# DMFX-1_v1_0.net
KiCad netlist of a schematic drawn in EAGLE
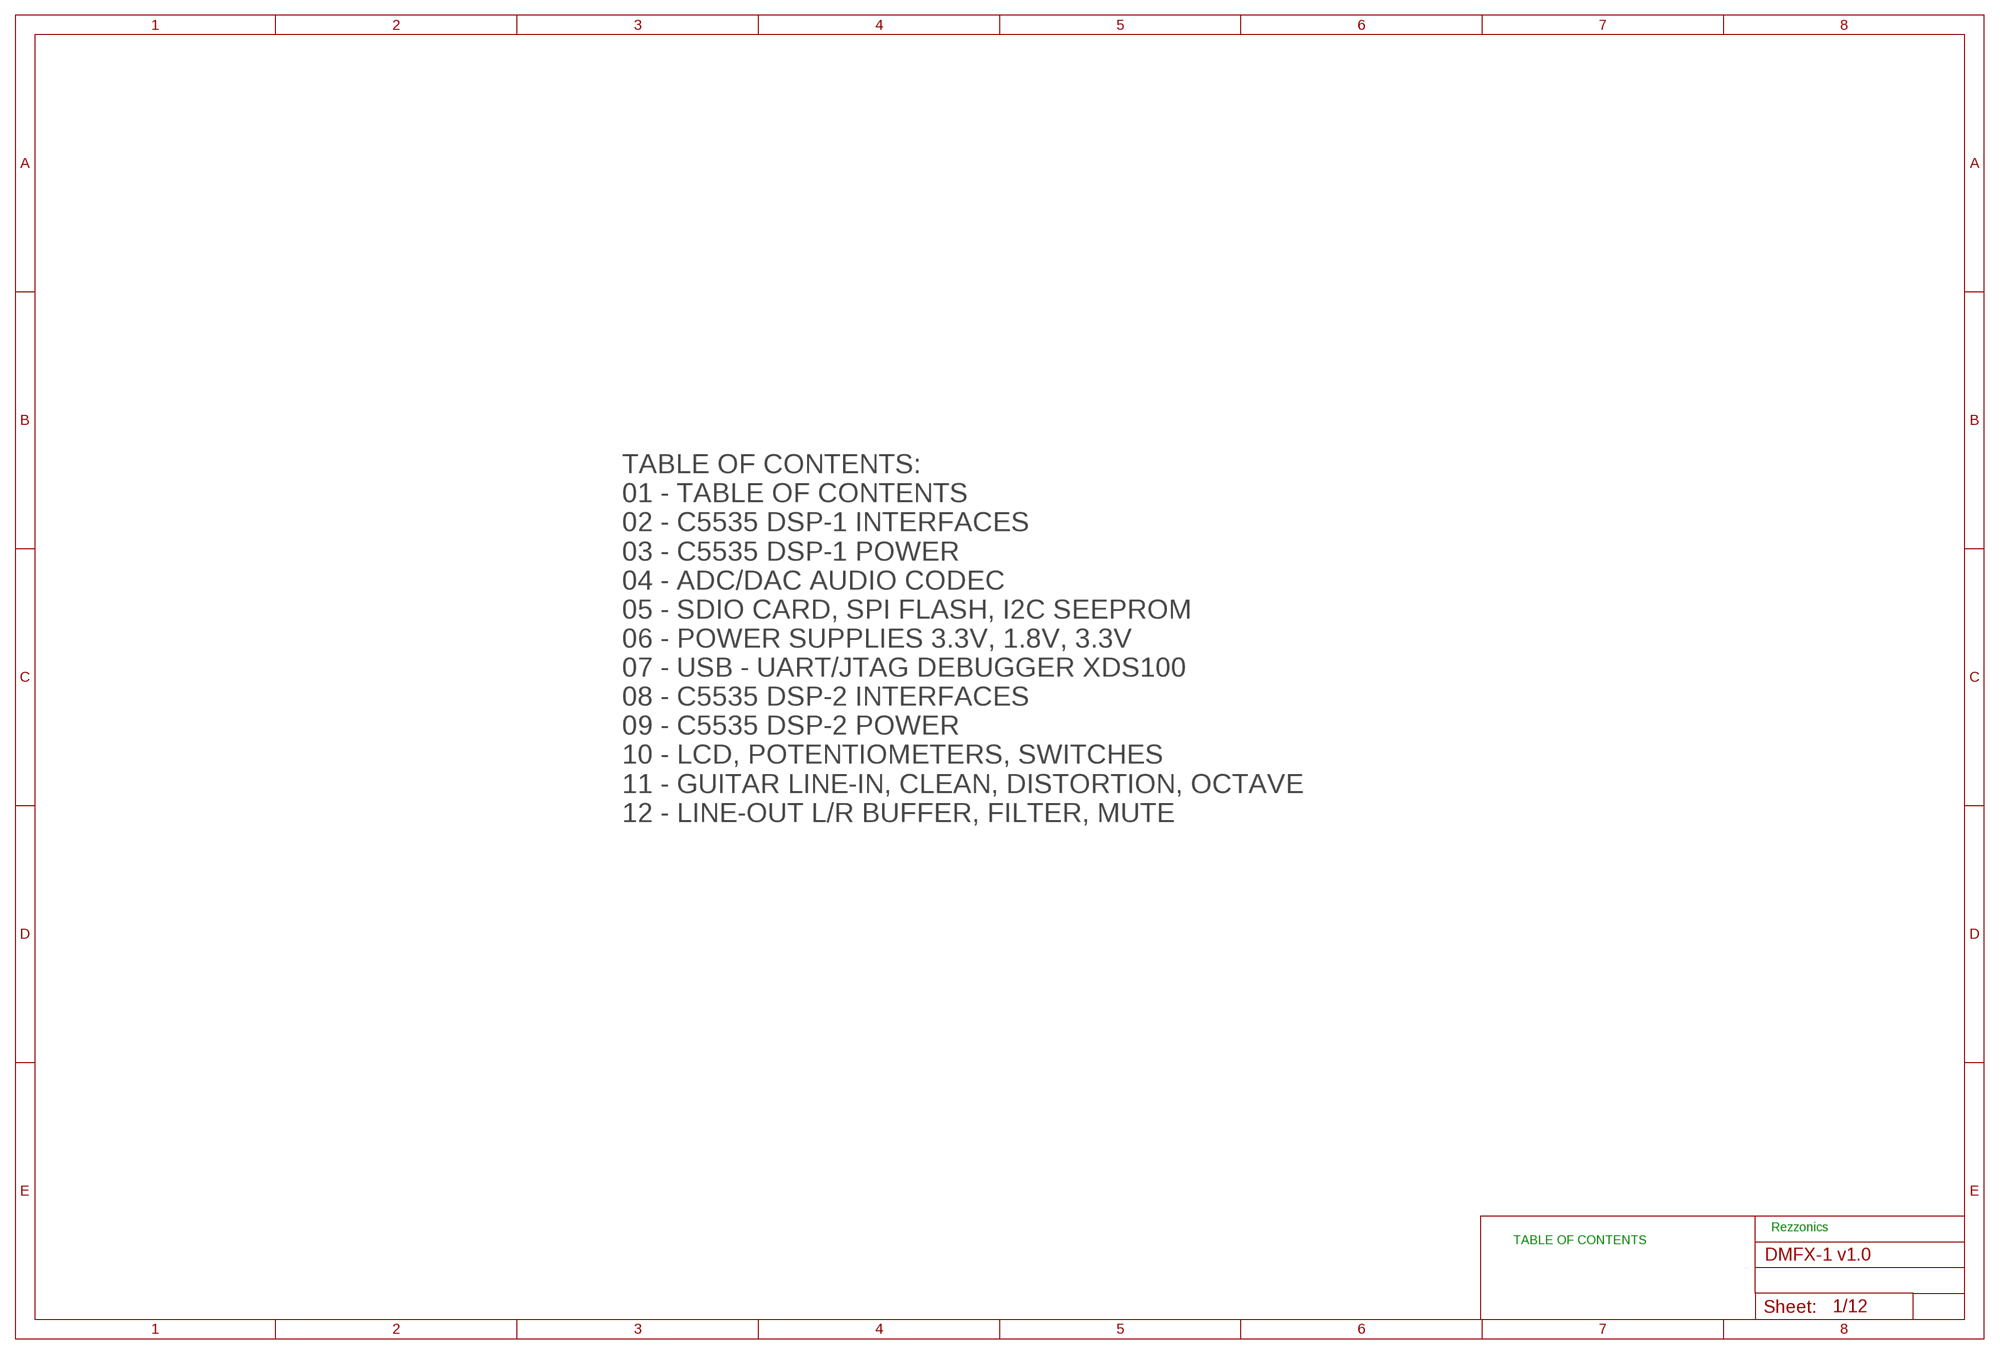
[diagram p0: schematic, sheet 1]
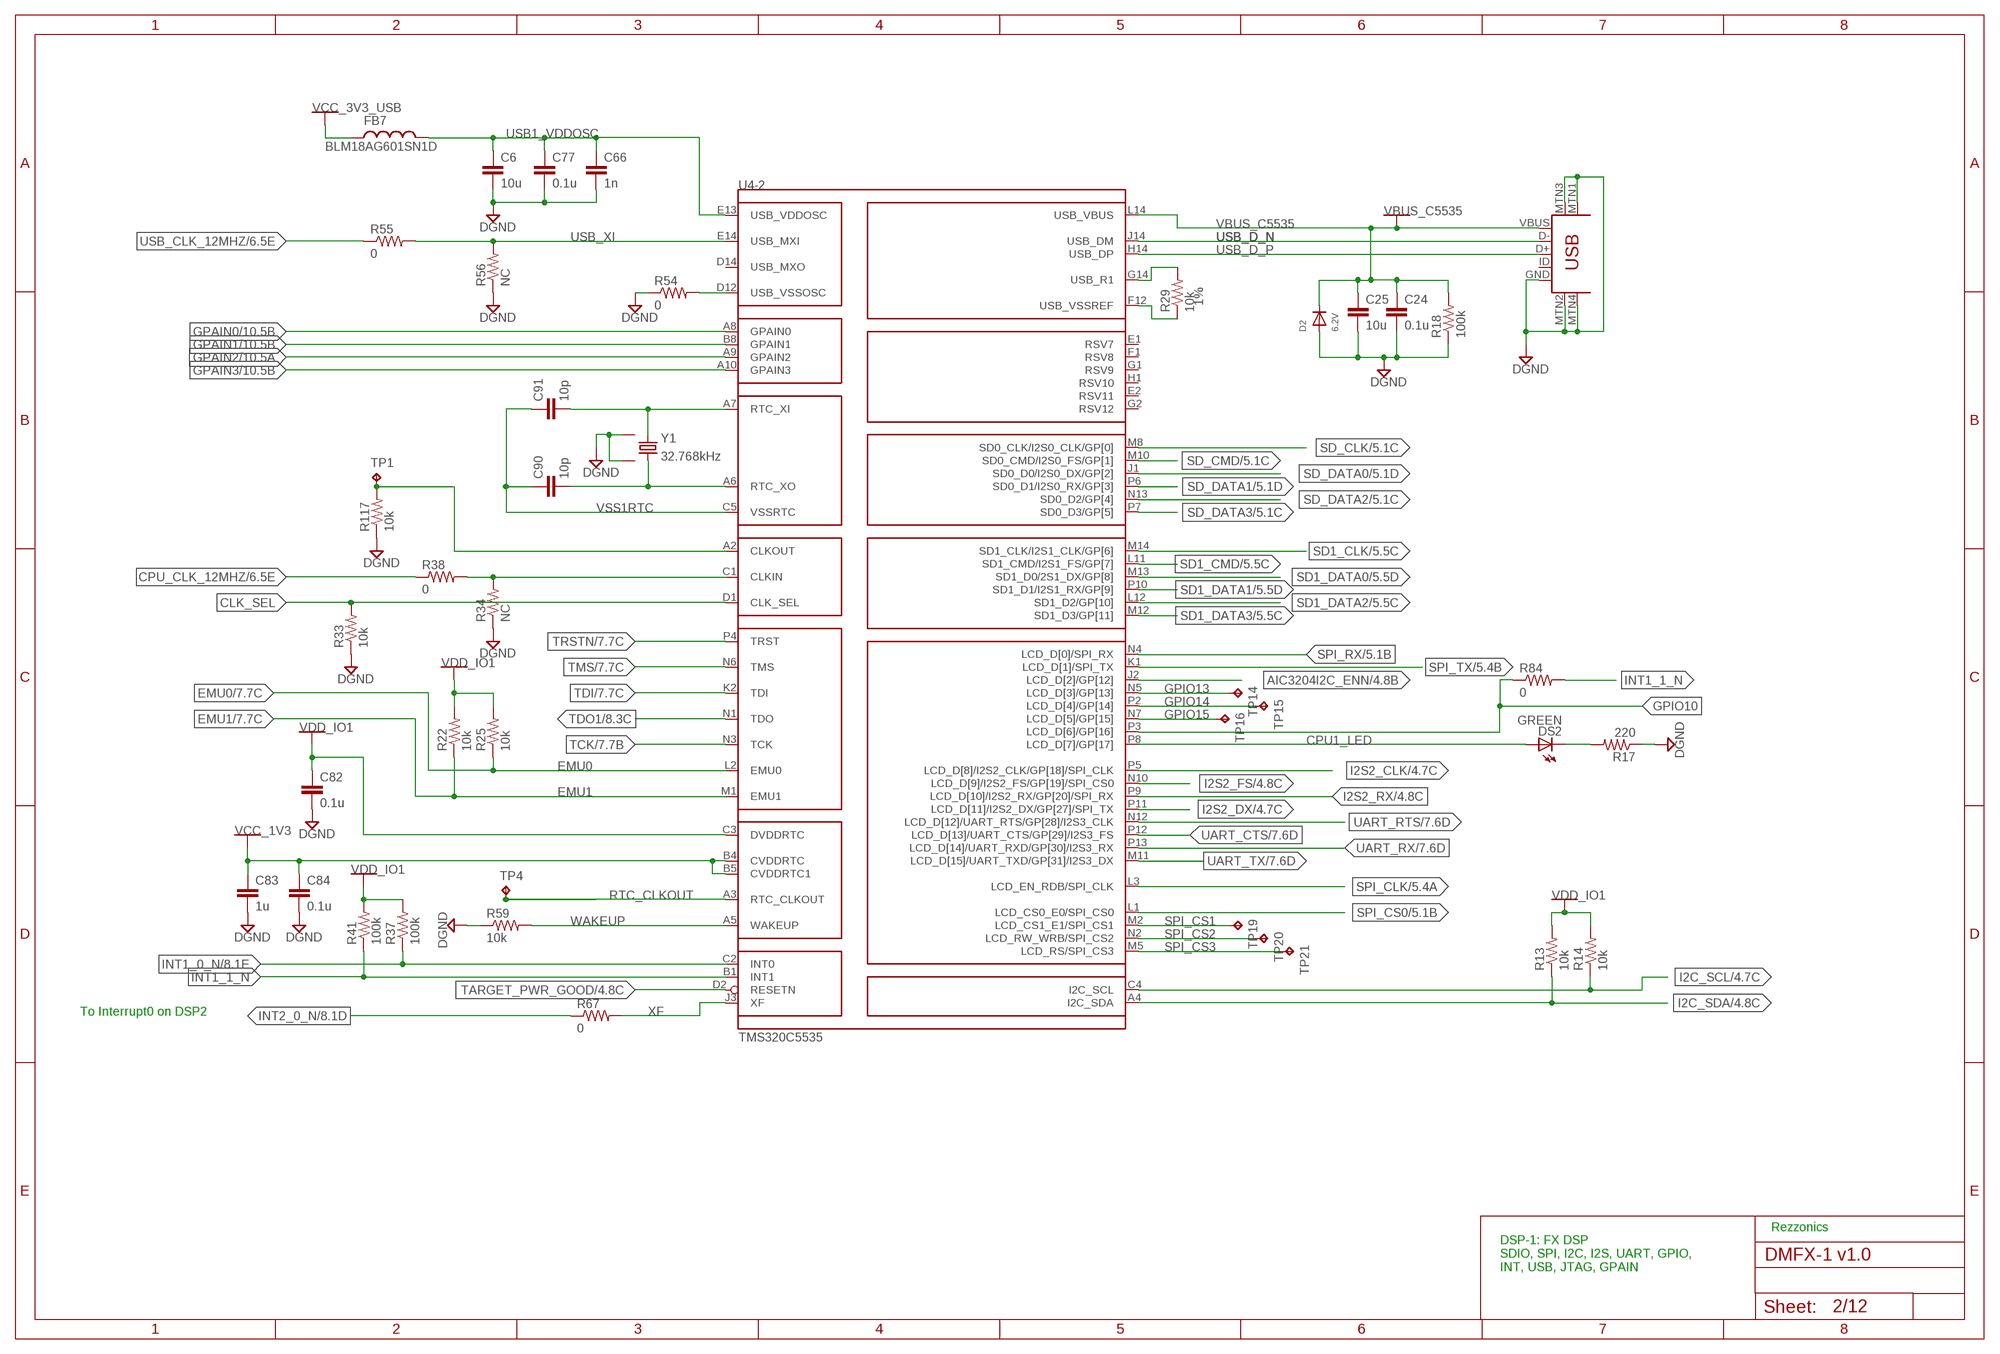
[diagram p1: schematic, sheet 2]
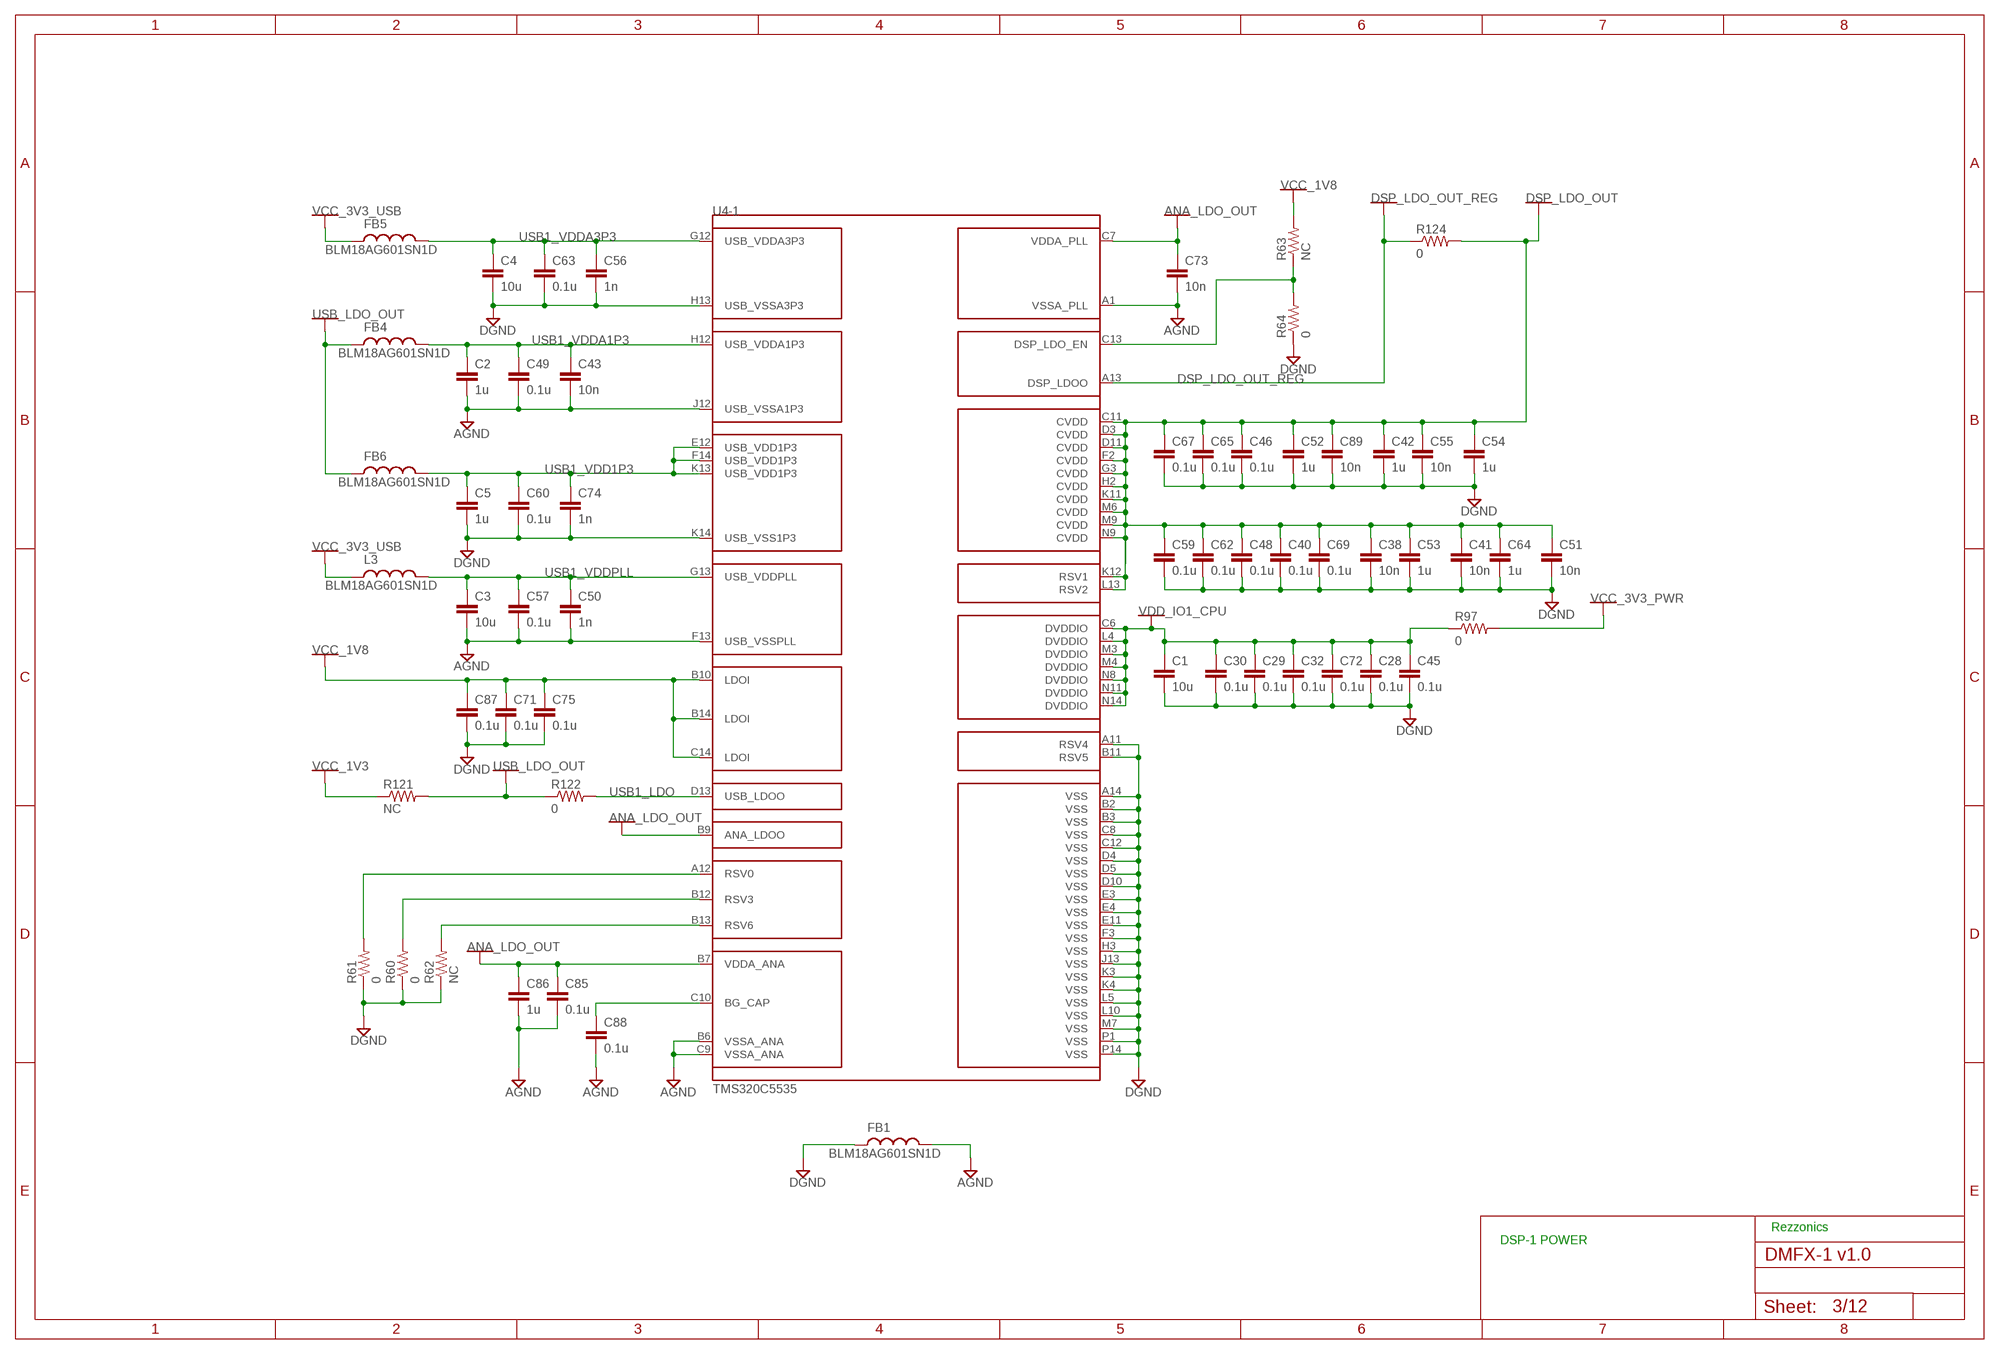
[diagram p2: schematic, sheet 3]
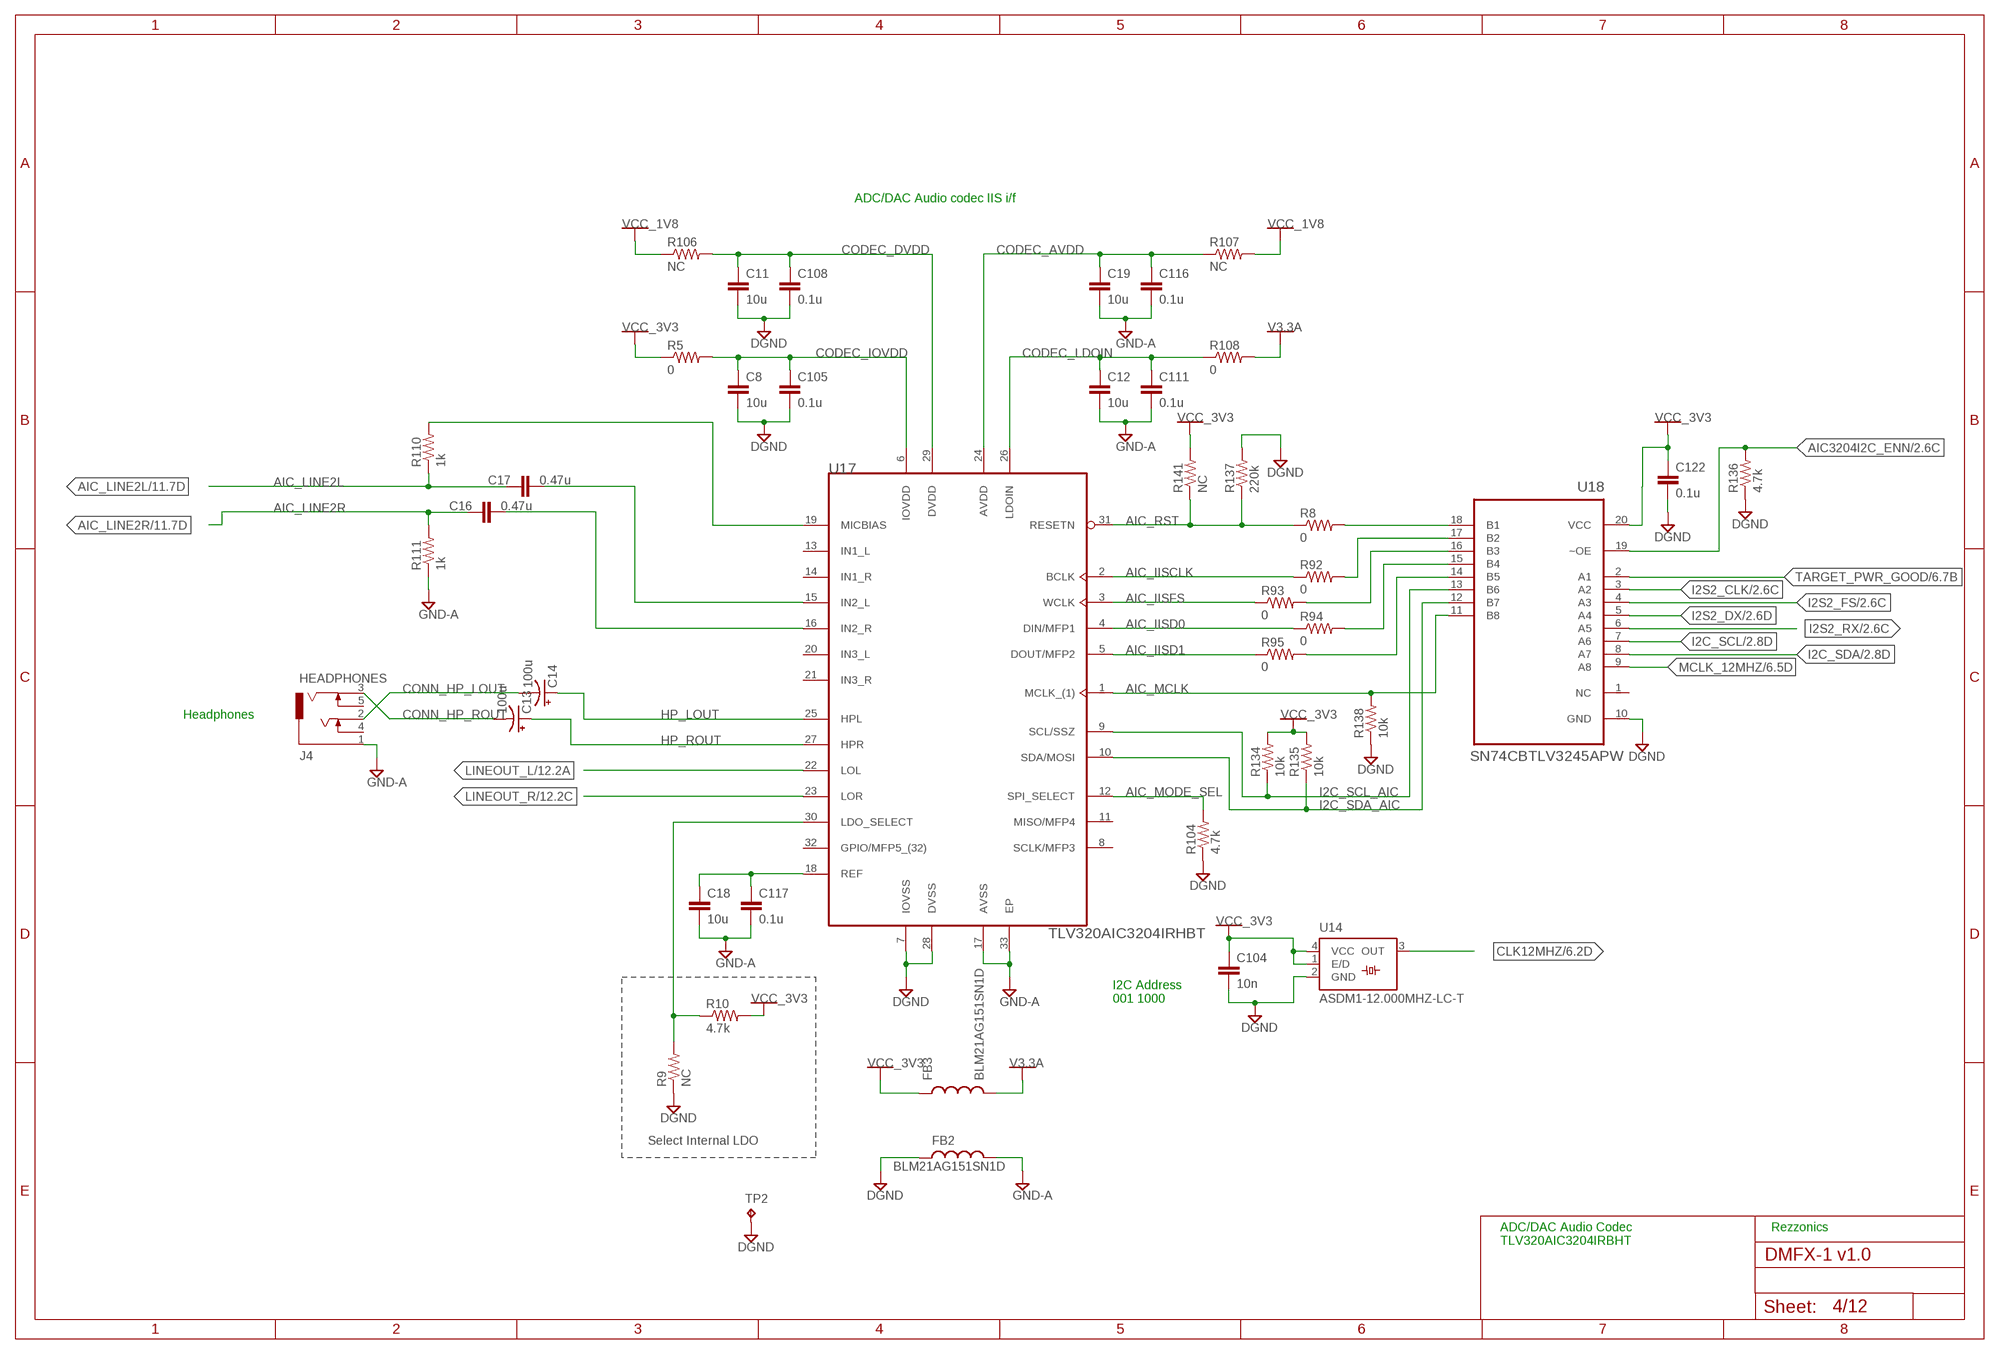
[diagram p3: schematic, sheet 4]
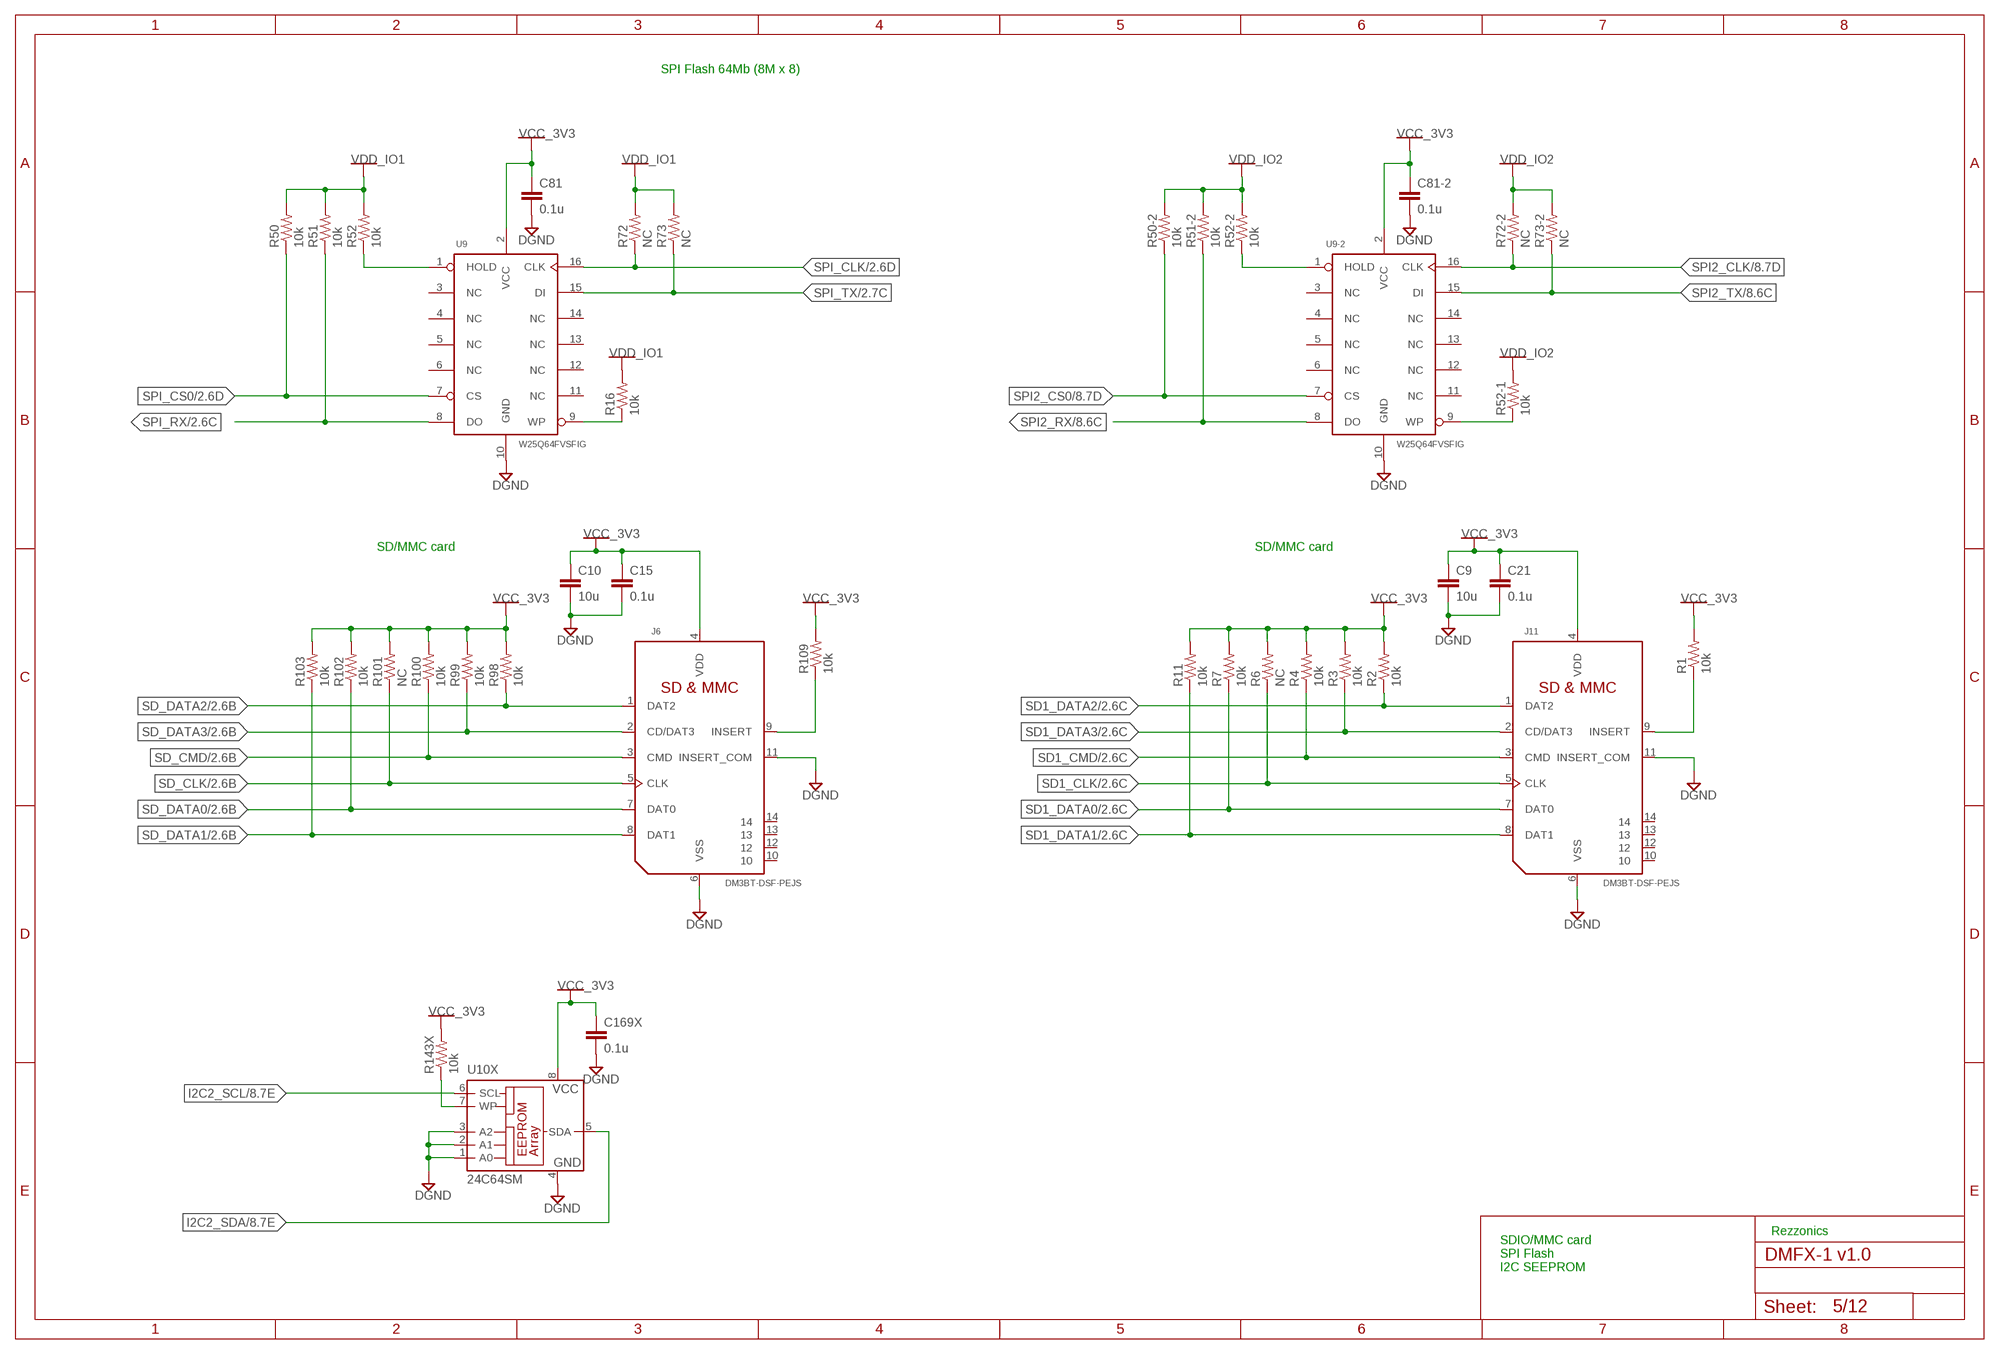
[diagram p4: schematic, sheet 5]
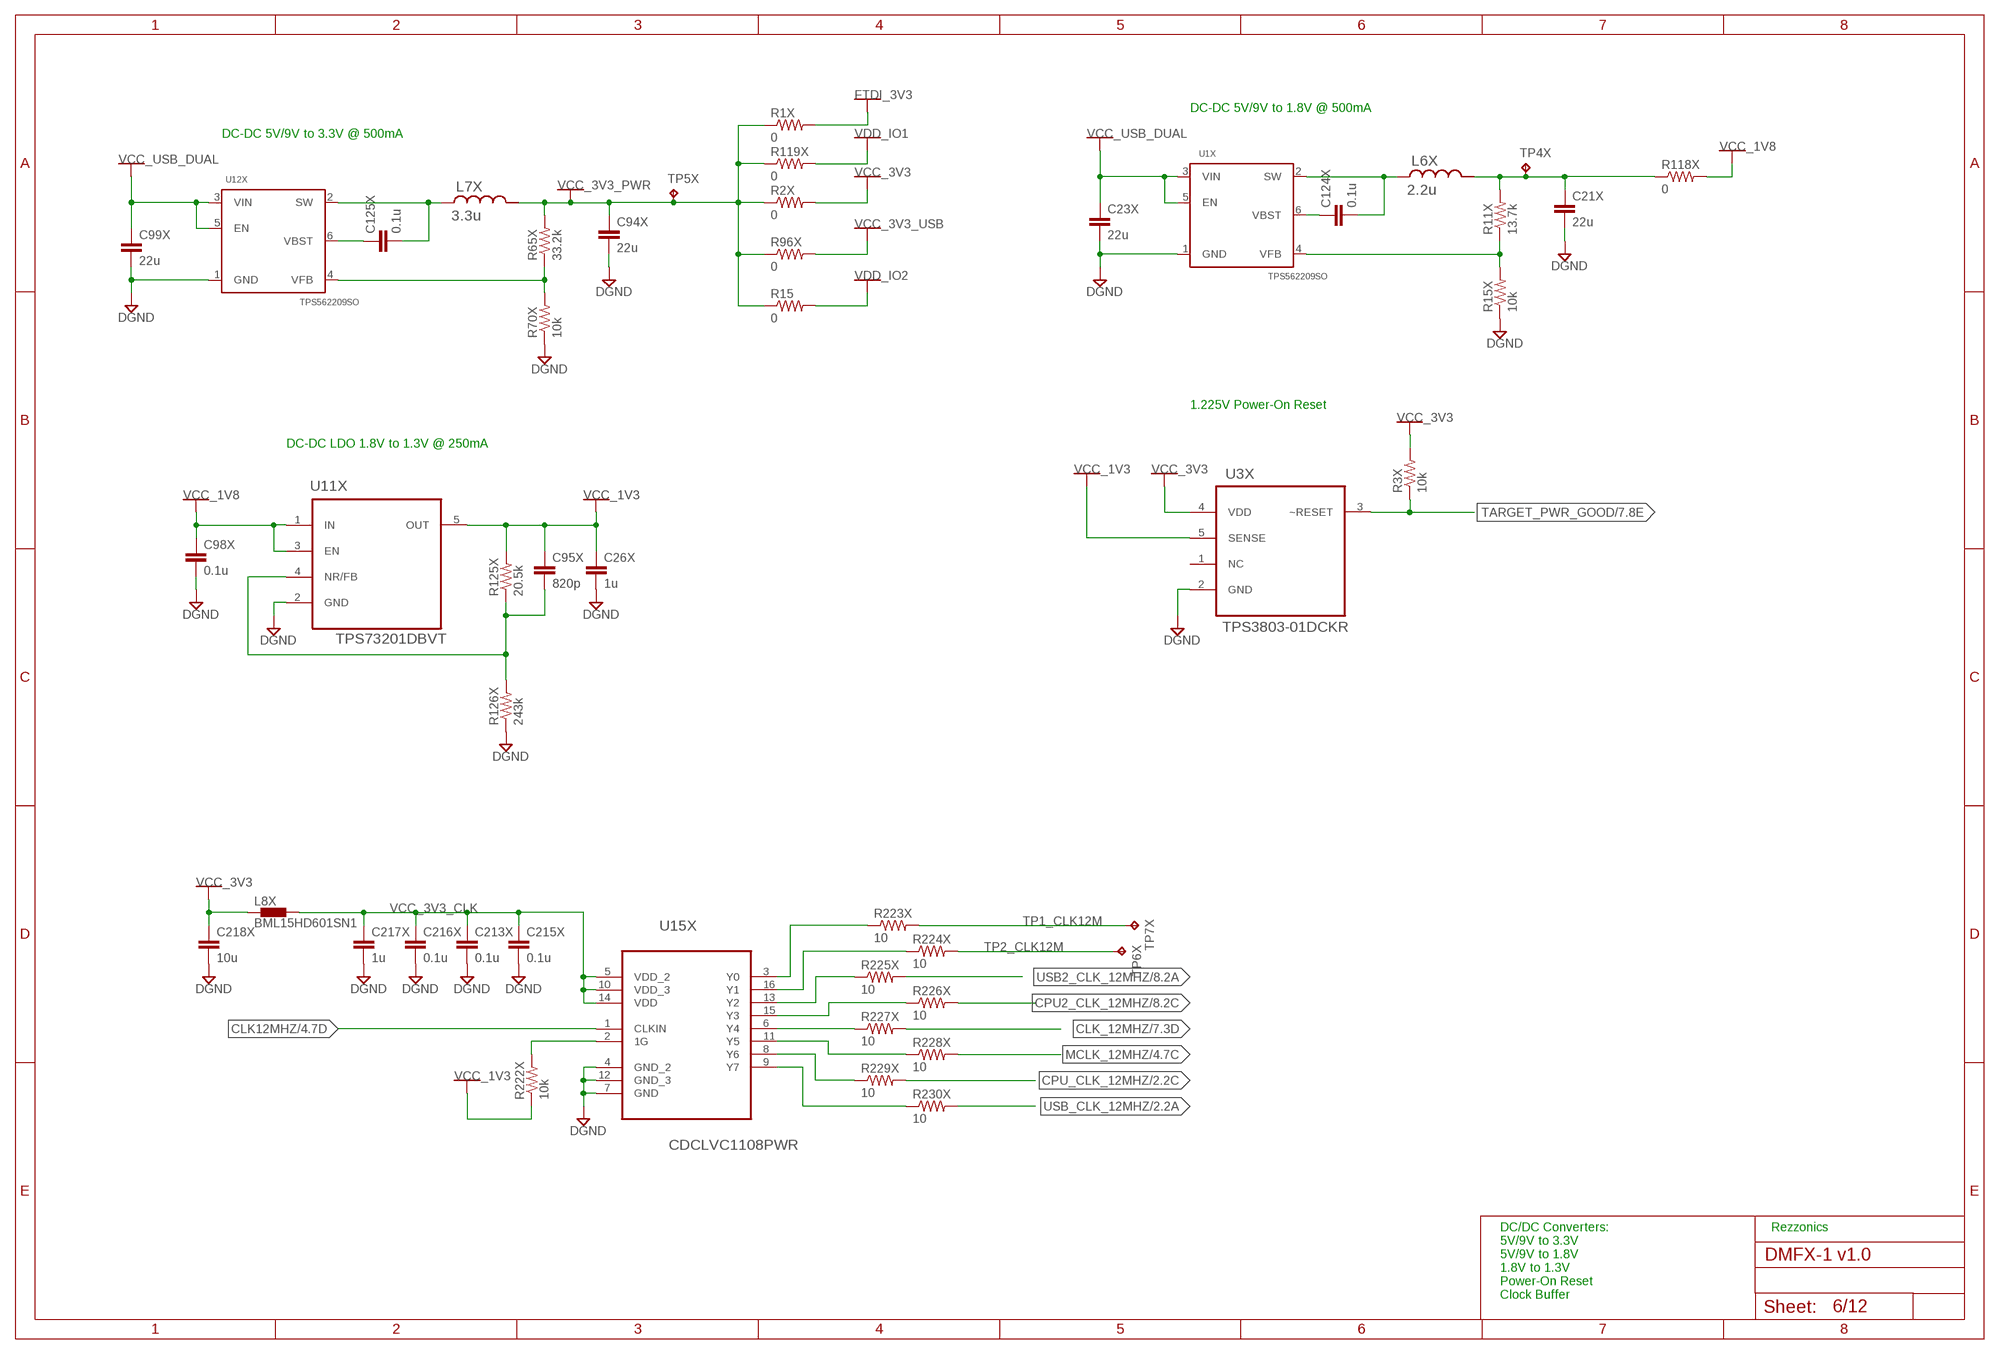
[diagram p5: schematic, sheet 6]
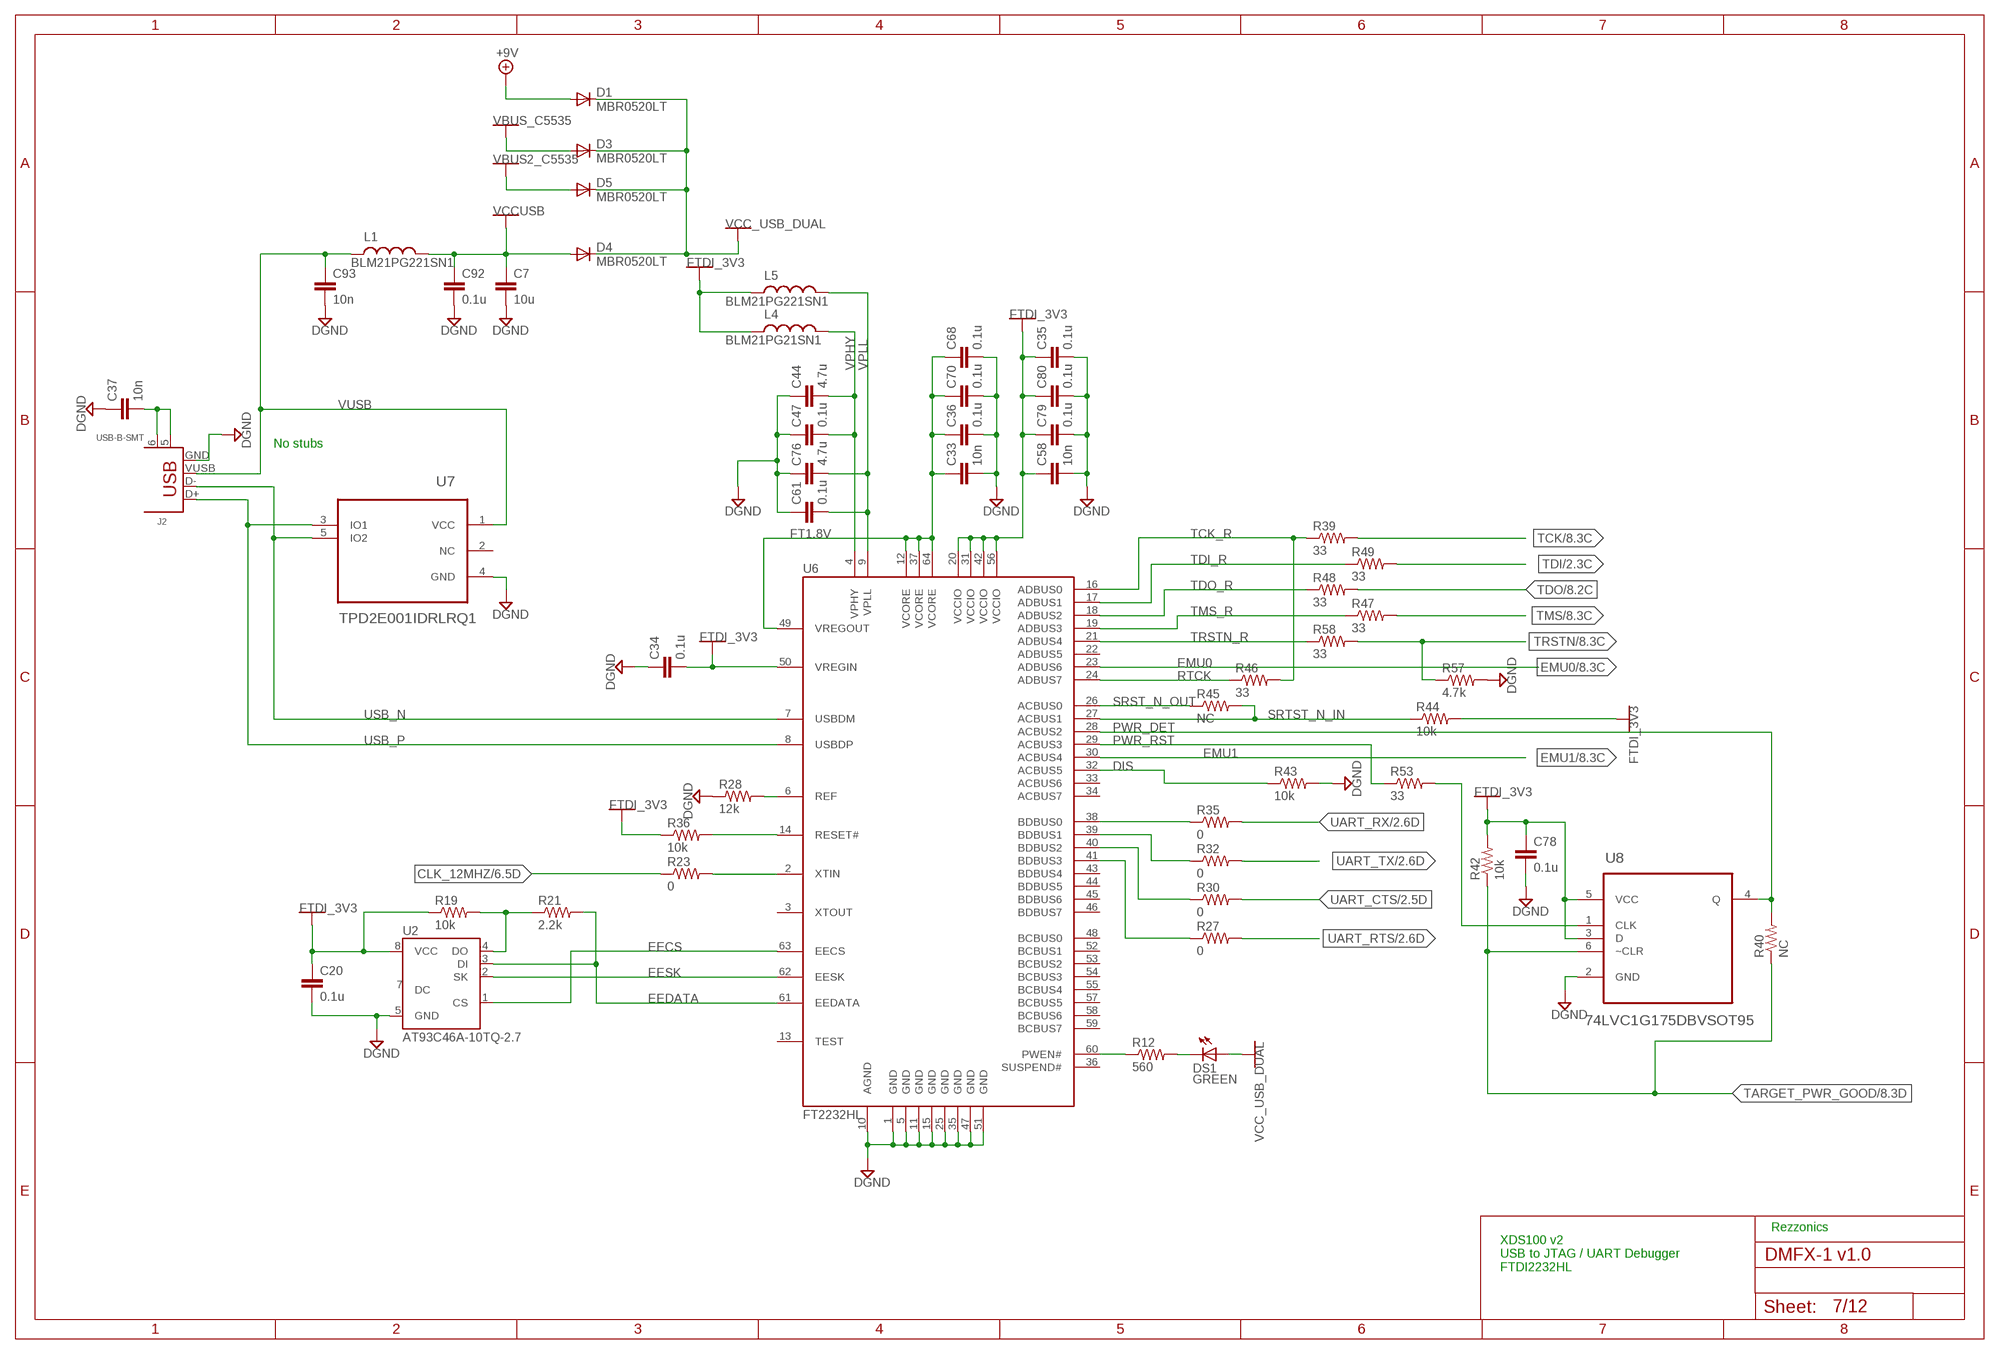
[diagram p6: schematic, sheet 7]
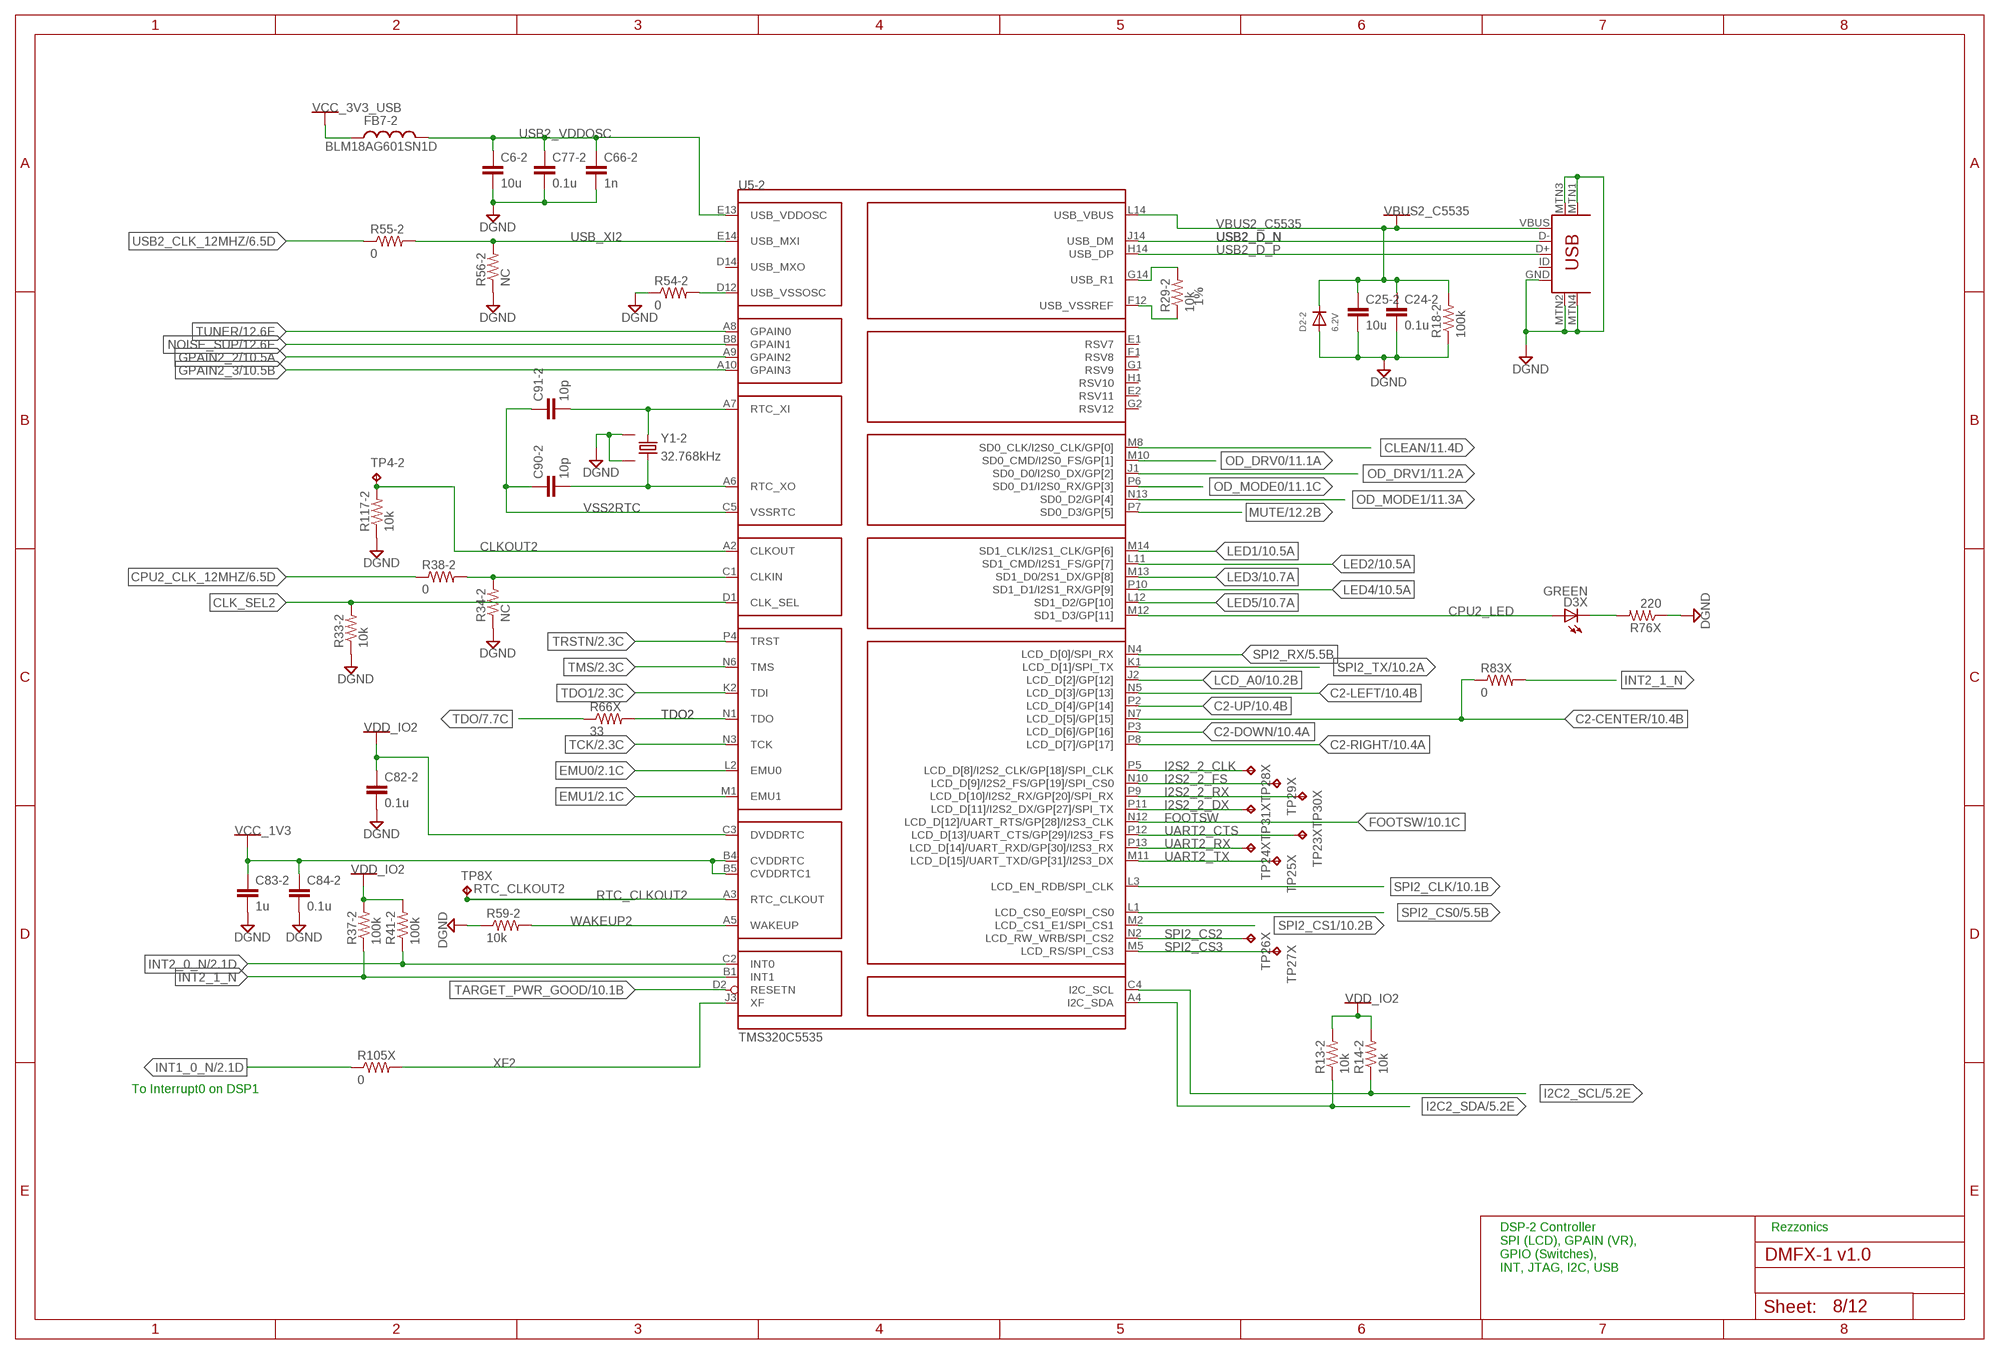
[diagram p7: schematic, sheet 8]
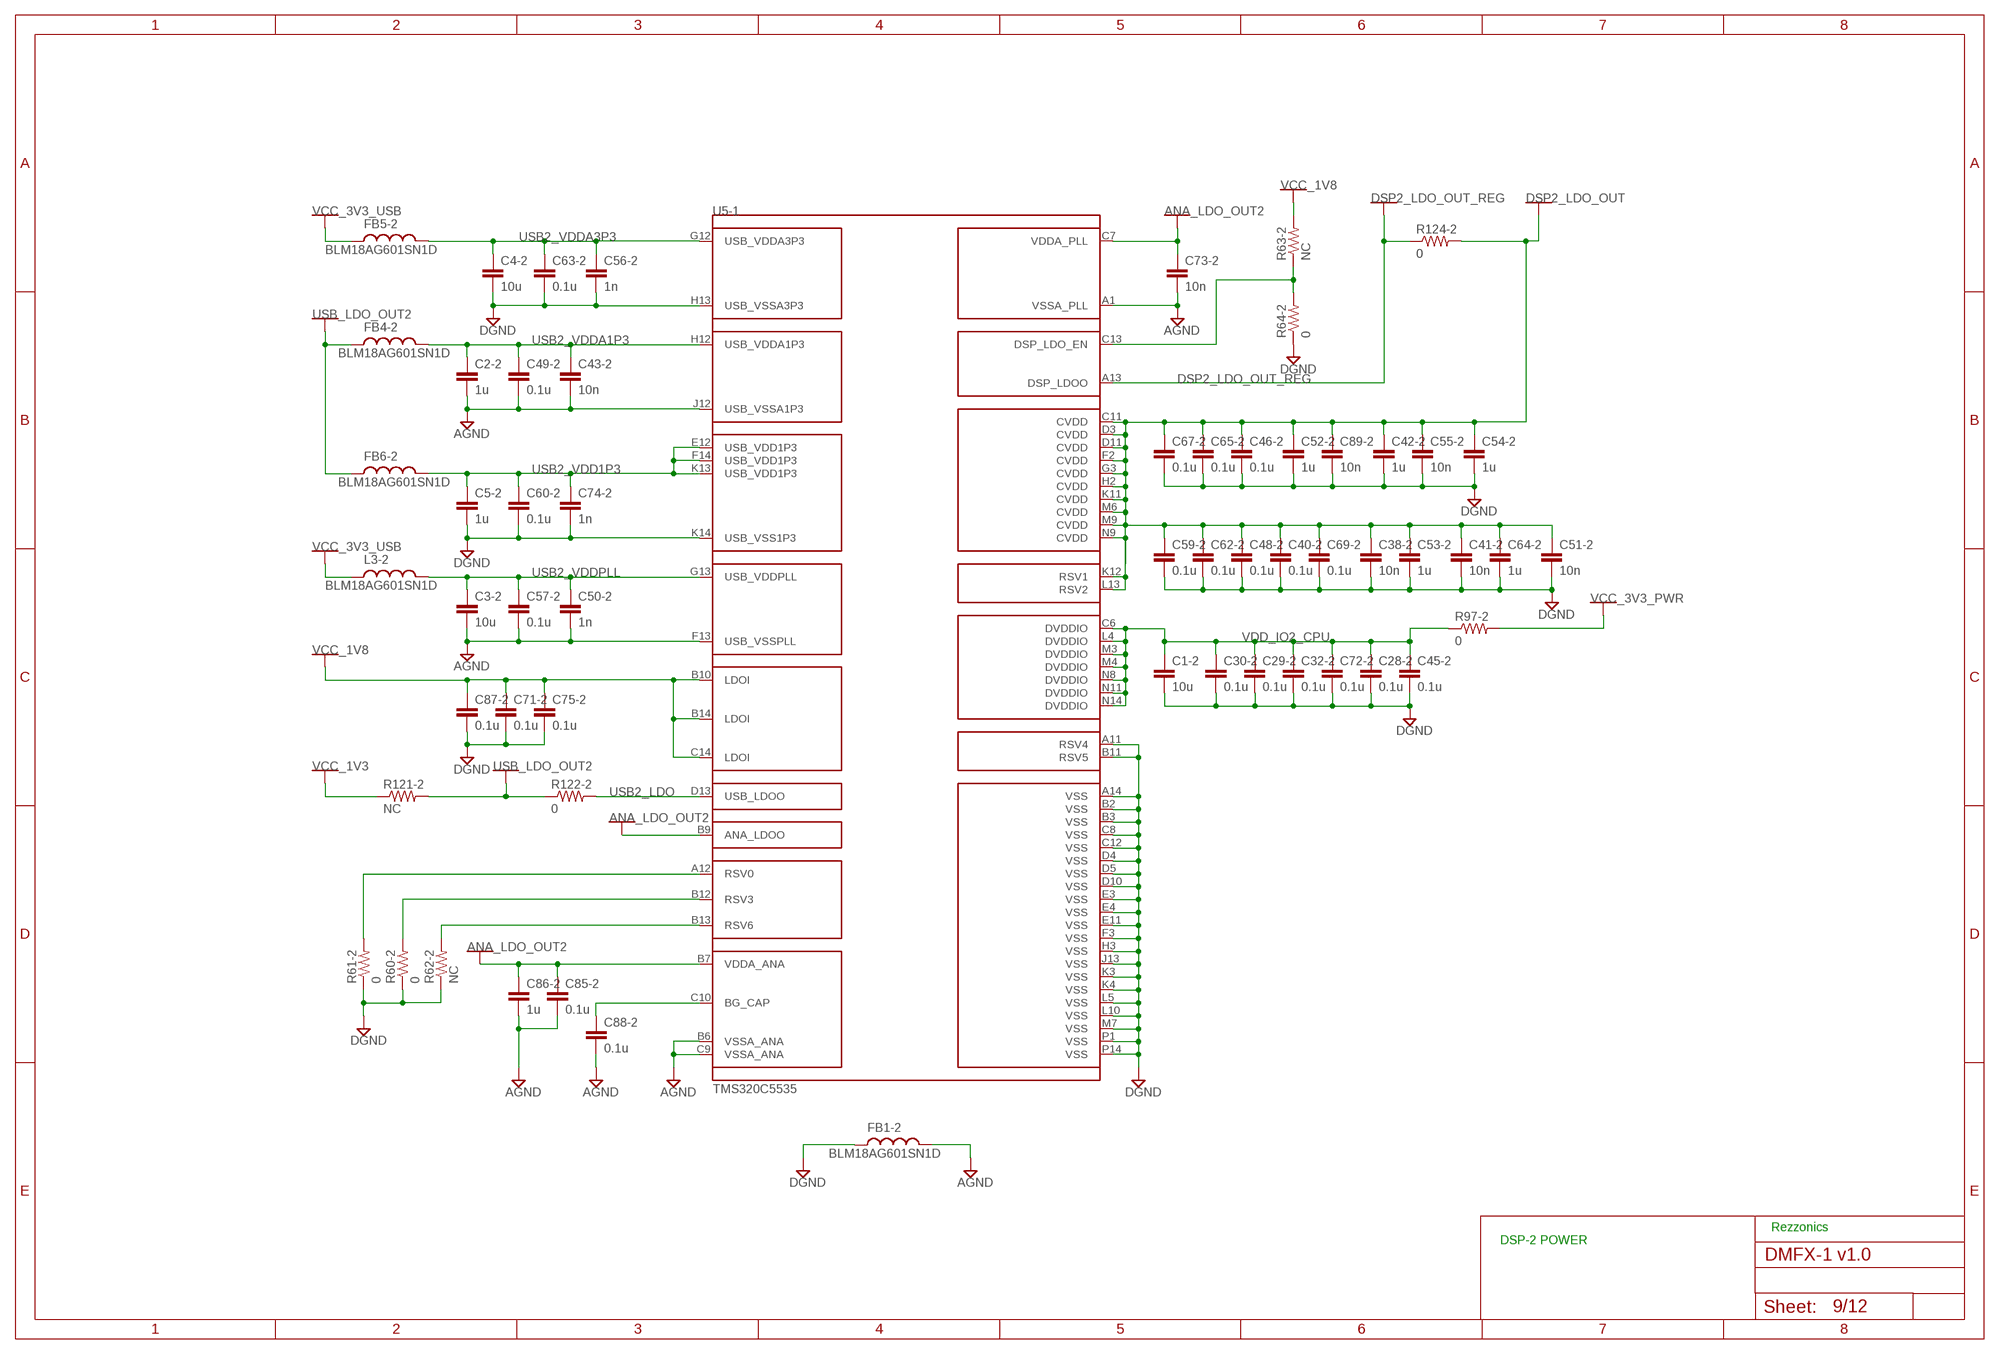
[diagram p8: schematic, sheet 9]
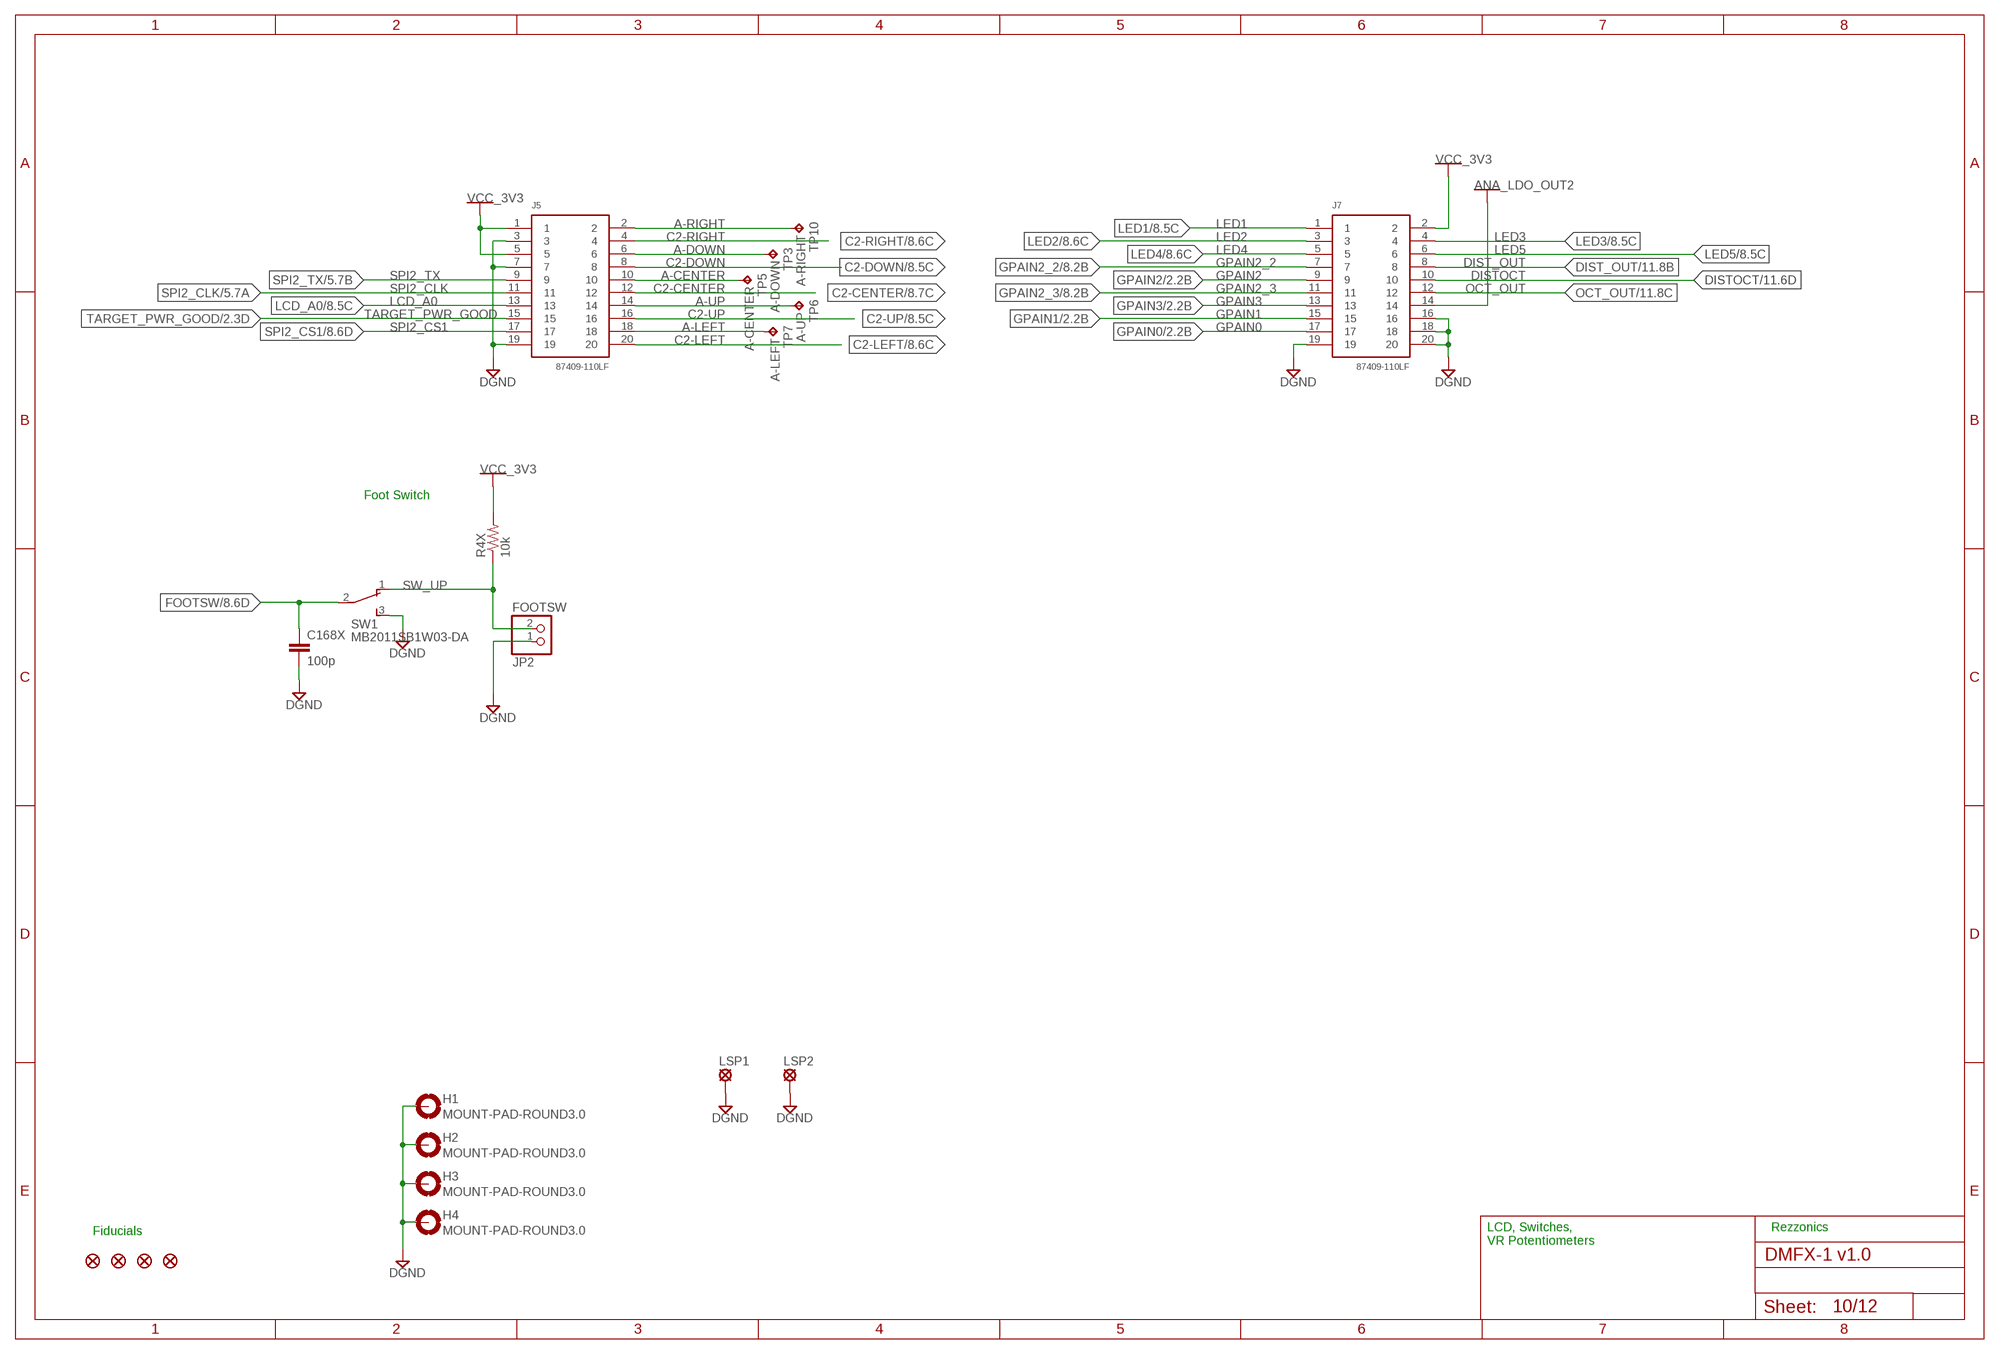
[diagram p9: schematic, sheet 10]
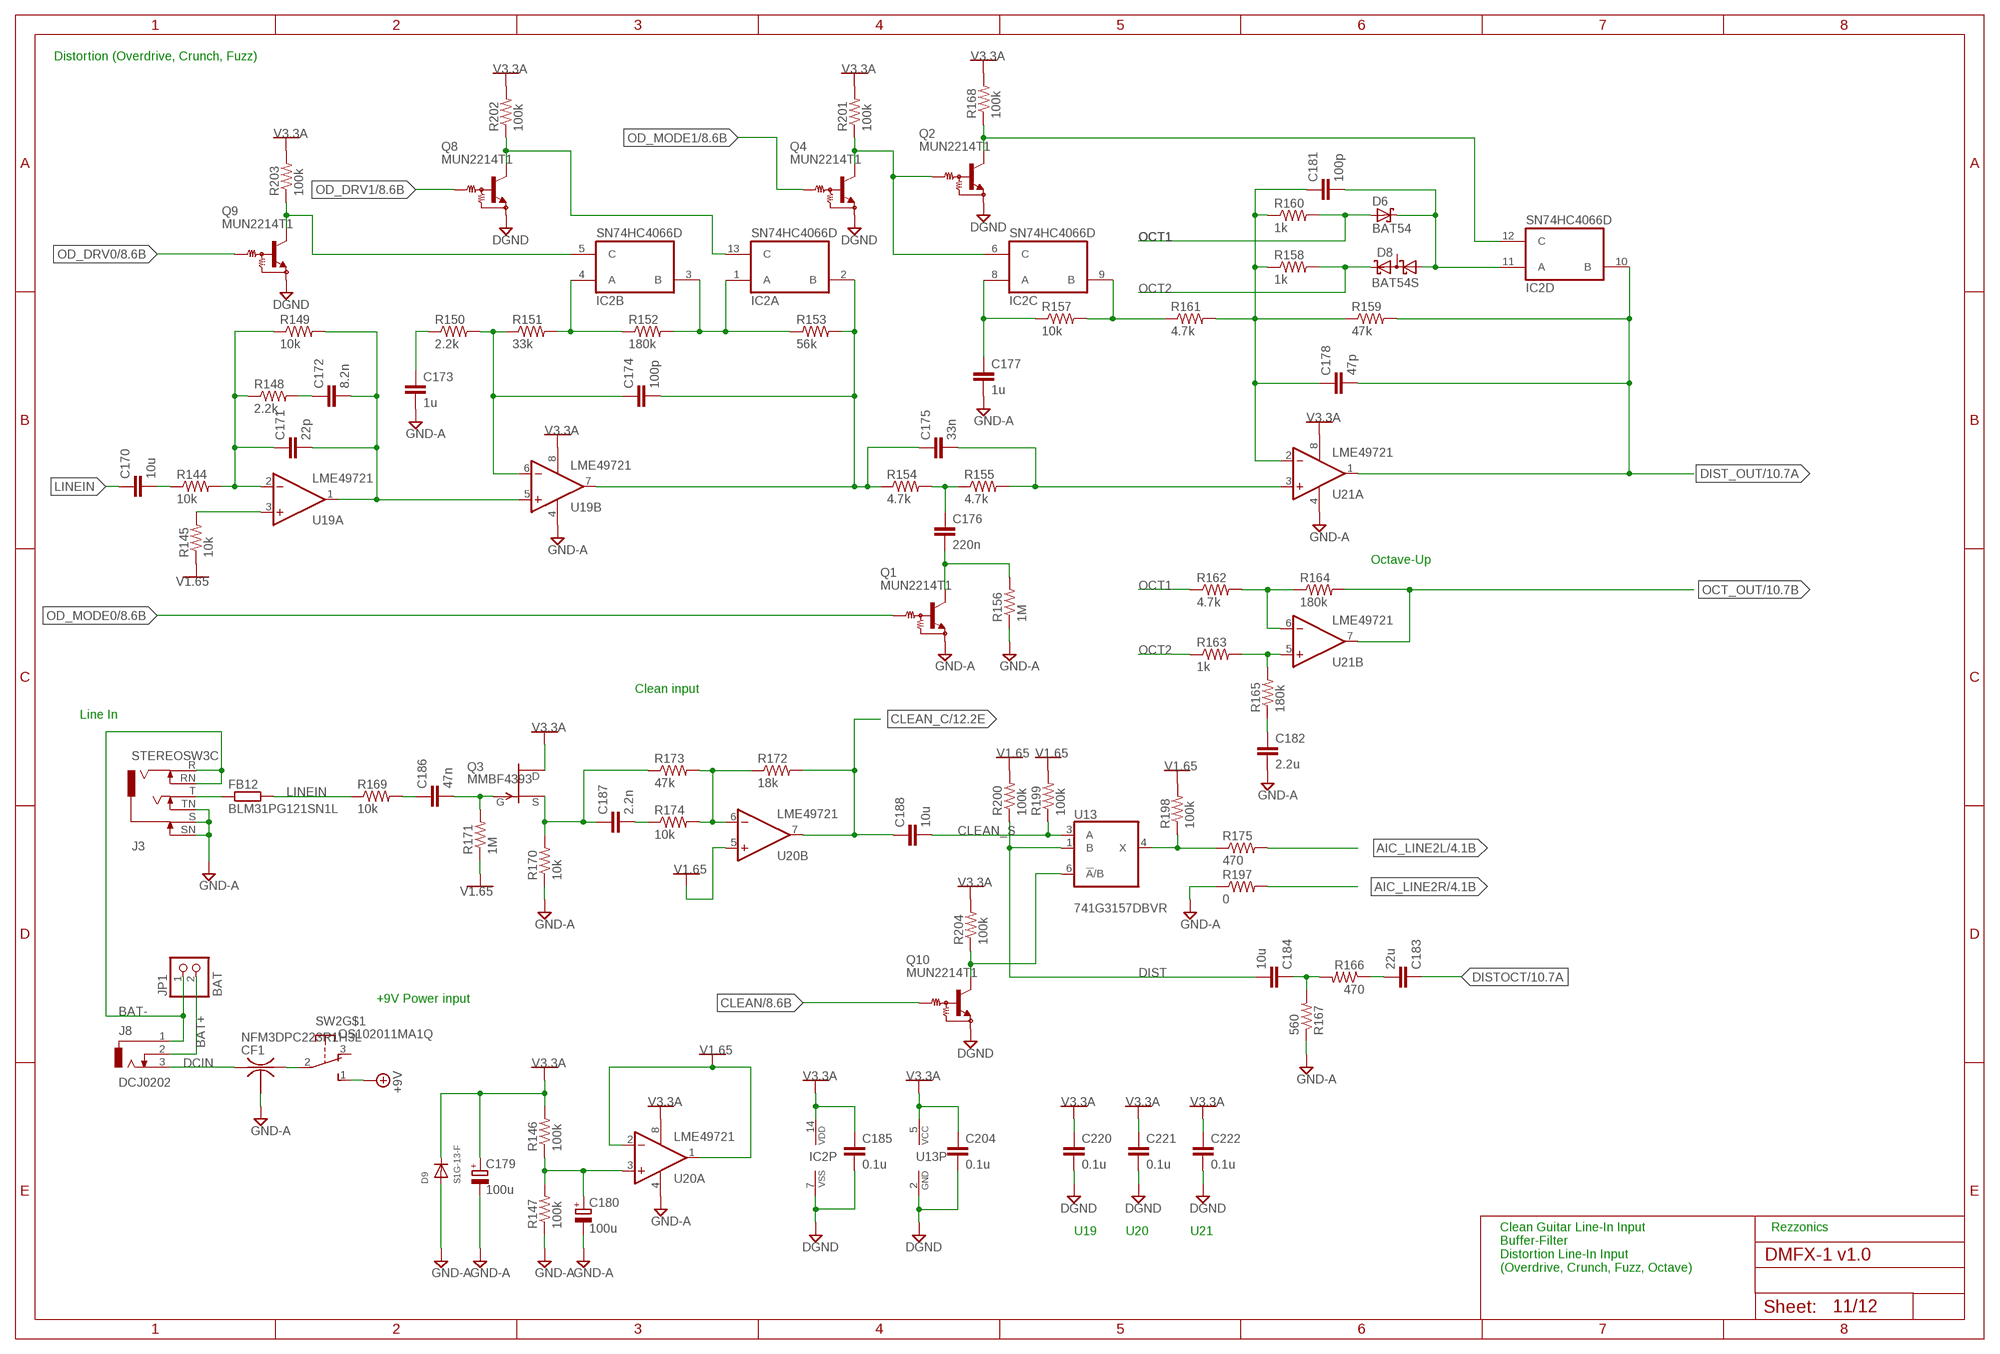
[diagram p10: schematic, sheet 11]
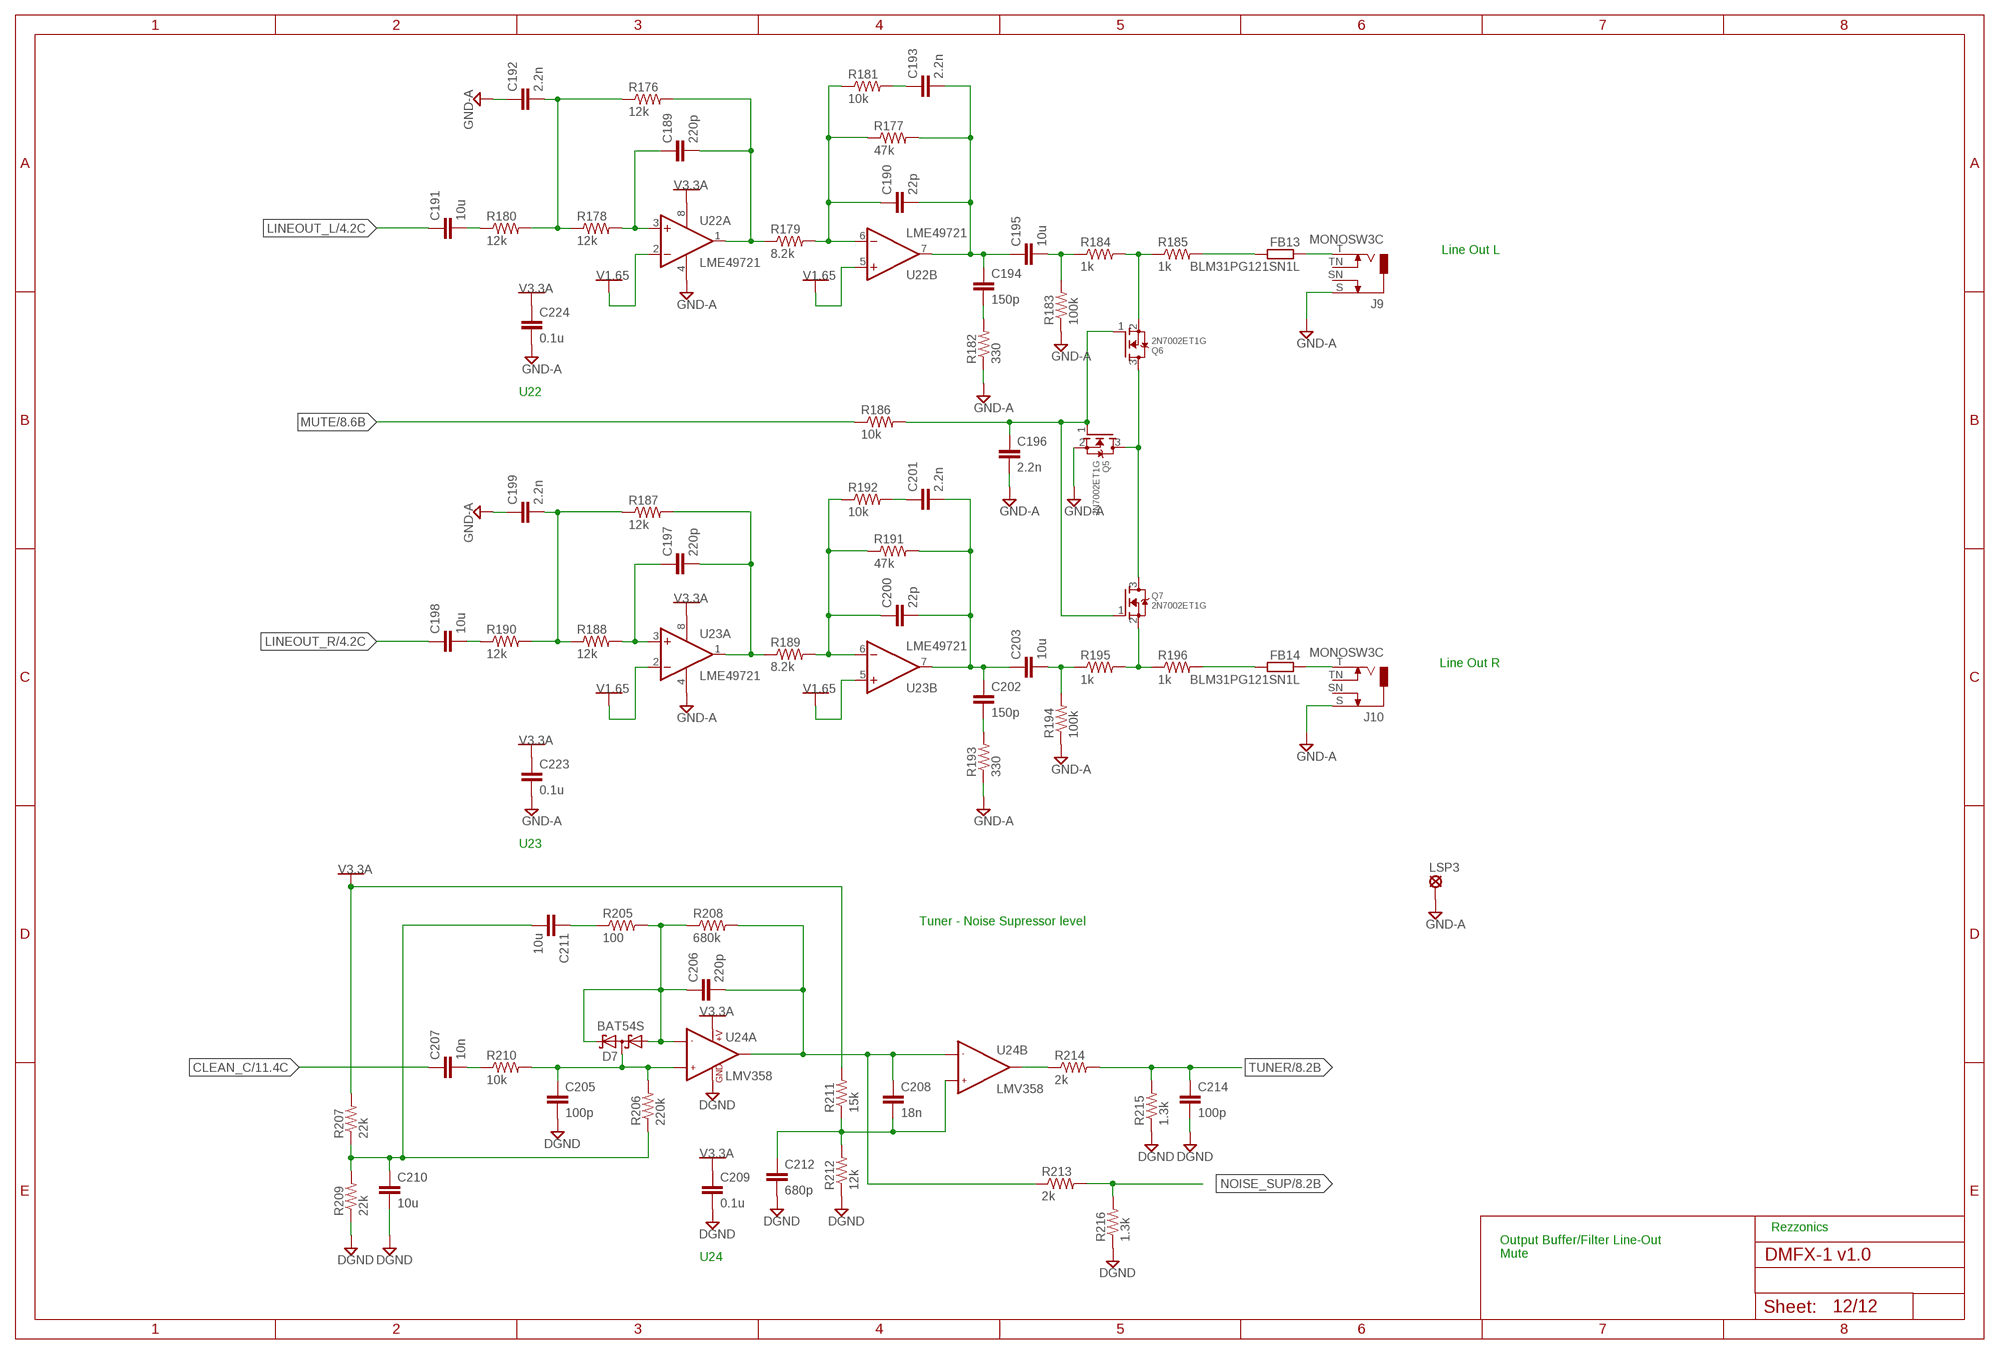
[diagram p11: schematic, sheet 12]

(export (version "E")
  (design (tool "Eeschema 10.0.6"))
  (components
    (comp (ref "C8")
      (value "10u")
      (footprint "eagle-import:C0603K")
      (fields (field (name "MPN") "GRM188R61C106MA73D"))
      (libsource (lib "eagle-import") (part "C-EUC0603K"))
    )
    (comp (ref "C11")
      (value "10u")
      (footprint "eagle-import:C0603K")
      (fields (field (name "MPN") "GRM188R61C106MA73D"))
      (libsource (lib "eagle-import") (part "C-EUC0603K"))
    )
    (comp (ref "C12")
      (value "10u")
      (footprint "eagle-import:C0603K")
      (fields (field (name "MPN") "GRM188R61C106MA73D"))
      (libsource (lib "eagle-import") (part "C-EUC0603K"))
    )
    (comp (ref "C13")
      (value "100u")
      (footprint "eagle-import:1411")
      (fields (field (name "MPN") "ATCC-211B-010-107M-T"))
      (libsource (lib "eagle-import") (part "CPOL-US1411"))
    )
    (comp (ref "C14")
      (value "100u")
      (footprint "eagle-import:1411")
      (fields (field (name "MPN") "ATCC-211B-010-107M-T"))
      (libsource (lib "eagle-import") (part "CPOL-US1411"))
    )
    (comp (ref "C16")
      (value "0.47u")
      (footprint "eagle-import:C0603K")
      (fields (field (name "MPN") "GRM188R71C474KA88D"))
      (libsource (lib "eagle-import") (part "C-EUC0603K"))
    )
    (comp (ref "C17")
      (value "0.47u")
      (footprint "eagle-import:C0603K")
      (fields (field (name "MPN") "GRM188R71C474KA88D"))
      (libsource (lib "eagle-import") (part "C-EUC0603K"))
    )
    (comp (ref "C18")
      (value "10u")
      (footprint "eagle-import:C0603K")
      (fields (field (name "MPN") "GRM188R61C106MA73D"))
      (libsource (lib "eagle-import") (part "C-EUC0603K"))
    )
    (comp (ref "C19")
      (value "10u")
      (footprint "eagle-import:C0603K")
      (fields (field (name "MPN") "GRM188R61C106MA73D"))
      (libsource (lib "eagle-import") (part "C-EUC0603K"))
    )
    (comp (ref "C104")
      (value "10n")
      (footprint "eagle-import:C0402K")
      (fields (field (name "MPN") "GRM155R71E103KA01D"))
      (libsource (lib "eagle-import") (part "resistor_C-EUC0402K"))
    )
    (comp (ref "C105")
      (value "0.1u")
      (footprint "eagle-import:C0402K")
      (fields (field (name "MPN") "GRM155R71C104JA88D"))
      (libsource (lib "eagle-import") (part "resistor_C-EUC0402K"))
    )
    (comp (ref "C108")
      (value "0.1u")
      (footprint "eagle-import:C0402K")
      (fields (field (name "MPN") "GRM155R71C104JA88D"))
      (libsource (lib "eagle-import") (part "resistor_C-EUC0402K"))
    )
    (comp (ref "C111")
      (value "0.1u")
      (footprint "eagle-import:C0402K")
      (fields (field (name "MPN") "GRM155R71C104JA88D"))
      (libsource (lib "eagle-import") (part "resistor_C-EUC0402K"))
    )
    (comp (ref "C116")
      (value "0.1u")
      (footprint "eagle-import:C0402K")
      (fields (field (name "MPN") "GRM155R71C104JA88D"))
      (libsource (lib "eagle-import") (part "resistor_C-EUC0402K"))
    )
    (comp (ref "C117")
      (value "0.1u")
      (footprint "eagle-import:C0402K")
      (fields (field (name "MPN") "GRM155R71C104JA88D"))
      (libsource (lib "eagle-import") (part "resistor_C-EUC0402K"))
    )
    (comp (ref "C122")
      (value "0.1u")
      (footprint "eagle-import:C0402K")
      (fields (field (name "MPN") "GRM155R71C104JA88D"))
      (libsource (lib "eagle-import") (part "resistor_C-EUC0402K"))
    )
    (comp (ref "FB2")
      (value "BLM21AG151SN1D")
      (footprint "eagle-import:0805")
      (libsource (lib "eagle-import") (part "INDUCTOR0805"))
    )
    (comp (ref "FB3")
      (value "BLM21AG151SN1D")
      (footprint "eagle-import:0805")
      (libsource (lib "eagle-import") (part "INDUCTOR0805"))
    )
    (comp (ref "J4")
      (value "HEADPHONES")
      (footprint "eagle-import:AUDIO-JACK-3.5MM-SMD")
      (fields (field (name "MPN") "SJ1-3515-SMT-TR"))
      (libsource (lib "eagle-import") (part "AUDIOJACK3_5SMD"))
    )
    (comp (ref "R5")
      (value "0")
      (footprint "eagle-import:0402-RES")
      (fields (field (name "MPN") "ERJ-2GE0R00X"))
      (libsource (lib "eagle-import") (part "RESISTOR0402-RES"))
    )
    (comp (ref "R8")
      (value "0")
      (footprint "eagle-import:0402-RES")
      (fields (field (name "MPN") "ERJ-2GE0R00X"))
      (libsource (lib "eagle-import") (part "RESISTOR0402-RES"))
    )
    (comp (ref "R9")
      (value "NC")
      (footprint "eagle-import:0603-RES")
      (libsource (lib "eagle-import") (part "RESISTOR0603-RES"))
    )
    (comp (ref "R10")
      (value "4.7k")
      (footprint "eagle-import:0603-RES")
      (fields (field (name "MPN") "ERJ-3EKF4701V"))
      (libsource (lib "eagle-import") (part "RESISTOR0603-RES"))
    )
    (comp (ref "R92")
      (value "0")
      (footprint "eagle-import:0402-RES")
      (fields (field (name "MPN") "ERJ-2GE0R00X"))
      (libsource (lib "eagle-import") (part "RESISTOR0402-RES"))
    )
    (comp (ref "R93")
      (value "0")
      (footprint "eagle-import:0402-RES")
      (fields (field (name "MPN") "ERJ-2GE0R00X"))
      (libsource (lib "eagle-import") (part "RESISTOR0402-RES"))
    )
    (comp (ref "R94")
      (value "0")
      (footprint "eagle-import:0402-RES")
      (fields (field (name "MPN") "ERJ-2GE0R00X"))
      (libsource (lib "eagle-import") (part "RESISTOR0402-RES"))
    )
    (comp (ref "R95")
      (value "0")
      (footprint "eagle-import:0402-RES")
      (fields (field (name "MPN") "ERJ-2GE0R00X"))
      (libsource (lib "eagle-import") (part "RESISTOR0402-RES"))
    )
    (comp (ref "R104")
      (value "4.7k")
      (footprint "eagle-import:0402-RES")
      (fields (field (name "MPN") "ERJ-2RKF4701X"))
      (libsource (lib "eagle-import") (part "RESISTOR0402-RES"))
    )
    (comp (ref "R106")
      (value "NC")
      (footprint "eagle-import:0402-RES")
      (libsource (lib "eagle-import") (part "RESISTOR0402-RES"))
    )
    (comp (ref "R107")
      (value "NC")
      (footprint "eagle-import:0402-RES")
      (libsource (lib "eagle-import") (part "RESISTOR0402-RES"))
    )
    (comp (ref "R108")
      (value "0")
      (footprint "eagle-import:0402-RES")
      (fields (field (name "MPN") "ERJ-2GE0R00X"))
      (libsource (lib "eagle-import") (part "RESISTOR0402-RES"))
    )
    (comp (ref "R110")
      (value "1k")
      (footprint "eagle-import:0402-RES")
      (fields (field (name "MPN") "ERJ-2RKF1001X"))
      (libsource (lib "eagle-import") (part "RESISTOR0402-RES"))
    )
    (comp (ref "R111")
      (value "1k")
      (footprint "eagle-import:0402-RES")
      (fields (field (name "MPN") "ERJ-2RKF1001X"))
      (libsource (lib "eagle-import") (part "RESISTOR0402-RES"))
    )
    (comp (ref "R134")
      (value "10k")
      (footprint "eagle-import:0402-RES")
      (fields (field (name "MPN") "ERJ-2RKF1002X"))
      (libsource (lib "eagle-import") (part "RESISTOR0402-RES"))
    )
    (comp (ref "R135")
      (value "10k")
      (footprint "eagle-import:0402-RES")
      (fields (field (name "MPN") "ERJ-2RKF1002X"))
      (libsource (lib "eagle-import") (part "RESISTOR0402-RES"))
    )
    (comp (ref "R136")
      (value "4.7k")
      (footprint "eagle-import:0402-RES")
      (fields (field (name "MPN") "ERJ-2RKF4701X"))
      (libsource (lib "eagle-import") (part "RESISTOR0402-RES"))
    )
    (comp (ref "R137")
      (value "220k")
      (footprint "eagle-import:0402-RES")
      (fields (field (name "MPN") "ERJ-2RKF2203X"))
      (libsource (lib "eagle-import") (part "RESISTOR0402-RES"))
    )
    (comp (ref "R138")
      (value "10k")
      (footprint "eagle-import:0402-RES")
      (fields (field (name "MPN") "ERJ-2RKF1002X"))
      (libsource (lib "eagle-import") (part "RESISTOR0402-RES"))
    )
    (comp (ref "R141")
      (value "NC")
      (footprint "eagle-import:0402-RES")
      (libsource (lib "eagle-import") (part "RESISTOR0402-RES"))
    )
    (comp (ref "TP2")
      (value "TPTP06R")
      (footprint "eagle-import:TP06R")
      (fields (field (name "TP_SIGNAL_NAME") "GND"))
      (libsource (lib "eagle-import") (part "TPTP06R"))
    )
    (comp (ref "U14")
      (value "ASDM1-12.000MHZ-LC-T")
      (footprint "eagle-import:ASDM1")
      (fields
        (field (name "MF") "Abracon")
        (field (name "MPN") "ASDM")
        (field (name "MPN_1") "ASDM1-12.000MHZ-LC-T")
      )
      (libsource (lib "eagle-import") (part "ASDM"))
    )
    (comp (ref "U17")
      (value "TLV320AIC3204IRHBT")
      (footprint "eagle-import:QFN50P500X500X100-33N")
      (fields (field (name "MPN") "TLV320AIC3204IRHBT"))
      (libsource (lib "eagle-import") (part "TLV320AIC3204IRHBT"))
    )
    (comp (ref "U18")
      (value "SN74CBTLV3245APW")
      (footprint "eagle-import:SOP65P640X120-20N")
      (fields (field (name "MPN") "SN74CBTLV3245APWR"))
      (libsource (lib "eagle-import") (part "SN74CBTLV3245APW"))
    )
    (comp (ref "C1")
      (value "10u")
      (footprint "eagle-import:C0603K")
      (fields (field (name "MPN") "GRM188R61C106MA73D"))
      (libsource (lib "eagle-import") (part "C-EUC0603K"))
    )
    (comp (ref "C2")
      (value "1u")
      (footprint "eagle-import:C0402K")
      (fields (field (name "MPN") "GRM155R70J105KA12D"))
      (libsource (lib "eagle-import") (part "resistor_C-EUC0402K"))
    )
    (comp (ref "C3")
      (value "10u")
      (footprint "eagle-import:C0603K")
      (fields (field (name "MPN") "GRM188R61C106MA73D"))
      (libsource (lib "eagle-import") (part "C-EUC0603K"))
    )
    (comp (ref "C4")
      (value "10u")
      (footprint "eagle-import:C0603K")
      (fields (field (name "MPN") "GRM188R61C106MA73D"))
      (libsource (lib "eagle-import") (part "C-EUC0603K"))
    )
    (comp (ref "C5")
      (value "1u")
      (footprint "eagle-import:C0402K")
      (fields (field (name "MPN") "GRM155R70J105KA12D"))
      (libsource (lib "eagle-import") (part "resistor_C-EUC0402K"))
    )
    (comp (ref "C28")
      (value "0.1u")
      (footprint "eagle-import:C0402K")
      (fields (field (name "MPN") "GRM155R71C104JA88D"))
      (libsource (lib "eagle-import") (part "resistor_C-EUC0402K"))
    )
    (comp (ref "C29")
      (value "0.1u")
      (footprint "eagle-import:C0402K")
      (fields (field (name "MPN") "GRM155R71C104JA88D"))
      (libsource (lib "eagle-import") (part "resistor_C-EUC0402K"))
    )
    (comp (ref "C30")
      (value "0.1u")
      (footprint "eagle-import:C0402K")
      (fields (field (name "MPN") "GRM155R71C104JA88D"))
      (libsource (lib "eagle-import") (part "resistor_C-EUC0402K"))
    )
    (comp (ref "C32")
      (value "0.1u")
      (footprint "eagle-import:0402")
      (fields (field (name "MPN") "GRM155R71C104JA88D"))
      (libsource (lib "eagle-import") (part "C0402_BGA"))
    )
    (comp (ref "C38")
      (value "10n")
      (footprint "eagle-import:0402")
      (fields (field (name "MPN") "GRM155R71E103KA01D"))
      (libsource (lib "eagle-import") (part "C0402_BGA"))
    )
    (comp (ref "C40")
      (value "0.1u")
      (footprint "eagle-import:0402")
      (fields (field (name "MPN") "GRM155R71C104JA88D"))
      (libsource (lib "eagle-import") (part "C0402_BGA"))
    )
    (comp (ref "C41")
      (value "10n")
      (footprint "eagle-import:0402")
      (fields (field (name "MPN") "GRM155R71E103KA01D"))
      (libsource (lib "eagle-import") (part "C0402_BGA"))
    )
    (comp (ref "C42")
      (value "1u")
      (footprint "eagle-import:0402")
      (fields (field (name "MPN") "GRM155R70J105KA12D"))
      (libsource (lib "eagle-import") (part "C0402_BGA"))
    )
    (comp (ref "C43")
      (value "10n")
      (footprint "eagle-import:0402")
      (fields (field (name "MPN") "GRM155R71E103KA01D"))
      (libsource (lib "eagle-import") (part "C0402_BGA"))
    )
    (comp (ref "C45")
      (value "0.1u")
      (footprint "eagle-import:0402")
      (fields (field (name "MPN") "GRM155R71C104JA88D"))
      (libsource (lib "eagle-import") (part "C0402_BGA"))
    )
    (comp (ref "C46")
      (value "0.1u")
      (footprint "eagle-import:0402")
      (fields (field (name "MPN") "GRM155R71C104JA88D"))
      (libsource (lib "eagle-import") (part "C0402_BGA"))
    )
    (comp (ref "C48")
      (value "0.1u")
      (footprint "eagle-import:0402")
      (fields (field (name "MPN") "GRM155R71C104JA88D"))
      (libsource (lib "eagle-import") (part "C0402_BGA"))
    )
    (comp (ref "C49")
      (value "0.1u")
      (footprint "eagle-import:0402")
      (fields (field (name "MPN") "GRM155R71C104JA88D"))
      (libsource (lib "eagle-import") (part "C0402_BGA"))
    )
    (comp (ref "C50")
      (value "1n")
      (footprint "eagle-import:0402")
      (fields (field (name "MPN") "GRM155R71H102JA01J"))
      (libsource (lib "eagle-import") (part "C0402_BGA"))
    )
    (comp (ref "C51")
      (value "10n")
      (footprint "eagle-import:0402")
      (fields (field (name "MPN") "GRM155R71E103KA01D"))
      (libsource (lib "eagle-import") (part "C0402_BGA"))
    )
    (comp (ref "C52")
      (value "1u")
      (footprint "eagle-import:0402")
      (fields (field (name "MPN") "GRM155R70J105KA12D"))
      (libsource (lib "eagle-import") (part "C0402_BGA"))
    )
    (comp (ref "C53")
      (value "1u")
      (footprint "eagle-import:0402")
      (fields (field (name "MPN") "GRM155R70J105KA12D"))
      (libsource (lib "eagle-import") (part "C0402_BGA"))
    )
    (comp (ref "C54")
      (value "1u")
      (footprint "eagle-import:0402")
      (fields (field (name "MPN") "GRM155R70J105KA12D"))
      (libsource (lib "eagle-import") (part "C0402_BGA"))
    )
    (comp (ref "C55")
      (value "10n")
      (footprint "eagle-import:0402")
      (fields (field (name "MPN") "GRM155R71E103KA01D"))
      (libsource (lib "eagle-import") (part "C0402_BGA"))
    )
    (comp (ref "C56")
      (value "1n")
      (footprint "eagle-import:0402")
      (fields (field (name "MPN") "GRM155R71H102JA01J"))
      (libsource (lib "eagle-import") (part "C0402_BGA"))
    )
    (comp (ref "C57")
      (value "0.1u")
      (footprint "eagle-import:0402")
      (fields (field (name "MPN") "GRM155R71C104JA88D"))
      (libsource (lib "eagle-import") (part "C0402_BGA"))
    )
    (comp (ref "C59")
      (value "0.1u")
      (footprint "eagle-import:0402")
      (fields (field (name "MPN") "GRM155R71C104JA88D"))
      (libsource (lib "eagle-import") (part "C0402_BGA"))
    )
    (comp (ref "C60")
      (value "0.1u")
      (footprint "eagle-import:0402")
      (fields (field (name "MPN") "GRM155R71C104JA88D"))
      (libsource (lib "eagle-import") (part "C0402_BGA"))
    )
    (comp (ref "C62")
      (value "0.1u")
      (footprint "eagle-import:0402")
      (fields (field (name "MPN") "GRM155R71C104JA88D"))
      (libsource (lib "eagle-import") (part "C0402_BGA"))
    )
    (comp (ref "C63")
      (value "0.1u")
      (footprint "eagle-import:0402")
      (fields (field (name "MPN") "GRM155R71C104JA88D"))
      (libsource (lib "eagle-import") (part "C0402_BGA"))
    )
    (comp (ref "C64")
      (value "1u")
      (footprint "eagle-import:0402")
      (fields (field (name "MPN") "GRM155R70J105KA12D"))
      (libsource (lib "eagle-import") (part "C0402_BGA"))
    )
    (comp (ref "C65")
      (value "0.1u")
      (footprint "eagle-import:0402")
      (fields (field (name "MPN") "GRM155R71C104JA88D"))
      (libsource (lib "eagle-import") (part "C0402_BGA"))
    )
    (comp (ref "C67")
      (value "0.1u")
      (footprint "eagle-import:0402")
      (fields (field (name "MPN") "GRM155R71C104JA88D"))
      (libsource (lib "eagle-import") (part "C0402_BGA"))
    )
    (comp (ref "C69")
      (value "0.1u")
      (footprint "eagle-import:0402")
      (fields (field (name "MPN") "GRM155R71C104JA88D"))
      (libsource (lib "eagle-import") (part "C0402_BGA"))
    )
    (comp (ref "C71")
      (value "0.1u")
      (footprint "eagle-import:0402")
      (fields (field (name "MPN") "GRM155R71C104JA88D"))
      (libsource (lib "eagle-import") (part "C0402_BGA"))
    )
    (comp (ref "C72")
      (value "0.1u")
      (footprint "eagle-import:0402")
      (fields (field (name "MPN") "GRM155R71C104JA88D"))
      (libsource (lib "eagle-import") (part "C0402_BGA"))
    )
    (comp (ref "C73")
      (value "10n")
      (footprint "eagle-import:0402")
      (fields (field (name "MPN") "GRM155R71E103KA01D"))
      (libsource (lib "eagle-import") (part "C0402_BGA"))
    )
    (comp (ref "C74")
      (value "1n")
      (footprint "eagle-import:C0402K")
      (fields (field (name "MPN") "GRM155R71H102JA01J"))
      (libsource (lib "eagle-import") (part "resistor_C-EUC0402K"))
    )
    (comp (ref "C75")
      (value "0.1u")
      (footprint "eagle-import:0402")
      (fields (field (name "MPN") "GRM155R71C104JA88D"))
      (libsource (lib "eagle-import") (part "C0402_BGA"))
    )
    (comp (ref "C85")
      (value "0.1u")
      (footprint "eagle-import:0402")
      (fields (field (name "MPN") "GRM155R71C104JA88D"))
      (libsource (lib "eagle-import") (part "C0402_BGA"))
    )
    (comp (ref "C86")
      (value "1u")
      (footprint "eagle-import:0402")
      (fields (field (name "MPN") "GRM155R70J105KA12D"))
      (libsource (lib "eagle-import") (part "C0402_BGA"))
    )
    (comp (ref "C87")
      (value "0.1u")
      (footprint "eagle-import:0402")
      (fields (field (name "MPN") "GRM155R71C104JA88D"))
      (libsource (lib "eagle-import") (part "C0402_BGA"))
    )
    (comp (ref "C88")
      (value "0.1u")
      (footprint "eagle-import:0402")
      (fields (field (name "MPN") "GRM155R71C104JA88D"))
      (libsource (lib "eagle-import") (part "C0402_BGA"))
    )
    (comp (ref "C89")
      (value "10n")
      (footprint "eagle-import:C0402K")
      (fields (field (name "MPN") "GRM155R71E103KA01D"))
      (libsource (lib "eagle-import") (part "resistor_C-EUC0402K"))
    )
    (comp (ref "FB1")
      (value "BLM18AG601SN1D")
      (footprint "eagle-import:0603")
      (libsource (lib "eagle-import") (part "INDUCTOR0603"))
    )
    (comp (ref "FB4")
      (value "BLM18AG601SN1D")
      (footprint "eagle-import:0603")
      (libsource (lib "eagle-import") (part "INDUCTOR0603"))
    )
    (comp (ref "FB5")
      (value "BLM18AG601SN1D")
      (footprint "eagle-import:0603")
      (libsource (lib "eagle-import") (part "INDUCTOR0603"))
    )
    (comp (ref "FB6")
      (value "BLM18AG601SN1D")
      (footprint "eagle-import:0603")
      (libsource (lib "eagle-import") (part "INDUCTOR0603"))
    )
    (comp (ref "L3")
      (value "BLM18AG601SN1D")
      (footprint "eagle-import:0603")
      (libsource (lib "eagle-import") (part "INDUCTOR0603"))
    )
    (comp (ref "R60")
      (value "0")
      (footprint "eagle-import:0402-RES")
      (fields (field (name "MPN") "ERJ-2GE0R00X"))
      (libsource (lib "eagle-import") (part "RESISTOR0402-RES"))
    )
    (comp (ref "R61")
      (value "0")
      (footprint "eagle-import:0402-RES")
      (fields (field (name "MPN") "ERJ-2GE0R00X"))
      (libsource (lib "eagle-import") (part "RESISTOR0402-RES"))
    )
    (comp (ref "R62")
      (value "NC")
      (footprint "eagle-import:0402-RES")
      (libsource (lib "eagle-import") (part "RESISTOR0402-RES"))
    )
    (comp (ref "R63")
      (value "NC")
      (footprint "eagle-import:0402-RES")
      (libsource (lib "eagle-import") (part "RESISTOR0402-RES"))
    )
    (comp (ref "R64")
      (value "0")
      (footprint "eagle-import:0402-RES")
      (fields (field (name "MPN") "ERJ-2GE0R00X"))
      (libsource (lib "eagle-import") (part "RESISTOR0402-RES"))
    )
    (comp (ref "R97")
      (value "0")
      (footprint "eagle-import:0805")
      (fields (field (name "MPN") "ERJ-2GE0R00X"))
      (libsource (lib "eagle-import") (part "RESISTOR0805-RES"))
    )
    (comp (ref "R121")
      (value "NC")
      (footprint "eagle-import:0805")
      (libsource (lib "eagle-import") (part "RESISTOR0805-RES"))
    )
    (comp (ref "R122")
      (value "0")
      (footprint "eagle-import:0805")
      (fields (field (name "MPN") "ERJ-6GEY0R00V"))
      (libsource (lib "eagle-import") (part "RESISTOR0805-RES"))
    )
    (comp (ref "R124")
      (value "0")
      (footprint "eagle-import:0805")
      (fields (field (name "MPN") "ERJ-6GEY0R00V"))
      (libsource (lib "eagle-import") (part "RESISTOR0805-RES"))
    )
    (comp (ref "U4")
      (value "TMS320C5535")
      (footprint "eagle-import:PBGA144")
      (fields (field (name "MPN") "TMS320C5535AZHH10"))
      (libsource (lib "eagle-import") (part "TMS320C5535S-PBGA-N144"))
    )
    (comp (ref "C6-2")
      (value "10u")
      (footprint "eagle-import:C0603K")
      (fields (field (name "MPN") "GRM188R61C106MA73D"))
      (libsource (lib "eagle-import") (part "C-EUC0603K"))
    )
    (comp (ref "C24-2")
      (value "0.1u")
      (footprint "eagle-import:C0402K")
      (fields (field (name "MPN") "GRM155R71C104JA88D"))
      (libsource (lib "eagle-import") (part "resistor_C-EUC0402K"))
    )
    (comp (ref "C25-2")
      (value "10u")
      (footprint "eagle-import:C0603K")
      (fields (field (name "MPN") "GRM188R61C106MA73D"))
      (libsource (lib "eagle-import") (part "C-EUC0603K"))
    )
    (comp (ref "C66-2")
      (value "1n")
      (footprint "eagle-import:0402")
      (fields (field (name "MPN") "GRM155R71H102JA01J"))
      (libsource (lib "eagle-import") (part "C0402_BGA"))
    )
    (comp (ref "C77-2")
      (value "0.1u")
      (footprint "eagle-import:C0402K")
      (fields (field (name "MPN") "GRM155R71C104JA88D"))
      (libsource (lib "eagle-import") (part "resistor_C-EUC0402K"))
    )
    (comp (ref "C82-2")
      (value "0.1u")
      (footprint "eagle-import:0402")
      (fields (field (name "MPN") "GRM155R71C104JA88D"))
      (libsource (lib "eagle-import") (part "C0402_BGA"))
    )
    (comp (ref "C83-2")
      (value "1u")
      (footprint "eagle-import:0402")
      (fields (field (name "MPN") "GRM155R70J105KA12D"))
      (libsource (lib "eagle-import") (part "C0402_BGA"))
    )
    (comp (ref "C84-2")
      (value "0.1u")
      (footprint "eagle-import:0402")
      (fields (field (name "MPN") "GRM155R71C104JA88D"))
      (libsource (lib "eagle-import") (part "C0402_BGA"))
    )
    (comp (ref "C90-2")
      (value "10p")
      (footprint "eagle-import:C0402K")
      (fields (field (name "MPN") "GRM1555C1H100FA01D"))
      (libsource (lib "eagle-import") (part "resistor_C-EUC0402K"))
    )
    (comp (ref "C91-2")
      (value "10p")
      (footprint "eagle-import:C0402K")
      (fields (field (name "MPN") "GRM1555C1H100FA01D"))
      (libsource (lib "eagle-import") (part "resistor_C-EUC0402K"))
    )
    (comp (ref "D2-2")
      (value "6.2V")
      (footprint "eagle-import:SMADIODE")
      (fields (field (name "MPN") "1SMA5920BT3G") (field (name "PART_NUMBER") "SMAZ6V2-13-F"))
      (libsource (lib "eagle-import") (part "DIODESMA"))
    )
    (comp (ref "D3X")
      (value "GREEN")
      (footprint "eagle-import:CHIPLED_0603")
      (fields (field (name "MPN") "LTST-C190KGKT"))
      (libsource (lib "eagle-import") (part "LEDCHIPLED_0603"))
    )
    (comp (ref "FB7-2")
      (value "BLM18AG601SN1D")
      (footprint "eagle-import:0805")
      (fields (field (name "MPN") "BLM21AG151SN1D"))
      (libsource (lib "eagle-import") (part "INDUCTOR0805"))
    )
    (comp (ref "J1-2")
      (value "USB-MINIB-5PIN")
      (footprint "eagle-import:USB-MINIB")
      (fields (field (name "MPN") "10033526-N3212LF"))
      (libsource (lib "eagle-import") (part "USB-MINIB-5PIN"))
    )
    (comp (ref "R13-2")
      (value "10k")
      (footprint "eagle-import:0402-RES")
      (fields (field (name "MPN") "ERJ-2RKF1002X"))
      (libsource (lib "eagle-import") (part "RESISTOR0402-RES"))
    )
    (comp (ref "R14-2")
      (value "10k")
      (footprint "eagle-import:0402-RES")
      (fields (field (name "MPN") "ERJ-2RKF1002X"))
      (libsource (lib "eagle-import") (part "RESISTOR0402-RES"))
    )
    (comp (ref "R18-2")
      (value "100k")
      (footprint "eagle-import:0402-RES")
      (fields (field (name "MPN") "ERJ-2RKF1003X"))
      (libsource (lib "eagle-import") (part "RESISTOR0402-RES"))
    )
    (comp (ref "R29-2")
      (value "10k")
      (footprint "eagle-import:0402")
      (fields
        (field (name "MANUFACTURER_PART_NUMBER") "CRCW04021K00FKED")
        (field (name "POWER") "0.063")
        (field (name "TOLERANCE") "1.0")
        (field (name "MPN") "ERJ-2RKF1002X")
        (field (name "TOLERANCE_1") "1%")
      )
      (libsource (lib "eagle-import") (part "CRCW04021K00FKED"))
    )
    (comp (ref "R33-2")
      (value "10k")
      (footprint "eagle-import:0402-RES")
      (fields (field (name "MPN") "ERJ-2RKF1002X"))
      (libsource (lib "eagle-import") (part "RESISTOR0402-RES"))
    )
    (comp (ref "R34-2")
      (value "NC")
      (footprint "eagle-import:0402")
      (fields
        (field (name "MANUFACTURER_PART_NUMBER") "CRCW04021K00FKED")
        (field (name "POWER") "0.063")
        (field (name "TOLERANCE") "1.0")
      )
      (libsource (lib "eagle-import") (part "CRCW04021K00FKED"))
    )
    (comp (ref "R37-2")
      (value "100k")
      (footprint "eagle-import:0402-RES")
      (fields (field (name "MPN") "ERJ-2RKF1003X"))
      (libsource (lib "eagle-import") (part "RESISTOR0402-RES"))
    )
    (comp (ref "R38-2")
      (value "0")
      (footprint "eagle-import:0402")
      (fields
        (field (name "MANUFACTURER_PART_NUMBER") "CRCW04021K00FKED")
        (field (name "POWER") "0.063")
        (field (name "TOLERANCE") "1.0")
      )
      (libsource (lib "eagle-import") (part "CRCW04021K00FKED"))
    )
    (comp (ref "R41-2")
      (value "100k")
      (footprint "eagle-import:0402-RES")
      (fields (field (name "MPN") "ERJ-2RKF1003X"))
      (libsource (lib "eagle-import") (part "RESISTOR0402-RES"))
    )
    (comp (ref "R54-2")
      (value "0")
      (footprint "eagle-import:0402")
      (fields
        (field (name "MANUFACTURER_PART_NUMBER") "CRCW04021K00FKED")
        (field (name "POWER") "0.063")
        (field (name "TOLERANCE") "1.0")
      )
      (libsource (lib "eagle-import") (part "CRCW04021K00FKED"))
    )
    (comp (ref "R55-2")
      (value "0")
      (footprint "eagle-import:0402-RES")
      (fields (field (name "MPN") "ERJ-2GE0R00X"))
      (libsource (lib "eagle-import") (part "RESISTOR0402-RES"))
    )
    (comp (ref "R56-2")
      (value "NC")
      (footprint "eagle-import:0402-RES")
      (libsource (lib "eagle-import") (part "RESISTOR0402-RES"))
    )
    (comp (ref "R59-2")
      (value "10k")
      (footprint "eagle-import:0402-RES")
      (fields (field (name "MPN") "ERJ-2RKF1002X"))
      (libsource (lib "eagle-import") (part "RESISTOR0402-RES"))
    )
    (comp (ref "R66X")
      (value "33")
      (footprint "eagle-import:0402-RES")
      (fields (field (name "MPN") "ERJ-2RKF33R0X"))
      (libsource (lib "eagle-import") (part "RESISTOR0402-RES"))
    )
    (comp (ref "R76X")
      (value "220")
      (footprint "eagle-import:0402-RES")
      (fields (field (name "MPN") "ERJ-2RKF2200X"))
      (libsource (lib "eagle-import") (part "RESISTOR0402-RES"))
    )
    (comp (ref "R83X")
      (value "0")
      (footprint "eagle-import:0402")
      (fields
        (field (name "MANUFACTURER_PART_NUMBER") "CRCW04021K00FKED")
        (field (name "POWER") "0.063")
        (field (name "TOLERANCE") "1.0")
      )
      (libsource (lib "eagle-import") (part "CRCW04021K00FKED"))
    )
    (comp (ref "R105X")
      (value "0")
      (footprint "eagle-import:0402-RES")
      (fields (field (name "MPN") "ERJ-2GE0R00X"))
      (libsource (lib "eagle-import") (part "RESISTOR0402-RES"))
    )
    (comp (ref "R117-2")
      (value "10k")
      (footprint "eagle-import:0402-RES")
      (fields (field (name "MPN") "ERJ-2RKF1002X"))
      (libsource (lib "eagle-import") (part "RESISTOR0402-RES"))
    )
    (comp (ref "TP4-2")
      (value "TPTP06R")
      (footprint "eagle-import:TP06R")
      (fields (field (name "TP_SIGNAL_NAME") "CLKOUT2"))
      (libsource (lib "eagle-import") (part "TPTP06R"))
    )
    (comp (ref "TP8X")
      (value "TPTP06R")
      (footprint "eagle-import:TP06R")
      (fields (field (name "TP_SIGNAL_NAME") "RTC_CLKOUT2"))
      (libsource (lib "eagle-import") (part "TPTP06R"))
    )
    (comp (ref "TP23X")
      (value "TPTP06R")
      (footprint "eagle-import:TP06R")
      (libsource (lib "eagle-import") (part "TPTP06R"))
    )
    (comp (ref "TP24X")
      (value "TPTP06R")
      (footprint "eagle-import:TP06R")
      (libsource (lib "eagle-import") (part "TPTP06R"))
    )
    (comp (ref "TP25X")
      (value "TPTP06R")
      (footprint "eagle-import:TP06R")
      (libsource (lib "eagle-import") (part "TPTP06R"))
    )
    (comp (ref "TP26X")
      (value "TPTP06R")
      (footprint "eagle-import:TP06R")
      (libsource (lib "eagle-import") (part "TPTP06R"))
    )
    (comp (ref "TP27X")
      (value "TPTP06R")
      (footprint "eagle-import:TP06R")
      (libsource (lib "eagle-import") (part "TPTP06R"))
    )
    (comp (ref "TP28X")
      (value "TPTP06R")
      (footprint "eagle-import:TP06R")
      (libsource (lib "eagle-import") (part "TPTP06R"))
    )
    (comp (ref "TP29X")
      (value "TPTP06R")
      (footprint "eagle-import:TP06R")
      (libsource (lib "eagle-import") (part "TPTP06R"))
    )
    (comp (ref "TP30X")
      (value "TPTP06R")
      (footprint "eagle-import:TP06R")
      (libsource (lib "eagle-import") (part "TPTP06R"))
    )
    (comp (ref "TP31X")
      (value "TPTP06R")
      (footprint "eagle-import:TP06R")
      (libsource (lib "eagle-import") (part "TPTP06R"))
    )
    (comp (ref "U5")
      (value "TMS320C5535")
      (footprint "eagle-import:PBGA144")
      (fields (field (name "MPN") "TMS320C5535AZHH10"))
      (libsource (lib "eagle-import") (part "TMS320C5535S-PBGA-N144"))
    )
    (comp (ref "Y1-2")
      (value "32.768kHz")
      (footprint "eagle-import:CRYSTAL-32KHZ-SMD_EPSON_MC146")
      (fields (field (name "MPN") "SSPT7F-12.5PF20-R"))
      (libsource (lib "eagle-import") (part "CRYSTAL"))
    )
    (comp (ref "C7")
      (value "10u")
      (footprint "eagle-import:C0603K")
      (fields (field (name "MPN") "GRM188R61C106MA73D"))
      (libsource (lib "eagle-import") (part "C-EUC0603K"))
    )
    (comp (ref "C20")
      (value "0.1u")
      (footprint "eagle-import:C0402K")
      (fields (field (name "MPN") "GRM155R71C104JA88D"))
      (libsource (lib "eagle-import") (part "resistor_C-EUC0402K"))
    )
    (comp (ref "C33")
      (value "10n")
      (footprint "eagle-import:C0402K")
      (fields (field (name "MPN") "GRM155R71E103KA01D"))
      (libsource (lib "eagle-import") (part "resistor_C-EUC0402K"))
    )
    (comp (ref "C34")
      (value "0.1u")
      (footprint "eagle-import:C0402K")
      (fields (field (name "MPN") "GRM155R71C104JA88D"))
      (libsource (lib "eagle-import") (part "resistor_C-EUC0402K"))
    )
    (comp (ref "C35")
      (value "0.1u")
      (footprint "eagle-import:C0402K")
      (fields (field (name "MPN") "GRM155R71C104JA88D"))
      (libsource (lib "eagle-import") (part "resistor_C-EUC0402K"))
    )
    (comp (ref "C36")
      (value "0.1u")
      (footprint "eagle-import:C0402K")
      (fields (field (name "MPN") "GRM155R71C104JA88D"))
      (libsource (lib "eagle-import") (part "resistor_C-EUC0402K"))
    )
    (comp (ref "C37")
      (value "10n")
      (footprint "eagle-import:C0402K")
      (fields (field (name "MPN") "GRM155R71E103KA01D"))
      (libsource (lib "eagle-import") (part "resistor_C-EUC0402K"))
    )
    (comp (ref "C44")
      (value "4.7u")
      (footprint "eagle-import:C0603K")
      (fields (field (name "MPN") "GRM188R60J475KE19D"))
      (libsource (lib "eagle-import") (part "C-EUC0603K"))
    )
    (comp (ref "C47")
      (value "0.1u")
      (footprint "eagle-import:C0402K")
      (fields (field (name "MPN") "GRM155R71C104JA88D"))
      (libsource (lib "eagle-import") (part "resistor_C-EUC0402K"))
    )
    (comp (ref "C58")
      (value "10n")
      (footprint "eagle-import:C0402K")
      (fields (field (name "MPN") "GRM155R71E103KA01D"))
      (libsource (lib "eagle-import") (part "resistor_C-EUC0402K"))
    )
    (comp (ref "C61")
      (value "0.1u")
      (footprint "eagle-import:C0402K")
      (fields (field (name "MPN") "GRM155R71C104JA88D"))
      (libsource (lib "eagle-import") (part "resistor_C-EUC0402K"))
    )
    (comp (ref "C68")
      (value "0.1u")
      (footprint "eagle-import:C0402K")
      (fields (field (name "MPN") "GRM155R71C104JA88D"))
      (libsource (lib "eagle-import") (part "resistor_C-EUC0402K"))
    )
    (comp (ref "C70")
      (value "0.1u")
      (footprint "eagle-import:C0402K")
      (fields (field (name "MPN") "GRM155R71C104JA88D"))
      (libsource (lib "eagle-import") (part "resistor_C-EUC0402K"))
    )
    (comp (ref "C76")
      (value "4.7u")
      (footprint "eagle-import:C0603K")
      (fields (field (name "MPN") "GRM188R60J475KE19D"))
      (libsource (lib "eagle-import") (part "C-EUC0603K"))
    )
    (comp (ref "C78")
      (value "0.1u")
      (footprint "eagle-import:C0402K")
      (fields (field (name "MPN") "GRM155R71C104JA88D"))
      (libsource (lib "eagle-import") (part "resistor_C-EUC0402K"))
    )
    (comp (ref "C79")
      (value "0.1u")
      (footprint "eagle-import:C0402K")
      (fields (field (name "MPN") "GRM155R71C104JA88D"))
      (libsource (lib "eagle-import") (part "resistor_C-EUC0402K"))
    )
    (comp (ref "C80")
      (value "0.1u")
      (footprint "eagle-import:C0402K")
      (fields (field (name "MPN") "GRM155R71C104JA88D"))
      (libsource (lib "eagle-import") (part "resistor_C-EUC0402K"))
    )
    (comp (ref "C92")
      (value "0.1u")
      (footprint "eagle-import:C0402K")
      (fields (field (name "MPN") "GRM155R71C104JA88D"))
      (libsource (lib "eagle-import") (part "resistor_C-EUC0402K"))
    )
    (comp (ref "C93")
      (value "10n")
      (footprint "eagle-import:C0402K")
      (fields (field (name "MPN") "GRM155R71E103KA01D"))
      (libsource (lib "eagle-import") (part "resistor_C-EUC0402K"))
    )
    (comp (ref "D1")
      (value "MBR0520LT")
      (footprint "eagle-import:SOD123")
      (fields (field (name "MPN") "MBR0520LT1G"))
      (libsource (lib "eagle-import") (part "MBR0520LT"))
    )
    (comp (ref "D3")
      (value "MBR0520LT")
      (footprint "eagle-import:SOD123")
      (fields (field (name "MPN") "MBR0520LT1G"))
      (libsource (lib "eagle-import") (part "MBR0520LT"))
    )
    (comp (ref "D4")
      (value "MBR0520LT")
      (footprint "eagle-import:SOD123")
      (fields (field (name "MPN") "MBR0520LT1G"))
      (libsource (lib "eagle-import") (part "MBR0520LT"))
    )
    (comp (ref "D5")
      (value "MBR0520LT")
      (footprint "eagle-import:SOD123")
      (fields (field (name "MPN") "MBR0520LT1G"))
      (libsource (lib "eagle-import") (part "MBR0520LT"))
    )
    (comp (ref "DS1")
      (value "GREEN")
      (footprint "eagle-import:CHIPLED_1206")
      (fields (field (name "MPN") "LTST-C230KGKT"))
      (libsource (lib "eagle-import") (part "LEDCHIPLED_1206"))
    )
    (comp (ref "J2")
      (value "USB-B-SMT")
      (footprint "eagle-import:USB-B-SMT")
      (fields (field (name "MPN") "M701-370442"))
      (libsource (lib "eagle-import") (part "USB-B-SMT"))
    )
    (comp (ref "L1")
      (value "BLM21PG221SN1")
      (footprint "eagle-import:0805")
      (fields (field (name "MPN") "BLM21PG221SN1D"))
      (libsource (lib "eagle-import") (part "INDUCTOR0805"))
    )
    (comp (ref "L4")
      (value "BLM21PG21SN1")
      (footprint "eagle-import:0805")
      (fields (field (name "MPN") "BLM21PG221SN1D"))
      (libsource (lib "eagle-import") (part "INDUCTOR0805"))
    )
    (comp (ref "L5")
      (value "BLM21PG221SN1")
      (footprint "eagle-import:0805")
      (fields (field (name "MPN") "BLM21PG221SN1D"))
      (libsource (lib "eagle-import") (part "INDUCTOR0805"))
    )
    (comp (ref "R12")
      (value "560")
      (footprint "eagle-import:0402-RES")
      (fields (field (name "MPN") "ERJ-2RKF2200X"))
      (libsource (lib "eagle-import") (part "RESISTOR0402-RES"))
    )
    (comp (ref "R19")
      (value "10k")
      (footprint "eagle-import:0402-RES")
      (fields (field (name "MPN") "ERJ-2RKF1002X"))
      (libsource (lib "eagle-import") (part "RESISTOR0402-RES"))
    )
    (comp (ref "R21")
      (value "2.2k")
      (footprint "eagle-import:0402-RES")
      (fields (field (name "MPN") "ERJ-2RKF2201X"))
      (libsource (lib "eagle-import") (part "RESISTOR0402-RES"))
    )
    (comp (ref "R23")
      (value "0")
      (footprint "eagle-import:0402-RES")
      (fields (field (name "MPN") "ERJ-2GE0R00X"))
      (libsource (lib "eagle-import") (part "RESISTOR0402-RES"))
    )
    (comp (ref "R27")
      (value "0")
      (footprint "eagle-import:0402-RES")
      (fields (field (name "MPN") "ERJ-2GE0R00X"))
      (libsource (lib "eagle-import") (part "RESISTOR0402-RES"))
    )
    (comp (ref "R28")
      (value "12k")
      (footprint "eagle-import:0402-RES")
      (fields (field (name "MPN") "ERJ-2RKF1202X"))
      (libsource (lib "eagle-import") (part "RESISTOR0402-RES"))
    )
    (comp (ref "R30")
      (value "0")
      (footprint "eagle-import:0402-RES")
      (fields (field (name "MPN") "ERJ-2GE0R00X"))
      (libsource (lib "eagle-import") (part "RESISTOR0402-RES"))
    )
    (comp (ref "R32")
      (value "0")
      (footprint "eagle-import:0402-RES")
      (fields (field (name "MPN") "ERJ-2GE0R00X"))
      (libsource (lib "eagle-import") (part "RESISTOR0402-RES"))
    )
    (comp (ref "R35")
      (value "0")
      (footprint "eagle-import:0402-RES")
      (fields (field (name "MPN") "ERJ-2GE0R00X"))
      (libsource (lib "eagle-import") (part "RESISTOR0402-RES"))
    )
    (comp (ref "R36")
      (value "10k")
      (footprint "eagle-import:0402-RES")
      (fields (field (name "MPN") "ERJ-2RKF1002X"))
      (libsource (lib "eagle-import") (part "RESISTOR0402-RES"))
    )
    (comp (ref "R39")
      (value "33")
      (footprint "eagle-import:0402-RES")
      (fields (field (name "MPN") "ERJ-2RKF33R0X"))
      (libsource (lib "eagle-import") (part "RESISTOR0402-RES"))
    )
    (comp (ref "R40")
      (value "NC")
      (footprint "eagle-import:0402-RES")
      (libsource (lib "eagle-import") (part "RESISTOR0402-RES"))
    )
    (comp (ref "R42")
      (value "10k")
      (footprint "eagle-import:0402-RES")
      (fields (field (name "MPN") "ERJ-2RKF1002X"))
      (libsource (lib "eagle-import") (part "RESISTOR0402-RES"))
    )
    (comp (ref "R43")
      (value "10k")
      (footprint "eagle-import:0402-RES")
      (fields (field (name "MPN") "ERJ-2RKF1002X"))
      (libsource (lib "eagle-import") (part "RESISTOR0402-RES"))
    )
    (comp (ref "R44")
      (value "10k")
      (footprint "eagle-import:0402-RES")
      (fields (field (name "MPN") "ERJ-2RKF1002X"))
      (libsource (lib "eagle-import") (part "RESISTOR0402-RES"))
    )
    (comp (ref "R45")
      (value "NC")
      (footprint "eagle-import:0402-RES")
      (libsource (lib "eagle-import") (part "RESISTOR0402-RES"))
    )
    (comp (ref "R46")
      (value "33")
      (footprint "eagle-import:0402-RES")
      (fields (field (name "MPN") "ERJ-2RKF33R0X"))
      (libsource (lib "eagle-import") (part "RESISTOR0402-RES"))
    )
    (comp (ref "R47")
      (value "33")
      (footprint "eagle-import:0402-RES")
      (fields (field (name "MPN") "ERJ-2RKF33R0X"))
      (libsource (lib "eagle-import") (part "RESISTOR0402-RES"))
    )
    (comp (ref "R48")
      (value "33")
      (footprint "eagle-import:0402-RES")
      (fields (field (name "MPN") "ERJ-2RKF33R0X"))
      (libsource (lib "eagle-import") (part "RESISTOR0402-RES"))
    )
    (comp (ref "R49")
      (value "33")
      (footprint "eagle-import:0402-RES")
      (fields (field (name "MPN") "ERJ-2RKF33R0X"))
      (libsource (lib "eagle-import") (part "RESISTOR0402-RES"))
    )
    (comp (ref "R53")
      (value "33")
      (footprint "eagle-import:0402-RES")
      (fields (field (name "MPN") "ERJ-2RKF33R0X"))
      (libsource (lib "eagle-import") (part "RESISTOR0402-RES"))
    )
    (comp (ref "R57")
      (value "4.7k")
      (footprint "eagle-import:0402-RES")
      (fields (field (name "MPN") "ERJ-2RKF4701X"))
      (libsource (lib "eagle-import") (part "RESISTOR0402-RES"))
    )
    (comp (ref "R58")
      (value "33")
      (footprint "eagle-import:0402-RES")
      (fields (field (name "MPN") "ERJ-2RKF33R0X"))
      (libsource (lib "eagle-import") (part "RESISTOR0402-RES"))
    )
    (comp (ref "U2")
      (value "AT93C46A-10TQ-2.7")
      (footprint "eagle-import:TSSOP8")
      (fields (field (name "MPN") "AT93C46D-TH-T"))
      (libsource (lib "eagle-import") (part "AT93C46A-10?Q-2.7T"))
    )
    (comp (ref "U6")
      (value "FT2232HL")
      (footprint "eagle-import:LQFP-10X10-64")
      (fields (field (name "MPN") "FT2232HL-REEL"))
      (libsource (lib "eagle-import") (part "FT2232H"))
    )
    (comp (ref "U7")
      (value "TPD2E001IDRLRQ1")
      (footprint "eagle-import:SOT50P160X60-5N")
      (fields (field (name "MPN") "TPD2E001DRLR"))
      (libsource (lib "eagle-import") (part "TPD2E001IDRLRQ1"))
    )
    (comp (ref "U8")
      (value "74LVC1G175DBVSOT95")
      (footprint "eagle-import:SOT95P280X145-6N")
      (fields (field (name "MPN") "SN74LVC1G175DBVT"))
      (libsource (lib "eagle-import") (part "74LVC1G175SOT95DBV"))
    )
    (comp (ref "C9")
      (value "10u")
      (footprint "eagle-import:C0603K")
      (fields (field (name "MPN") "GRM188R61C106MA73D"))
      (libsource (lib "eagle-import") (part "C-EUC0603K"))
    )
    (comp (ref "C10")
      (value "10u")
      (footprint "eagle-import:C0603K")
      (fields (field (name "MPN") "GRM188R61C106MA73D"))
      (libsource (lib "eagle-import") (part "C-EUC0603K"))
    )
    (comp (ref "C15")
      (value "0.1u")
      (footprint "eagle-import:C0402K")
      (fields (field (name "MPN") "GRM155R71C104JA88D"))
      (libsource (lib "eagle-import") (part "resistor_C-EUC0402K"))
    )
    (comp (ref "C21")
      (value "0.1u")
      (footprint "eagle-import:C0402K")
      (fields (field (name "MPN") "GRM155R71C104JA88D"))
      (libsource (lib "eagle-import") (part "resistor_C-EUC0402K"))
    )
    (comp (ref "C81")
      (value "0.1u")
      (footprint "eagle-import:C0402K")
      (fields (field (name "MPN") "GRM155R71C104JA88D"))
      (libsource (lib "eagle-import") (part "resistor_C-EUC0402K"))
    )
    (comp (ref "C81-2")
      (value "0.1u")
      (footprint "eagle-import:C0402K")
      (fields (field (name "MPN") "GRM155R71C104JA88D"))
      (libsource (lib "eagle-import") (part "resistor_C-EUC0402K"))
    )
    (comp (ref "C169X")
      (value "0.1u")
      (footprint "eagle-import:C0402K")
      (fields (field (name "MPN") "GRM155R71C104JA88D"))
      (libsource (lib "eagle-import") (part "resistor_C-EUC0402K"))
    )
    (comp (ref "J6")
      (value "DM3BT-DSF-PEJS")
      (footprint "eagle-import:MICROSD_RBT")
      (libsource (lib "eagle-import") (part "SDMMCRBT"))
    )
    (comp (ref "J11")
      (value "DM3BT-DSF-PEJS")
      (footprint "eagle-import:MICROSD_RBT")
      (libsource (lib "eagle-import") (part "SDMMCRBT"))
    )
    (comp (ref "R1")
      (value "10k")
      (footprint "eagle-import:0402-RES")
      (fields (field (name "MPN") "ERJ-2RKF1002X"))
      (libsource (lib "eagle-import") (part "RESISTOR0402-RES"))
    )
    (comp (ref "R2")
      (value "10k")
      (footprint "eagle-import:0402-RES")
      (fields (field (name "MPN") "ERJ-2RKF1002X"))
      (libsource (lib "eagle-import") (part "RESISTOR0402-RES"))
    )
    (comp (ref "R3")
      (value "10k")
      (footprint "eagle-import:0402-RES")
      (fields (field (name "MPN") "ERJ-2RKF1002X"))
      (libsource (lib "eagle-import") (part "RESISTOR0402-RES"))
    )
    (comp (ref "R4")
      (value "10k")
      (footprint "eagle-import:0402-RES")
      (fields (field (name "MPN") "ERJ-2RKF1002X"))
      (libsource (lib "eagle-import") (part "RESISTOR0402-RES"))
    )
    (comp (ref "R6")
      (value "NC")
      (footprint "eagle-import:0402-RES")
      (libsource (lib "eagle-import") (part "RESISTOR0402-RES"))
    )
    (comp (ref "R7")
      (value "10k")
      (footprint "eagle-import:0402-RES")
      (fields (field (name "MPN") "ERJ-2RKF1002X"))
      (libsource (lib "eagle-import") (part "RESISTOR0402-RES"))
    )
    (comp (ref "R11")
      (value "10k")
      (footprint "eagle-import:0402-RES")
      (fields (field (name "MPN") "ERJ-2RKF1002X"))
      (libsource (lib "eagle-import") (part "RESISTOR0402-RES"))
    )
    (comp (ref "R16")
      (value "10k")
      (footprint "eagle-import:0402-RES")
      (fields (field (name "MPN") "ERJ-2RKF1002X"))
      (libsource (lib "eagle-import") (part "RESISTOR0402-RES"))
    )
    (comp (ref "R50")
      (value "10k")
      (footprint "eagle-import:0402-RES")
      (fields (field (name "MPN") "ERJ-2RKF1002X"))
      (libsource (lib "eagle-import") (part "RESISTOR0402-RES"))
    )
    (comp (ref "R50-2")
      (value "10k")
      (footprint "eagle-import:0402-RES")
      (fields (field (name "MPN") "ERJ-2RKF1002X"))
      (libsource (lib "eagle-import") (part "RESISTOR0402-RES"))
    )
    (comp (ref "R51")
      (value "10k")
      (footprint "eagle-import:0402-RES")
      (fields (field (name "MPN") "ERJ-2RKF1002X"))
      (libsource (lib "eagle-import") (part "RESISTOR0402-RES"))
    )
    (comp (ref "R51-2")
      (value "10k")
      (footprint "eagle-import:0402-RES")
      (fields (field (name "MPN") "ERJ-2RKF1002X"))
      (libsource (lib "eagle-import") (part "RESISTOR0402-RES"))
    )
    (comp (ref "R52")
      (value "10k")
      (footprint "eagle-import:0402-RES")
      (fields (field (name "MPN") "ERJ-2RKF1002X"))
      (libsource (lib "eagle-import") (part "RESISTOR0402-RES"))
    )
    (comp (ref "R52-1")
      (value "10k")
      (footprint "eagle-import:0402-RES")
      (fields (field (name "MPN") "ERJ-2RKF1002X"))
      (libsource (lib "eagle-import") (part "RESISTOR0402-RES"))
    )
    (comp (ref "R52-2")
      (value "10k")
      (footprint "eagle-import:0402-RES")
      (fields (field (name "MPN") "ERJ-2RKF1002X"))
      (libsource (lib "eagle-import") (part "RESISTOR0402-RES"))
    )
    (comp (ref "R72")
      (value "NC")
      (footprint "eagle-import:0402-RES")
      (libsource (lib "eagle-import") (part "RESISTOR0402-RES"))
    )
    (comp (ref "R72-2")
      (value "NC")
      (footprint "eagle-import:0402-RES")
      (libsource (lib "eagle-import") (part "RESISTOR0402-RES"))
    )
    (comp (ref "R73")
      (value "NC")
      (footprint "eagle-import:0402-RES")
      (libsource (lib "eagle-import") (part "RESISTOR0402-RES"))
    )
    (comp (ref "R73-2")
      (value "NC")
      (footprint "eagle-import:0402-RES")
      (libsource (lib "eagle-import") (part "RESISTOR0402-RES"))
    )
    (comp (ref "R98")
      (value "10k")
      (footprint "eagle-import:0402-RES")
      (fields (field (name "MPN") "ERJ-2RKF1002X"))
      (libsource (lib "eagle-import") (part "RESISTOR0402-RES"))
    )
    (comp (ref "R99")
      (value "10k")
      (footprint "eagle-import:0402-RES")
      (fields (field (name "MPN") "ERJ-2RKF1002X"))
      (libsource (lib "eagle-import") (part "RESISTOR0402-RES"))
    )
    (comp (ref "R100")
      (value "10k")
      (footprint "eagle-import:0402-RES")
      (fields (field (name "MPN") "ERJ-2RKF1002X"))
      (libsource (lib "eagle-import") (part "RESISTOR0402-RES"))
    )
    (comp (ref "R101")
      (value "NC")
      (footprint "eagle-import:0402-RES")
      (libsource (lib "eagle-import") (part "RESISTOR0402-RES"))
    )
    (comp (ref "R102")
      (value "10k")
      (footprint "eagle-import:0402-RES")
      (fields (field (name "MPN") "ERJ-2RKF1002X"))
      (libsource (lib "eagle-import") (part "RESISTOR0402-RES"))
    )
    (comp (ref "R103")
      (value "10k")
      (footprint "eagle-import:0402-RES")
      (fields (field (name "MPN") "ERJ-2RKF1002X"))
      (libsource (lib "eagle-import") (part "RESISTOR0402-RES"))
    )
    (comp (ref "R109")
      (value "10k")
      (footprint "eagle-import:0402-RES")
      (fields (field (name "MPN") "ERJ-2RKF1002X"))
      (libsource (lib "eagle-import") (part "RESISTOR0402-RES"))
    )
    (comp (ref "R143X")
      (value "10k")
      (footprint "eagle-import:0402-RES")
      (fields (field (name "MPN") "ERJ-2RKF1002X"))
      (libsource (lib "eagle-import") (part "RESISTOR0402-RES"))
    )
    (comp (ref "U9")
      (value "W25Q64FVSFIG")
      (footprint "eagle-import:SO16L")
      (libsource (lib "eagle-import") (part "SPI_FLASH-X25XX"))
    )
    (comp (ref "U9-2")
      (value "W25Q64FVSFIG")
      (footprint "eagle-import:SO16L")
      (libsource (lib "eagle-import") (part "SPI_FLASH-X25XX"))
    )
    (comp (ref "U10X")
      (value "24C64SM")
      (footprint "eagle-import:SO-08M")
      (fields
        (field (name "MF") "RAMTRON INTERNATIONAL CORP")
        (field (name "MPN") "FM24C64-S")
        (field (name "MPN_1") "AT24C64D-SSHM-T")
      )
      (libsource (lib "eagle-import") (part "24SMC64"))
    )
    (comp (ref "C168X")
      (value "100p")
      (footprint "eagle-import:C0402K")
      (fields (field (name "MPN") "GRM1555C1H101FA01J"))
      (libsource (lib "eagle-import") (part "C-EUC0402K"))
    )
    (comp (ref "H1")
      (value "MOUNT-PAD-ROUND3.0")
      (footprint "eagle-import:3,0-PAD")
      (libsource (lib "eagle-import") (part "MOUNT-PAD-ROUND3.0"))
    )
    (comp (ref "H2")
      (value "MOUNT-PAD-ROUND3.0")
      (footprint "eagle-import:3,0-PAD")
      (libsource (lib "eagle-import") (part "MOUNT-PAD-ROUND3.0"))
    )
    (comp (ref "H3")
      (value "MOUNT-PAD-ROUND3.0")
      (footprint "eagle-import:3,0-PAD")
      (libsource (lib "eagle-import") (part "MOUNT-PAD-ROUND3.0"))
    )
    (comp (ref "H4")
      (value "MOUNT-PAD-ROUND3.0")
      (footprint "eagle-import:3,0-PAD")
      (libsource (lib "eagle-import") (part "MOUNT-PAD-ROUND3.0"))
    )
    (comp (ref "J5")
      (value "87409-110LF")
      (footprint "eagle-import:87409-110LF")
      (libsource (lib "eagle-import") (part "87409-110LF"))
    )
    (comp (ref "J7")
      (value "87409-110LF")
      (footprint "eagle-import:87409-110LF")
      (libsource (lib "eagle-import") (part "87409-110LF"))
    )
    (comp (ref "JP2")
      (value "FOOTSW")
      (footprint "eagle-import:1X02")
      (libsource (lib "eagle-import") (part "PINHD-1X2"))
    )
    (comp (ref "JP3")
      (value "FIDUCIAL1X2.5")
      (footprint "eagle-import:FIDUCIAL-1X2.5")
      (libsource (lib "eagle-import") (part "FIDUCIAL1X2.5"))
    )
    (comp (ref "JP6")
      (value "FIDUCIAL1X2.5")
      (footprint "eagle-import:FIDUCIAL-1X2.5")
      (libsource (lib "eagle-import") (part "FIDUCIAL1X2.5"))
    )
    (comp (ref "JP7")
      (value "FIDUCIAL1X2.5")
      (footprint "eagle-import:FIDUCIAL-1X2.5")
      (libsource (lib "eagle-import") (part "FIDUCIAL1X2.5"))
    )
    (comp (ref "JP8")
      (value "FIDUCIAL1X2.5")
      (footprint "eagle-import:FIDUCIAL-1X2.5")
      (libsource (lib "eagle-import") (part "FIDUCIAL1X2.5"))
    )
    (comp (ref "LSP1")
      (value "LSP13")
      (footprint "eagle-import:LSP13")
      (libsource (lib "eagle-import") (part "LSP13"))
    )
    (comp (ref "LSP2")
      (value "LSP13")
      (footprint "eagle-import:LSP13")
      (libsource (lib "eagle-import") (part "LSP13"))
    )
    (comp (ref "R4X")
      (value "10k")
      (footprint "eagle-import:0402-RES")
      (fields (field (name "MPN") "ERJ-2RKF1002X"))
      (libsource (lib "eagle-import") (part "RESISTOR0402-RES"))
    )
    (comp (ref "SW1")
      (value "MB2011SB1W03-DA")
      (footprint "eagle-import:MB2011")
      (libsource (lib "eagle-import") (part "MB2011"))
    )
    (comp (ref "TP3")
      (value "TPTP12R")
      (footprint "eagle-import:TP12R")
      (fields (field (name "TP_SIGNAL_NAME") "A-DOWN"))
      (libsource (lib "eagle-import") (part "TPTP12R"))
    )
    (comp (ref "TP5")
      (value "TPTP12R")
      (footprint "eagle-import:TP12R")
      (fields (field (name "TP_SIGNAL_NAME") "A-CENTER"))
      (libsource (lib "eagle-import") (part "TPTP12R"))
    )
    (comp (ref "TP6")
      (value "TPTP12R")
      (footprint "eagle-import:TP12R")
      (fields (field (name "TP_SIGNAL_NAME") "A-UP"))
      (libsource (lib "eagle-import") (part "TPTP12R"))
    )
    (comp (ref "TP7")
      (value "TPTP12R")
      (footprint "eagle-import:TP12R")
      (fields (field (name "TP_SIGNAL_NAME") "A-LEFT"))
      (libsource (lib "eagle-import") (part "TPTP12R"))
    )
    (comp (ref "TP10")
      (value "TPTP12R")
      (footprint "eagle-import:TP12R")
      (fields (field (name "TP_SIGNAL_NAME") "A-RIGHT"))
      (libsource (lib "eagle-import") (part "TPTP12R"))
    )
    (comp (ref "C170")
      (value "10u")
      (footprint "eagle-import:C0805K")
      (fields (field (name "MPN") "GRM21BR71A106KA73L"))
      (libsource (lib "eagle-import") (part "C-EUC0805K"))
    )
    (comp (ref "C171")
      (value "22p")
      (footprint "eagle-import:0402-CAP")
      (fields (field (name "MPN") "GRM1555C2A220JA01D"))
      (libsource (lib "eagle-import") (part "CAP0402-CAP"))
    )
    (comp (ref "C172")
      (value "8.2n")
      (footprint "eagle-import:0402-CAP")
      (fields (field (name "MPN") "GRM155R71H822KA88D"))
      (libsource (lib "eagle-import") (part "CAP0402-CAP"))
    )
    (comp (ref "C173")
      (value "1u")
      (footprint "eagle-import:0402-CAP")
      (fields (field (name "MPN") "GRM155R70J105KA12D"))
      (libsource (lib "eagle-import") (part "CAP0402-CAP"))
    )
    (comp (ref "C174")
      (value "100p")
      (footprint "eagle-import:0402-CAP")
      (fields (field (name "MPN") "GRM1555C1H101FA01J"))
      (libsource (lib "eagle-import") (part "CAP0402-CAP"))
    )
    (comp (ref "C175")
      (value "33n")
      (footprint "eagle-import:0402-CAP")
      (fields (field (name "MPN") "GRM155R71E333KA88J"))
      (libsource (lib "eagle-import") (part "CAP0402-CAP"))
    )
    (comp (ref "C176")
      (value "220n")
      (footprint "eagle-import:0402-CAP")
      (fields (field (name "MPN") "GRM155R71C224KA12D"))
      (libsource (lib "eagle-import") (part "CAP0402-CAP"))
    )
    (comp (ref "C177")
      (value "1u")
      (footprint "eagle-import:0402-CAP")
      (fields (field (name "MPN") "GRM155R70J105KA12D"))
      (libsource (lib "eagle-import") (part "CAP0402-CAP"))
    )
    (comp (ref "C178")
      (value "47p")
      (footprint "eagle-import:0402-CAP")
      (fields (field (name "MPN") "GRM1555C1H470FA01D"))
      (libsource (lib "eagle-import") (part "CAP0402-CAP"))
    )
    (comp (ref "C179")
      (value "100u")
      (footprint "eagle-import:PANASONIC_D")
      (fields (field (name "MF") "Cornell-Dubilier") (field (name "MPN") "AVE107M25X16T-F"))
      (libsource (lib "eagle-import") (part "CPOL-EUD"))
    )
    (comp (ref "C180")
      (value "100u")
      (footprint "eagle-import:PANASONIC_D")
      (fields (field (name "MF") "Cornell Dubilier") (field (name "MPN") "AVE107M25X16T-F"))
      (libsource (lib "eagle-import") (part "CPOL-EUD"))
    )
    (comp (ref "C181")
      (value "100p")
      (footprint "eagle-import:0402-CAP")
      (fields (field (name "MPN") "GRM1555C1H101FA01J"))
      (libsource (lib "eagle-import") (part "CAP0402-CAP"))
    )
    (comp (ref "C182")
      (value "2.2u")
      (footprint "eagle-import:0402-CAP")
      (fields (field (name "MPN") "GRM155R60J225ME15D"))
      (libsource (lib "eagle-import") (part "CAP0402-CAP"))
    )
    (comp (ref "C183")
      (value "22u")
      (footprint "eagle-import:C1206K")
      (fields (field (name "MPN") "GRM31CR71A226KE15L"))
      (libsource (lib "eagle-import") (part "C-EUC1206K"))
    )
    (comp (ref "C184")
      (value "10u")
      (footprint "eagle-import:C0805K")
      (fields (field (name "MPN") "GRM21BR71A106KA73L"))
      (libsource (lib "eagle-import") (part "C-EUC0805K"))
    )
    (comp (ref "C185")
      (value "0.1u")
      (footprint "eagle-import:C0402K")
      (fields (field (name "MPN") "GRM155R71C104JA88D"))
      (libsource (lib "eagle-import") (part "resistor_C-EUC0402K"))
    )
    (comp (ref "C186")
      (value "47n")
      (footprint "eagle-import:0402-CAP")
      (fields (field (name "MPN") "GRM155R71H473KE14D"))
      (libsource (lib "eagle-import") (part "CAP0402-CAP"))
    )
    (comp (ref "C187")
      (value "2.2n")
      (footprint "eagle-import:0402-CAP")
      (fields (field (name "MPN") "GRM155R71H222JA01J"))
      (libsource (lib "eagle-import") (part "CAP0402-CAP"))
    )
    (comp (ref "C188")
      (value "10u")
      (footprint "eagle-import:C0805K")
      (fields (field (name "MPN") "GRM21BR71A106KA73L"))
      (libsource (lib "eagle-import") (part "C-EUC0805K"))
    )
    (comp (ref "C204")
      (value "0.1u")
      (footprint "eagle-import:C0402K")
      (fields (field (name "MPN") "GRM155R71C104JA88D"))
      (libsource (lib "eagle-import") (part "resistor_C-EUC0402K"))
    )
    (comp (ref "C220")
      (value "0.1u")
      (footprint "eagle-import:C0402K")
      (fields (field (name "MPN") "GRM155R71C104JA88D"))
      (libsource (lib "eagle-import") (part "resistor_C-EUC0402K"))
    )
    (comp (ref "C221")
      (value "0.1u")
      (footprint "eagle-import:C0402K")
      (fields (field (name "MPN") "GRM155R71C104JA88D"))
      (libsource (lib "eagle-import") (part "resistor_C-EUC0402K"))
    )
    (comp (ref "C222")
      (value "0.1u")
      (footprint "eagle-import:C0402K")
      (fields (field (name "MPN") "GRM155R71C104JA88D"))
      (libsource (lib "eagle-import") (part "resistor_C-EUC0402K"))
    )
    (comp (ref "CF1")
      (value "NFM3DPC223R1H3L")
      (footprint "eagle-import:NFM3DC")
      (fields
        (field (name "MF") "FARNELL")
        (field (name "MPN") "NFM3DCC470U1H3L")
        (field (name "MPN_1") "NFM3DPC223R1H3L")
      )
      (libsource (lib "eagle-import") (part "NFM3DC"))
    )
    (comp (ref "D6")
      (value "BAT54")
      (footprint "eagle-import:SOT23")
      (fields (field (name "MPN") "BAT54LT1G"))
      (libsource (lib "eagle-import") (part "BAT54"))
    )
    (comp (ref "D8")
      (value "BAT54S")
      (footprint "eagle-import:SOT23")
      (fields (field (name "MPN") "BAT54SLT1G"))
      (libsource (lib "eagle-import") (part "BAT54S"))
    )
    (comp (ref "D9")
      (value "S1G-13-F")
      (footprint "eagle-import:SMADIODE")
      (libsource (lib "eagle-import") (part "DIODESMA"))
    )
    (comp (ref "FB12")
      (value "BLM31PG121SN1L")
      (footprint "eagle-import:R1206")
      (libsource (lib "eagle-import") (part "R-EU_R1206"))
    )
    (comp (ref "IC2")
      (value "SN74HC4066D")
      (footprint "eagle-import:SO14")
      (fields (field (name "MPN") "SN74HC4066DR"))
      (libsource (lib "eagle-import") (part "4066D"))
    )
    (comp (ref "J3")
      (value "STEREOSW3C")
      (footprint "eagle-import:NEUTRIK-NMJ6HCD2")
      (fields (field (name "MPN") "NMJ6HCD2"))
      (libsource (lib "eagle-import") (part "STEREOSW3C"))
    )
    (comp (ref "J8")
      (value "DCJ0202")
      (footprint "eagle-import:DCJ0202")
      (fields (field (name "MF") "Kobiconn") (field (name "MPN") "PJ-202A"))
      (libsource (lib "eagle-import") (part "DCJ0202"))
    )
    (comp (ref "JP1")
      (value "BAT")
      (footprint "eagle-import:1X02")
      (fields (field (name "MF") "3M") (field (name "MPN") "929834-01-02-RK"))
      (libsource (lib "eagle-import") (part "PINHD-1X2"))
    )
    (comp (ref "Q1")
      (value "MUN2214T1")
      (footprint "eagle-import:SC59-BEC")
      (fields (field (name "MPN") "MUN2214T1G"))
      (libsource (lib "eagle-import") (part "MUN2214T1"))
    )
    (comp (ref "Q2")
      (value "MUN2214T1")
      (footprint "eagle-import:SC59-BEC")
      (fields (field (name "MPN") "MUN2214T1G"))
      (libsource (lib "eagle-import") (part "MUN2214T1"))
    )
    (comp (ref "Q3")
      (value "MMBF4393")
      (footprint "eagle-import:SOT23")
      (libsource (lib "eagle-import") (part "?548SST6"))
    )
    (comp (ref "Q4")
      (value "MUN2214T1")
      (footprint "eagle-import:SC59-BEC")
      (fields (field (name "MPN") "MUN2214T1G"))
      (libsource (lib "eagle-import") (part "MUN2214T1"))
    )
    (comp (ref "Q8")
      (value "MUN2214T1")
      (footprint "eagle-import:SC59-BEC")
      (fields (field (name "MPN") "MUN2214T1G"))
      (libsource (lib "eagle-import") (part "MUN2214T1"))
    )
    (comp (ref "Q9")
      (value "MUN2214T1")
      (footprint "eagle-import:SC59-BEC")
      (fields (field (name "MPN") "MUN2214T1G"))
      (libsource (lib "eagle-import") (part "MUN2214T1"))
    )
    (comp (ref "Q10")
      (value "MUN2214T1")
      (footprint "eagle-import:SC59-BEC")
      (fields (field (name "MPN") "MUN2214T1G"))
      (libsource (lib "eagle-import") (part "MUN2214T1"))
    )
    (comp (ref "R144")
      (value "10k")
      (footprint "eagle-import:0402-RES")
      (fields (field (name "MPN") "ERJ-2RKF1002X"))
      (libsource (lib "eagle-import") (part "RESISTOR0402-RES"))
    )
    (comp (ref "R145")
      (value "10k")
      (footprint "eagle-import:0402-RES")
      (fields (field (name "MPN") "ERJ-2RKF1002X"))
      (libsource (lib "eagle-import") (part "RESISTOR0402-RES"))
    )
    (comp (ref "R146")
      (value "100k")
      (footprint "eagle-import:0402-RES")
      (fields (field (name "MPN") "ERJ-2RKF1003X"))
      (libsource (lib "eagle-import") (part "RESISTOR0402-RES"))
    )
    (comp (ref "R147")
      (value "100k")
      (footprint "eagle-import:0402-RES")
      (fields (field (name "MPN") "ERJ-2RKF1003X"))
      (libsource (lib "eagle-import") (part "RESISTOR0402-RES"))
    )
    (comp (ref "R148")
      (value "2.2k")
      (footprint "eagle-import:0402-RES")
      (fields (field (name "MPN") "ERJ-2RKF2201X"))
      (libsource (lib "eagle-import") (part "RESISTOR0402-RES"))
    )
    (comp (ref "R149")
      (value "10k")
      (footprint "eagle-import:0402-RES")
      (fields (field (name "MPN") "ERJ-2RKF1002X"))
      (libsource (lib "eagle-import") (part "RESISTOR0402-RES"))
    )
    (comp (ref "R150")
      (value "2.2k")
      (footprint "eagle-import:0402-RES")
      (fields (field (name "MPN") "ERJ-2RKF2201X"))
      (libsource (lib "eagle-import") (part "RESISTOR0402-RES"))
    )
    (comp (ref "R151")
      (value "33k")
      (footprint "eagle-import:0402-RES")
      (fields (field (name "MPN") "ERJ-2RKF3302X"))
      (libsource (lib "eagle-import") (part "RESISTOR0402-RES"))
    )
    (comp (ref "R152")
      (value "180k")
      (footprint "eagle-import:0402-RES")
      (fields (field (name "MPN") "ERJ-2RKF1803X"))
      (libsource (lib "eagle-import") (part "RESISTOR0402-RES"))
    )
    (comp (ref "R153")
      (value "56k")
      (footprint "eagle-import:0402-RES")
      (fields (field (name "MPN") "ERJ-2RKF5602X"))
      (libsource (lib "eagle-import") (part "RESISTOR0402-RES"))
    )
    (comp (ref "R154")
      (value "4.7k")
      (footprint "eagle-import:0402-RES")
      (fields (field (name "MPN") "ERJ-2RKF4701X"))
      (libsource (lib "eagle-import") (part "RESISTOR0402-RES"))
    )
    (comp (ref "R155")
      (value "4.7k")
      (footprint "eagle-import:0402-RES")
      (fields (field (name "MPN") "ERJ-2RKF4701X"))
      (libsource (lib "eagle-import") (part "RESISTOR0402-RES"))
    )
    (comp (ref "R156")
      (value "1M")
      (footprint "eagle-import:0402-RES")
      (fields (field (name "MPN") "ERJ-2RKF1004X"))
      (libsource (lib "eagle-import") (part "RESISTOR0402-RES"))
    )
    (comp (ref "R157")
      (value "10k")
      (footprint "eagle-import:0402-RES")
      (fields (field (name "MPN") "ERJ-2RKF1002X"))
      (libsource (lib "eagle-import") (part "RESISTOR0402-RES"))
    )
    (comp (ref "R158")
      (value "1k")
      (footprint "eagle-import:0402-RES")
      (fields (field (name "MPN") "ERJ-2RKF1001X"))
      (libsource (lib "eagle-import") (part "RESISTOR0402-RES"))
    )
    (comp (ref "R159")
      (value "47k")
      (footprint "eagle-import:0402-RES")
      (fields (field (name "MPN") "ERJ-2RKF4702X"))
      (libsource (lib "eagle-import") (part "RESISTOR0402-RES"))
    )
    (comp (ref "R160")
      (value "1k")
      (footprint "eagle-import:0402-RES")
      (fields (field (name "MPN") "ERJ-2RKF1001X"))
      (libsource (lib "eagle-import") (part "RESISTOR0402-RES"))
    )
    (comp (ref "R161")
      (value "4.7k")
      (footprint "eagle-import:0402-RES")
      (fields (field (name "MPN") "ERJ-2RKF4701X"))
      (libsource (lib "eagle-import") (part "RESISTOR0402-RES"))
    )
    (comp (ref "R162")
      (value "4.7k")
      (footprint "eagle-import:0402-RES")
      (fields (field (name "MPN") "ERJ-2RKF4701X"))
      (libsource (lib "eagle-import") (part "RESISTOR0402-RES"))
    )
    (comp (ref "R163")
      (value "1k")
      (footprint "eagle-import:0402-RES")
      (fields (field (name "MPN") "ERJ-2RKF1001X"))
      (libsource (lib "eagle-import") (part "RESISTOR0402-RES"))
    )
    (comp (ref "R164")
      (value "180k")
      (footprint "eagle-import:0402-RES")
      (fields (field (name "MPN") "ERJ-2RKF1803X"))
      (libsource (lib "eagle-import") (part "RESISTOR0402-RES"))
    )
    (comp (ref "R165")
      (value "180k")
      (footprint "eagle-import:0402-RES")
      (fields (field (name "MPN") "ERJ-2RKF1803X"))
      (libsource (lib "eagle-import") (part "RESISTOR0402-RES"))
    )
    (comp (ref "R166")
      (value "470")
      (footprint "eagle-import:0402-RES")
      (fields (field (name "MPN") "ERJ-2RKF4700X"))
      (libsource (lib "eagle-import") (part "RESISTOR0402-RES"))
    )
    (comp (ref "R167")
      (value "560")
      (footprint "eagle-import:0402-RES")
      (fields (field (name "MPN") "ERJ-2RKF5600X"))
      (libsource (lib "eagle-import") (part "RESISTOR0402-RES"))
    )
    (comp (ref "R168")
      (value "100k")
      (footprint "eagle-import:0402-RES")
      (fields (field (name "MPN") "ERJ-2RKF1003X"))
      (libsource (lib "eagle-import") (part "RESISTOR0402-RES"))
    )
    (comp (ref "R169")
      (value "10k")
      (footprint "eagle-import:0402-RES")
      (fields (field (name "MPN") "ERJ-2RKF1002X"))
      (libsource (lib "eagle-import") (part "RESISTOR0402-RES"))
    )
    (comp (ref "R170")
      (value "10k")
      (footprint "eagle-import:0402-RES")
      (fields (field (name "MPN") "ERJ-2RKF1002X"))
      (libsource (lib "eagle-import") (part "RESISTOR0402-RES"))
    )
    (comp (ref "R171")
      (value "1M")
      (footprint "eagle-import:0402-RES")
      (fields (field (name "MPN") "ERJ-2RKF1004X"))
      (libsource (lib "eagle-import") (part "RESISTOR0402-RES"))
    )
    (comp (ref "R172")
      (value "18k")
      (footprint "eagle-import:0402-RES")
      (fields (field (name "MPN") "ERJ-2RKF1802X"))
      (libsource (lib "eagle-import") (part "RESISTOR0402-RES"))
    )
    (comp (ref "R173")
      (value "47k")
      (footprint "eagle-import:0402-RES")
      (fields (field (name "MPN") "ERJ-2RKF4702X"))
      (libsource (lib "eagle-import") (part "RESISTOR0402-RES"))
    )
    (comp (ref "R174")
      (value "10k")
      (footprint "eagle-import:0402-RES")
      (fields (field (name "MPN") "ERJ-2RKF1002X"))
      (libsource (lib "eagle-import") (part "RESISTOR0402-RES"))
    )
    (comp (ref "R175")
      (value "470")
      (footprint "eagle-import:0402-RES")
      (fields (field (name "MPN") "ERJ-2RKF4700X"))
      (libsource (lib "eagle-import") (part "RESISTOR0402-RES"))
    )
    (comp (ref "R197")
      (value "0")
      (footprint "eagle-import:0402-RES")
      (fields (field (name "MPN") "ERJ-2GE0R00X"))
      (libsource (lib "eagle-import") (part "RESISTOR0402-RES"))
    )
    (comp (ref "R198")
      (value "100k")
      (footprint "eagle-import:0402-RES")
      (fields (field (name "MPN") "ERJ-2RKF1003X"))
      (libsource (lib "eagle-import") (part "RESISTOR0402-RES"))
    )
    (comp (ref "R199")
      (value "100k")
      (footprint "eagle-import:0402-RES")
      (fields (field (name "MPN") "ERJ-2RKF1003X"))
      (libsource (lib "eagle-import") (part "RESISTOR0402-RES"))
    )
    (comp (ref "R200")
      (value "100k")
      (footprint "eagle-import:0402-RES")
      (fields (field (name "MPN") "ERJ-2RKF1003X"))
      (libsource (lib "eagle-import") (part "RESISTOR0402-RES"))
    )
    (comp (ref "R201")
      (value "100k")
      (footprint "eagle-import:0402-RES")
      (fields (field (name "MPN") "ERJ-2RKF1003X"))
      (libsource (lib "eagle-import") (part "RESISTOR0402-RES"))
    )
    (comp (ref "R202")
      (value "100k")
      (footprint "eagle-import:0402-RES")
      (fields (field (name "MPN") "ERJ-2RKF1003X"))
      (libsource (lib "eagle-import") (part "RESISTOR0402-RES"))
    )
    (comp (ref "R203")
      (value "100k")
      (footprint "eagle-import:0402-RES")
      (fields (field (name "MPN") "ERJ-2RKF1003X"))
      (libsource (lib "eagle-import") (part "RESISTOR0402-RES"))
    )
    (comp (ref "R204")
      (value "100k")
      (footprint "eagle-import:0402-RES")
      (fields (field (name "MPN") "ERJ-2RKF1003X"))
      (libsource (lib "eagle-import") (part "RESISTOR0402-RES"))
    )
    (comp (ref "SW2")
      (value "OS102011MA1Q")
      (footprint "eagle-import:OS102011MA1Q")
      (fields (field (name "MPN") "OS102011MA1QN1"))
      (libsource (lib "eagle-import") (part "OS102011MA1Q"))
    )
    (comp (ref "U13")
      (value "741G3157DBVR")
      (footprint "eagle-import:DBV_R-PDSO-G6")
      (fields (field (name "MPN") "SN74LVC1G3157DBVR"))
      (libsource (lib "eagle-import") (part "741G3157DBVR"))
    )
    (comp (ref "U19")
      (value "LME49721")
      (footprint "eagle-import:SO08")
      (fields (field (name "MPN") "LME49721MAX/NOPB"))
      (libsource (lib "eagle-import") (part "RC4559D"))
    )
    (comp (ref "U20")
      (value "LME49721")
      (footprint "eagle-import:SO08")
      (fields (field (name "MPN") "LME49721MAX/NOPB"))
      (libsource (lib "eagle-import") (part "RC4559D"))
    )
    (comp (ref "U21")
      (value "LME49721")
      (footprint "eagle-import:SO08")
      (fields (field (name "MPN") "LME49721MAX/NOPB"))
      (libsource (lib "eagle-import") (part "RC4559D"))
    )
    (comp (ref "C21X")
      (value "22u")
      (footprint "eagle-import:C1206K")
      (fields (field (name "MPN") "GRM31CR71A226KE15L"))
      (libsource (lib "eagle-import") (part "C-EUC1206K"))
    )
    (comp (ref "C23X")
      (value "22u")
      (footprint "eagle-import:C1210K")
      (fields (field (name "MPN") "GRM32ER71E226ME15L"))
      (libsource (lib "eagle-import") (part "C-EUC1210K"))
    )
    (comp (ref "C26X")
      (value "1u")
      (footprint "eagle-import:C0402K")
      (fields (field (name "MPN") "GRM155R70J105KA12D"))
      (libsource (lib "eagle-import") (part "resistor_C-EUC0402K"))
    )
    (comp (ref "C94X")
      (value "22u")
      (footprint "eagle-import:C1206K")
      (fields (field (name "MPN") "GRM31CR71A226KE15L"))
      (libsource (lib "eagle-import") (part "C-EUC1206K"))
    )
    (comp (ref "C95X")
      (value "820p")
      (footprint "eagle-import:C0402K")
      (fields (field (name "MPN") "GRM1555C1H821JA01D"))
      (libsource (lib "eagle-import") (part "resistor_C-EUC0402K"))
    )
    (comp (ref "C98X")
      (value "0.1u")
      (footprint "eagle-import:C0402K")
      (fields (field (name "MPN") "GRM155R71C104JA88D"))
      (libsource (lib "eagle-import") (part "resistor_C-EUC0402K"))
    )
    (comp (ref "C99X")
      (value "22u")
      (footprint "eagle-import:C1210K")
      (fields (field (name "MPN") "GRM32ER71E226ME15L"))
      (libsource (lib "eagle-import") (part "C-EUC1210K"))
    )
    (comp (ref "C124X")
      (value "0.1u")
      (footprint "eagle-import:C0402K")
      (fields (field (name "MPN") "GRM155R71C104JA88D"))
      (libsource (lib "eagle-import") (part "resistor_C-EUC0402K"))
    )
    (comp (ref "C125X")
      (value "0.1u")
      (footprint "eagle-import:C0402K")
      (fields (field (name "MPN") "GRM155R71C104JA88D"))
      (libsource (lib "eagle-import") (part "resistor_C-EUC0402K"))
    )
    (comp (ref "C213X")
      (value "0.1u")
      (footprint "eagle-import:C0402K")
      (fields (field (name "MPN") "GRM155R71C104JA88D"))
      (libsource (lib "eagle-import") (part "resistor_C-EUC0402K"))
    )
    (comp (ref "C215X")
      (value "0.1u")
      (footprint "eagle-import:C0402K")
      (fields (field (name "MPN") "GRM155R71C104JA88D"))
      (libsource (lib "eagle-import") (part "resistor_C-EUC0402K"))
    )
    (comp (ref "C216X")
      (value "0.1u")
      (footprint "eagle-import:C0402K")
      (fields (field (name "MPN") "GRM155R71C104JA88D"))
      (libsource (lib "eagle-import") (part "resistor_C-EUC0402K"))
    )
    (comp (ref "C217X")
      (value "1u")
      (footprint "eagle-import:C0402K")
      (fields (field (name "MPN") "GRM155R70J105KA12D"))
      (libsource (lib "eagle-import") (part "resistor_C-EUC0402K"))
    )
    (comp (ref "C218X")
      (value "10u")
      (footprint "eagle-import:C0603K")
      (fields (field (name "MPN") "GRM188R61C106MA73D"))
      (libsource (lib "eagle-import") (part "resistor_C-EUC0603K"))
    )
    (comp (ref "L6X")
      (value "2.2u")
      (footprint "eagle-import:SRN3015")
      (fields (field (name "MPN") "SRN3015-2R2M"))
      (libsource (lib "eagle-import") (part "SRN3015"))
    )
    (comp (ref "L7X")
      (value "3.3u")
      (footprint "eagle-import:SRN3015")
      (fields (field (name "MPN") "SRN3015-3R3M"))
      (libsource (lib "eagle-import") (part "SRN3015"))
    )
    (comp (ref "L8X")
      (value "BML15HD601SN1")
      (footprint "eagle-import:0402")
      (fields (field (name "MPN") "BLM15HD601SN1D"))
      (libsource (lib "eagle-import") (part "BML15HD601SN1"))
    )
    (comp (ref "R1X")
      (value "0")
      (footprint "eagle-import:0402-RES")
      (fields (field (name "MPN") "ERJ-2GE0R00X"))
      (libsource (lib "eagle-import") (part "RESISTOR0402-RES"))
    )
    (comp (ref "R2X")
      (value "0")
      (footprint "eagle-import:0402-RES")
      (fields (field (name "MPN") "ERJ-2GE0R00X"))
      (libsource (lib "eagle-import") (part "RESISTOR0402-RES"))
    )
    (comp (ref "R3X")
      (value "10k")
      (footprint "eagle-import:0402-RES")
      (fields (field (name "MPN") "ERJ-2RKF1002X"))
      (libsource (lib "eagle-import") (part "RESISTOR0402-RES"))
    )
    (comp (ref "R11X")
      (value "13.7k")
      (footprint "eagle-import:0402-RES")
      (fields (field (name "MPN") "ERJ-2RKF1372X"))
      (libsource (lib "eagle-import") (part "RESISTOR0402-RES"))
    )
    (comp (ref "R15")
      (value "0")
      (footprint "eagle-import:0402-RES")
      (fields (field (name "MPN") "ERJ-2GE0R00X"))
      (libsource (lib "eagle-import") (part "RESISTOR0402-RES"))
    )
    (comp (ref "R15X")
      (value "10k")
      (footprint "eagle-import:0402-RES")
      (fields (field (name "MPN") "ERJ-2RKF1002X"))
      (libsource (lib "eagle-import") (part "RESISTOR0402-RES"))
    )
    (comp (ref "R65X")
      (value "33.2k")
      (footprint "eagle-import:0402-RES")
      (fields (field (name "MPN") "ERJ-2RKF3322X"))
      (libsource (lib "eagle-import") (part "RESISTOR0402-RES"))
    )
    (comp (ref "R70X")
      (value "10k")
      (footprint "eagle-import:0402-RES")
      (fields (field (name "MPN") "ERJ-2RKF1002X"))
      (libsource (lib "eagle-import") (part "RESISTOR0402-RES"))
    )
    (comp (ref "R96X")
      (value "0")
      (footprint "eagle-import:0402-RES")
      (fields (field (name "MPN") "ERJ-2GE0R00X"))
      (libsource (lib "eagle-import") (part "RESISTOR0402-RES"))
    )
    (comp (ref "R118X")
      (value "0")
      (footprint "eagle-import:0402-RES")
      (fields (field (name "MPN") "ERJ-2GE0R00X"))
      (libsource (lib "eagle-import") (part "RESISTOR0402-RES"))
    )
    (comp (ref "R119X")
      (value "0")
      (footprint "eagle-import:0402-RES")
      (fields (field (name "MPN") "ERJ-2GE0R00X"))
      (libsource (lib "eagle-import") (part "RESISTOR0402-RES"))
    )
    (comp (ref "R125X")
      (value "20.5k")
      (footprint "eagle-import:0402-RES")
      (fields (field (name "MPN") "ERJ-2RKF2052X"))
      (libsource (lib "eagle-import") (part "RESISTOR0402-RES"))
    )
    (comp (ref "R126X")
      (value "243k")
      (footprint "eagle-import:0402-RES")
      (fields (field (name "MPN") "ERJ-2RKF2433X"))
      (libsource (lib "eagle-import") (part "RESISTOR0402-RES"))
    )
    (comp (ref "R222X")
      (value "10k")
      (footprint "eagle-import:0402-RES")
      (fields (field (name "MPN") "ERJ-2RKF1002X"))
      (libsource (lib "eagle-import") (part "RESISTOR0402-RES"))
    )
    (comp (ref "R223X")
      (value "10")
      (footprint "eagle-import:0402-RES")
      (fields (field (name "MPN") "ERJ-2RKF10R0X"))
      (libsource (lib "eagle-import") (part "RESISTOR0402-RES"))
    )
    (comp (ref "R224X")
      (value "10")
      (footprint "eagle-import:0402-RES")
      (fields (field (name "MPN") "ERJ-2RKF10R0X"))
      (libsource (lib "eagle-import") (part "RESISTOR0402-RES"))
    )
    (comp (ref "R225X")
      (value "10")
      (footprint "eagle-import:0402-RES")
      (fields (field (name "MPN") "ERJ-2RKF10R0X"))
      (libsource (lib "eagle-import") (part "RESISTOR0402-RES"))
    )
    (comp (ref "R226X")
      (value "10")
      (footprint "eagle-import:0402-RES")
      (fields (field (name "MPN") "ERJ-2RKF10R0X"))
      (libsource (lib "eagle-import") (part "RESISTOR0402-RES"))
    )
    (comp (ref "R227X")
      (value "10")
      (footprint "eagle-import:0402-RES")
      (fields (field (name "MPN") "ERJ-2RKF10R0X"))
      (libsource (lib "eagle-import") (part "RESISTOR0402-RES"))
    )
    (comp (ref "R228X")
      (value "10")
      (footprint "eagle-import:0402-RES")
      (fields (field (name "MPN") "ERJ-2RKF10R0X"))
      (libsource (lib "eagle-import") (part "RESISTOR0402-RES"))
    )
    (comp (ref "R229X")
      (value "10")
      (footprint "eagle-import:0402-RES")
      (fields (field (name "MPN") "ERJ-2RKF10R0X"))
      (libsource (lib "eagle-import") (part "RESISTOR0402-RES"))
    )
    (comp (ref "R230X")
      (value "10")
      (footprint "eagle-import:0402-RES")
      (fields (field (name "MPN") "ERJ-2RKF10R0X"))
      (libsource (lib "eagle-import") (part "RESISTOR0402-RES"))
    )
    (comp (ref "TP4X")
      (value "TPTP06R")
      (footprint "eagle-import:TP06R")
      (fields (field (name "TP_SIGNAL_NAME") "VCC_1V8_TP"))
      (libsource (lib "eagle-import") (part "TPTP06R"))
    )
    (comp (ref "TP5X")
      (value "TPTP06R")
      (footprint "eagle-import:TP06R")
      (fields (field (name "TP_SIGNAL_NAME") "VCC_3V3_TP"))
      (libsource (lib "eagle-import") (part "TPTP06R"))
    )
    (comp (ref "TP6X")
      (value "TPTP06R")
      (footprint "eagle-import:TP06R")
      (libsource (lib "eagle-import") (part "TPTP06R"))
    )
    (comp (ref "TP7X")
      (value "TPTP06R")
      (footprint "eagle-import:TP06R")
      (libsource (lib "eagle-import") (part "TPTP06R"))
    )
    (comp (ref "U1X")
      (value "TPS562209SO")
      (footprint "eagle-import:SOT95P280X145-6N")
      (fields (field (name "MPN") "TPS562209DDCT"))
      (libsource (lib "eagle-import") (part "TPS562209SO"))
    )
    (comp (ref "U3X")
      (value "TPS3803-01DCKR")
      (footprint "eagle-import:SOT65P210X110-5N")
      (fields (field (name "MPN") "TPS3803-01DCKR"))
      (libsource (lib "eagle-import") (part "TPS3803-01DCKR"))
    )
    (comp (ref "U11X")
      (value "TPS73201DBVT")
      (footprint "eagle-import:SOT95P280X145-5N")
      (fields (field (name "MPN") "TPS73201DBVT"))
      (libsource (lib "eagle-import") (part "TPS73201DBVT"))
    )
    (comp (ref "U12X")
      (value "TPS562209SO")
      (footprint "eagle-import:SOT95P280X145-6N")
      (fields (field (name "MPN") "TPS562209DDCT"))
      (libsource (lib "eagle-import") (part "TPS562209SO"))
    )
    (comp (ref "U15X")
      (value "CDCLVC1108PWR")
      (footprint "eagle-import:SOP65P640X120-16N")
      (fields (field (name "MPN") "CDCLVC1108PWR"))
      (libsource (lib "eagle-import") (part "CDCLVC1108PWR"))
    )
    (comp (ref "C6")
      (value "10u")
      (footprint "eagle-import:C0603K")
      (fields (field (name "MPN") "GRM188R61C106MA73D"))
      (libsource (lib "eagle-import") (part "C-EUC0603K"))
    )
    (comp (ref "C24")
      (value "0.1u")
      (footprint "eagle-import:C0402K")
      (fields (field (name "MPN") "GRM155R71C104JA88D"))
      (libsource (lib "eagle-import") (part "resistor_C-EUC0402K"))
    )
    (comp (ref "C25")
      (value "10u")
      (footprint "eagle-import:C0603K")
      (fields (field (name "MPN") "GRM188R61C106MA73D"))
      (libsource (lib "eagle-import") (part "C-EUC0603K"))
    )
    (comp (ref "C66")
      (value "1n")
      (footprint "eagle-import:0402")
      (fields (field (name "MPN") "GRM155R71H102JA01J"))
      (libsource (lib "eagle-import") (part "C0402_BGA"))
    )
    (comp (ref "C77")
      (value "0.1u")
      (footprint "eagle-import:C0402K")
      (fields (field (name "MPN") "GRM155R71C104JA88D"))
      (libsource (lib "eagle-import") (part "resistor_C-EUC0402K"))
    )
    (comp (ref "C82")
      (value "0.1u")
      (footprint "eagle-import:0402")
      (fields (field (name "MPN") "GRM155R71C104JA88D"))
      (libsource (lib "eagle-import") (part "C0402_BGA"))
    )
    (comp (ref "C83")
      (value "1u")
      (footprint "eagle-import:0402")
      (fields (field (name "MPN") "GRM155R70J105KA12D"))
      (libsource (lib "eagle-import") (part "C0402_BGA"))
    )
    (comp (ref "C84")
      (value "0.1u")
      (footprint "eagle-import:0402")
      (fields (field (name "MPN") "GRM155R71C104JA88D"))
      (libsource (lib "eagle-import") (part "C0402_BGA"))
    )
    (comp (ref "C90")
      (value "10p")
      (footprint "eagle-import:C0402K")
      (fields (field (name "MPN") "GRM1555C1H100FA01D"))
      (libsource (lib "eagle-import") (part "resistor_C-EUC0402K"))
    )
    (comp (ref "C91")
      (value "10p")
      (footprint "eagle-import:C0402K")
      (fields (field (name "MPN") "GRM1555C1H100FA01D"))
      (libsource (lib "eagle-import") (part "resistor_C-EUC0402K"))
    )
    (comp (ref "D2")
      (value "6.2V")
      (footprint "eagle-import:SMADIODE")
      (fields (field (name "MPN") "1SMA5920BT3G") (field (name "PART_NUMBER") "SMAZ6V2-13-F"))
      (libsource (lib "eagle-import") (part "DIODESMA"))
    )
    (comp (ref "DS2")
      (value "GREEN")
      (footprint "eagle-import:CHIPLED_0603")
      (fields (field (name "MPN") "LTST-C190KGKT"))
      (libsource (lib "eagle-import") (part "LEDCHIPLED_0603"))
    )
    (comp (ref "FB7")
      (value "BLM18AG601SN1D")
      (footprint "eagle-import:0805")
      (fields (field (name "MPN") "BLM21AG151SN1D"))
      (libsource (lib "eagle-import") (part "INDUCTOR0805"))
    )
    (comp (ref "J1")
      (value "USB-MINIB-5PIN")
      (footprint "eagle-import:USB-MINIB")
      (fields (field (name "MPN") "10033526-N3212LF"))
      (libsource (lib "eagle-import") (part "USB-MINIB-5PIN"))
    )
    (comp (ref "R13")
      (value "10k")
      (footprint "eagle-import:0402-RES")
      (fields (field (name "MPN") "ERJ-2RKF1002X"))
      (libsource (lib "eagle-import") (part "RESISTOR0402-RES"))
    )
    (comp (ref "R14")
      (value "10k")
      (footprint "eagle-import:0402-RES")
      (fields (field (name "MPN") "ERJ-2RKF1002X"))
      (libsource (lib "eagle-import") (part "RESISTOR0402-RES"))
    )
    (comp (ref "R17")
      (value "220")
      (footprint "eagle-import:0402-RES")
      (fields (field (name "MPN") "ERJ-2RKF2200X"))
      (libsource (lib "eagle-import") (part "RESISTOR0402-RES"))
    )
    (comp (ref "R18")
      (value "100k")
      (footprint "eagle-import:0402-RES")
      (fields (field (name "MPN") "ERJ-2RKF1003X"))
      (libsource (lib "eagle-import") (part "RESISTOR0402-RES"))
    )
    (comp (ref "R22")
      (value "10k")
      (footprint "eagle-import:0402-RES")
      (fields (field (name "MPN") "ERJ-2RKF1002X"))
      (libsource (lib "eagle-import") (part "RESISTOR0402-RES"))
    )
    (comp (ref "R25")
      (value "10k")
      (footprint "eagle-import:0402-RES")
      (fields (field (name "MPN") "ERJ-2RKF1002X"))
      (libsource (lib "eagle-import") (part "RESISTOR0402-RES"))
    )
    (comp (ref "R29")
      (value "10k")
      (footprint "eagle-import:0402")
      (fields
        (field (name "MANUFACTURER_PART_NUMBER") "CRCW04021K00FKED")
        (field (name "POWER") "0.063")
        (field (name "TOLERANCE") "1.0")
        (field (name "MPN") "ERJ-2RKF1002X")
        (field (name "TOLERANCE_1") "1%")
      )
      (libsource (lib "eagle-import") (part "CRCW04021K00FKED"))
    )
    (comp (ref "R33")
      (value "10k")
      (footprint "eagle-import:0402-RES")
      (fields (field (name "MPN") "ERJ-2RKF1002X"))
      (libsource (lib "eagle-import") (part "RESISTOR0402-RES"))
    )
    (comp (ref "R34")
      (value "NC")
      (footprint "eagle-import:0402")
      (fields
        (field (name "MANUFACTURER_PART_NUMBER") "CRCW04021K00FKED")
        (field (name "POWER") "0.063")
        (field (name "TOLERANCE") "1.0")
      )
      (libsource (lib "eagle-import") (part "CRCW04021K00FKED"))
    )
    (comp (ref "R37")
      (value "100k")
      (footprint "eagle-import:0402-RES")
      (fields (field (name "MPN") "ERJ-2RKF1003X"))
      (libsource (lib "eagle-import") (part "RESISTOR0402-RES"))
    )
    (comp (ref "R38")
      (value "0")
      (footprint "eagle-import:0402")
      (fields
        (field (name "MANUFACTURER_PART_NUMBER") "CRCW04021K00FKED")
        (field (name "POWER") "0.063")
        (field (name "TOLERANCE") "1.0")
      )
      (libsource (lib "eagle-import") (part "CRCW04021K00FKED"))
    )
    (comp (ref "R41")
      (value "100k")
      (footprint "eagle-import:0402-RES")
      (fields (field (name "MPN") "ERJ-2RKF1003X"))
      (libsource (lib "eagle-import") (part "RESISTOR0402-RES"))
    )
    (comp (ref "R54")
      (value "0")
      (footprint "eagle-import:0402")
      (fields
        (field (name "MANUFACTURER_PART_NUMBER") "CRCW04021K00FKED")
        (field (name "POWER") "0.063")
        (field (name "TOLERANCE") "1.0")
      )
      (libsource (lib "eagle-import") (part "CRCW04021K00FKED"))
    )
    (comp (ref "R55")
      (value "0")
      (footprint "eagle-import:0402-RES")
      (fields (field (name "MPN") "ERJ-2GE0R00X"))
      (libsource (lib "eagle-import") (part "RESISTOR0402-RES"))
    )
    (comp (ref "R56")
      (value "NC")
      (footprint "eagle-import:0402-RES")
      (libsource (lib "eagle-import") (part "RESISTOR0402-RES"))
    )
    (comp (ref "R59")
      (value "10k")
      (footprint "eagle-import:0402-RES")
      (fields (field (name "MPN") "ERJ-2RKF1002X"))
      (libsource (lib "eagle-import") (part "RESISTOR0402-RES"))
    )
    (comp (ref "R67")
      (value "0")
      (footprint "eagle-import:0402")
      (fields
        (field (name "MANUFACTURER_PART_NUMBER") "CRCW04021K00FKED")
        (field (name "POWER") "0.063")
        (field (name "TOLERANCE") "1.0")
      )
      (libsource (lib "eagle-import") (part "CRCW04021K00FKED"))
    )
    (comp (ref "R84")
      (value "0")
      (footprint "eagle-import:0402-RES")
      (fields (field (name "MPN") "ERJ-2GE0R00X"))
      (libsource (lib "eagle-import") (part "RESISTOR0402-RES"))
    )
    (comp (ref "R117")
      (value "10k")
      (footprint "eagle-import:0402-RES")
      (fields (field (name "MPN") "ERJ-2RKF1002X"))
      (libsource (lib "eagle-import") (part "RESISTOR0402-RES"))
    )
    (comp (ref "TP1")
      (value "TPTP06R")
      (footprint "eagle-import:TP06R")
      (fields (field (name "TP_SIGNAL_NAME") "CLKOUT"))
      (libsource (lib "eagle-import") (part "TPTP06R"))
    )
    (comp (ref "TP4")
      (value "TPTP06R")
      (footprint "eagle-import:TP06R")
      (fields (field (name "TP_SIGNAL_NAME") "RTC_CLKOUT"))
      (libsource (lib "eagle-import") (part "TPTP06R"))
    )
    (comp (ref "TP14")
      (value "TPTP06R")
      (footprint "eagle-import:TP06R")
      (libsource (lib "eagle-import") (part "TPTP06R"))
    )
    (comp (ref "TP15")
      (value "TPTP06R")
      (footprint "eagle-import:TP06R")
      (libsource (lib "eagle-import") (part "TPTP06R"))
    )
    (comp (ref "TP16")
      (value "TPTP06R")
      (footprint "eagle-import:TP06R")
      (libsource (lib "eagle-import") (part "TPTP06R"))
    )
    (comp (ref "TP19")
      (value "TPTP06R")
      (footprint "eagle-import:TP06R")
      (libsource (lib "eagle-import") (part "TPTP06R"))
    )
    (comp (ref "TP20")
      (value "TPTP06R")
      (footprint "eagle-import:TP06R")
      (libsource (lib "eagle-import") (part "TPTP06R"))
    )
    (comp (ref "TP21")
      (value "TPTP06R")
      (footprint "eagle-import:TP06R")
      (libsource (lib "eagle-import") (part "TPTP06R"))
    )
    (comp (ref "Y1")
      (value "32.768kHz")
      (footprint "eagle-import:CRYSTAL-32KHZ-SMD_EPSON_MC146")
      (fields (field (name "MPN") "SSPT7F-12.5PF20-R"))
      (libsource (lib "eagle-import") (part "CRYSTAL"))
    )
    (comp (ref "C189")
      (value "220p")
      (footprint "eagle-import:0402-CAP")
      (fields (field (name "MPN") "GRM1555C1H221FA01D"))
      (libsource (lib "eagle-import") (part "CAP0402-CAP"))
    )
    (comp (ref "C190")
      (value "22p")
      (footprint "eagle-import:0402-CAP")
      (fields (field (name "MPN") "GRM1555C2A220JA01D"))
      (libsource (lib "eagle-import") (part "CAP0402-CAP"))
    )
    (comp (ref "C191")
      (value "10u")
      (footprint "eagle-import:C0805K")
      (fields (field (name "MPN") "GRM21BR71A106KA73L"))
      (libsource (lib "eagle-import") (part "C-EUC0805K"))
    )
    (comp (ref "C192")
      (value "2.2n")
      (footprint "eagle-import:0402-CAP")
      (fields (field (name "MPN") "GRM155R71H222JA01J"))
      (libsource (lib "eagle-import") (part "CAP0402-CAP"))
    )
    (comp (ref "C193")
      (value "2.2n")
      (footprint "eagle-import:0402-CAP")
      (fields (field (name "MPN") "GRM155R71H222JA01J"))
      (libsource (lib "eagle-import") (part "CAP0402-CAP"))
    )
    (comp (ref "C194")
      (value "150p")
      (footprint "eagle-import:0402-CAP")
      (fields (field (name "MPN") "GRM1555C1H151GA01D"))
      (libsource (lib "eagle-import") (part "CAP0402-CAP"))
    )
    (comp (ref "C195")
      (value "10u")
      (footprint "eagle-import:C0805K")
      (fields (field (name "MPN") "GRM21BR71A106KA73L"))
      (libsource (lib "eagle-import") (part "C-EUC0805K"))
    )
    (comp (ref "C196")
      (value "2.2n")
      (footprint "eagle-import:0402-CAP")
      (fields (field (name "MPN") "GRM155R71H222JA01J"))
      (libsource (lib "eagle-import") (part "CAP0402-CAP"))
    )
    (comp (ref "C197")
      (value "220p")
      (footprint "eagle-import:0402-CAP")
      (fields (field (name "MPN") "GRM1555C1H221FA01D"))
      (libsource (lib "eagle-import") (part "CAP0402-CAP"))
    )
    (comp (ref "C198")
      (value "10u")
      (footprint "eagle-import:C0805K")
      (fields (field (name "MPN") "GRM21BR71A106KA73L"))
      (libsource (lib "eagle-import") (part "C-EUC0805K"))
    )
    (comp (ref "C199")
      (value "2.2n")
      (footprint "eagle-import:0402-CAP")
      (fields (field (name "MPN") "GRM155R71H222JA01J"))
      (libsource (lib "eagle-import") (part "CAP0402-CAP"))
    )
    (comp (ref "C200")
      (value "22p")
      (footprint "eagle-import:0402-CAP")
      (fields (field (name "MPN") "GRM1555C2A220JA01D"))
      (libsource (lib "eagle-import") (part "CAP0402-CAP"))
    )
    (comp (ref "C201")
      (value "2.2n")
      (footprint "eagle-import:0402-CAP")
      (fields (field (name "MPN") "GRM155R71H222JA01J"))
      (libsource (lib "eagle-import") (part "CAP0402-CAP"))
    )
    (comp (ref "C202")
      (value "150p")
      (footprint "eagle-import:0402-CAP")
      (fields (field (name "MPN") "GRM1555C1H151GA01D"))
      (libsource (lib "eagle-import") (part "CAP0402-CAP"))
    )
    (comp (ref "C203")
      (value "10u")
      (footprint "eagle-import:C0805K")
      (fields (field (name "MPN") "GRM21BR71A106KA73L"))
      (libsource (lib "eagle-import") (part "C-EUC0805K"))
    )
    (comp (ref "C205")
      (value "100p")
      (footprint "eagle-import:0402-CAP")
      (fields (field (name "MPN") "GRM1555C1H101FA01J"))
      (libsource (lib "eagle-import") (part "CAP0402-CAP"))
    )
    (comp (ref "C206")
      (value "220p")
      (footprint "eagle-import:0402-CAP")
      (fields (field (name "MPN") "GRM1555C1H221FA01D"))
      (libsource (lib "eagle-import") (part "CAP0402-CAP"))
    )
    (comp (ref "C207")
      (value "10n")
      (footprint "eagle-import:0402-CAP")
      (fields (field (name "MPN") "GRM155R71E103KA01D"))
      (libsource (lib "eagle-import") (part "CAP0402-CAP"))
    )
    (comp (ref "C208")
      (value "18n")
      (footprint "eagle-import:0402-CAP")
      (fields (field (name "MPN") "GRM155R71H183KA12D"))
      (libsource (lib "eagle-import") (part "CAP0402-CAP"))
    )
    (comp (ref "C209")
      (value "0.1u")
      (footprint "eagle-import:0402-CAP")
      (fields (field (name "MPN") "GRM155R71C104JA88D"))
      (libsource (lib "eagle-import") (part "CAP0402-CAP"))
    )
    (comp (ref "C210")
      (value "10u")
      (footprint "eagle-import:C0805K")
      (fields (field (name "MPN") "GRM21BR71A106KA73L"))
      (libsource (lib "eagle-import") (part "resistor_C-EUC0805K"))
    )
    (comp (ref "C211")
      (value "10u")
      (footprint "eagle-import:C0805K")
      (fields (field (name "MPN") "GRM21BR71A106KA73L"))
      (libsource (lib "eagle-import") (part "resistor_C-EUC0805K"))
    )
    (comp (ref "C212")
      (value "680p")
      (footprint "eagle-import:0402-CAP")
      (fields (field (name "MPN") "GRM155R72A681KA01D"))
      (libsource (lib "eagle-import") (part "CAP0402-CAP"))
    )
    (comp (ref "C214")
      (value "100p")
      (footprint "eagle-import:0402-CAP")
      (fields (field (name "MPN") "GRM1555C1H101FA01J"))
      (libsource (lib "eagle-import") (part "CAP0402-CAP"))
    )
    (comp (ref "C223")
      (value "0.1u")
      (footprint "eagle-import:0402-CAP")
      (fields (field (name "MPN") "GRM155R71C104JA88D"))
      (libsource (lib "eagle-import") (part "CAP0402-CAP"))
    )
    (comp (ref "C224")
      (value "0.1u")
      (footprint "eagle-import:0402-CAP")
      (fields (field (name "MPN") "GRM155R71C104JA88D"))
      (libsource (lib "eagle-import") (part "CAP0402-CAP"))
    )
    (comp (ref "D7")
      (value "BAT54S")
      (footprint "eagle-import:SOT23")
      (fields (field (name "MPN") "BAT54SLT1G"))
      (libsource (lib "eagle-import") (part "BAT54S"))
    )
    (comp (ref "FB13")
      (value "BLM31PG121SN1L")
      (footprint "eagle-import:R1206")
      (libsource (lib "eagle-import") (part "R-EU_R1206"))
    )
    (comp (ref "FB14")
      (value "BLM31PG121SN1L")
      (footprint "eagle-import:R1206")
      (libsource (lib "eagle-import") (part "R-EU_R1206"))
    )
    (comp (ref "J9")
      (value "MONOSW3C")
      (footprint "eagle-import:NEUTRIK-NMJ4HCD2")
      (fields (field (name "MPN") "NMJ4HCD2"))
      (libsource (lib "eagle-import") (part "MONOSW3C"))
    )
    (comp (ref "J10")
      (value "MONOSW3C")
      (footprint "eagle-import:NEUTRIK-NMJ4HCD2")
      (fields (field (name "MPN") "NMJ4HCD2"))
      (libsource (lib "eagle-import") (part "MONOSW3C"))
    )
    (comp (ref "LSP3")
      (value "LSP13")
      (footprint "eagle-import:LSP13")
      (libsource (lib "eagle-import") (part "LSP13"))
    )
    (comp (ref "Q5")
      (value "2N7002ET1G")
      (footprint "eagle-import:SOT23")
      (libsource (lib "eagle-import") (part "MOSFET-NREFLOW"))
    )
    (comp (ref "Q6")
      (value "2N7002ET1G")
      (footprint "eagle-import:SOT23")
      (libsource (lib "eagle-import") (part "MOSFET-NREFLOW"))
    )
    (comp (ref "Q7")
      (value "2N7002ET1G")
      (footprint "eagle-import:SOT23")
      (libsource (lib "eagle-import") (part "MOSFET-NREFLOW"))
    )
    (comp (ref "R176")
      (value "12k")
      (footprint "eagle-import:0402-RES")
      (fields (field (name "MPN") "ERJ-2RKF1202X"))
      (libsource (lib "eagle-import") (part "RESISTOR0402-RES"))
    )
    (comp (ref "R177")
      (value "47k")
      (footprint "eagle-import:0402-RES")
      (fields (field (name "MPN") "ERJ-2RKF4702X"))
      (libsource (lib "eagle-import") (part "RESISTOR0402-RES"))
    )
    (comp (ref "R178")
      (value "12k")
      (footprint "eagle-import:0402-RES")
      (fields (field (name "MPN") "ERJ-2RKF1202X"))
      (libsource (lib "eagle-import") (part "RESISTOR0402-RES"))
    )
    (comp (ref "R179")
      (value "8.2k")
      (footprint "eagle-import:0402-RES")
      (fields (field (name "MPN") "ERJ-2RKF8201X"))
      (libsource (lib "eagle-import") (part "RESISTOR0402-RES"))
    )
    (comp (ref "R180")
      (value "12k")
      (footprint "eagle-import:0402-RES")
      (fields (field (name "MPN") "ERJ-2RKF1202X"))
      (libsource (lib "eagle-import") (part "RESISTOR0402-RES"))
    )
    (comp (ref "R181")
      (value "10k")
      (footprint "eagle-import:0402-RES")
      (fields (field (name "MPN") "ERJ-2RKF1002X"))
      (libsource (lib "eagle-import") (part "RESISTOR0402-RES"))
    )
    (comp (ref "R182")
      (value "330")
      (footprint "eagle-import:0402-RES")
      (fields (field (name "MPN") "ERJ-2RKF3300X"))
      (libsource (lib "eagle-import") (part "RESISTOR0402-RES"))
    )
    (comp (ref "R183")
      (value "100k")
      (footprint "eagle-import:0402-RES")
      (fields (field (name "MPN") "ERJ-2RKF1003X"))
      (libsource (lib "eagle-import") (part "RESISTOR0402-RES"))
    )
    (comp (ref "R184")
      (value "1k")
      (footprint "eagle-import:0402-RES")
      (fields (field (name "MPN") "ERJ-2RKF1001X"))
      (libsource (lib "eagle-import") (part "RESISTOR0402-RES"))
    )
    (comp (ref "R185")
      (value "1k")
      (footprint "eagle-import:0402-RES")
      (fields (field (name "MPN") "ERJ-2RKF1001X"))
      (libsource (lib "eagle-import") (part "RESISTOR0402-RES"))
    )
    (comp (ref "R186")
      (value "10k")
      (footprint "eagle-import:0402-RES")
      (fields (field (name "MPN") "ERJ-2RKF1002X"))
      (libsource (lib "eagle-import") (part "RESISTOR0402-RES"))
    )
    (comp (ref "R187")
      (value "12k")
      (footprint "eagle-import:0402-RES")
      (fields (field (name "MPN") "ERJ-2RKF1202X"))
      (libsource (lib "eagle-import") (part "RESISTOR0402-RES"))
    )
    (comp (ref "R188")
      (value "12k")
      (footprint "eagle-import:0402-RES")
      (fields (field (name "MPN") "ERJ-2RKF1202X"))
      (libsource (lib "eagle-import") (part "RESISTOR0402-RES"))
    )
    (comp (ref "R189")
      (value "8.2k")
      (footprint "eagle-import:0402-RES")
      (fields (field (name "MPN") "ERJ-2RKF8201X"))
      (libsource (lib "eagle-import") (part "RESISTOR0402-RES"))
    )
    (comp (ref "R190")
      (value "12k")
      (footprint "eagle-import:0402-RES")
      (fields (field (name "MPN") "ERJ-2RKF1202X"))
      (libsource (lib "eagle-import") (part "RESISTOR0402-RES"))
    )
    (comp (ref "R191")
      (value "47k")
      (footprint "eagle-import:0402-RES")
      (fields (field (name "MPN") "ERJ-2RKF4702X"))
      (libsource (lib "eagle-import") (part "RESISTOR0402-RES"))
    )
    (comp (ref "R192")
      (value "10k")
      (footprint "eagle-import:0402-RES")
      (fields (field (name "MPN") "ERJ-2RKF1002X"))
      (libsource (lib "eagle-import") (part "RESISTOR0402-RES"))
    )
    (comp (ref "R193")
      (value "330")
      (footprint "eagle-import:0402-RES")
      (fields (field (name "MPN") "ERJ-2RKF3300X"))
      (libsource (lib "eagle-import") (part "RESISTOR0402-RES"))
    )
    (comp (ref "R194")
      (value "100k")
      (footprint "eagle-import:0402-RES")
      (fields (field (name "MPN") "ERJ-2RKF1003X"))
      (libsource (lib "eagle-import") (part "RESISTOR0402-RES"))
    )
    (comp (ref "R195")
      (value "1k")
      (footprint "eagle-import:0402-RES")
      (fields (field (name "MPN") "ERJ-2RKF1001X"))
      (libsource (lib "eagle-import") (part "RESISTOR0402-RES"))
    )
    (comp (ref "R196")
      (value "1k")
      (footprint "eagle-import:0402-RES")
      (fields (field (name "MPN") "ERJ-2RKF1001X"))
      (libsource (lib "eagle-import") (part "RESISTOR0402-RES"))
    )
    (comp (ref "R205")
      (value "100")
      (footprint "eagle-import:0402-RES")
      (fields (field (name "MPN") "ERJ-2RKF1000X"))
      (libsource (lib "eagle-import") (part "RESISTOR0402-RES"))
    )
    (comp (ref "R206")
      (value "220k")
      (footprint "eagle-import:0402-RES")
      (fields (field (name "MPN") "ERJ-2RKF2203X"))
      (libsource (lib "eagle-import") (part "RESISTOR0402-RES"))
    )
    (comp (ref "R207")
      (value "22k")
      (footprint "eagle-import:0402-RES")
      (fields (field (name "MPN") "ERJ-2RKF2202X"))
      (libsource (lib "eagle-import") (part "RESISTOR0402-RES"))
    )
    (comp (ref "R208")
      (value "680k")
      (footprint "eagle-import:0402-RES")
      (fields (field (name "MPN") "ERJ-2RKF6803X"))
      (libsource (lib "eagle-import") (part "RESISTOR0402-RES"))
    )
    (comp (ref "R209")
      (value "22k")
      (footprint "eagle-import:0402-RES")
      (fields (field (name "MPN") "ERJ-2RKF2202X"))
      (libsource (lib "eagle-import") (part "RESISTOR0402-RES"))
    )
    (comp (ref "R210")
      (value "10k")
      (footprint "eagle-import:0402-RES")
      (fields (field (name "MPN") "ERJ-2RKF1002X"))
      (libsource (lib "eagle-import") (part "RESISTOR0402-RES"))
    )
    (comp (ref "R211")
      (value "15k")
      (footprint "eagle-import:0402-RES")
      (fields (field (name "MPN") "ERJ-2RKF1502X"))
      (libsource (lib "eagle-import") (part "RESISTOR0402-RES"))
    )
    (comp (ref "R212")
      (value "12k")
      (footprint "eagle-import:0402-RES")
      (fields (field (name "MPN") "ERJ-2RKF1202X"))
      (libsource (lib "eagle-import") (part "RESISTOR0402-RES"))
    )
    (comp (ref "R213")
      (value "2k")
      (footprint "eagle-import:0402-RES")
      (fields (field (name "MPN") "ERJ-2RKF2001X"))
      (libsource (lib "eagle-import") (part "RESISTOR0402-RES"))
    )
    (comp (ref "R214")
      (value "2k")
      (footprint "eagle-import:0402-RES")
      (fields (field (name "MPN") "ERJ-2RKF2001X"))
      (libsource (lib "eagle-import") (part "RESISTOR0402-RES"))
    )
    (comp (ref "R215")
      (value "1.3k")
      (footprint "eagle-import:0402-RES")
      (fields (field (name "MPN") "ERJ-2RKF1301X"))
      (libsource (lib "eagle-import") (part "RESISTOR0402-RES"))
    )
    (comp (ref "R216")
      (value "1.3k")
      (footprint "eagle-import:0402-RES")
      (fields (field (name "MPN") "ERJ-2RKF1301X"))
      (libsource (lib "eagle-import") (part "RESISTOR0402-RES"))
    )
    (comp (ref "U22")
      (value "LME49721")
      (footprint "eagle-import:SO08")
      (fields (field (name "MPN") "LME49721MAX/NOPB"))
      (libsource (lib "eagle-import") (part "RC4559D"))
    )
    (comp (ref "U23")
      (value "LME49721")
      (footprint "eagle-import:SO08")
      (fields (field (name "MPN") "LME49721MAX/NOPB"))
      (libsource (lib "eagle-import") (part "RC4559D"))
    )
    (comp (ref "U24")
      (value "LMV358")
      (footprint "eagle-import:SO08")
      (fields (field (name "MPN") "LMV358IDR"))
      (libsource (lib "eagle-import") (part "LMV358"))
    )
    (comp (ref "C1-2")
      (value "10u")
      (footprint "eagle-import:C0603K")
      (fields (field (name "MPN") "GRM188R61C106MA73D"))
      (libsource (lib "eagle-import") (part "C-EUC0603K"))
    )
    (comp (ref "C2-2")
      (value "1u")
      (footprint "eagle-import:C0402K")
      (fields (field (name "MPN") "GRM155R70J105KA12D"))
      (libsource (lib "eagle-import") (part "resistor_C-EUC0402K"))
    )
    (comp (ref "C3-2")
      (value "10u")
      (footprint "eagle-import:C0603K")
      (fields (field (name "MPN") "GRM188R61C106MA73D"))
      (libsource (lib "eagle-import") (part "C-EUC0603K"))
    )
    (comp (ref "C4-2")
      (value "10u")
      (footprint "eagle-import:C0603K")
      (fields (field (name "MPN") "GRM188R61C106MA73D"))
      (libsource (lib "eagle-import") (part "C-EUC0603K"))
    )
    (comp (ref "C5-2")
      (value "1u")
      (footprint "eagle-import:C0402K")
      (fields (field (name "MPN") "GRM155R70J105KA12D"))
      (libsource (lib "eagle-import") (part "resistor_C-EUC0402K"))
    )
    (comp (ref "C28-2")
      (value "0.1u")
      (footprint "eagle-import:0402")
      (fields (field (name "MPN") "GRM155R71C104JA88D"))
      (libsource (lib "eagle-import") (part "C0402_BGA"))
    )
    (comp (ref "C29-2")
      (value "0.1u")
      (footprint "eagle-import:0402")
      (fields (field (name "MPN") "GRM155R71C104JA88D"))
      (libsource (lib "eagle-import") (part "C0402_BGA"))
    )
    (comp (ref "C30-2")
      (value "0.1u")
      (footprint "eagle-import:0402")
      (fields (field (name "MPN") "GRM155R71C104JA88D"))
      (libsource (lib "eagle-import") (part "C0402_BGA"))
    )
    (comp (ref "C32-2")
      (value "0.1u")
      (footprint "eagle-import:0402")
      (fields (field (name "MPN") "GRM155R71C104JA88D"))
      (libsource (lib "eagle-import") (part "C0402_BGA"))
    )
    (comp (ref "C38-2")
      (value "10n")
      (footprint "eagle-import:0402")
      (fields (field (name "MPN") "GRM155R71E103KA01D"))
      (libsource (lib "eagle-import") (part "C0402_BGA"))
    )
    (comp (ref "C40-2")
      (value "0.1u")
      (footprint "eagle-import:0402")
      (fields (field (name "MPN") "GRM155R71C104JA88D"))
      (libsource (lib "eagle-import") (part "C0402_BGA"))
    )
    (comp (ref "C41-2")
      (value "10n")
      (footprint "eagle-import:0402")
      (fields (field (name "MPN") "GRM155R71E103KA01D"))
      (libsource (lib "eagle-import") (part "C0402_BGA"))
    )
    (comp (ref "C42-2")
      (value "1u")
      (footprint "eagle-import:0402")
      (fields (field (name "MPN") "GRM155R70J105KA12D"))
      (libsource (lib "eagle-import") (part "C0402_BGA"))
    )
    (comp (ref "C43-2")
      (value "10n")
      (footprint "eagle-import:0402")
      (fields (field (name "MPN") "GRM155R71E103KA01D"))
      (libsource (lib "eagle-import") (part "C0402_BGA"))
    )
    (comp (ref "C45-2")
      (value "0.1u")
      (footprint "eagle-import:0402")
      (fields (field (name "MPN") "GRM155R71C104JA88D"))
      (libsource (lib "eagle-import") (part "C0402_BGA"))
    )
    (comp (ref "C46-2")
      (value "0.1u")
      (footprint "eagle-import:0402")
      (fields (field (name "MPN") "GRM155R71C104JA88D"))
      (libsource (lib "eagle-import") (part "C0402_BGA"))
    )
    (comp (ref "C48-2")
      (value "0.1u")
      (footprint "eagle-import:0402")
      (fields (field (name "MPN") "GRM155R71C104JA88D"))
      (libsource (lib "eagle-import") (part "C0402_BGA"))
    )
    (comp (ref "C49-2")
      (value "0.1u")
      (footprint "eagle-import:0402")
      (fields (field (name "MPN") "GRM155R71C104JA88D"))
      (libsource (lib "eagle-import") (part "C0402_BGA"))
    )
    (comp (ref "C50-2")
      (value "1n")
      (footprint "eagle-import:0402")
      (fields (field (name "MPN") "GRM155R71H102JA01J"))
      (libsource (lib "eagle-import") (part "C0402_BGA"))
    )
    (comp (ref "C51-2")
      (value "10n")
      (footprint "eagle-import:0402")
      (fields (field (name "MPN") "GRM155R71E103KA01D"))
      (libsource (lib "eagle-import") (part "C0402_BGA"))
    )
    (comp (ref "C52-2")
      (value "1u")
      (footprint "eagle-import:0402")
      (fields (field (name "MPN") "GRM155R70J105KA12D"))
      (libsource (lib "eagle-import") (part "C0402_BGA"))
    )
    (comp (ref "C53-2")
      (value "1u")
      (footprint "eagle-import:0402")
      (fields (field (name "MPN") "GRM155R70J105KA12D"))
      (libsource (lib "eagle-import") (part "C0402_BGA"))
    )
    (comp (ref "C54-2")
      (value "1u")
      (footprint "eagle-import:0402")
      (fields (field (name "MPN") "GRM155R70J105KA12D"))
      (libsource (lib "eagle-import") (part "C0402_BGA"))
    )
    (comp (ref "C55-2")
      (value "10n")
      (footprint "eagle-import:0402")
      (fields (field (name "MPN") "GRM155R71E103KA01D"))
      (libsource (lib "eagle-import") (part "C0402_BGA"))
    )
    (comp (ref "C56-2")
      (value "1n")
      (footprint "eagle-import:0402")
      (fields (field (name "MPN") "GRM155R71H102JA01J"))
      (libsource (lib "eagle-import") (part "C0402_BGA"))
    )
    (comp (ref "C57-2")
      (value "0.1u")
      (footprint "eagle-import:0402")
      (fields (field (name "MPN") "GRM155R71C104JA88D"))
      (libsource (lib "eagle-import") (part "C0402_BGA"))
    )
    (comp (ref "C59-2")
      (value "0.1u")
      (footprint "eagle-import:0402")
      (fields (field (name "MPN") "GRM155R71C104JA88D"))
      (libsource (lib "eagle-import") (part "C0402_BGA"))
    )
    (comp (ref "C60-2")
      (value "0.1u")
      (footprint "eagle-import:0402")
      (fields (field (name "MPN") "GRM155R71C104JA88D"))
      (libsource (lib "eagle-import") (part "C0402_BGA"))
    )
    (comp (ref "C62-2")
      (value "0.1u")
      (footprint "eagle-import:0402")
      (fields (field (name "MPN") "GRM155R71C104JA88D"))
      (libsource (lib "eagle-import") (part "C0402_BGA"))
    )
    (comp (ref "C63-2")
      (value "0.1u")
      (footprint "eagle-import:0402")
      (fields (field (name "MPN") "GRM155R71C104JA88D"))
      (libsource (lib "eagle-import") (part "C0402_BGA"))
    )
    (comp (ref "C64-2")
      (value "1u")
      (footprint "eagle-import:0402")
      (fields (field (name "MPN") "GRM155R70J105KA12D"))
      (libsource (lib "eagle-import") (part "C0402_BGA"))
    )
    (comp (ref "C65-2")
      (value "0.1u")
      (footprint "eagle-import:0402")
      (fields (field (name "MPN") "GRM155R71C104JA88D"))
      (libsource (lib "eagle-import") (part "C0402_BGA"))
    )
    (comp (ref "C67-2")
      (value "0.1u")
      (footprint "eagle-import:0402")
      (fields (field (name "MPN") "GRM155R71C104JA88D"))
      (libsource (lib "eagle-import") (part "C0402_BGA"))
    )
    (comp (ref "C69-2")
      (value "0.1u")
      (footprint "eagle-import:0402")
      (fields (field (name "MPN") "GRM155R71C104JA88D"))
      (libsource (lib "eagle-import") (part "C0402_BGA"))
    )
    (comp (ref "C71-2")
      (value "0.1u")
      (footprint "eagle-import:0402")
      (fields (field (name "MPN") "GRM155R71C104JA88D"))
      (libsource (lib "eagle-import") (part "C0402_BGA"))
    )
    (comp (ref "C72-2")
      (value "0.1u")
      (footprint "eagle-import:0402")
      (fields (field (name "MPN") "GRM155R71C104JA88D"))
      (libsource (lib "eagle-import") (part "C0402_BGA"))
    )
    (comp (ref "C73-2")
      (value "10n")
      (footprint "eagle-import:0402")
      (fields (field (name "MPN") "GRM155R71E103KA01D"))
      (libsource (lib "eagle-import") (part "C0402_BGA"))
    )
    (comp (ref "C74-2")
      (value "1n")
      (footprint "eagle-import:C0402K")
      (fields (field (name "MPN") "GRM155R71H102JA01J"))
      (libsource (lib "eagle-import") (part "resistor_C-EUC0402K"))
    )
    (comp (ref "C75-2")
      (value "0.1u")
      (footprint "eagle-import:0402")
      (fields (field (name "MPN") "GRM155R71C104JA88D"))
      (libsource (lib "eagle-import") (part "C0402_BGA"))
    )
    (comp (ref "C85-2")
      (value "0.1u")
      (footprint "eagle-import:0402")
      (fields (field (name "MPN") "GRM155R71C104JA88D"))
      (libsource (lib "eagle-import") (part "C0402_BGA"))
    )
    (comp (ref "C86-2")
      (value "1u")
      (footprint "eagle-import:0402")
      (fields (field (name "MPN") "GRM155R70J105KA12D"))
      (libsource (lib "eagle-import") (part "C0402_BGA"))
    )
    (comp (ref "C87-2")
      (value "0.1u")
      (footprint "eagle-import:0402")
      (fields (field (name "MPN") "GRM155R71C104JA88D"))
      (libsource (lib "eagle-import") (part "C0402_BGA"))
    )
    (comp (ref "C88-2")
      (value "0.1u")
      (footprint "eagle-import:0402")
      (fields (field (name "MPN") "GRM155R71C104JA88D"))
      (libsource (lib "eagle-import") (part "C0402_BGA"))
    )
    (comp (ref "C89-2")
      (value "10n")
      (footprint "eagle-import:C0402K")
      (fields (field (name "MPN") "GRM155R71E103KA01D"))
      (libsource (lib "eagle-import") (part "resistor_C-EUC0402K"))
    )
    (comp (ref "FB1-2")
      (value "BLM18AG601SN1D")
      (footprint "eagle-import:0603")
      (libsource (lib "eagle-import") (part "INDUCTOR0603"))
    )
    (comp (ref "FB4-2")
      (value "BLM18AG601SN1D")
      (footprint "eagle-import:0603")
      (libsource (lib "eagle-import") (part "INDUCTOR0603"))
    )
    (comp (ref "FB5-2")
      (value "BLM18AG601SN1D")
      (footprint "eagle-import:0603")
      (libsource (lib "eagle-import") (part "INDUCTOR0603"))
    )
    (comp (ref "FB6-2")
      (value "BLM18AG601SN1D")
      (footprint "eagle-import:0603")
      (libsource (lib "eagle-import") (part "INDUCTOR0603"))
    )
    (comp (ref "L3-2")
      (value "BLM18AG601SN1D")
      (footprint "eagle-import:0603")
      (libsource (lib "eagle-import") (part "INDUCTOR0603"))
    )
    (comp (ref "R60-2")
      (value "0")
      (footprint "eagle-import:0402-RES")
      (fields (field (name "MPN") "ERJ-2GE0R00X"))
      (libsource (lib "eagle-import") (part "RESISTOR0402-RES"))
    )
    (comp (ref "R61-2")
      (value "0")
      (footprint "eagle-import:0402-RES")
      (fields (field (name "MPN") "ERJ-2GE0R00X"))
      (libsource (lib "eagle-import") (part "RESISTOR0402-RES"))
    )
    (comp (ref "R62-2")
      (value "NC")
      (footprint "eagle-import:0402-RES")
      (libsource (lib "eagle-import") (part "RESISTOR0402-RES"))
    )
    (comp (ref "R63-2")
      (value "NC")
      (footprint "eagle-import:0402-RES")
      (libsource (lib "eagle-import") (part "RESISTOR0402-RES"))
    )
    (comp (ref "R64-2")
      (value "0")
      (footprint "eagle-import:0402-RES")
      (fields (field (name "MPN") "ERJ-2GE0R00X"))
      (libsource (lib "eagle-import") (part "RESISTOR0402-RES"))
    )
    (comp (ref "R97-2")
      (value "0")
      (footprint "eagle-import:0805")
      (fields (field (name "MPN") "ERJ-6GEY0R00V"))
      (libsource (lib "eagle-import") (part "RESISTOR0805-RES"))
    )
    (comp (ref "R121-2")
      (value "NC")
      (footprint "eagle-import:0805")
      (libsource (lib "eagle-import") (part "RESISTOR0805-RES"))
    )
    (comp (ref "R122-2")
      (value "0")
      (footprint "eagle-import:0805")
      (fields (field (name "MPN") "ERJ-6GEY0R00V"))
      (libsource (lib "eagle-import") (part "RESISTOR0805-RES"))
    )
    (comp (ref "R124-2")
      (value "0")
      (footprint "eagle-import:0805")
      (fields (field (name "MPN") "ERJ-6GEY0R00V"))
      (libsource (lib "eagle-import") (part "RESISTOR0805-RES"))
    )
  )
  (nets
    (net (code "1") (name "+9V") (class "Default")
      (node (ref "D1") (pin "A") (pinfunction "A_A") (pintype "passive"))
      (node (ref "SW2") (pin "1") (pinfunction "S_1") (pintype "passive"))
    )
    (net (code "2") (name "A-CENTER") (class "Default")
      (node (ref "J5") (pin "10") (pinfunction "10_10") (pintype "passive"))
      (node (ref "TP5") (pin "TP") (pinfunction "TP_TP") (pintype "input"))
    )
    (net (code "3") (name "A-DOWN") (class "Default")
      (node (ref "J5") (pin "6") (pinfunction "6_6") (pintype "passive"))
      (node (ref "TP3") (pin "TP") (pinfunction "TP_TP") (pintype "input"))
    )
    (net (code "4") (name "A-LEFT") (class "Default")
      (node (ref "J5") (pin "18") (pinfunction "18_18") (pintype "passive"))
      (node (ref "TP7") (pin "TP") (pinfunction "TP_TP") (pintype "input"))
    )
    (net (code "5") (name "A-RIGHT") (class "Default")
      (node (ref "J5") (pin "2") (pinfunction "2_2") (pintype "passive"))
      (node (ref "TP10") (pin "TP") (pinfunction "TP_TP") (pintype "input"))
    )
    (net (code "6") (name "A-UP") (class "Default")
      (node (ref "J5") (pin "14") (pinfunction "14_14") (pintype "passive"))
      (node (ref "TP6") (pin "TP") (pinfunction "TP_TP") (pintype "input"))
    )
    (net (code "7") (name "AGND") (class "Default")
      (node (ref "C2") (pin "2") (pinfunction "2_2") (pintype "passive"))
      (node (ref "C2-2") (pin "2") (pinfunction "2_2") (pintype "passive"))
      (node (ref "C3") (pin "2") (pinfunction "2_2") (pintype "passive"))
      (node (ref "C3-2") (pin "2") (pinfunction "2_2") (pintype "passive"))
      (node (ref "C43") (pin "2") (pinfunction "2_2") (pintype "passive"))
      (node (ref "C43-2") (pin "2") (pinfunction "2_2") (pintype "passive"))
      (node (ref "C49") (pin "2") (pinfunction "2_2") (pintype "passive"))
      (node (ref "C49-2") (pin "2") (pinfunction "2_2") (pintype "passive"))
      (node (ref "C50") (pin "2") (pinfunction "2_2") (pintype "passive"))
      (node (ref "C50-2") (pin "2") (pinfunction "2_2") (pintype "passive"))
      (node (ref "C57") (pin "2") (pinfunction "2_2") (pintype "passive"))
      (node (ref "C57-2") (pin "2") (pinfunction "2_2") (pintype "passive"))
      (node (ref "C73") (pin "2") (pinfunction "2_2") (pintype "passive"))
      (node (ref "C73-2") (pin "2") (pinfunction "2_2") (pintype "passive"))
      (node (ref "C85") (pin "2") (pinfunction "2_2") (pintype "passive"))
      (node (ref "C85-2") (pin "2") (pinfunction "2_2") (pintype "passive"))
      (node (ref "C86") (pin "2") (pinfunction "2_2") (pintype "passive"))
      (node (ref "C86-2") (pin "2") (pinfunction "2_2") (pintype "passive"))
      (node (ref "C88") (pin "2") (pinfunction "2_2") (pintype "passive"))
      (node (ref "C88-2") (pin "2") (pinfunction "2_2") (pintype "passive"))
      (node (ref "FB1") (pin "2") (pinfunction "2_2") (pintype "passive"))
      (node (ref "FB1-2") (pin "2") (pinfunction "2_2") (pintype "passive"))
      (node (ref "U4") (pin "A1") (pinfunction "VSSA_PLL_A1") (pintype "power_in"))
      (node (ref "U4") (pin "B6") (pinfunction "VSSA_ANA_B6") (pintype "power_in"))
      (node (ref "U4") (pin "C9") (pinfunction "VSSA_ANA_C9") (pintype "power_in"))
      (node (ref "U4") (pin "F13") (pinfunction "USB_VSSPLL_F13") (pintype "power_in"))
      (node (ref "U4") (pin "J12") (pinfunction "USB_VSSA1P3_J12") (pintype "power_in"))
      (node (ref "U5") (pin "A1") (pinfunction "VSSA_PLL_A1") (pintype "power_in"))
      (node (ref "U5") (pin "B6") (pinfunction "VSSA_ANA_B6") (pintype "power_in"))
      (node (ref "U5") (pin "C9") (pinfunction "VSSA_ANA_C9") (pintype "power_in"))
      (node (ref "U5") (pin "F13") (pinfunction "USB_VSSPLL_F13") (pintype "power_in"))
      (node (ref "U5") (pin "J12") (pinfunction "USB_VSSA1P3_J12") (pintype "power_in"))
    )
    (net (code "8") (name "AIC3204I2C_ENN") (class "Default")
      (node (ref "R136") (pin "2") (pinfunction "2_2") (pintype "passive"))
      (node (ref "U18") (pin "19") (pinfunction "~{OE}_19") (pintype "input"))
      (node (ref "U4") (pin "J2") (pinfunction "LCD_D[2]/GP[12]_J2") (pintype "tri_state"))
    )
    (net (code "9") (name "AIC_IISCLK") (class "Default")
      (node (ref "R92") (pin "1") (pinfunction "1_1") (pintype "passive"))
      (node (ref "U17") (pin "2") (pinfunction "BCLK_2") (pintype "bidirectional"))
    )
    (net (code "10") (name "AIC_IISD0") (class "Default")
      (node (ref "R94") (pin "1") (pinfunction "1_1") (pintype "passive"))
      (node (ref "U17") (pin "4") (pinfunction "DIN/MFP1_4") (pintype "input"))
    )
    (net (code "11") (name "AIC_IISD1") (class "Default")
      (node (ref "R95") (pin "1") (pinfunction "1_1") (pintype "passive"))
      (node (ref "U17") (pin "5") (pinfunction "DOUT/MFP2_5") (pintype "output"))
    )
    (net (code "12") (name "AIC_IISFS") (class "Default")
      (node (ref "R93") (pin "1") (pinfunction "1_1") (pintype "passive"))
      (node (ref "U17") (pin "3") (pinfunction "WCLK_3") (pintype "bidirectional"))
    )
    (net (code "13") (name "AIC_LINE2L") (class "Default")
      (node (ref "C17") (pin "1") (pinfunction "1_1") (pintype "passive"))
      (node (ref "R110") (pin "1") (pinfunction "1_1") (pintype "passive"))
      (node (ref "R175") (pin "2") (pinfunction "2_2") (pintype "passive"))
    )
    (net (code "14") (name "AIC_LINE2R") (class "Default")
      (node (ref "C16") (pin "1") (pinfunction "1_1") (pintype "passive"))
      (node (ref "R111") (pin "2") (pinfunction "2_2") (pintype "passive"))
      (node (ref "R197") (pin "2") (pinfunction "2_2") (pintype "passive"))
    )
    (net (code "15") (name "AIC_MCLK") (class "Default")
      (node (ref "R138") (pin "2") (pinfunction "2_2") (pintype "passive"))
      (node (ref "U17") (pin "1") (pinfunction "MCLK_(1)_1") (pintype "input"))
      (node (ref "U18") (pin "11") (pinfunction "B8_11") (pintype "bidirectional"))
    )
    (net (code "16") (name "AIC_MODE_SEL") (class "Default")
      (node (ref "R104") (pin "2") (pinfunction "2_2") (pintype "passive"))
      (node (ref "U17") (pin "12") (pinfunction "SPI_SELECT_12") (pintype "input"))
    )
    (net (code "17") (name "AIC_RST") (class "Default")
      (node (ref "R137") (pin "1") (pinfunction "1_1") (pintype "passive"))
      (node (ref "R141") (pin "1") (pinfunction "1_1") (pintype "passive"))
      (node (ref "R8") (pin "1") (pinfunction "1_1") (pintype "passive"))
      (node (ref "U17") (pin "31") (pinfunction "RESETN_31") (pintype "input"))
    )
    (net (code "18") (name "ANA_LDO_OUT") (class "Default")
      (node (ref "C73") (pin "1") (pinfunction "1_1") (pintype "passive"))
      (node (ref "C85") (pin "1") (pinfunction "1_1") (pintype "passive"))
      (node (ref "C86") (pin "1") (pinfunction "1_1") (pintype "passive"))
      (node (ref "U4") (pin "B7") (pinfunction "VDDA_ANA_B7") (pintype "power_in"))
      (node (ref "U4") (pin "B9") (pinfunction "ANA_LDOO_B9") (pintype "power_in"))
      (node (ref "U4") (pin "C7") (pinfunction "VDDA_PLL_C7") (pintype "power_in"))
    )
    (net (code "19") (name "ANA_LDO_OUT2") (class "Default")
      (node (ref "C73-2") (pin "1") (pinfunction "1_1") (pintype "passive"))
      (node (ref "C85-2") (pin "1") (pinfunction "1_1") (pintype "passive"))
      (node (ref "C86-2") (pin "1") (pinfunction "1_1") (pintype "passive"))
      (node (ref "J7") (pin "14") (pinfunction "14_14") (pintype "passive"))
      (node (ref "U5") (pin "B7") (pinfunction "VDDA_ANA_B7") (pintype "power_in"))
      (node (ref "U5") (pin "B9") (pinfunction "ANA_LDOO_B9") (pintype "power_in"))
      (node (ref "U5") (pin "C7") (pinfunction "VDDA_PLL_C7") (pintype "power_in"))
    )
    (net (code "20") (name "BAT+") (class "Default")
      (node (ref "J8") (pin "2") (pinfunction "2_2") (pintype "passive"))
      (node (ref "JP1") (pin "2") (pinfunction "2_2") (pintype "passive"))
    )
    (net (code "21") (name "BAT-") (class "Default")
      (node (ref "J3") (pin "R") (pinfunction "R_R") (pintype "passive"))
      (node (ref "J3") (pin "RN") (pinfunction "RN_RN") (pintype "passive"))
      (node (ref "J8") (pin "1") (pinfunction "1_1") (pintype "passive"))
      (node (ref "JP1") (pin "1") (pinfunction "1_1") (pintype "passive"))
    )
    (net (code "22") (name "C2-CENTER") (class "Default")
      (node (ref "J5") (pin "12") (pinfunction "12_12") (pintype "passive"))
      (node (ref "R83X") (pin "1") (pinfunction "1_1") (pintype "passive"))
      (node (ref "U5") (pin "N7") (pinfunction "LCD_D[5]/GP[15]_N7") (pintype "tri_state"))
    )
    (net (code "23") (name "C2-DOWN") (class "Default")
      (node (ref "J5") (pin "8") (pinfunction "8_8") (pintype "passive"))
      (node (ref "U5") (pin "P3") (pinfunction "LCD_D[6]/GP[16]_P3") (pintype "tri_state"))
    )
    (net (code "24") (name "C2-LEFT") (class "Default")
      (node (ref "J5") (pin "20") (pinfunction "20_20") (pintype "passive"))
      (node (ref "U5") (pin "N5") (pinfunction "LCD_D[3]/GP[13]_N5") (pintype "tri_state"))
    )
    (net (code "25") (name "C2-RIGHT") (class "Default")
      (node (ref "J5") (pin "4") (pinfunction "4_4") (pintype "passive"))
      (node (ref "U5") (pin "P8") (pinfunction "LCD_D[7]/GP[17]_P8") (pintype "tri_state"))
    )
    (net (code "26") (name "C2-UP") (class "Default")
      (node (ref "J5") (pin "16") (pinfunction "16_16") (pintype "passive"))
      (node (ref "U5") (pin "P2") (pinfunction "LCD_D[4]/GP[14]_P2") (pintype "tri_state"))
    )
    (net (code "27") (name "CLEAN") (class "Default")
      (node (ref "Q10") (pin "B") (pinfunction "B_B") (pintype "passive"))
      (node (ref "U5") (pin "M8") (pinfunction "SD0_CLK/I2S0_CLK/GP[0]_M8") (pintype "bidirectional"))
    )
    (net (code "28") (name "CLEAN_C") (class "Default")
      (node (ref "C188") (pin "1") (pinfunction "1_1") (pintype "passive"))
      (node (ref "C207") (pin "1") (pinfunction "1_1") (pintype "passive"))
      (node (ref "R172") (pin "2") (pinfunction "2_2") (pintype "passive"))
      (node (ref "U20") (pin "7") (pinfunction "OUT_7") (pintype "output"))
    )
    (net (code "29") (name "CLEAN_S") (class "Default")
      (node (ref "C188") (pin "2") (pinfunction "2_2") (pintype "passive"))
      (node (ref "R199") (pin "1") (pinfunction "1_1") (pintype "passive"))
      (node (ref "U13") (pin "3") (pinfunction "A_3") (pintype "bidirectional"))
    )
    (net (code "30") (name "CLK12MHZ") (class "Default")
      (node (ref "U14") (pin "3") (pinfunction "OUT_3") (pintype "output"))
      (node (ref "U15X") (pin "1") (pinfunction "CLKIN_1") (pintype "input"))
    )
    (net (code "31") (name "CLKOUT2") (class "Default")
      (node (ref "R117-2") (pin "2") (pinfunction "2_2") (pintype "passive"))
      (node (ref "TP4-2") (pin "TP") (pinfunction "TP_TP") (pintype "input"))
      (node (ref "U5") (pin "A2") (pinfunction "CLKOUT_A2") (pintype "output"))
    )
    (net (code "32") (name "CLK_12MHZ") (class "Default")
      (node (ref "R227X") (pin "2") (pinfunction "2_2") (pintype "passive"))
      (node (ref "R23") (pin "1") (pinfunction "1_1") (pintype "passive"))
    )
    (net (code "33") (name "CLK_SEL") (class "Default")
      (node (ref "R33") (pin "2") (pinfunction "2_2") (pintype "passive"))
      (node (ref "U4") (pin "D1") (pinfunction "CLK_SEL_D1") (pintype "input"))
    )
    (net (code "34") (name "CLK_SEL2") (class "Default")
      (node (ref "R33-2") (pin "2") (pinfunction "2_2") (pintype "passive"))
      (node (ref "U5") (pin "D1") (pinfunction "CLK_SEL_D1") (pintype "input"))
    )
    (net (code "35") (name "CODEC_AVDD") (class "Default")
      (node (ref "C116") (pin "1") (pinfunction "1_1") (pintype "passive"))
      (node (ref "C19") (pin "1") (pinfunction "1_1") (pintype "passive"))
      (node (ref "R107") (pin "1") (pinfunction "1_1") (pintype "passive"))
      (node (ref "U17") (pin "24") (pinfunction "AVDD_24") (pintype "power_in"))
    )
    (net (code "36") (name "CODEC_DVDD") (class "Default")
      (node (ref "C108") (pin "1") (pinfunction "1_1") (pintype "passive"))
      (node (ref "C11") (pin "1") (pinfunction "1_1") (pintype "passive"))
      (node (ref "R106") (pin "2") (pinfunction "2_2") (pintype "passive"))
      (node (ref "U17") (pin "29") (pinfunction "DVDD_29") (pintype "power_in"))
    )
    (net (code "37") (name "CODEC_IOVDD") (class "Default")
      (node (ref "C105") (pin "1") (pinfunction "1_1") (pintype "passive"))
      (node (ref "C8") (pin "1") (pinfunction "1_1") (pintype "passive"))
      (node (ref "R5") (pin "2") (pinfunction "2_2") (pintype "passive"))
      (node (ref "U17") (pin "6") (pinfunction "IOVDD_6") (pintype "power_in"))
    )
    (net (code "38") (name "CODEC_LDOIN") (class "Default")
      (node (ref "C111") (pin "1") (pinfunction "1_1") (pintype "passive"))
      (node (ref "C12") (pin "1") (pinfunction "1_1") (pintype "passive"))
      (node (ref "R108") (pin "1") (pinfunction "1_1") (pintype "passive"))
      (node (ref "U17") (pin "26") (pinfunction "LDOIN_26") (pintype "power_in"))
    )
    (net (code "39") (name "CONN_HP_LOUT") (class "Default")
      (node (ref "C14") (pin "-") (pinfunction "-_-") (pintype "passive"))
      (node (ref "J4") (pin "2") (pinfunction "T_2") (pintype "passive"))
    )
    (net (code "40") (name "CONN_HP_ROUT") (class "Default")
      (node (ref "C13") (pin "-") (pinfunction "-_-") (pintype "passive"))
      (node (ref "J4") (pin "3") (pinfunction "R_3") (pintype "passive"))
    )
    (net (code "41") (name "CPU1_LED") (class "Default")
      (node (ref "DS2") (pin "A") (pinfunction "A_A") (pintype "passive"))
      (node (ref "U4") (pin "P8") (pinfunction "LCD_D[7]/GP[17]_P8") (pintype "tri_state"))
    )
    (net (code "42") (name "CPU2_CLK_12MHZ") (class "Default")
      (node (ref "R226X") (pin "2") (pinfunction "2_2") (pintype "passive"))
      (node (ref "R38-2") (pin "1") (pinfunction "1_1") (pintype "passive"))
    )
    (net (code "43") (name "CPU2_LED") (class "Default")
      (node (ref "D3X") (pin "A") (pinfunction "A_A") (pintype "passive"))
      (node (ref "U5") (pin "M12") (pinfunction "SD1_D3/GP[11]_M12") (pintype "bidirectional"))
    )
    (net (code "44") (name "CPU_CLK_12MHZ") (class "Default")
      (node (ref "R229X") (pin "2") (pinfunction "2_2") (pintype "passive"))
      (node (ref "R38") (pin "1") (pinfunction "1_1") (pintype "passive"))
    )
    (net (code "45") (name "DCIN") (class "Default")
      (node (ref "CF1") (pin "1") (pinfunction "1_1") (pintype "passive"))
      (node (ref "J8") (pin "3") (pinfunction "3_3") (pintype "passive"))
    )
    (net (code "46") (name "DGND") (class "Default")
      (node (ref "C1") (pin "2") (pinfunction "2_2") (pintype "passive"))
      (node (ref "C1-2") (pin "2") (pinfunction "2_2") (pintype "passive"))
      (node (ref "C10") (pin "2") (pinfunction "2_2") (pintype "passive"))
      (node (ref "C104") (pin "2") (pinfunction "2_2") (pintype "passive"))
      (node (ref "C105") (pin "2") (pinfunction "2_2") (pintype "passive"))
      (node (ref "C108") (pin "2") (pinfunction "2_2") (pintype "passive"))
      (node (ref "C11") (pin "2") (pinfunction "2_2") (pintype "passive"))
      (node (ref "C122") (pin "2") (pinfunction "2_2") (pintype "passive"))
      (node (ref "C15") (pin "2") (pinfunction "2_2") (pintype "passive"))
      (node (ref "C168X") (pin "2") (pinfunction "2_2") (pintype "passive"))
      (node (ref "C169X") (pin "2") (pinfunction "2_2") (pintype "passive"))
      (node (ref "C185") (pin "2") (pinfunction "2_2") (pintype "passive"))
      (node (ref "C20") (pin "2") (pinfunction "2_2") (pintype "passive"))
      (node (ref "C204") (pin "2") (pinfunction "2_2") (pintype "passive"))
      (node (ref "C205") (pin "2") (pinfunction "2_2") (pintype "passive"))
      (node (ref "C209") (pin "2") (pinfunction "2_2") (pintype "passive"))
      (node (ref "C21") (pin "2") (pinfunction "2_2") (pintype "passive"))
      (node (ref "C210") (pin "2") (pinfunction "2_2") (pintype "passive"))
      (node (ref "C212") (pin "2") (pinfunction "2_2") (pintype "passive"))
      (node (ref "C213X") (pin "2") (pinfunction "2_2") (pintype "passive"))
      (node (ref "C214") (pin "2") (pinfunction "2_2") (pintype "passive"))
      (node (ref "C215X") (pin "2") (pinfunction "2_2") (pintype "passive"))
      (node (ref "C216X") (pin "2") (pinfunction "2_2") (pintype "passive"))
      (node (ref "C217X") (pin "2") (pinfunction "2_2") (pintype "passive"))
      (node (ref "C218X") (pin "2") (pinfunction "2_2") (pintype "passive"))
      (node (ref "C21X") (pin "2") (pinfunction "2_2") (pintype "passive"))
      (node (ref "C220") (pin "2") (pinfunction "2_2") (pintype "passive"))
      (node (ref "C221") (pin "2") (pinfunction "2_2") (pintype "passive"))
      (node (ref "C222") (pin "2") (pinfunction "2_2") (pintype "passive"))
      (node (ref "C23X") (pin "2") (pinfunction "2_2") (pintype "passive"))
      (node (ref "C24") (pin "2") (pinfunction "2_2") (pintype "passive"))
      (node (ref "C24-2") (pin "2") (pinfunction "2_2") (pintype "passive"))
      (node (ref "C25") (pin "2") (pinfunction "2_2") (pintype "passive"))
      (node (ref "C25-2") (pin "2") (pinfunction "2_2") (pintype "passive"))
      (node (ref "C26X") (pin "2") (pinfunction "2_2") (pintype "passive"))
      (node (ref "C28") (pin "2") (pinfunction "2_2") (pintype "passive"))
      (node (ref "C28-2") (pin "2") (pinfunction "2_2") (pintype "passive"))
      (node (ref "C29") (pin "2") (pinfunction "2_2") (pintype "passive"))
      (node (ref "C29-2") (pin "2") (pinfunction "2_2") (pintype "passive"))
      (node (ref "C30") (pin "2") (pinfunction "2_2") (pintype "passive"))
      (node (ref "C30-2") (pin "2") (pinfunction "2_2") (pintype "passive"))
      (node (ref "C32") (pin "2") (pinfunction "2_2") (pintype "passive"))
      (node (ref "C32-2") (pin "2") (pinfunction "2_2") (pintype "passive"))
      (node (ref "C33") (pin "2") (pinfunction "2_2") (pintype "passive"))
      (node (ref "C34") (pin "1") (pinfunction "1_1") (pintype "passive"))
      (node (ref "C35") (pin "2") (pinfunction "2_2") (pintype "passive"))
      (node (ref "C36") (pin "2") (pinfunction "2_2") (pintype "passive"))
      (node (ref "C37") (pin "1") (pinfunction "1_1") (pintype "passive"))
      (node (ref "C38") (pin "2") (pinfunction "2_2") (pintype "passive"))
      (node (ref "C38-2") (pin "2") (pinfunction "2_2") (pintype "passive"))
      (node (ref "C4") (pin "2") (pinfunction "2_2") (pintype "passive"))
      (node (ref "C4-2") (pin "2") (pinfunction "2_2") (pintype "passive"))
      (node (ref "C40") (pin "2") (pinfunction "2_2") (pintype "passive"))
      (node (ref "C40-2") (pin "2") (pinfunction "2_2") (pintype "passive"))
      (node (ref "C41") (pin "2") (pinfunction "2_2") (pintype "passive"))
      (node (ref "C41-2") (pin "2") (pinfunction "2_2") (pintype "passive"))
      (node (ref "C42") (pin "2") (pinfunction "2_2") (pintype "passive"))
      (node (ref "C42-2") (pin "2") (pinfunction "2_2") (pintype "passive"))
      (node (ref "C44") (pin "1") (pinfunction "1_1") (pintype "passive"))
      (node (ref "C45") (pin "2") (pinfunction "2_2") (pintype "passive"))
      (node (ref "C45-2") (pin "2") (pinfunction "2_2") (pintype "passive"))
      (node (ref "C46") (pin "2") (pinfunction "2_2") (pintype "passive"))
      (node (ref "C46-2") (pin "2") (pinfunction "2_2") (pintype "passive"))
      (node (ref "C47") (pin "1") (pinfunction "1_1") (pintype "passive"))
      (node (ref "C48") (pin "2") (pinfunction "2_2") (pintype "passive"))
      (node (ref "C48-2") (pin "2") (pinfunction "2_2") (pintype "passive"))
      (node (ref "C5") (pin "2") (pinfunction "2_2") (pintype "passive"))
      (node (ref "C5-2") (pin "2") (pinfunction "2_2") (pintype "passive"))
      (node (ref "C51") (pin "2") (pinfunction "2_2") (pintype "passive"))
      (node (ref "C51-2") (pin "2") (pinfunction "2_2") (pintype "passive"))
      (node (ref "C52") (pin "2") (pinfunction "2_2") (pintype "passive"))
      (node (ref "C52-2") (pin "2") (pinfunction "2_2") (pintype "passive"))
      (node (ref "C53") (pin "2") (pinfunction "2_2") (pintype "passive"))
      (node (ref "C53-2") (pin "2") (pinfunction "2_2") (pintype "passive"))
      (node (ref "C54") (pin "2") (pinfunction "2_2") (pintype "passive"))
      (node (ref "C54-2") (pin "2") (pinfunction "2_2") (pintype "passive"))
      (node (ref "C55") (pin "2") (pinfunction "2_2") (pintype "passive"))
      (node (ref "C55-2") (pin "2") (pinfunction "2_2") (pintype "passive"))
      (node (ref "C56") (pin "2") (pinfunction "2_2") (pintype "passive"))
      (node (ref "C56-2") (pin "2") (pinfunction "2_2") (pintype "passive"))
      (node (ref "C58") (pin "2") (pinfunction "2_2") (pintype "passive"))
      (node (ref "C59") (pin "2") (pinfunction "2_2") (pintype "passive"))
      (node (ref "C59-2") (pin "2") (pinfunction "2_2") (pintype "passive"))
      (node (ref "C6") (pin "2") (pinfunction "2_2") (pintype "passive"))
      (node (ref "C6-2") (pin "2") (pinfunction "2_2") (pintype "passive"))
      (node (ref "C60") (pin "2") (pinfunction "2_2") (pintype "passive"))
      (node (ref "C60-2") (pin "2") (pinfunction "2_2") (pintype "passive"))
      (node (ref "C61") (pin "1") (pinfunction "1_1") (pintype "passive"))
      (node (ref "C62") (pin "2") (pinfunction "2_2") (pintype "passive"))
      (node (ref "C62-2") (pin "2") (pinfunction "2_2") (pintype "passive"))
      (node (ref "C63") (pin "2") (pinfunction "2_2") (pintype "passive"))
      (node (ref "C63-2") (pin "2") (pinfunction "2_2") (pintype "passive"))
      (node (ref "C64") (pin "2") (pinfunction "2_2") (pintype "passive"))
      (node (ref "C64-2") (pin "2") (pinfunction "2_2") (pintype "passive"))
      (node (ref "C65") (pin "2") (pinfunction "2_2") (pintype "passive"))
      (node (ref "C65-2") (pin "2") (pinfunction "2_2") (pintype "passive"))
      (node (ref "C66") (pin "2") (pinfunction "2_2") (pintype "passive"))
      (node (ref "C66-2") (pin "2") (pinfunction "2_2") (pintype "passive"))
      (node (ref "C67") (pin "2") (pinfunction "2_2") (pintype "passive"))
      (node (ref "C67-2") (pin "2") (pinfunction "2_2") (pintype "passive"))
      (node (ref "C68") (pin "2") (pinfunction "2_2") (pintype "passive"))
      (node (ref "C69") (pin "2") (pinfunction "2_2") (pintype "passive"))
      (node (ref "C69-2") (pin "2") (pinfunction "2_2") (pintype "passive"))
      (node (ref "C7") (pin "2") (pinfunction "2_2") (pintype "passive"))
      (node (ref "C70") (pin "2") (pinfunction "2_2") (pintype "passive"))
      (node (ref "C71") (pin "2") (pinfunction "2_2") (pintype "passive"))
      (node (ref "C71-2") (pin "2") (pinfunction "2_2") (pintype "passive"))
      (node (ref "C72") (pin "2") (pinfunction "2_2") (pintype "passive"))
      (node (ref "C72-2") (pin "2") (pinfunction "2_2") (pintype "passive"))
      (node (ref "C74") (pin "2") (pinfunction "2_2") (pintype "passive"))
      (node (ref "C74-2") (pin "2") (pinfunction "2_2") (pintype "passive"))
      (node (ref "C75") (pin "2") (pinfunction "2_2") (pintype "passive"))
      (node (ref "C75-2") (pin "2") (pinfunction "2_2") (pintype "passive"))
      (node (ref "C76") (pin "1") (pinfunction "1_1") (pintype "passive"))
      (node (ref "C77") (pin "2") (pinfunction "2_2") (pintype "passive"))
      (node (ref "C77-2") (pin "2") (pinfunction "2_2") (pintype "passive"))
      (node (ref "C78") (pin "2") (pinfunction "2_2") (pintype "passive"))
      (node (ref "C79") (pin "2") (pinfunction "2_2") (pintype "passive"))
      (node (ref "C8") (pin "2") (pinfunction "2_2") (pintype "passive"))
      (node (ref "C80") (pin "2") (pinfunction "2_2") (pintype "passive"))
      (node (ref "C81") (pin "2") (pinfunction "2_2") (pintype "passive"))
      (node (ref "C81-2") (pin "2") (pinfunction "2_2") (pintype "passive"))
      (node (ref "C82") (pin "2") (pinfunction "2_2") (pintype "passive"))
      (node (ref "C82-2") (pin "2") (pinfunction "2_2") (pintype "passive"))
      (node (ref "C83") (pin "2") (pinfunction "2_2") (pintype "passive"))
      (node (ref "C83-2") (pin "2") (pinfunction "2_2") (pintype "passive"))
      (node (ref "C84") (pin "2") (pinfunction "2_2") (pintype "passive"))
      (node (ref "C84-2") (pin "2") (pinfunction "2_2") (pintype "passive"))
      (node (ref "C87") (pin "2") (pinfunction "2_2") (pintype "passive"))
      (node (ref "C87-2") (pin "2") (pinfunction "2_2") (pintype "passive"))
      (node (ref "C89") (pin "2") (pinfunction "2_2") (pintype "passive"))
      (node (ref "C89-2") (pin "2") (pinfunction "2_2") (pintype "passive"))
      (node (ref "C9") (pin "2") (pinfunction "2_2") (pintype "passive"))
      (node (ref "C92") (pin "2") (pinfunction "2_2") (pintype "passive"))
      (node (ref "C93") (pin "2") (pinfunction "2_2") (pintype "passive"))
      (node (ref "C94X") (pin "2") (pinfunction "2_2") (pintype "passive"))
      (node (ref "C98X") (pin "2") (pinfunction "2_2") (pintype "passive"))
      (node (ref "C99X") (pin "2") (pinfunction "2_2") (pintype "passive"))
      (node (ref "D2") (pin "A") (pinfunction "A_A") (pintype "passive"))
      (node (ref "D2-2") (pin "A") (pinfunction "A_A") (pintype "passive"))
      (node (ref "FB1") (pin "1") (pinfunction "1_1") (pintype "passive"))
      (node (ref "FB1-2") (pin "1") (pinfunction "1_1") (pintype "passive"))
      (node (ref "FB2") (pin "1") (pinfunction "1_1") (pintype "passive"))
      (node (ref "H1") (pin "B3,0") (pinfunction "MOUNT_B3,0") (pintype "passive"))
      (node (ref "H2") (pin "B3,0") (pinfunction "MOUNT_B3,0") (pintype "passive"))
      (node (ref "H3") (pin "B3,0") (pinfunction "MOUNT_B3,0") (pintype "passive"))
      (node (ref "H4") (pin "B3,0") (pinfunction "MOUNT_B3,0") (pintype "passive"))
      (node (ref "IC2") (pin "7") (pinfunction "VSS_7") (pintype "power_in"))
      (node (ref "J1") (pin "GND") (pinfunction "GND_GND") (pintype "bidirectional"))
      (node (ref "J1") (pin "MTN1") (pinfunction "MTN2_MTN1") (pintype "bidirectional"))
      (node (ref "J1") (pin "MTN2") (pinfunction "MTN3_MTN2") (pintype "bidirectional"))
      (node (ref "J1") (pin "MTN3") (pinfunction "MTN1_MTN3") (pintype "bidirectional"))
      (node (ref "J1") (pin "MTN4") (pinfunction "MTN4_MTN4") (pintype "bidirectional"))
      (node (ref "J1-2") (pin "GND") (pinfunction "GND_GND") (pintype "bidirectional"))
      (node (ref "J1-2") (pin "MTN1") (pinfunction "MTN2_MTN1") (pintype "bidirectional"))
      (node (ref "J1-2") (pin "MTN2") (pinfunction "MTN3_MTN2") (pintype "bidirectional"))
      (node (ref "J1-2") (pin "MTN3") (pinfunction "MTN1_MTN3") (pintype "bidirectional"))
      (node (ref "J1-2") (pin "MTN4") (pinfunction "MTN4_MTN4") (pintype "bidirectional"))
      (node (ref "J11") (pin "11") (pinfunction "INSERT_COM_11") (pintype "passive"))
      (node (ref "J11") (pin "6") (pinfunction "VSS_6") (pintype "power_in"))
      (node (ref "J2") (pin "GND") (pinfunction "GND_GND") (pintype "bidirectional"))
      (node (ref "J5") (pin "19") (pinfunction "19_19") (pintype "passive"))
      (node (ref "J5") (pin "3") (pinfunction "3_3") (pintype "passive"))
      (node (ref "J5") (pin "7") (pinfunction "7_7") (pintype "passive"))
      (node (ref "J6") (pin "11") (pinfunction "INSERT_COM_11") (pintype "passive"))
      (node (ref "J6") (pin "6") (pinfunction "VSS_6") (pintype "power_in"))
      (node (ref "J7") (pin "16") (pinfunction "16_16") (pintype "passive"))
      (node (ref "J7") (pin "18") (pinfunction "18_18") (pintype "passive"))
      (node (ref "J7") (pin "19") (pinfunction "19_19") (pintype "passive"))
      (node (ref "J7") (pin "20") (pinfunction "20_20") (pintype "passive"))
      (node (ref "JP2") (pin "1") (pinfunction "1_1") (pintype "passive"))
      (node (ref "LSP1") (pin "MP") (pinfunction "MP_MP") (pintype "passive"))
      (node (ref "LSP2") (pin "MP") (pinfunction "MP_MP") (pintype "passive"))
      (node (ref "Q10") (pin "E") (pinfunction "E_E") (pintype "passive"))
      (node (ref "Q2") (pin "E") (pinfunction "E_E") (pintype "passive"))
      (node (ref "Q4") (pin "E") (pinfunction "E_E") (pintype "passive"))
      (node (ref "Q8") (pin "E") (pinfunction "E_E") (pintype "passive"))
      (node (ref "Q9") (pin "E") (pinfunction "E_E") (pintype "passive"))
      (node (ref "R104") (pin "1") (pinfunction "1_1") (pintype "passive"))
      (node (ref "R117") (pin "1") (pinfunction "1_1") (pintype "passive"))
      (node (ref "R117-2") (pin "1") (pinfunction "1_1") (pintype "passive"))
      (node (ref "R126X") (pin "1") (pinfunction "1_1") (pintype "passive"))
      (node (ref "R136") (pin "1") (pinfunction "1_1") (pintype "passive"))
      (node (ref "R137") (pin "2") (pinfunction "2_2") (pintype "passive"))
      (node (ref "R138") (pin "1") (pinfunction "1_1") (pintype "passive"))
      (node (ref "R15X") (pin "1") (pinfunction "1_1") (pintype "passive"))
      (node (ref "R17") (pin "1") (pinfunction "1_1") (pintype "passive"))
      (node (ref "R18") (pin "1") (pinfunction "1_1") (pintype "passive"))
      (node (ref "R18-2") (pin "1") (pinfunction "1_1") (pintype "passive"))
      (node (ref "R209") (pin "1") (pinfunction "1_1") (pintype "passive"))
      (node (ref "R212") (pin "1") (pinfunction "1_1") (pintype "passive"))
      (node (ref "R215") (pin "1") (pinfunction "1_1") (pintype "passive"))
      (node (ref "R216") (pin "1") (pinfunction "1_1") (pintype "passive"))
      (node (ref "R28") (pin "1") (pinfunction "1_1") (pintype "passive"))
      (node (ref "R33") (pin "1") (pinfunction "1_1") (pintype "passive"))
      (node (ref "R33-2") (pin "1") (pinfunction "1_1") (pintype "passive"))
      (node (ref "R34") (pin "1") (pinfunction "1_1") (pintype "passive"))
      (node (ref "R34-2") (pin "1") (pinfunction "1_1") (pintype "passive"))
      (node (ref "R43") (pin "2") (pinfunction "2_2") (pintype "passive"))
      (node (ref "R54") (pin "1") (pinfunction "1_1") (pintype "passive"))
      (node (ref "R54-2") (pin "1") (pinfunction "1_1") (pintype "passive"))
      (node (ref "R56") (pin "1") (pinfunction "1_1") (pintype "passive"))
      (node (ref "R56-2") (pin "1") (pinfunction "1_1") (pintype "passive"))
      (node (ref "R57") (pin "2") (pinfunction "2_2") (pintype "passive"))
      (node (ref "R59") (pin "1") (pinfunction "1_1") (pintype "passive"))
      (node (ref "R59-2") (pin "1") (pinfunction "1_1") (pintype "passive"))
      (node (ref "R60") (pin "1") (pinfunction "1_1") (pintype "passive"))
      (node (ref "R60-2") (pin "1") (pinfunction "1_1") (pintype "passive"))
      (node (ref "R61") (pin "1") (pinfunction "1_1") (pintype "passive"))
      (node (ref "R61-2") (pin "1") (pinfunction "1_1") (pintype "passive"))
      (node (ref "R62") (pin "1") (pinfunction "1_1") (pintype "passive"))
      (node (ref "R62-2") (pin "1") (pinfunction "1_1") (pintype "passive"))
      (node (ref "R64") (pin "1") (pinfunction "1_1") (pintype "passive"))
      (node (ref "R64-2") (pin "1") (pinfunction "1_1") (pintype "passive"))
      (node (ref "R70X") (pin "1") (pinfunction "1_1") (pintype "passive"))
      (node (ref "R76X") (pin "1") (pinfunction "1_1") (pintype "passive"))
      (node (ref "R9") (pin "1") (pinfunction "1_1") (pintype "passive"))
      (node (ref "SW1") (pin "3") (pinfunction "S_3") (pintype "passive"))
      (node (ref "TP2") (pin "TP") (pinfunction "TP_TP") (pintype "input"))
      (node (ref "U10X") (pin "1") (pinfunction "A0_1") (pintype "input"))
      (node (ref "U10X") (pin "2") (pinfunction "A1_2") (pintype "input"))
      (node (ref "U10X") (pin "3") (pinfunction "A2_3") (pintype "input"))
      (node (ref "U10X") (pin "4") (pinfunction "GND_4") (pintype "power_in"))
      (node (ref "U11X") (pin "2") (pinfunction "GND_2") (pintype "passive"))
      (node (ref "U12X") (pin "1") (pinfunction "GND_1") (pintype "power_in"))
      (node (ref "U13") (pin "2") (pinfunction "GND_2") (pintype "power_in"))
      (node (ref "U14") (pin "2") (pinfunction "GND_2") (pintype "power_in"))
      (node (ref "U15X") (pin "12") (pinfunction "GND_3_12") (pintype "passive"))
      (node (ref "U15X") (pin "4") (pinfunction "GND_2_4") (pintype "passive"))
      (node (ref "U15X") (pin "7") (pinfunction "GND_7") (pintype "passive"))
      (node (ref "U17") (pin "28") (pinfunction "DVSS_28") (pintype "power_in"))
      (node (ref "U17") (pin "7") (pinfunction "IOVSS_7") (pintype "power_in"))
      (node (ref "U18") (pin "10") (pinfunction "GND_10") (pintype "passive"))
      (node (ref "U1X") (pin "1") (pinfunction "GND_1") (pintype "power_in"))
      (node (ref "U2") (pin "5") (pinfunction "GND_5") (pintype "power_in"))
      (node (ref "U24") (pin "4") (pinfunction "GND_4") (pintype "power_in"))
      (node (ref "U3X") (pin "2") (pinfunction "GND_2") (pintype "passive"))
      (node (ref "U4") (pin "A11") (pinfunction "RSV4_A11") (pintype "input"))
      (node (ref "U4") (pin "A14") (pinfunction "VSS_A14") (pintype "power_in"))
      (node (ref "U4") (pin "B11") (pinfunction "RSV5_B11") (pintype "input"))
      (node (ref "U4") (pin "B2") (pinfunction "VSS_B2") (pintype "power_in"))
      (node (ref "U4") (pin "B3") (pinfunction "VSS_B3") (pintype "power_in"))
      (node (ref "U4") (pin "C12") (pinfunction "VSS_C12") (pintype "power_in"))
      (node (ref "U4") (pin "C8") (pinfunction "VSS_C8") (pintype "power_in"))
      (node (ref "U4") (pin "D10") (pinfunction "VSS_D10") (pintype "power_in"))
      (node (ref "U4") (pin "D4") (pinfunction "VSS_D4") (pintype "power_in"))
      (node (ref "U4") (pin "D5") (pinfunction "VSS_D5") (pintype "power_in"))
      (node (ref "U4") (pin "E11") (pinfunction "VSS_E11") (pintype "power_in"))
      (node (ref "U4") (pin "E3") (pinfunction "VSS_E3") (pintype "power_in"))
      (node (ref "U4") (pin "E4") (pinfunction "VSS_E4") (pintype "power_in"))
      (node (ref "U4") (pin "F3") (pinfunction "VSS_F3") (pintype "power_in"))
      (node (ref "U4") (pin "H13") (pinfunction "USB_VSSA3P3_H13") (pintype "power_in"))
      (node (ref "U4") (pin "H3") (pinfunction "VSS_H3") (pintype "power_in"))
      (node (ref "U4") (pin "J13") (pinfunction "VSS_J13") (pintype "power_in"))
      (node (ref "U4") (pin "K14") (pinfunction "USB_VSS1P3_K14") (pintype "power_in"))
      (node (ref "U4") (pin "K3") (pinfunction "VSS_K3") (pintype "power_in"))
      (node (ref "U4") (pin "K4") (pinfunction "VSS_K4") (pintype "power_in"))
      (node (ref "U4") (pin "L10") (pinfunction "VSS_L10") (pintype "power_in"))
      (node (ref "U4") (pin "L5") (pinfunction "VSS_L5") (pintype "power_in"))
      (node (ref "U4") (pin "M7") (pinfunction "VSS_M7") (pintype "power_in"))
      (node (ref "U4") (pin "P1") (pinfunction "VSS_P1") (pintype "power_in"))
      (node (ref "U4") (pin "P14") (pinfunction "VSS_P14") (pintype "power_in"))
      (node (ref "U5") (pin "A11") (pinfunction "RSV4_A11") (pintype "input"))
      (node (ref "U5") (pin "A14") (pinfunction "VSS_A14") (pintype "power_in"))
      (node (ref "U5") (pin "B11") (pinfunction "RSV5_B11") (pintype "input"))
      (node (ref "U5") (pin "B2") (pinfunction "VSS_B2") (pintype "power_in"))
      (node (ref "U5") (pin "B3") (pinfunction "VSS_B3") (pintype "power_in"))
      (node (ref "U5") (pin "C12") (pinfunction "VSS_C12") (pintype "power_in"))
      (node (ref "U5") (pin "C8") (pinfunction "VSS_C8") (pintype "power_in"))
      (node (ref "U5") (pin "D10") (pinfunction "VSS_D10") (pintype "power_in"))
      (node (ref "U5") (pin "D4") (pinfunction "VSS_D4") (pintype "power_in"))
      (node (ref "U5") (pin "D5") (pinfunction "VSS_D5") (pintype "power_in"))
      (node (ref "U5") (pin "E11") (pinfunction "VSS_E11") (pintype "power_in"))
      (node (ref "U5") (pin "E3") (pinfunction "VSS_E3") (pintype "power_in"))
      (node (ref "U5") (pin "E4") (pinfunction "VSS_E4") (pintype "power_in"))
      (node (ref "U5") (pin "F3") (pinfunction "VSS_F3") (pintype "power_in"))
      (node (ref "U5") (pin "H13") (pinfunction "USB_VSSA3P3_H13") (pintype "power_in"))
      (node (ref "U5") (pin "H3") (pinfunction "VSS_H3") (pintype "power_in"))
      (node (ref "U5") (pin "J13") (pinfunction "VSS_J13") (pintype "power_in"))
      (node (ref "U5") (pin "K14") (pinfunction "USB_VSS1P3_K14") (pintype "power_in"))
      (node (ref "U5") (pin "K3") (pinfunction "VSS_K3") (pintype "power_in"))
      (node (ref "U5") (pin "K4") (pinfunction "VSS_K4") (pintype "power_in"))
      (node (ref "U5") (pin "L10") (pinfunction "VSS_L10") (pintype "power_in"))
      (node (ref "U5") (pin "L5") (pinfunction "VSS_L5") (pintype "power_in"))
      (node (ref "U5") (pin "M7") (pinfunction "VSS_M7") (pintype "power_in"))
      (node (ref "U5") (pin "P1") (pinfunction "VSS_P1") (pintype "power_in"))
      (node (ref "U5") (pin "P14") (pinfunction "VSS_P14") (pintype "power_in"))
      (node (ref "U6") (pin "1") (pinfunction "GND_1") (pintype "power_in"))
      (node (ref "U6") (pin "10") (pinfunction "AGND_10") (pintype "power_in"))
      (node (ref "U6") (pin "11") (pinfunction "GND_11") (pintype "power_in"))
      (node (ref "U6") (pin "15") (pinfunction "GND_15") (pintype "power_in"))
      (node (ref "U6") (pin "25") (pinfunction "GND_25") (pintype "power_in"))
      (node (ref "U6") (pin "35") (pinfunction "GND_35") (pintype "power_in"))
      (node (ref "U6") (pin "47") (pinfunction "GND_47") (pintype "power_in"))
      (node (ref "U6") (pin "5") (pinfunction "GND_5") (pintype "power_in"))
      (node (ref "U6") (pin "51") (pinfunction "GND_51") (pintype "power_in"))
      (node (ref "U7") (pin "4") (pinfunction "GND_4") (pintype "passive"))
      (node (ref "U8") (pin "2") (pinfunction "GND_2") (pintype "passive"))
      (node (ref "U9") (pin "10") (pinfunction "GND_10") (pintype "power_in"))
      (node (ref "U9-2") (pin "10") (pinfunction "GND_10") (pintype "power_in"))
      (node (ref "Y1") (pin "NC1") (pinfunction "3_NC1") (pintype "passive"))
      (node (ref "Y1") (pin "NC2") (pinfunction "4_NC2") (pintype "passive"))
      (node (ref "Y1-2") (pin "NC1") (pinfunction "3_NC1") (pintype "passive"))
      (node (ref "Y1-2") (pin "NC2") (pinfunction "4_NC2") (pintype "passive"))
    )
    (net (code "47") (name "DIS") (class "Default")
      (node (ref "R43") (pin "1") (pinfunction "1_1") (pintype "passive"))
      (node (ref "U6") (pin "32") (pinfunction "ACBUS5_32") (pintype "bidirectional"))
    )
    (net (code "48") (name "DIST") (class "Default")
      (node (ref "C184") (pin "2") (pinfunction "2_2") (pintype "passive"))
      (node (ref "R200") (pin "1") (pinfunction "1_1") (pintype "passive"))
      (node (ref "U13") (pin "1") (pinfunction "B_1") (pintype "bidirectional"))
    )
    (net (code "49") (name "DISTOCT") (class "Default")
      (node (ref "C183") (pin "1") (pinfunction "1_1") (pintype "passive"))
      (node (ref "J7") (pin "10") (pinfunction "10_10") (pintype "passive"))
    )
    (net (code "50") (name "DIST_OUT") (class "Default")
      (node (ref "C178") (pin "2") (pinfunction "2_2") (pintype "passive"))
      (node (ref "IC2") (pin "10") (pinfunction "B_10") (pintype "tri_state"))
      (node (ref "J7") (pin "8") (pinfunction "8_8") (pintype "passive"))
      (node (ref "R159") (pin "2") (pinfunction "2_2") (pintype "passive"))
      (node (ref "U21") (pin "1") (pinfunction "OUT_1") (pintype "output"))
    )
    (net (code "51") (name "DSP2_LDO_OUT") (class "Default")
      (node (ref "C38-2") (pin "1") (pinfunction "1_1") (pintype "passive"))
      (node (ref "C40-2") (pin "1") (pinfunction "1_1") (pintype "passive"))
      (node (ref "C41-2") (pin "1") (pinfunction "1_1") (pintype "passive"))
      (node (ref "C42-2") (pin "1") (pinfunction "1_1") (pintype "passive"))
      (node (ref "C46-2") (pin "1") (pinfunction "1_1") (pintype "passive"))
      (node (ref "C48-2") (pin "1") (pinfunction "1_1") (pintype "passive"))
      (node (ref "C51-2") (pin "1") (pinfunction "1_1") (pintype "passive"))
      (node (ref "C52-2") (pin "1") (pinfunction "1_1") (pintype "passive"))
      (node (ref "C53-2") (pin "1") (pinfunction "1_1") (pintype "passive"))
      (node (ref "C54-2") (pin "1") (pinfunction "1_1") (pintype "passive"))
      (node (ref "C55-2") (pin "1") (pinfunction "1_1") (pintype "passive"))
      (node (ref "C59-2") (pin "1") (pinfunction "1_1") (pintype "passive"))
      (node (ref "C62-2") (pin "1") (pinfunction "1_1") (pintype "passive"))
      (node (ref "C64-2") (pin "1") (pinfunction "1_1") (pintype "passive"))
      (node (ref "C65-2") (pin "1") (pinfunction "1_1") (pintype "passive"))
      (node (ref "C67-2") (pin "1") (pinfunction "1_1") (pintype "passive"))
      (node (ref "C69-2") (pin "1") (pinfunction "1_1") (pintype "passive"))
      (node (ref "C89-2") (pin "1") (pinfunction "1_1") (pintype "passive"))
      (node (ref "R124-2") (pin "2") (pinfunction "2_2") (pintype "passive"))
      (node (ref "U5") (pin "C11") (pinfunction "CVDD_C11") (pintype "power_in"))
      (node (ref "U5") (pin "D11") (pinfunction "CVDD_D11") (pintype "power_in"))
      (node (ref "U5") (pin "D3") (pinfunction "CVDD_D3") (pintype "power_in"))
      (node (ref "U5") (pin "F2") (pinfunction "CVDD_F2") (pintype "power_in"))
      (node (ref "U5") (pin "G3") (pinfunction "CVDD_G3") (pintype "power_in"))
      (node (ref "U5") (pin "H2") (pinfunction "CVDD_H2") (pintype "power_in"))
      (node (ref "U5") (pin "K11") (pinfunction "CVDD_K11") (pintype "power_in"))
      (node (ref "U5") (pin "K12") (pinfunction "RSV1_K12") (pintype "power_in"))
      (node (ref "U5") (pin "L13") (pinfunction "RSV2_L13") (pintype "power_in"))
      (node (ref "U5") (pin "M6") (pinfunction "CVDD_M6") (pintype "power_in"))
      (node (ref "U5") (pin "M9") (pinfunction "CVDD_M9") (pintype "power_in"))
      (node (ref "U5") (pin "N9") (pinfunction "CVDD_N9") (pintype "power_in"))
    )
    (net (code "52") (name "DSP2_LDO_OUT_REG") (class "Default")
      (node (ref "R124-2") (pin "1") (pinfunction "1_1") (pintype "passive"))
      (node (ref "U5") (pin "A13") (pinfunction "DSP_LDOO_A13") (pintype "power_in"))
    )
    (net (code "53") (name "DSP_LDO_OUT") (class "Default")
      (node (ref "C38") (pin "1") (pinfunction "1_1") (pintype "passive"))
      (node (ref "C40") (pin "1") (pinfunction "1_1") (pintype "passive"))
      (node (ref "C41") (pin "1") (pinfunction "1_1") (pintype "passive"))
      (node (ref "C42") (pin "1") (pinfunction "1_1") (pintype "passive"))
      (node (ref "C46") (pin "1") (pinfunction "1_1") (pintype "passive"))
      (node (ref "C48") (pin "1") (pinfunction "1_1") (pintype "passive"))
      (node (ref "C51") (pin "1") (pinfunction "1_1") (pintype "passive"))
      (node (ref "C52") (pin "1") (pinfunction "1_1") (pintype "passive"))
      (node (ref "C53") (pin "1") (pinfunction "1_1") (pintype "passive"))
      (node (ref "C54") (pin "1") (pinfunction "1_1") (pintype "passive"))
      (node (ref "C55") (pin "1") (pinfunction "1_1") (pintype "passive"))
      (node (ref "C59") (pin "1") (pinfunction "1_1") (pintype "passive"))
      (node (ref "C62") (pin "1") (pinfunction "1_1") (pintype "passive"))
      (node (ref "C64") (pin "1") (pinfunction "1_1") (pintype "passive"))
      (node (ref "C65") (pin "1") (pinfunction "1_1") (pintype "passive"))
      (node (ref "C67") (pin "1") (pinfunction "1_1") (pintype "passive"))
      (node (ref "C69") (pin "1") (pinfunction "1_1") (pintype "passive"))
      (node (ref "C89") (pin "1") (pinfunction "1_1") (pintype "passive"))
      (node (ref "R124") (pin "2") (pinfunction "2_2") (pintype "passive"))
      (node (ref "U4") (pin "C11") (pinfunction "CVDD_C11") (pintype "power_in"))
      (node (ref "U4") (pin "D11") (pinfunction "CVDD_D11") (pintype "power_in"))
      (node (ref "U4") (pin "D3") (pinfunction "CVDD_D3") (pintype "power_in"))
      (node (ref "U4") (pin "F2") (pinfunction "CVDD_F2") (pintype "power_in"))
      (node (ref "U4") (pin "G3") (pinfunction "CVDD_G3") (pintype "power_in"))
      (node (ref "U4") (pin "H2") (pinfunction "CVDD_H2") (pintype "power_in"))
      (node (ref "U4") (pin "K11") (pinfunction "CVDD_K11") (pintype "power_in"))
      (node (ref "U4") (pin "K12") (pinfunction "RSV1_K12") (pintype "power_in"))
      (node (ref "U4") (pin "L13") (pinfunction "RSV2_L13") (pintype "power_in"))
      (node (ref "U4") (pin "M6") (pinfunction "CVDD_M6") (pintype "power_in"))
      (node (ref "U4") (pin "M9") (pinfunction "CVDD_M9") (pintype "power_in"))
      (node (ref "U4") (pin "N9") (pinfunction "CVDD_N9") (pintype "power_in"))
    )
    (net (code "54") (name "DSP_LDO_OUT_REG") (class "Default")
      (node (ref "R124") (pin "1") (pinfunction "1_1") (pintype "passive"))
      (node (ref "U4") (pin "A13") (pinfunction "DSP_LDOO_A13") (pintype "power_in"))
    )
    (net (code "55") (name "EECS") (class "Default")
      (node (ref "U2") (pin "1") (pinfunction "CS_1") (pintype "input"))
      (node (ref "U6") (pin "63") (pinfunction "EECS_63") (pintype "bidirectional"))
    )
    (net (code "56") (name "EEDATA") (class "Default")
      (node (ref "R21") (pin "2") (pinfunction "2_2") (pintype "passive"))
      (node (ref "U2") (pin "3") (pinfunction "DI_3") (pintype "input"))
      (node (ref "U6") (pin "61") (pinfunction "EEDATA_61") (pintype "bidirectional"))
    )
    (net (code "57") (name "EESK") (class "Default")
      (node (ref "U2") (pin "2") (pinfunction "SK_2") (pintype "input"))
      (node (ref "U6") (pin "62") (pinfunction "EESK_62") (pintype "output"))
    )
    (net (code "58") (name "EMU0") (class "Default")
      (node (ref "R25") (pin "1") (pinfunction "1_1") (pintype "passive"))
      (node (ref "U4") (pin "L2") (pinfunction "EMU0_L2") (pintype "bidirectional"))
      (node (ref "U5") (pin "L2") (pinfunction "EMU0_L2") (pintype "bidirectional"))
      (node (ref "U6") (pin "23") (pinfunction "ADBUS6_23") (pintype "bidirectional"))
    )
    (net (code "59") (name "EMU1") (class "Default")
      (node (ref "R22") (pin "1") (pinfunction "1_1") (pintype "passive"))
      (node (ref "U4") (pin "M1") (pinfunction "EMU1_M1") (pintype "bidirectional"))
      (node (ref "U5") (pin "M1") (pinfunction "EMU1_M1") (pintype "bidirectional"))
      (node (ref "U6") (pin "30") (pinfunction "ACBUS4_30") (pintype "bidirectional"))
    )
    (net (code "60") (name "FOOTSW") (class "Default")
      (node (ref "C168X") (pin "1") (pinfunction "1_1") (pintype "passive"))
      (node (ref "SW1") (pin "2") (pinfunction "P_2") (pintype "passive"))
      (node (ref "U5") (pin "N12") (pinfunction "LCD_D[12]/UART_RTS/GP[28]/I2S3_CLK_N12") (pintype "bidirectional"))
    )
    (net (code "61") (name "FT1.8V") (class "Default")
      (node (ref "C33") (pin "1") (pinfunction "1_1") (pintype "passive"))
      (node (ref "C36") (pin "1") (pinfunction "1_1") (pintype "passive"))
      (node (ref "C68") (pin "1") (pinfunction "1_1") (pintype "passive"))
      (node (ref "C70") (pin "1") (pinfunction "1_1") (pintype "passive"))
      (node (ref "U6") (pin "12") (pinfunction "VCORE_12") (pintype "power_in"))
      (node (ref "U6") (pin "37") (pinfunction "VCORE_37") (pintype "power_in"))
      (node (ref "U6") (pin "49") (pinfunction "VREGOUT_49") (pintype "power_in"))
      (node (ref "U6") (pin "64") (pinfunction "VCORE_64") (pintype "power_in"))
    )
    (net (code "62") (name "FTDI_3V3") (class "Default")
      (node (ref "C20") (pin "1") (pinfunction "1_1") (pintype "passive"))
      (node (ref "C34") (pin "2") (pinfunction "2_2") (pintype "passive"))
      (node (ref "C35") (pin "1") (pinfunction "1_1") (pintype "passive"))
      (node (ref "C58") (pin "1") (pinfunction "1_1") (pintype "passive"))
      (node (ref "C78") (pin "1") (pinfunction "1_1") (pintype "passive"))
      (node (ref "C79") (pin "1") (pinfunction "1_1") (pintype "passive"))
      (node (ref "C80") (pin "1") (pinfunction "1_1") (pintype "passive"))
      (node (ref "L4") (pin "1") (pinfunction "1_1") (pintype "passive"))
      (node (ref "L5") (pin "1") (pinfunction "1_1") (pintype "passive"))
      (node (ref "R19") (pin "1") (pinfunction "1_1") (pintype "passive"))
      (node (ref "R1X") (pin "2") (pinfunction "2_2") (pintype "passive"))
      (node (ref "R36") (pin "1") (pinfunction "1_1") (pintype "passive"))
      (node (ref "R42") (pin "2") (pinfunction "2_2") (pintype "passive"))
      (node (ref "R44") (pin "2") (pinfunction "2_2") (pintype "passive"))
      (node (ref "U2") (pin "8") (pinfunction "VCC_8") (pintype "power_in"))
      (node (ref "U6") (pin "20") (pinfunction "VCCIO_20") (pintype "power_in"))
      (node (ref "U6") (pin "31") (pinfunction "VCCIO_31") (pintype "power_in"))
      (node (ref "U6") (pin "42") (pinfunction "VCCIO_42") (pintype "power_in"))
      (node (ref "U6") (pin "50") (pinfunction "VREGIN_50") (pintype "power_in"))
      (node (ref "U6") (pin "56") (pinfunction "VCCIO_56") (pintype "power_in"))
      (node (ref "U8") (pin "3") (pinfunction "D_3") (pintype "input"))
      (node (ref "U8") (pin "5") (pinfunction "VCC_5") (pintype "power_in"))
    )
    (net (code "63") (name "GND-A") (class "Default")
      (node (ref "C111") (pin "2") (pinfunction "2_2") (pintype "passive"))
      (node (ref "C116") (pin "2") (pinfunction "2_2") (pintype "passive"))
      (node (ref "C117") (pin "2") (pinfunction "2_2") (pintype "passive"))
      (node (ref "C12") (pin "2") (pinfunction "2_2") (pintype "passive"))
      (node (ref "C173") (pin "2") (pinfunction "2_2") (pintype "passive"))
      (node (ref "C177") (pin "2") (pinfunction "2_2") (pintype "passive"))
      (node (ref "C179") (pin "-") (pinfunction "-_-") (pintype "passive"))
      (node (ref "C18") (pin "2") (pinfunction "2_2") (pintype "passive"))
      (node (ref "C180") (pin "-") (pinfunction "-_-") (pintype "passive"))
      (node (ref "C182") (pin "2") (pinfunction "2_2") (pintype "passive"))
      (node (ref "C19") (pin "2") (pinfunction "2_2") (pintype "passive"))
      (node (ref "C192") (pin "1") (pinfunction "1_1") (pintype "passive"))
      (node (ref "C196") (pin "2") (pinfunction "2_2") (pintype "passive"))
      (node (ref "C199") (pin "1") (pinfunction "1_1") (pintype "passive"))
      (node (ref "C223") (pin "2") (pinfunction "2_2") (pintype "passive"))
      (node (ref "C224") (pin "2") (pinfunction "2_2") (pintype "passive"))
      (node (ref "CF1") (pin "2@1") (pinfunction "2_2@1") (pintype "passive"))
      (node (ref "D9") (pin "A") (pinfunction "A_A") (pintype "passive"))
      (node (ref "FB2") (pin "2") (pinfunction "2_2") (pintype "passive"))
      (node (ref "J10") (pin "S") (pinfunction "S_S") (pintype "passive"))
      (node (ref "J3") (pin "S") (pinfunction "S_S") (pintype "passive"))
      (node (ref "J3") (pin "SN") (pinfunction "SN_SN") (pintype "passive"))
      (node (ref "J3") (pin "TN") (pinfunction "TN_TN") (pintype "passive"))
      (node (ref "J4") (pin "1") (pinfunction "S_1") (pintype "passive"))
      (node (ref "J9") (pin "S") (pinfunction "S_S") (pintype "passive"))
      (node (ref "LSP3") (pin "MP") (pinfunction "MP_MP") (pintype "passive"))
      (node (ref "Q1") (pin "E") (pinfunction "E_E") (pintype "passive"))
      (node (ref "Q5") (pin "2") (pinfunction "S_2") (pintype "bidirectional"))
      (node (ref "R111") (pin "1") (pinfunction "1_1") (pintype "passive"))
      (node (ref "R147") (pin "1") (pinfunction "1_1") (pintype "passive"))
      (node (ref "R156") (pin "1") (pinfunction "1_1") (pintype "passive"))
      (node (ref "R167") (pin "1") (pinfunction "1_1") (pintype "passive"))
      (node (ref "R170") (pin "1") (pinfunction "1_1") (pintype "passive"))
      (node (ref "R182") (pin "1") (pinfunction "1_1") (pintype "passive"))
      (node (ref "R183") (pin "1") (pinfunction "1_1") (pintype "passive"))
      (node (ref "R193") (pin "1") (pinfunction "1_1") (pintype "passive"))
      (node (ref "R194") (pin "1") (pinfunction "1_1") (pintype "passive"))
      (node (ref "R197") (pin "1") (pinfunction "1_1") (pintype "passive"))
      (node (ref "U17") (pin "17") (pinfunction "AVSS_17") (pintype "power_in"))
      (node (ref "U17") (pin "33") (pinfunction "EP_33") (pintype "power_in"))
      (node (ref "U19") (pin "4") (pinfunction "V-_4") (pintype "power_in"))
      (node (ref "U20") (pin "4") (pinfunction "V-_4") (pintype "power_in"))
      (node (ref "U21") (pin "4") (pinfunction "V-_4") (pintype "power_in"))
      (node (ref "U22") (pin "4") (pinfunction "V-_4") (pintype "power_in"))
      (node (ref "U23") (pin "4") (pinfunction "V-_4") (pintype "power_in"))
    )
    (net (code "64") (name "GPAIN0") (class "Default")
      (node (ref "J7") (pin "17") (pinfunction "17_17") (pintype "passive"))
      (node (ref "U4") (pin "A8") (pinfunction "GPAIN0_A8") (pintype "bidirectional"))
    )
    (net (code "65") (name "GPAIN1") (class "Default")
      (node (ref "J7") (pin "15") (pinfunction "15_15") (pintype "passive"))
      (node (ref "U4") (pin "B8") (pinfunction "GPAIN1_B8") (pintype "bidirectional"))
    )
    (net (code "66") (name "GPAIN2") (class "Default")
      (node (ref "J7") (pin "9") (pinfunction "9_9") (pintype "passive"))
      (node (ref "U4") (pin "A9") (pinfunction "GPAIN2_A9") (pintype "bidirectional"))
    )
    (net (code "67") (name "GPAIN2_2") (class "Default")
      (node (ref "J7") (pin "7") (pinfunction "7_7") (pintype "passive"))
      (node (ref "U5") (pin "A9") (pinfunction "GPAIN2_A9") (pintype "bidirectional"))
    )
    (net (code "68") (name "GPAIN2_3") (class "Default")
      (node (ref "J7") (pin "11") (pinfunction "11_11") (pintype "passive"))
      (node (ref "U5") (pin "A10") (pinfunction "GPAIN3_A10") (pintype "bidirectional"))
    )
    (net (code "69") (name "GPAIN3") (class "Default")
      (node (ref "J7") (pin "13") (pinfunction "13_13") (pintype "passive"))
      (node (ref "U4") (pin "A10") (pinfunction "GPAIN3_A10") (pintype "bidirectional"))
    )
    (net (code "70") (name "GPIO10") (class "Default")
      (node (ref "R84") (pin "1") (pinfunction "1_1") (pintype "passive"))
      (node (ref "U4") (pin "P3") (pinfunction "LCD_D[6]/GP[16]_P3") (pintype "tri_state"))
    )
    (net (code "71") (name "GPIO13") (class "Default")
      (node (ref "TP14") (pin "TP") (pinfunction "TP_TP") (pintype "input"))
      (node (ref "U4") (pin "N5") (pinfunction "LCD_D[3]/GP[13]_N5") (pintype "tri_state"))
    )
    (net (code "72") (name "GPIO14") (class "Default")
      (node (ref "TP15") (pin "TP") (pinfunction "TP_TP") (pintype "input"))
      (node (ref "U4") (pin "P2") (pinfunction "LCD_D[4]/GP[14]_P2") (pintype "tri_state"))
    )
    (net (code "73") (name "GPIO15") (class "Default")
      (node (ref "TP16") (pin "TP") (pinfunction "TP_TP") (pintype "input"))
      (node (ref "U4") (pin "N7") (pinfunction "LCD_D[5]/GP[15]_N7") (pintype "tri_state"))
    )
    (net (code "74") (name "HP_LOUT") (class "Default")
      (node (ref "C14") (pin "+") (pinfunction "+_+") (pintype "passive"))
      (node (ref "U17") (pin "25") (pinfunction "HPL_25") (pintype "output"))
    )
    (net (code "75") (name "HP_ROUT") (class "Default")
      (node (ref "C13") (pin "+") (pinfunction "+_+") (pintype "passive"))
      (node (ref "U17") (pin "27") (pinfunction "HPR_27") (pintype "output"))
    )
    (net (code "76") (name "I2C2_SCL") (class "Default")
      (node (ref "R14-2") (pin "1") (pinfunction "1_1") (pintype "passive"))
      (node (ref "U10X") (pin "6") (pinfunction "SCL_6") (pintype "input"))
      (node (ref "U5") (pin "C4") (pinfunction "I2C_SCL_C4") (pintype "bidirectional"))
    )
    (net (code "77") (name "I2C2_SDA") (class "Default")
      (node (ref "R13-2") (pin "1") (pinfunction "1_1") (pintype "passive"))
      (node (ref "U10X") (pin "5") (pinfunction "SDA_5") (pintype "bidirectional"))
      (node (ref "U5") (pin "A4") (pinfunction "I2C_SDA_A4") (pintype "bidirectional"))
    )
    (net (code "78") (name "I2C_SCL") (class "Default")
      (node (ref "R14") (pin "1") (pinfunction "1_1") (pintype "passive"))
      (node (ref "U18") (pin "7") (pinfunction "A6_7") (pintype "bidirectional"))
      (node (ref "U4") (pin "C4") (pinfunction "I2C_SCL_C4") (pintype "bidirectional"))
    )
    (net (code "79") (name "I2C_SCL_AIC") (class "Default")
      (node (ref "R134") (pin "1") (pinfunction "1_1") (pintype "passive"))
      (node (ref "U17") (pin "9") (pinfunction "SCL/SSZ_9") (pintype "input"))
      (node (ref "U18") (pin "13") (pinfunction "B6_13") (pintype "bidirectional"))
    )
    (net (code "80") (name "I2C_SDA") (class "Default")
      (node (ref "R13") (pin "1") (pinfunction "1_1") (pintype "passive"))
      (node (ref "U18") (pin "8") (pinfunction "A7_8") (pintype "bidirectional"))
      (node (ref "U4") (pin "A4") (pinfunction "I2C_SDA_A4") (pintype "bidirectional"))
    )
    (net (code "81") (name "I2C_SDA_AIC") (class "Default")
      (node (ref "R135") (pin "1") (pinfunction "1_1") (pintype "passive"))
      (node (ref "U17") (pin "10") (pinfunction "SDA/MOSI_10") (pintype "input"))
      (node (ref "U18") (pin "12") (pinfunction "B7_12") (pintype "bidirectional"))
    )
    (net (code "82") (name "I2S2_2_CLK") (class "Default")
      (node (ref "TP28X") (pin "TP") (pinfunction "TP_TP") (pintype "input"))
      (node (ref "U5") (pin "P5") (pinfunction "LCD_D[8]/I2S2_CLK/GP[18]/SPI_CLK_P5") (pintype "bidirectional"))
    )
    (net (code "83") (name "I2S2_2_DX") (class "Default")
      (node (ref "TP31X") (pin "TP") (pinfunction "TP_TP") (pintype "input"))
      (node (ref "U5") (pin "P11") (pinfunction "LCD_D[11]/I2S2_DX/GP[27]/SPI_TX_P11") (pintype "bidirectional"))
    )
    (net (code "84") (name "I2S2_2_FS") (class "Default")
      (node (ref "TP29X") (pin "TP") (pinfunction "TP_TP") (pintype "input"))
      (node (ref "U5") (pin "N10") (pinfunction "LCD_D[9]/I2S2_FS/GP[19]/SPI_CS0_N10") (pintype "bidirectional"))
    )
    (net (code "85") (name "I2S2_2_RX") (class "Default")
      (node (ref "TP30X") (pin "TP") (pinfunction "TP_TP") (pintype "input"))
      (node (ref "U5") (pin "P9") (pinfunction "LCD_D[10]/I2S2_RX/GP[20]/SPI_RX_P9") (pintype "bidirectional"))
    )
    (net (code "86") (name "I2S2_CLK") (class "Default")
      (node (ref "U18") (pin "3") (pinfunction "A2_3") (pintype "bidirectional"))
      (node (ref "U4") (pin "P5") (pinfunction "LCD_D[8]/I2S2_CLK/GP[18]/SPI_CLK_P5") (pintype "bidirectional"))
    )
    (net (code "87") (name "I2S2_DX") (class "Default")
      (node (ref "U18") (pin "5") (pinfunction "A4_5") (pintype "bidirectional"))
      (node (ref "U4") (pin "P11") (pinfunction "LCD_D[11]/I2S2_DX/GP[27]/SPI_TX_P11") (pintype "bidirectional"))
    )
    (net (code "88") (name "I2S2_FS") (class "Default")
      (node (ref "U18") (pin "4") (pinfunction "A3_4") (pintype "bidirectional"))
      (node (ref "U4") (pin "N10") (pinfunction "LCD_D[9]/I2S2_FS/GP[19]/SPI_CS0_N10") (pintype "bidirectional"))
    )
    (net (code "89") (name "I2S2_RX") (class "Default")
      (node (ref "U18") (pin "6") (pinfunction "A5_6") (pintype "bidirectional"))
      (node (ref "U4") (pin "P9") (pinfunction "LCD_D[10]/I2S2_RX/GP[20]/SPI_RX_P9") (pintype "bidirectional"))
    )
    (net (code "90") (name "INT1_0_N") (class "Default")
      (node (ref "R105X") (pin "1") (pinfunction "1_1") (pintype "passive"))
      (node (ref "R37") (pin "1") (pinfunction "1_1") (pintype "passive"))
      (node (ref "U4") (pin "C2") (pinfunction "INT0_C2") (pintype "input"))
    )
    (net (code "91") (name "INT1_1_N") (class "Default")
      (node (ref "R41") (pin "1") (pinfunction "1_1") (pintype "passive"))
      (node (ref "R84") (pin "2") (pinfunction "2_2") (pintype "passive"))
      (node (ref "U4") (pin "B1") (pinfunction "INT1_B1") (pintype "input"))
    )
    (net (code "92") (name "INT2_0_N") (class "Default")
      (node (ref "R41-2") (pin "1") (pinfunction "1_1") (pintype "passive"))
      (node (ref "R67") (pin "1") (pinfunction "1_1") (pintype "passive"))
      (node (ref "U5") (pin "C2") (pinfunction "INT0_C2") (pintype "input"))
    )
    (net (code "93") (name "INT2_1_N") (class "Default")
      (node (ref "R37-2") (pin "1") (pinfunction "1_1") (pintype "passive"))
      (node (ref "R83X") (pin "2") (pinfunction "2_2") (pintype "passive"))
      (node (ref "U5") (pin "B1") (pinfunction "INT1_B1") (pintype "input"))
    )
    (net (code "94") (name "LCD_A0") (class "Default")
      (node (ref "J5") (pin "13") (pinfunction "13_13") (pintype "passive"))
      (node (ref "U5") (pin "J2") (pinfunction "LCD_D[2]/GP[12]_J2") (pintype "tri_state"))
    )
    (net (code "95") (name "LED1") (class "Default")
      (node (ref "J7") (pin "1") (pinfunction "1_1") (pintype "passive"))
      (node (ref "U5") (pin "M14") (pinfunction "SD1_CLK/I2S1_CLK/GP[6]_M14") (pintype "bidirectional"))
    )
    (net (code "96") (name "LED2") (class "Default")
      (node (ref "J7") (pin "3") (pinfunction "3_3") (pintype "passive"))
      (node (ref "U5") (pin "L11") (pinfunction "SD1_CMD/I2S1_FS/GP[7]_L11") (pintype "bidirectional"))
    )
    (net (code "97") (name "LED3") (class "Default")
      (node (ref "J7") (pin "4") (pinfunction "4_4") (pintype "passive"))
      (node (ref "U5") (pin "M13") (pinfunction "SD1_D0/2S1_DX/GP[8]_M13") (pintype "bidirectional"))
    )
    (net (code "98") (name "LED4") (class "Default")
      (node (ref "J7") (pin "5") (pinfunction "5_5") (pintype "passive"))
      (node (ref "U5") (pin "P10") (pinfunction "SD1_D1/I2S1_RX/GP[9]_P10") (pintype "bidirectional"))
    )
    (net (code "99") (name "LED5") (class "Default")
      (node (ref "J7") (pin "6") (pinfunction "6_6") (pintype "passive"))
      (node (ref "U5") (pin "L12") (pinfunction "SD1_D2/GP[10]_L12") (pintype "bidirectional"))
    )
    (net (code "100") (name "LINEIN") (class "Default")
      (node (ref "C170") (pin "1") (pinfunction "1_1") (pintype "passive"))
      (node (ref "FB12") (pin "2") (pinfunction "2_2") (pintype "passive"))
      (node (ref "R169") (pin "1") (pinfunction "1_1") (pintype "passive"))
    )
    (net (code "101") (name "LINEOUT_L") (class "Default")
      (node (ref "C191") (pin "1") (pinfunction "1_1") (pintype "passive"))
      (node (ref "U17") (pin "22") (pinfunction "LOL_22") (pintype "output"))
    )
    (net (code "102") (name "LINEOUT_R") (class "Default")
      (node (ref "C198") (pin "1") (pinfunction "1_1") (pintype "passive"))
      (node (ref "U17") (pin "23") (pinfunction "LOR_23") (pintype "output"))
    )
    (net (code "103") (name "MCLK_12MHZ") (class "Default")
      (node (ref "R228X") (pin "2") (pinfunction "2_2") (pintype "passive"))
      (node (ref "U18") (pin "9") (pinfunction "A8_9") (pintype "bidirectional"))
    )
    (net (code "104") (name "MUTE") (class "Default")
      (node (ref "R186") (pin "1") (pinfunction "1_1") (pintype "passive"))
      (node (ref "U5") (pin "P7") (pinfunction "SD0_D3/GP[5]_P7") (pintype "bidirectional"))
    )
    (net (code "105") (name "NOISE_SUP") (class "Default")
      (node (ref "R213") (pin "2") (pinfunction "2_2") (pintype "passive"))
      (node (ref "R216") (pin "2") (pinfunction "2_2") (pintype "passive"))
      (node (ref "U5") (pin "B8") (pinfunction "GPAIN1_B8") (pintype "bidirectional"))
    )
    (net (code "106") (name "Net-(C21X-Pad1)") (class "Default")
      (node (ref "C21X") (pin "1") (pinfunction "1_1") (pintype "passive"))
      (node (ref "L6X") (pin "1") (pinfunction "1_1") (pintype "passive"))
      (node (ref "R118X") (pin "1") (pinfunction "1_1") (pintype "passive"))
      (node (ref "R11X") (pin "2") (pinfunction "2_2") (pintype "passive"))
      (node (ref "TP4X") (pin "TP") (pinfunction "TP_TP") (pintype "input"))
    )
    (net (code "107") (name "Net-(C170-Pad2)") (class "Default")
      (node (ref "C170") (pin "2") (pinfunction "2_2") (pintype "passive"))
      (node (ref "R144") (pin "1") (pinfunction "1_1") (pintype "passive"))
    )
    (net (code "108") (name "Net-(C172-Pad1)") (class "Default")
      (node (ref "C172") (pin "1") (pinfunction "1_1") (pintype "passive"))
      (node (ref "R148") (pin "2") (pinfunction "2_2") (pintype "passive"))
    )
    (net (code "109") (name "Net-(C173-Pad1)") (class "Default")
      (node (ref "C173") (pin "1") (pinfunction "1_1") (pintype "passive"))
      (node (ref "R150") (pin "1") (pinfunction "1_1") (pintype "passive"))
    )
    (net (code "110") (name "Net-(C176-Pad1)") (class "Default")
      (node (ref "C176") (pin "1") (pinfunction "1_1") (pintype "passive"))
      (node (ref "R154") (pin "2") (pinfunction "2_2") (pintype "passive"))
      (node (ref "R155") (pin "1") (pinfunction "1_1") (pintype "passive"))
    )
    (net (code "111") (name "Net-(C176-Pad2)") (class "Default")
      (node (ref "C176") (pin "2") (pinfunction "2_2") (pintype "passive"))
      (node (ref "Q1") (pin "C") (pinfunction "C_C") (pintype "passive"))
      (node (ref "R156") (pin "2") (pinfunction "2_2") (pintype "passive"))
    )
    (net (code "112") (name "Net-(C182-Pad1)") (class "Default")
      (node (ref "C182") (pin "1") (pinfunction "1_1") (pintype "passive"))
      (node (ref "R165") (pin "1") (pinfunction "1_1") (pintype "passive"))
    )
    (net (code "113") (name "Net-(C183-Pad2)") (class "Default")
      (node (ref "C183") (pin "2") (pinfunction "2_2") (pintype "passive"))
      (node (ref "R166") (pin "1") (pinfunction "1_1") (pintype "passive"))
    )
    (net (code "114") (name "Net-(C184-Pad1)") (class "Default")
      (node (ref "C184") (pin "1") (pinfunction "1_1") (pintype "passive"))
      (node (ref "R166") (pin "2") (pinfunction "2_2") (pintype "passive"))
      (node (ref "R167") (pin "2") (pinfunction "2_2") (pintype "passive"))
    )
    (net (code "115") (name "Net-(C186-Pad1)") (class "Default")
      (node (ref "C186") (pin "1") (pinfunction "1_1") (pintype "passive"))
      (node (ref "R169") (pin "2") (pinfunction "2_2") (pintype "passive"))
    )
    (net (code "116") (name "Net-(C187-Pad2)") (class "Default")
      (node (ref "C187") (pin "2") (pinfunction "2_2") (pintype "passive"))
      (node (ref "R174") (pin "1") (pinfunction "1_1") (pintype "passive"))
    )
    (net (code "117") (name "Net-(C191-Pad2)") (class "Default")
      (node (ref "C191") (pin "2") (pinfunction "2_2") (pintype "passive"))
      (node (ref "R180") (pin "1") (pinfunction "1_1") (pintype "passive"))
    )
    (net (code "118") (name "Net-(C192-Pad2)") (class "Default")
      (node (ref "C192") (pin "2") (pinfunction "2_2") (pintype "passive"))
      (node (ref "R176") (pin "1") (pinfunction "1_1") (pintype "passive"))
      (node (ref "R178") (pin "1") (pinfunction "1_1") (pintype "passive"))
      (node (ref "R180") (pin "2") (pinfunction "2_2") (pintype "passive"))
    )
    (net (code "119") (name "Net-(C193-Pad1)") (class "Default")
      (node (ref "C193") (pin "1") (pinfunction "1_1") (pintype "passive"))
      (node (ref "R181") (pin "2") (pinfunction "2_2") (pintype "passive"))
    )
    (net (code "120") (name "Net-(C194-Pad2)") (class "Default")
      (node (ref "C194") (pin "2") (pinfunction "2_2") (pintype "passive"))
      (node (ref "R182") (pin "2") (pinfunction "2_2") (pintype "passive"))
    )
    (net (code "121") (name "Net-(C195-Pad2)") (class "Default")
      (node (ref "C195") (pin "2") (pinfunction "2_2") (pintype "passive"))
      (node (ref "R183") (pin "2") (pinfunction "2_2") (pintype "passive"))
      (node (ref "R184") (pin "1") (pinfunction "1_1") (pintype "passive"))
    )
    (net (code "122") (name "Net-(C198-Pad2)") (class "Default")
      (node (ref "C198") (pin "2") (pinfunction "2_2") (pintype "passive"))
      (node (ref "R190") (pin "1") (pinfunction "1_1") (pintype "passive"))
    )
    (net (code "123") (name "Net-(C199-Pad2)") (class "Default")
      (node (ref "C199") (pin "2") (pinfunction "2_2") (pintype "passive"))
      (node (ref "R187") (pin "1") (pinfunction "1_1") (pintype "passive"))
      (node (ref "R188") (pin "1") (pinfunction "1_1") (pintype "passive"))
      (node (ref "R190") (pin "2") (pinfunction "2_2") (pintype "passive"))
    )
    (net (code "124") (name "Net-(C201-Pad1)") (class "Default")
      (node (ref "C201") (pin "1") (pinfunction "1_1") (pintype "passive"))
      (node (ref "R192") (pin "2") (pinfunction "2_2") (pintype "passive"))
    )
    (net (code "125") (name "Net-(C202-Pad2)") (class "Default")
      (node (ref "C202") (pin "2") (pinfunction "2_2") (pintype "passive"))
      (node (ref "R193") (pin "2") (pinfunction "2_2") (pintype "passive"))
    )
    (net (code "126") (name "Net-(C203-Pad2)") (class "Default")
      (node (ref "C203") (pin "2") (pinfunction "2_2") (pintype "passive"))
      (node (ref "R194") (pin "2") (pinfunction "2_2") (pintype "passive"))
      (node (ref "R195") (pin "1") (pinfunction "1_1") (pintype "passive"))
    )
    (net (code "127") (name "Net-(C207-Pad2)") (class "Default")
      (node (ref "C207") (pin "2") (pinfunction "2_2") (pintype "passive"))
      (node (ref "R210") (pin "1") (pinfunction "1_1") (pintype "passive"))
    )
    (net (code "128") (name "Net-(C210-Pad1)") (class "Default")
      (node (ref "C210") (pin "1") (pinfunction "1_1") (pintype "passive"))
      (node (ref "C211") (pin "2") (pinfunction "2_2") (pintype "passive"))
      (node (ref "R206") (pin "1") (pinfunction "1_1") (pintype "passive"))
      (node (ref "R207") (pin "1") (pinfunction "1_1") (pintype "passive"))
      (node (ref "R209") (pin "2") (pinfunction "2_2") (pintype "passive"))
    )
    (net (code "129") (name "Net-(C211-Pad1)") (class "Default")
      (node (ref "C211") (pin "1") (pinfunction "1_1") (pintype "passive"))
      (node (ref "R205") (pin "1") (pinfunction "1_1") (pintype "passive"))
    )
    (net (code "130") (name "Net-(D3X-PadC)") (class "Default")
      (node (ref "D3X") (pin "C") (pinfunction "C_C") (pintype "passive"))
      (node (ref "R76X") (pin "2") (pinfunction "2_2") (pintype "passive"))
    )
    (net (code "131") (name "Net-(D6-C)") (class "Default")
      (node (ref "C181") (pin "2") (pinfunction "2_2") (pintype "passive"))
      (node (ref "D6") (pin "3") (pinfunction "C_3") (pintype "passive"))
      (node (ref "D8") (pin "1") (pinfunction "A1_1") (pintype "passive"))
      (node (ref "IC2") (pin "11") (pinfunction "A_11") (pintype "tri_state"))
    )
    (net (code "132") (name "Net-(D7-A1)") (class "Default")
      (node (ref "C206") (pin "1") (pinfunction "1_1") (pintype "passive"))
      (node (ref "D7") (pin "1") (pinfunction "A1_1") (pintype "passive"))
      (node (ref "D7") (pin "2") (pinfunction "C2_2") (pintype "passive"))
      (node (ref "R205") (pin "2") (pinfunction "2_2") (pintype "passive"))
      (node (ref "R208") (pin "1") (pinfunction "1_1") (pintype "passive"))
      (node (ref "U24") (pin "2") (pinfunction "-IN1_2") (pintype "input"))
    )
    (net (code "133") (name "Net-(D7-C1A2)") (class "Default")
      (node (ref "C205") (pin "1") (pinfunction "1_1") (pintype "passive"))
      (node (ref "D7") (pin "3") (pinfunction "C1A2_3") (pintype "passive"))
      (node (ref "R206") (pin "2") (pinfunction "2_2") (pintype "passive"))
      (node (ref "R210") (pin "2") (pinfunction "2_2") (pintype "passive"))
      (node (ref "U24") (pin "3") (pinfunction "+IN1_3") (pintype "input"))
    )
    (net (code "134") (name "Net-(DS1-PadC)") (class "Default")
      (node (ref "DS1") (pin "C") (pinfunction "C_C") (pintype "passive"))
      (node (ref "R12") (pin "2") (pinfunction "2_2") (pintype "passive"))
    )
    (net (code "135") (name "Net-(DS2-PadC)") (class "Default")
      (node (ref "DS2") (pin "C") (pinfunction "C_C") (pintype "passive"))
      (node (ref "R17") (pin "2") (pinfunction "2_2") (pintype "passive"))
    )
    (net (code "136") (name "Net-(FB12-Pad1)") (class "Default")
      (node (ref "FB12") (pin "1") (pinfunction "1_1") (pintype "passive"))
      (node (ref "J3") (pin "T") (pinfunction "T_T") (pintype "passive"))
    )
    (net (code "137") (name "Net-(FB13-Pad1)") (class "Default")
      (node (ref "FB13") (pin "1") (pinfunction "1_1") (pintype "passive"))
      (node (ref "J9") (pin "T") (pinfunction "T_T") (pintype "passive"))
    )
    (net (code "138") (name "Net-(FB13-Pad2)") (class "Default")
      (node (ref "FB13") (pin "2") (pinfunction "2_2") (pintype "passive"))
      (node (ref "R185") (pin "2") (pinfunction "2_2") (pintype "passive"))
    )
    (net (code "139") (name "Net-(FB14-Pad1)") (class "Default")
      (node (ref "FB14") (pin "1") (pinfunction "1_1") (pintype "passive"))
      (node (ref "J10") (pin "T") (pinfunction "T_T") (pintype "passive"))
    )
    (net (code "140") (name "Net-(FB14-Pad2)") (class "Default")
      (node (ref "FB14") (pin "2") (pinfunction "2_2") (pintype "passive"))
      (node (ref "R196") (pin "2") (pinfunction "2_2") (pintype "passive"))
    )
    (net (code "141") (name "Net-(IC2A-A)") (class "Default")
      (node (ref "IC2") (pin "1") (pinfunction "A_1") (pintype "tri_state"))
      (node (ref "IC2") (pin "3") (pinfunction "B_3") (pintype "tri_state"))
      (node (ref "R152") (pin "2") (pinfunction "2_2") (pintype "passive"))
      (node (ref "R153") (pin "1") (pinfunction "1_1") (pintype "passive"))
    )
    (net (code "142") (name "Net-(IC2A-B)") (class "Default")
      (node (ref "C174") (pin "2") (pinfunction "2_2") (pintype "passive"))
      (node (ref "C175") (pin "1") (pinfunction "1_1") (pintype "passive"))
      (node (ref "IC2") (pin "2") (pinfunction "B_2") (pintype "tri_state"))
      (node (ref "R153") (pin "2") (pinfunction "2_2") (pintype "passive"))
      (node (ref "R154") (pin "1") (pinfunction "1_1") (pintype "passive"))
      (node (ref "U19") (pin "7") (pinfunction "OUT_7") (pintype "output"))
    )
    (net (code "143") (name "Net-(IC2A-C)") (class "Default")
      (node (ref "IC2") (pin "13") (pinfunction "C_13") (pintype "input"))
      (node (ref "Q8") (pin "C") (pinfunction "C_C") (pintype "passive"))
      (node (ref "R202") (pin "1") (pinfunction "1_1") (pintype "passive"))
    )
    (net (code "144") (name "Net-(IC2B-A)") (class "Default")
      (node (ref "IC2") (pin "4") (pinfunction "A_4") (pintype "tri_state"))
      (node (ref "R151") (pin "2") (pinfunction "2_2") (pintype "passive"))
      (node (ref "R152") (pin "1") (pinfunction "1_1") (pintype "passive"))
    )
    (net (code "145") (name "Net-(IC2B-C)") (class "Default")
      (node (ref "IC2") (pin "5") (pinfunction "C_5") (pintype "input"))
      (node (ref "Q9") (pin "C") (pinfunction "C_C") (pintype "passive"))
      (node (ref "R203") (pin "1") (pinfunction "1_1") (pintype "passive"))
    )
    (net (code "146") (name "Net-(IC2C-A)") (class "Default")
      (node (ref "C177") (pin "1") (pinfunction "1_1") (pintype "passive"))
      (node (ref "IC2") (pin "8") (pinfunction "A_8") (pintype "tri_state"))
      (node (ref "R157") (pin "1") (pinfunction "1_1") (pintype "passive"))
    )
    (net (code "147") (name "Net-(IC2C-B)") (class "Default")
      (node (ref "IC2") (pin "9") (pinfunction "B_9") (pintype "tri_state"))
      (node (ref "R157") (pin "2") (pinfunction "2_2") (pintype "passive"))
      (node (ref "R161") (pin "1") (pinfunction "1_1") (pintype "passive"))
    )
    (net (code "148") (name "Net-(IC2C-C)") (class "Default")
      (node (ref "IC2") (pin "6") (pinfunction "C_6") (pintype "input"))
      (node (ref "Q2") (pin "B") (pinfunction "B_B") (pintype "passive"))
      (node (ref "Q4") (pin "C") (pinfunction "C_C") (pintype "passive"))
      (node (ref "R201") (pin "1") (pinfunction "1_1") (pintype "passive"))
    )
    (net (code "149") (name "Net-(IC2D-C)") (class "Default")
      (node (ref "IC2") (pin "12") (pinfunction "C_12") (pintype "input"))
      (node (ref "Q2") (pin "C") (pinfunction "C_C") (pintype "passive"))
      (node (ref "R168") (pin "1") (pinfunction "1_1") (pintype "passive"))
    )
    (net (code "150") (name "Net-(J2-P$1)") (class "Default")
      (node (ref "C37") (pin "2") (pinfunction "2_2") (pintype "passive"))
      (node (ref "J2") (pin "5") (pinfunction "P$1_5") (pintype "bidirectional"))
      (node (ref "J2") (pin "6") (pinfunction "P$2_6") (pintype "bidirectional"))
    )
    (net (code "151") (name "Net-(J6-INSERT)") (class "Default")
      (node (ref "J6") (pin "9") (pinfunction "INSERT_9") (pintype "passive"))
      (node (ref "R109") (pin "1") (pinfunction "1_1") (pintype "passive"))
    )
    (net (code "152") (name "Net-(J11-INSERT)") (class "Default")
      (node (ref "J11") (pin "9") (pinfunction "INSERT_9") (pintype "passive"))
      (node (ref "R1") (pin "1") (pinfunction "1_1") (pintype "passive"))
    )
    (net (code "153") (name "Net-(Q3-G)") (class "Default")
      (node (ref "C186") (pin "2") (pinfunction "2_2") (pintype "passive"))
      (node (ref "Q3") (pin "3") (pinfunction "G_3") (pintype "passive"))
      (node (ref "R171") (pin "2") (pinfunction "2_2") (pintype "passive"))
    )
    (net (code "154") (name "Net-(Q3-S)") (class "Default")
      (node (ref "C187") (pin "1") (pinfunction "1_1") (pintype "passive"))
      (node (ref "Q3") (pin "2") (pinfunction "S_2") (pintype "passive"))
      (node (ref "R170") (pin "2") (pinfunction "2_2") (pintype "passive"))
      (node (ref "R173") (pin "1") (pinfunction "1_1") (pintype "passive"))
    )
    (net (code "155") (name "Net-(Q5-D)") (class "Default")
      (node (ref "Q5") (pin "3") (pinfunction "D_3") (pintype "bidirectional"))
      (node (ref "Q6") (pin "3") (pinfunction "D_3") (pintype "bidirectional"))
      (node (ref "Q7") (pin "3") (pinfunction "D_3") (pintype "bidirectional"))
    )
    (net (code "156") (name "Net-(Q5-G)") (class "Default")
      (node (ref "C196") (pin "1") (pinfunction "1_1") (pintype "passive"))
      (node (ref "Q5") (pin "1") (pinfunction "G_1") (pintype "bidirectional"))
      (node (ref "Q6") (pin "1") (pinfunction "G_1") (pintype "bidirectional"))
      (node (ref "Q7") (pin "1") (pinfunction "G_1") (pintype "bidirectional"))
      (node (ref "R186") (pin "2") (pinfunction "2_2") (pintype "passive"))
    )
    (net (code "157") (name "Net-(Q6-S)") (class "Default")
      (node (ref "Q6") (pin "2") (pinfunction "S_2") (pintype "bidirectional"))
      (node (ref "R184") (pin "2") (pinfunction "2_2") (pintype "passive"))
      (node (ref "R185") (pin "1") (pinfunction "1_1") (pintype "passive"))
    )
    (net (code "158") (name "Net-(Q7-S)") (class "Default")
      (node (ref "Q7") (pin "2") (pinfunction "S_2") (pintype "bidirectional"))
      (node (ref "R195") (pin "2") (pinfunction "2_2") (pintype "passive"))
      (node (ref "R196") (pin "1") (pinfunction "1_1") (pintype "passive"))
    )
    (net (code "159") (name "Net-(SW2A-P)") (class "Default")
      (node (ref "CF1") (pin "3") (pinfunction "3_3") (pintype "passive"))
      (node (ref "SW2") (pin "2") (pinfunction "P_2") (pintype "passive"))
    )
    (net (code "160") (name "Net-(U1X-SW)") (class "Default")
      (node (ref "C124X") (pin "2") (pinfunction "2_2") (pintype "passive"))
      (node (ref "L6X") (pin "2") (pinfunction "2_2") (pintype "passive"))
      (node (ref "U1X") (pin "2") (pinfunction "SW_2") (pintype "output"))
    )
    (net (code "161") (name "Net-(U1X-VBST)") (class "Default")
      (node (ref "C124X") (pin "1") (pinfunction "1_1") (pintype "passive"))
      (node (ref "U1X") (pin "6") (pinfunction "VBST_6") (pintype "passive"))
    )
    (net (code "162") (name "Net-(U1X-VFB)") (class "Default")
      (node (ref "R11X") (pin "1") (pinfunction "1_1") (pintype "passive"))
      (node (ref "R15X") (pin "2") (pinfunction "2_2") (pintype "passive"))
      (node (ref "U1X") (pin "4") (pinfunction "VFB_4") (pintype "input"))
    )
    (net (code "163") (name "Net-(U2-DO)") (class "Default")
      (node (ref "R19") (pin "2") (pinfunction "2_2") (pintype "passive"))
      (node (ref "R21") (pin "1") (pinfunction "1_1") (pintype "passive"))
      (node (ref "U2") (pin "4") (pinfunction "DO_4") (pintype "output"))
    )
    (net (code "164") (name "Net-(U4A-BG_CAP)") (class "Default")
      (node (ref "C88") (pin "1") (pinfunction "1_1") (pintype "passive"))
      (node (ref "U4") (pin "C10") (pinfunction "BG_CAP_C10") (pintype "bidirectional"))
    )
    (net (code "165") (name "Net-(U4A-DSP_LDO_EN)") (class "Default")
      (node (ref "R63") (pin "1") (pinfunction "1_1") (pintype "passive"))
      (node (ref "R64") (pin "2") (pinfunction "2_2") (pintype "passive"))
      (node (ref "U4") (pin "C13") (pinfunction "DSP_LDO_EN_C13") (pintype "input"))
    )
    (net (code "166") (name "Net-(U4A-RSV0)") (class "Default")
      (node (ref "R61") (pin "2") (pinfunction "2_2") (pintype "passive"))
      (node (ref "U4") (pin "A12") (pinfunction "RSV0_A12") (pintype "input"))
    )
    (net (code "167") (name "Net-(U4A-RSV3)") (class "Default")
      (node (ref "R60") (pin "2") (pinfunction "2_2") (pintype "passive"))
      (node (ref "U4") (pin "B12") (pinfunction "RSV3_B12") (pintype "input"))
    )
    (net (code "168") (name "Net-(U4A-RSV6)") (class "Default")
      (node (ref "R62") (pin "2") (pinfunction "2_2") (pintype "passive"))
      (node (ref "U4") (pin "B13") (pinfunction "RSV6_B13") (pintype "input"))
    )
    (net (code "169") (name "Net-(U4B-CLKIN)") (class "Default")
      (node (ref "R34") (pin "2") (pinfunction "2_2") (pintype "passive"))
      (node (ref "R38") (pin "2") (pinfunction "2_2") (pintype "passive"))
      (node (ref "U4") (pin "C1") (pinfunction "CLKIN_C1") (pintype "input"))
    )
    (net (code "170") (name "Net-(U4B-CLKOUT)") (class "Default")
      (node (ref "R117") (pin "2") (pinfunction "2_2") (pintype "passive"))
      (node (ref "TP1") (pin "TP") (pinfunction "TP_TP") (pintype "input"))
      (node (ref "U4") (pin "A2") (pinfunction "CLKOUT_A2") (pintype "output"))
    )
    (net (code "171") (name "Net-(U4B-RTC_XI)") (class "Default")
      (node (ref "C91") (pin "2") (pinfunction "2_2") (pintype "passive"))
      (node (ref "U4") (pin "A7") (pinfunction "RTC_XI_A7") (pintype "input"))
      (node (ref "Y1") (pin "P$2") (pinfunction "2_P$2") (pintype "passive"))
    )
    (net (code "172") (name "Net-(U4B-RTC_XO)") (class "Default")
      (node (ref "C90") (pin "2") (pinfunction "2_2") (pintype "passive"))
      (node (ref "U4") (pin "A6") (pinfunction "RTC_XO_A6") (pintype "bidirectional"))
      (node (ref "Y1") (pin "P$1") (pinfunction "1_P$1") (pintype "passive"))
    )
    (net (code "173") (name "Net-(U4B-USB_R1)") (class "Default")
      (node (ref "R29") (pin "2") (pinfunction "2_2") (pintype "passive"))
      (node (ref "U4") (pin "G14") (pinfunction "USB_R1_G14") (pintype "bidirectional"))
    )
    (net (code "174") (name "Net-(U4B-USB_VSSOSC)") (class "Default")
      (node (ref "R54") (pin "2") (pinfunction "2_2") (pintype "passive"))
      (node (ref "U4") (pin "D12") (pinfunction "USB_VSSOSC_D12") (pintype "power_in"))
    )
    (net (code "175") (name "Net-(U4B-USB_VSSREF)") (class "Default")
      (node (ref "R29") (pin "1") (pinfunction "1_1") (pintype "passive"))
      (node (ref "U4") (pin "F12") (pinfunction "USB_VSSREF_F12") (pintype "power_in"))
    )
    (net (code "176") (name "Net-(U5A-BG_CAP)") (class "Default")
      (node (ref "C88-2") (pin "1") (pinfunction "1_1") (pintype "passive"))
      (node (ref "U5") (pin "C10") (pinfunction "BG_CAP_C10") (pintype "bidirectional"))
    )
    (net (code "177") (name "Net-(U5A-DSP_LDO_EN)") (class "Default")
      (node (ref "R63-2") (pin "1") (pinfunction "1_1") (pintype "passive"))
      (node (ref "R64-2") (pin "2") (pinfunction "2_2") (pintype "passive"))
      (node (ref "U5") (pin "C13") (pinfunction "DSP_LDO_EN_C13") (pintype "input"))
    )
    (net (code "178") (name "Net-(U5A-RSV0)") (class "Default")
      (node (ref "R61-2") (pin "2") (pinfunction "2_2") (pintype "passive"))
      (node (ref "U5") (pin "A12") (pinfunction "RSV0_A12") (pintype "input"))
    )
    (net (code "179") (name "Net-(U5A-RSV3)") (class "Default")
      (node (ref "R60-2") (pin "2") (pinfunction "2_2") (pintype "passive"))
      (node (ref "U5") (pin "B12") (pinfunction "RSV3_B12") (pintype "input"))
    )
    (net (code "180") (name "Net-(U5A-RSV6)") (class "Default")
      (node (ref "R62-2") (pin "2") (pinfunction "2_2") (pintype "passive"))
      (node (ref "U5") (pin "B13") (pinfunction "RSV6_B13") (pintype "input"))
    )
    (net (code "181") (name "Net-(U5B-CLKIN)") (class "Default")
      (node (ref "R34-2") (pin "2") (pinfunction "2_2") (pintype "passive"))
      (node (ref "R38-2") (pin "2") (pinfunction "2_2") (pintype "passive"))
      (node (ref "U5") (pin "C1") (pinfunction "CLKIN_C1") (pintype "input"))
    )
    (net (code "182") (name "Net-(U5B-RTC_XI)") (class "Default")
      (node (ref "C91-2") (pin "2") (pinfunction "2_2") (pintype "passive"))
      (node (ref "U5") (pin "A7") (pinfunction "RTC_XI_A7") (pintype "input"))
      (node (ref "Y1-2") (pin "P$2") (pinfunction "2_P$2") (pintype "passive"))
    )
    (net (code "183") (name "Net-(U5B-RTC_XO)") (class "Default")
      (node (ref "C90-2") (pin "2") (pinfunction "2_2") (pintype "passive"))
      (node (ref "U5") (pin "A6") (pinfunction "RTC_XO_A6") (pintype "bidirectional"))
      (node (ref "Y1-2") (pin "P$1") (pinfunction "1_P$1") (pintype "passive"))
    )
    (net (code "184") (name "Net-(U5B-USB_R1)") (class "Default")
      (node (ref "R29-2") (pin "2") (pinfunction "2_2") (pintype "passive"))
      (node (ref "U5") (pin "G14") (pinfunction "USB_R1_G14") (pintype "bidirectional"))
    )
    (net (code "185") (name "Net-(U5B-USB_VSSOSC)") (class "Default")
      (node (ref "R54-2") (pin "2") (pinfunction "2_2") (pintype "passive"))
      (node (ref "U5") (pin "D12") (pinfunction "USB_VSSOSC_D12") (pintype "power_in"))
    )
    (net (code "186") (name "Net-(U5B-USB_VSSREF)") (class "Default")
      (node (ref "R29-2") (pin "1") (pinfunction "1_1") (pintype "passive"))
      (node (ref "U5") (pin "F12") (pinfunction "USB_VSSREF_F12") (pintype "power_in"))
    )
    (net (code "187") (name "Net-(U6-BDBUS0)") (class "Default")
      (node (ref "R35") (pin "1") (pinfunction "1_1") (pintype "passive"))
      (node (ref "U6") (pin "38") (pinfunction "BDBUS0_38") (pintype "output"))
    )
    (net (code "188") (name "Net-(U6-BDBUS1)") (class "Default")
      (node (ref "R32") (pin "1") (pinfunction "1_1") (pintype "passive"))
      (node (ref "U6") (pin "39") (pinfunction "BDBUS1_39") (pintype "input"))
    )
    (net (code "189") (name "Net-(U6-BDBUS2)") (class "Default")
      (node (ref "R30") (pin "1") (pinfunction "1_1") (pintype "passive"))
      (node (ref "U6") (pin "40") (pinfunction "BDBUS2_40") (pintype "output"))
    )
    (net (code "190") (name "Net-(U6-BDBUS3)") (class "Default")
      (node (ref "R27") (pin "1") (pinfunction "1_1") (pintype "passive"))
      (node (ref "U6") (pin "41") (pinfunction "BDBUS3_41") (pintype "input"))
    )
    (net (code "191") (name "Net-(U6-PWEN#)") (class "Default")
      (node (ref "R12") (pin "1") (pinfunction "1_1") (pintype "passive"))
      (node (ref "U6") (pin "60") (pinfunction "PWEN#_60") (pintype "output"))
    )
    (net (code "192") (name "Net-(U6-REF)") (class "Default")
      (node (ref "R28") (pin "2") (pinfunction "2_2") (pintype "passive"))
      (node (ref "U6") (pin "6") (pinfunction "REF_6") (pintype "passive"))
    )
    (net (code "193") (name "Net-(U6-RESET#)") (class "Default")
      (node (ref "R36") (pin "2") (pinfunction "2_2") (pintype "passive"))
      (node (ref "U6") (pin "14") (pinfunction "RESET#_14") (pintype "input"))
    )
    (net (code "194") (name "Net-(U6-XTIN)") (class "Default")
      (node (ref "R23") (pin "2") (pinfunction "2_2") (pintype "passive"))
      (node (ref "U6") (pin "2") (pinfunction "XTIN_2") (pintype "input"))
    )
    (net (code "195") (name "Net-(U8-CLK)") (class "Default")
      (node (ref "R53") (pin "2") (pinfunction "2_2") (pintype "passive"))
      (node (ref "U8") (pin "1") (pinfunction "CLK_1") (pintype "input"))
    )
    (net (code "196") (name "Net-(U9-2-HOLD)") (class "Default")
      (node (ref "R52-2") (pin "1") (pinfunction "1_1") (pintype "passive"))
      (node (ref "U9-2") (pin "1") (pinfunction "HOLD_1") (pintype "bidirectional"))
    )
    (net (code "197") (name "Net-(U9-2-WP)") (class "Default")
      (node (ref "R52-1") (pin "1") (pinfunction "1_1") (pintype "passive"))
      (node (ref "U9-2") (pin "9") (pinfunction "WP_9") (pintype "bidirectional"))
    )
    (net (code "198") (name "Net-(U9-HOLD)") (class "Default")
      (node (ref "R52") (pin "1") (pinfunction "1_1") (pintype "passive"))
      (node (ref "U9") (pin "1") (pinfunction "HOLD_1") (pintype "bidirectional"))
    )
    (net (code "199") (name "Net-(U9-WP)") (class "Default")
      (node (ref "R16") (pin "1") (pinfunction "1_1") (pintype "passive"))
      (node (ref "U9") (pin "9") (pinfunction "WP_9") (pintype "bidirectional"))
    )
    (net (code "200") (name "Net-(U10X-WP)") (class "Default")
      (node (ref "R143X") (pin "1") (pinfunction "1_1") (pintype "passive"))
      (node (ref "U10X") (pin "7") (pinfunction "WP_7") (pintype "input"))
    )
    (net (code "201") (name "Net-(U11X-NR{slash}FB)") (class "Default")
      (node (ref "C95X") (pin "2") (pinfunction "2_2") (pintype "passive"))
      (node (ref "R125X") (pin "1") (pinfunction "1_1") (pintype "passive"))
      (node (ref "R126X") (pin "2") (pinfunction "2_2") (pintype "passive"))
      (node (ref "U11X") (pin "4") (pinfunction "NR/FB_4") (pintype "passive"))
    )
    (net (code "202") (name "Net-(U12X-SW)") (class "Default")
      (node (ref "C125X") (pin "2") (pinfunction "2_2") (pintype "passive"))
      (node (ref "L7X") (pin "2") (pinfunction "2_2") (pintype "passive"))
      (node (ref "U12X") (pin "2") (pinfunction "SW_2") (pintype "output"))
    )
    (net (code "203") (name "Net-(U12X-VBST)") (class "Default")
      (node (ref "C125X") (pin "1") (pinfunction "1_1") (pintype "passive"))
      (node (ref "U12X") (pin "6") (pinfunction "VBST_6") (pintype "passive"))
    )
    (net (code "204") (name "Net-(U12X-VFB)") (class "Default")
      (node (ref "R65X") (pin "1") (pinfunction "1_1") (pintype "passive"))
      (node (ref "R70X") (pin "2") (pinfunction "2_2") (pintype "passive"))
      (node (ref "U12X") (pin "4") (pinfunction "VFB_4") (pintype "input"))
    )
    (net (code "205") (name "Net-(U13A-X)") (class "Default")
      (node (ref "R175") (pin "1") (pinfunction "1_1") (pintype "passive"))
      (node (ref "R198") (pin "1") (pinfunction "1_1") (pintype "passive"))
      (node (ref "U13") (pin "4") (pinfunction "X_4") (pintype "bidirectional"))
    )
    (net (code "206") (name "Net-(U13A-~{A}{slash}B)") (class "Default")
      (node (ref "Q10") (pin "C") (pinfunction "C_C") (pintype "passive"))
      (node (ref "R204") (pin "1") (pinfunction "1_1") (pintype "passive"))
      (node (ref "U13") (pin "6") (pinfunction "~{A}/B_6") (pintype "input"))
    )
    (net (code "207") (name "Net-(U15X-1G)") (class "Default")
      (node (ref "R222X") (pin "2") (pinfunction "2_2") (pintype "passive"))
      (node (ref "U15X") (pin "2") (pinfunction "1G_2") (pintype "input"))
    )
    (net (code "208") (name "Net-(U15X-Y0)") (class "Default")
      (node (ref "R223X") (pin "1") (pinfunction "1_1") (pintype "passive"))
      (node (ref "U15X") (pin "3") (pinfunction "Y0_3") (pintype "output"))
    )
    (net (code "209") (name "Net-(U15X-Y1)") (class "Default")
      (node (ref "R224X") (pin "1") (pinfunction "1_1") (pintype "passive"))
      (node (ref "U15X") (pin "16") (pinfunction "Y1_16") (pintype "output"))
    )
    (net (code "210") (name "Net-(U15X-Y2)") (class "Default")
      (node (ref "R225X") (pin "1") (pinfunction "1_1") (pintype "passive"))
      (node (ref "U15X") (pin "13") (pinfunction "Y2_13") (pintype "output"))
    )
    (net (code "211") (name "Net-(U15X-Y3)") (class "Default")
      (node (ref "R226X") (pin "1") (pinfunction "1_1") (pintype "passive"))
      (node (ref "U15X") (pin "15") (pinfunction "Y3_15") (pintype "output"))
    )
    (net (code "212") (name "Net-(U15X-Y4)") (class "Default")
      (node (ref "R227X") (pin "1") (pinfunction "1_1") (pintype "passive"))
      (node (ref "U15X") (pin "6") (pinfunction "Y4_6") (pintype "output"))
    )
    (net (code "213") (name "Net-(U15X-Y5)") (class "Default")
      (node (ref "R228X") (pin "1") (pinfunction "1_1") (pintype "passive"))
      (node (ref "U15X") (pin "11") (pinfunction "Y5_11") (pintype "output"))
    )
    (net (code "214") (name "Net-(U15X-Y6)") (class "Default")
      (node (ref "R229X") (pin "1") (pinfunction "1_1") (pintype "passive"))
      (node (ref "U15X") (pin "8") (pinfunction "Y6_8") (pintype "output"))
    )
    (net (code "215") (name "Net-(U15X-Y7)") (class "Default")
      (node (ref "R230X") (pin "1") (pinfunction "1_1") (pintype "passive"))
      (node (ref "U15X") (pin "9") (pinfunction "Y7_9") (pintype "output"))
    )
    (net (code "216") (name "Net-(U17-IN2_L)") (class "Default")
      (node (ref "C17") (pin "2") (pinfunction "2_2") (pintype "passive"))
      (node (ref "U17") (pin "15") (pinfunction "IN2_L_15") (pintype "input"))
    )
    (net (code "217") (name "Net-(U17-IN2_R)") (class "Default")
      (node (ref "C16") (pin "2") (pinfunction "2_2") (pintype "passive"))
      (node (ref "U17") (pin "16") (pinfunction "IN2_R_16") (pintype "input"))
    )
    (net (code "218") (name "Net-(U17-LDO_SELECT)") (class "Default")
      (node (ref "R10") (pin "1") (pinfunction "1_1") (pintype "passive"))
      (node (ref "R9") (pin "2") (pinfunction "2_2") (pintype "passive"))
      (node (ref "U17") (pin "30") (pinfunction "LDO_SELECT_30") (pintype "input"))
    )
    (net (code "219") (name "Net-(U17-MICBIAS)") (class "Default")
      (node (ref "R110") (pin "2") (pinfunction "2_2") (pintype "passive"))
      (node (ref "U17") (pin "19") (pinfunction "MICBIAS_19") (pintype "output"))
    )
    (net (code "220") (name "Net-(U17-REF)") (class "Default")
      (node (ref "C117") (pin "1") (pinfunction "1_1") (pintype "passive"))
      (node (ref "C18") (pin "1") (pinfunction "1_1") (pintype "passive"))
      (node (ref "U17") (pin "18") (pinfunction "REF_18") (pintype "output"))
    )
    (net (code "221") (name "Net-(U18-B1)") (class "Default")
      (node (ref "R8") (pin "2") (pinfunction "2_2") (pintype "passive"))
      (node (ref "U18") (pin "18") (pinfunction "B1_18") (pintype "bidirectional"))
    )
    (net (code "222") (name "Net-(U18-B2)") (class "Default")
      (node (ref "R92") (pin "2") (pinfunction "2_2") (pintype "passive"))
      (node (ref "U18") (pin "17") (pinfunction "B2_17") (pintype "bidirectional"))
    )
    (net (code "223") (name "Net-(U18-B3)") (class "Default")
      (node (ref "R93") (pin "2") (pinfunction "2_2") (pintype "passive"))
      (node (ref "U18") (pin "16") (pinfunction "B3_16") (pintype "bidirectional"))
    )
    (net (code "224") (name "Net-(U18-B4)") (class "Default")
      (node (ref "R94") (pin "2") (pinfunction "2_2") (pintype "passive"))
      (node (ref "U18") (pin "15") (pinfunction "B4_15") (pintype "bidirectional"))
    )
    (net (code "225") (name "Net-(U18-B5)") (class "Default")
      (node (ref "R95") (pin "2") (pinfunction "2_2") (pintype "passive"))
      (node (ref "U18") (pin "14") (pinfunction "B5_14") (pintype "bidirectional"))
    )
    (net (code "226") (name "Net-(U19A-+IN)") (class "Default")
      (node (ref "R145") (pin "2") (pinfunction "2_2") (pintype "passive"))
      (node (ref "U19") (pin "3") (pinfunction "+IN_3") (pintype "input"))
    )
    (net (code "227") (name "Net-(U19A--IN)") (class "Default")
      (node (ref "C171") (pin "1") (pinfunction "1_1") (pintype "passive"))
      (node (ref "R144") (pin "2") (pinfunction "2_2") (pintype "passive"))
      (node (ref "R148") (pin "1") (pinfunction "1_1") (pintype "passive"))
      (node (ref "R149") (pin "1") (pinfunction "1_1") (pintype "passive"))
      (node (ref "U19") (pin "2") (pinfunction "-IN_2") (pintype "input"))
    )
    (net (code "228") (name "Net-(U19A-OUT)") (class "Default")
      (node (ref "C171") (pin "2") (pinfunction "2_2") (pintype "passive"))
      (node (ref "C172") (pin "2") (pinfunction "2_2") (pintype "passive"))
      (node (ref "R149") (pin "2") (pinfunction "2_2") (pintype "passive"))
      (node (ref "U19") (pin "1") (pinfunction "OUT_1") (pintype "output"))
      (node (ref "U19") (pin "5") (pinfunction "+IN_5") (pintype "input"))
    )
    (net (code "229") (name "Net-(U19B--IN)") (class "Default")
      (node (ref "C174") (pin "1") (pinfunction "1_1") (pintype "passive"))
      (node (ref "R150") (pin "2") (pinfunction "2_2") (pintype "passive"))
      (node (ref "R151") (pin "1") (pinfunction "1_1") (pintype "passive"))
      (node (ref "U19") (pin "6") (pinfunction "-IN_6") (pintype "input"))
    )
    (net (code "230") (name "Net-(U20A-+IN)") (class "Default")
      (node (ref "C180") (pin "+") (pinfunction "+_+") (pintype "passive"))
      (node (ref "R146") (pin "1") (pinfunction "1_1") (pintype "passive"))
      (node (ref "R147") (pin "2") (pinfunction "2_2") (pintype "passive"))
      (node (ref "U20") (pin "3") (pinfunction "+IN_3") (pintype "input"))
    )
    (net (code "231") (name "Net-(U20B--IN)") (class "Default")
      (node (ref "R172") (pin "1") (pinfunction "1_1") (pintype "passive"))
      (node (ref "R173") (pin "2") (pinfunction "2_2") (pintype "passive"))
      (node (ref "R174") (pin "2") (pinfunction "2_2") (pintype "passive"))
      (node (ref "U20") (pin "6") (pinfunction "-IN_6") (pintype "input"))
    )
    (net (code "232") (name "Net-(U21A-+IN)") (class "Default")
      (node (ref "C175") (pin "2") (pinfunction "2_2") (pintype "passive"))
      (node (ref "R155") (pin "2") (pinfunction "2_2") (pintype "passive"))
      (node (ref "U21") (pin "3") (pinfunction "+IN_3") (pintype "input"))
    )
    (net (code "233") (name "Net-(U21A--IN)") (class "Default")
      (node (ref "C178") (pin "1") (pinfunction "1_1") (pintype "passive"))
      (node (ref "C181") (pin "1") (pinfunction "1_1") (pintype "passive"))
      (node (ref "R158") (pin "1") (pinfunction "1_1") (pintype "passive"))
      (node (ref "R159") (pin "1") (pinfunction "1_1") (pintype "passive"))
      (node (ref "R160") (pin "1") (pinfunction "1_1") (pintype "passive"))
      (node (ref "R161") (pin "2") (pinfunction "2_2") (pintype "passive"))
      (node (ref "U21") (pin "2") (pinfunction "-IN_2") (pintype "input"))
    )
    (net (code "234") (name "Net-(U21B-+IN)") (class "Default")
      (node (ref "R163") (pin "2") (pinfunction "2_2") (pintype "passive"))
      (node (ref "R165") (pin "2") (pinfunction "2_2") (pintype "passive"))
      (node (ref "U21") (pin "5") (pinfunction "+IN_5") (pintype "input"))
    )
    (net (code "235") (name "Net-(U21B--IN)") (class "Default")
      (node (ref "R162") (pin "2") (pinfunction "2_2") (pintype "passive"))
      (node (ref "R164") (pin "1") (pinfunction "1_1") (pintype "passive"))
      (node (ref "U21") (pin "6") (pinfunction "-IN_6") (pintype "input"))
    )
    (net (code "236") (name "Net-(U22A-+IN)") (class "Default")
      (node (ref "C189") (pin "1") (pinfunction "1_1") (pintype "passive"))
      (node (ref "R178") (pin "2") (pinfunction "2_2") (pintype "passive"))
      (node (ref "U22") (pin "3") (pinfunction "+IN_3") (pintype "input"))
    )
    (net (code "237") (name "Net-(U22A-OUT)") (class "Default")
      (node (ref "C189") (pin "2") (pinfunction "2_2") (pintype "passive"))
      (node (ref "R176") (pin "2") (pinfunction "2_2") (pintype "passive"))
      (node (ref "R179") (pin "1") (pinfunction "1_1") (pintype "passive"))
      (node (ref "U22") (pin "1") (pinfunction "OUT_1") (pintype "output"))
    )
    (net (code "238") (name "Net-(U22B--IN)") (class "Default")
      (node (ref "C190") (pin "1") (pinfunction "1_1") (pintype "passive"))
      (node (ref "R177") (pin "1") (pinfunction "1_1") (pintype "passive"))
      (node (ref "R179") (pin "2") (pinfunction "2_2") (pintype "passive"))
      (node (ref "R181") (pin "1") (pinfunction "1_1") (pintype "passive"))
      (node (ref "U22") (pin "6") (pinfunction "-IN_6") (pintype "input"))
    )
    (net (code "239") (name "Net-(U22B-OUT)") (class "Default")
      (node (ref "C190") (pin "2") (pinfunction "2_2") (pintype "passive"))
      (node (ref "C193") (pin "2") (pinfunction "2_2") (pintype "passive"))
      (node (ref "C194") (pin "1") (pinfunction "1_1") (pintype "passive"))
      (node (ref "C195") (pin "1") (pinfunction "1_1") (pintype "passive"))
      (node (ref "R177") (pin "2") (pinfunction "2_2") (pintype "passive"))
      (node (ref "U22") (pin "7") (pinfunction "OUT_7") (pintype "output"))
    )
    (net (code "240") (name "Net-(U23A-+IN)") (class "Default")
      (node (ref "C197") (pin "1") (pinfunction "1_1") (pintype "passive"))
      (node (ref "R188") (pin "2") (pinfunction "2_2") (pintype "passive"))
      (node (ref "U23") (pin "3") (pinfunction "+IN_3") (pintype "input"))
    )
    (net (code "241") (name "Net-(U23A-OUT)") (class "Default")
      (node (ref "C197") (pin "2") (pinfunction "2_2") (pintype "passive"))
      (node (ref "R187") (pin "2") (pinfunction "2_2") (pintype "passive"))
      (node (ref "R189") (pin "1") (pinfunction "1_1") (pintype "passive"))
      (node (ref "U23") (pin "1") (pinfunction "OUT_1") (pintype "output"))
    )
    (net (code "242") (name "Net-(U23B--IN)") (class "Default")
      (node (ref "C200") (pin "1") (pinfunction "1_1") (pintype "passive"))
      (node (ref "R189") (pin "2") (pinfunction "2_2") (pintype "passive"))
      (node (ref "R191") (pin "1") (pinfunction "1_1") (pintype "passive"))
      (node (ref "R192") (pin "1") (pinfunction "1_1") (pintype "passive"))
      (node (ref "U23") (pin "6") (pinfunction "-IN_6") (pintype "input"))
    )
    (net (code "243") (name "Net-(U23B-OUT)") (class "Default")
      (node (ref "C200") (pin "2") (pinfunction "2_2") (pintype "passive"))
      (node (ref "C201") (pin "2") (pinfunction "2_2") (pintype "passive"))
      (node (ref "C202") (pin "1") (pinfunction "1_1") (pintype "passive"))
      (node (ref "C203") (pin "1") (pinfunction "1_1") (pintype "passive"))
      (node (ref "R191") (pin "2") (pinfunction "2_2") (pintype "passive"))
      (node (ref "U23") (pin "7") (pinfunction "OUT_7") (pintype "output"))
    )
    (net (code "244") (name "Net-(U24A-OUT1)") (class "Default")
      (node (ref "C206") (pin "2") (pinfunction "2_2") (pintype "passive"))
      (node (ref "C208") (pin "1") (pinfunction "1_1") (pintype "passive"))
      (node (ref "R208") (pin "2") (pinfunction "2_2") (pintype "passive"))
      (node (ref "R213") (pin "1") (pinfunction "1_1") (pintype "passive"))
      (node (ref "U24") (pin "1") (pinfunction "OUT1_1") (pintype "output"))
      (node (ref "U24") (pin "6") (pinfunction "-IN2_6") (pintype "input"))
    )
    (net (code "245") (name "Net-(U24B-+IN2)") (class "Default")
      (node (ref "C208") (pin "2") (pinfunction "2_2") (pintype "passive"))
      (node (ref "C212") (pin "1") (pinfunction "1_1") (pintype "passive"))
      (node (ref "R211") (pin "1") (pinfunction "1_1") (pintype "passive"))
      (node (ref "R212") (pin "2") (pinfunction "2_2") (pintype "passive"))
      (node (ref "U24") (pin "5") (pinfunction "+IN2_5") (pintype "input"))
    )
    (net (code "246") (name "Net-(U24B-OUT2)") (class "Default")
      (node (ref "R214") (pin "1") (pinfunction "1_1") (pintype "passive"))
      (node (ref "U24") (pin "7") (pinfunction "OUT2_7") (pintype "output"))
    )
    (net (code "247") (name "OCT1") (class "Default")
      (node (ref "D6") (pin "1") (pinfunction "A_1") (pintype "passive"))
      (node (ref "R160") (pin "2") (pinfunction "2_2") (pintype "passive"))
      (node (ref "R162") (pin "1") (pinfunction "1_1") (pintype "passive"))
    )
    (net (code "248") (name "OCT2") (class "Default")
      (node (ref "D8") (pin "2") (pinfunction "C2_2") (pintype "passive"))
      (node (ref "R158") (pin "2") (pinfunction "2_2") (pintype "passive"))
      (node (ref "R163") (pin "1") (pinfunction "1_1") (pintype "passive"))
    )
    (net (code "249") (name "OCT_OUT") (class "Default")
      (node (ref "J7") (pin "12") (pinfunction "12_12") (pintype "passive"))
      (node (ref "R164") (pin "2") (pinfunction "2_2") (pintype "passive"))
      (node (ref "U21") (pin "7") (pinfunction "OUT_7") (pintype "output"))
    )
    (net (code "250") (name "OD_DRV0") (class "Default")
      (node (ref "Q9") (pin "B") (pinfunction "B_B") (pintype "passive"))
      (node (ref "U5") (pin "M10") (pinfunction "SD0_CMD/I2S0_FS/GP[1]_M10") (pintype "bidirectional"))
    )
    (net (code "251") (name "OD_DRV1") (class "Default")
      (node (ref "Q8") (pin "B") (pinfunction "B_B") (pintype "passive"))
      (node (ref "U5") (pin "J1") (pinfunction "SD0_D0/I2S0_DX/GP[2]_J1") (pintype "bidirectional"))
    )
    (net (code "252") (name "OD_MODE0") (class "Default")
      (node (ref "Q1") (pin "B") (pinfunction "B_B") (pintype "passive"))
      (node (ref "U5") (pin "P6") (pinfunction "SD0_D1/I2S0_RX/GP[3]_P6") (pintype "bidirectional"))
    )
    (net (code "253") (name "OD_MODE1") (class "Default")
      (node (ref "Q4") (pin "B") (pinfunction "B_B") (pintype "passive"))
      (node (ref "U5") (pin "N13") (pinfunction "SD0_D2/GP[4]_N13") (pintype "bidirectional"))
    )
    (net (code "254") (name "PWR_DET") (class "Default")
      (node (ref "R40") (pin "2") (pinfunction "2_2") (pintype "passive"))
      (node (ref "U6") (pin "28") (pinfunction "ACBUS2_28") (pintype "bidirectional"))
      (node (ref "U8") (pin "4") (pinfunction "Q_4") (pintype "output"))
    )
    (net (code "255") (name "PWR_RST") (class "Default")
      (node (ref "R53") (pin "1") (pinfunction "1_1") (pintype "passive"))
      (node (ref "U6") (pin "29") (pinfunction "ACBUS3_29") (pintype "bidirectional"))
    )
    (net (code "256") (name "RTCK") (class "Default")
      (node (ref "R46") (pin "1") (pinfunction "1_1") (pintype "passive"))
      (node (ref "U6") (pin "24") (pinfunction "ADBUS7_24") (pintype "bidirectional"))
    )
    (net (code "257") (name "RTC_CLKOUT") (class "Default")
      (node (ref "TP4") (pin "TP") (pinfunction "TP_TP") (pintype "input"))
      (node (ref "U4") (pin "A3") (pinfunction "RTC_CLKOUT_A3") (pintype "output"))
    )
    (net (code "258") (name "RTC_CLKOUT2") (class "Default")
      (node (ref "TP8X") (pin "TP") (pinfunction "TP_TP") (pintype "input"))
      (node (ref "U5") (pin "A3") (pinfunction "RTC_CLKOUT_A3") (pintype "output"))
    )
    (net (code "259") (name "SD1_CLK") (class "Default")
      (node (ref "J11") (pin "5") (pinfunction "CLK_5") (pintype "input"))
      (node (ref "R6") (pin "1") (pinfunction "1_1") (pintype "passive"))
      (node (ref "U4") (pin "M14") (pinfunction "SD1_CLK/I2S1_CLK/GP[6]_M14") (pintype "bidirectional"))
    )
    (net (code "260") (name "SD1_CMD") (class "Default")
      (node (ref "J11") (pin "3") (pinfunction "CMD_3") (pintype "input"))
      (node (ref "R4") (pin "1") (pinfunction "1_1") (pintype "passive"))
      (node (ref "U4") (pin "L11") (pinfunction "SD1_CMD/I2S1_FS/GP[7]_L11") (pintype "bidirectional"))
    )
    (net (code "261") (name "SD1_DATA0") (class "Default")
      (node (ref "J11") (pin "7") (pinfunction "DAT0_7") (pintype "bidirectional"))
      (node (ref "R7") (pin "1") (pinfunction "1_1") (pintype "passive"))
      (node (ref "U4") (pin "M13") (pinfunction "SD1_D0/2S1_DX/GP[8]_M13") (pintype "bidirectional"))
    )
    (net (code "262") (name "SD1_DATA1") (class "Default")
      (node (ref "J11") (pin "8") (pinfunction "DAT1_8") (pintype "bidirectional"))
      (node (ref "R11") (pin "1") (pinfunction "1_1") (pintype "passive"))
      (node (ref "U4") (pin "P10") (pinfunction "SD1_D1/I2S1_RX/GP[9]_P10") (pintype "bidirectional"))
    )
    (net (code "263") (name "SD1_DATA2") (class "Default")
      (node (ref "J11") (pin "1") (pinfunction "DAT2_1") (pintype "bidirectional"))
      (node (ref "R2") (pin "1") (pinfunction "1_1") (pintype "passive"))
      (node (ref "U4") (pin "L12") (pinfunction "SD1_D2/GP[10]_L12") (pintype "bidirectional"))
    )
    (net (code "264") (name "SD1_DATA3") (class "Default")
      (node (ref "J11") (pin "2") (pinfunction "CD/DAT3_2") (pintype "bidirectional"))
      (node (ref "R3") (pin "1") (pinfunction "1_1") (pintype "passive"))
      (node (ref "U4") (pin "M12") (pinfunction "SD1_D3/GP[11]_M12") (pintype "bidirectional"))
    )
    (net (code "265") (name "SD_CLK") (class "Default")
      (node (ref "J6") (pin "5") (pinfunction "CLK_5") (pintype "input"))
      (node (ref "R101") (pin "1") (pinfunction "1_1") (pintype "passive"))
      (node (ref "U4") (pin "M8") (pinfunction "SD0_CLK/I2S0_CLK/GP[0]_M8") (pintype "bidirectional"))
    )
    (net (code "266") (name "SD_CMD") (class "Default")
      (node (ref "J6") (pin "3") (pinfunction "CMD_3") (pintype "input"))
      (node (ref "R100") (pin "1") (pinfunction "1_1") (pintype "passive"))
      (node (ref "U4") (pin "M10") (pinfunction "SD0_CMD/I2S0_FS/GP[1]_M10") (pintype "bidirectional"))
    )
    (net (code "267") (name "SD_DATA0") (class "Default")
      (node (ref "J6") (pin "7") (pinfunction "DAT0_7") (pintype "bidirectional"))
      (node (ref "R102") (pin "1") (pinfunction "1_1") (pintype "passive"))
      (node (ref "U4") (pin "J1") (pinfunction "SD0_D0/I2S0_DX/GP[2]_J1") (pintype "bidirectional"))
    )
    (net (code "268") (name "SD_DATA1") (class "Default")
      (node (ref "J6") (pin "8") (pinfunction "DAT1_8") (pintype "bidirectional"))
      (node (ref "R103") (pin "1") (pinfunction "1_1") (pintype "passive"))
      (node (ref "U4") (pin "P6") (pinfunction "SD0_D1/I2S0_RX/GP[3]_P6") (pintype "bidirectional"))
    )
    (net (code "269") (name "SD_DATA2") (class "Default")
      (node (ref "J6") (pin "1") (pinfunction "DAT2_1") (pintype "bidirectional"))
      (node (ref "R98") (pin "1") (pinfunction "1_1") (pintype "passive"))
      (node (ref "U4") (pin "N13") (pinfunction "SD0_D2/GP[4]_N13") (pintype "bidirectional"))
    )
    (net (code "270") (name "SD_DATA3") (class "Default")
      (node (ref "J6") (pin "2") (pinfunction "CD/DAT3_2") (pintype "bidirectional"))
      (node (ref "R99") (pin "1") (pinfunction "1_1") (pintype "passive"))
      (node (ref "U4") (pin "P7") (pinfunction "SD0_D3/GP[5]_P7") (pintype "bidirectional"))
    )
    (net (code "271") (name "SPI2_CLK") (class "Default")
      (node (ref "J5") (pin "11") (pinfunction "11_11") (pintype "passive"))
      (node (ref "R72-2") (pin "1") (pinfunction "1_1") (pintype "passive"))
      (node (ref "U5") (pin "L3") (pinfunction "LCD_EN_RDB/SPI_CLK_L3") (pintype "output"))
      (node (ref "U9-2") (pin "16") (pinfunction "CLK_16") (pintype "input"))
    )
    (net (code "272") (name "SPI2_CS0") (class "Default")
      (node (ref "R50-2") (pin "1") (pinfunction "1_1") (pintype "passive"))
      (node (ref "U5") (pin "L1") (pinfunction "LCD_CS0_E0/SPI_CS0_L1") (pintype "bidirectional"))
      (node (ref "U9-2") (pin "7") (pinfunction "CS_7") (pintype "input"))
    )
    (net (code "273") (name "SPI2_CS1") (class "Default")
      (node (ref "J5") (pin "17") (pinfunction "17_17") (pintype "passive"))
      (node (ref "U5") (pin "M2") (pinfunction "LCD_CS1_E1/SPI_CS1_M2") (pintype "bidirectional"))
    )
    (net (code "274") (name "SPI2_CS2") (class "Default")
      (node (ref "TP26X") (pin "TP") (pinfunction "TP_TP") (pintype "input"))
      (node (ref "U5") (pin "N2") (pinfunction "LCD_RW_WRB/SPI_CS2_N2") (pintype "bidirectional"))
    )
    (net (code "275") (name "SPI2_CS3") (class "Default")
      (node (ref "TP27X") (pin "TP") (pinfunction "TP_TP") (pintype "input"))
      (node (ref "U5") (pin "M5") (pinfunction "LCD_RS/SPI_CS3_M5") (pintype "bidirectional"))
    )
    (net (code "276") (name "SPI2_RX") (class "Default")
      (node (ref "R51-2") (pin "1") (pinfunction "1_1") (pintype "passive"))
      (node (ref "U5") (pin "N4") (pinfunction "LCD_D[0]/SPI_RX_N4") (pintype "tri_state"))
      (node (ref "U9-2") (pin "8") (pinfunction "DO_8") (pintype "bidirectional"))
    )
    (net (code "277") (name "SPI2_TX") (class "Default")
      (node (ref "J5") (pin "9") (pinfunction "9_9") (pintype "passive"))
      (node (ref "R73-2") (pin "1") (pinfunction "1_1") (pintype "passive"))
      (node (ref "U5") (pin "K1") (pinfunction "LCD_D[1]/SPI_TX_K1") (pintype "tri_state"))
      (node (ref "U9-2") (pin "15") (pinfunction "DI_15") (pintype "bidirectional"))
    )
    (net (code "278") (name "SPI_CLK") (class "Default")
      (node (ref "R72") (pin "1") (pinfunction "1_1") (pintype "passive"))
      (node (ref "U4") (pin "L3") (pinfunction "LCD_EN_RDB/SPI_CLK_L3") (pintype "output"))
      (node (ref "U9") (pin "16") (pinfunction "CLK_16") (pintype "input"))
    )
    (net (code "279") (name "SPI_CS0") (class "Default")
      (node (ref "R50") (pin "1") (pinfunction "1_1") (pintype "passive"))
      (node (ref "U4") (pin "L1") (pinfunction "LCD_CS0_E0/SPI_CS0_L1") (pintype "bidirectional"))
      (node (ref "U9") (pin "7") (pinfunction "CS_7") (pintype "input"))
    )
    (net (code "280") (name "SPI_CS1") (class "Default")
      (node (ref "TP19") (pin "TP") (pinfunction "TP_TP") (pintype "input"))
      (node (ref "U4") (pin "M2") (pinfunction "LCD_CS1_E1/SPI_CS1_M2") (pintype "bidirectional"))
    )
    (net (code "281") (name "SPI_CS2") (class "Default")
      (node (ref "TP20") (pin "TP") (pinfunction "TP_TP") (pintype "input"))
      (node (ref "U4") (pin "N2") (pinfunction "LCD_RW_WRB/SPI_CS2_N2") (pintype "bidirectional"))
    )
    (net (code "282") (name "SPI_CS3") (class "Default")
      (node (ref "TP21") (pin "TP") (pinfunction "TP_TP") (pintype "input"))
      (node (ref "U4") (pin "M5") (pinfunction "LCD_RS/SPI_CS3_M5") (pintype "bidirectional"))
    )
    (net (code "283") (name "SPI_RX") (class "Default")
      (node (ref "R51") (pin "1") (pinfunction "1_1") (pintype "passive"))
      (node (ref "U4") (pin "N4") (pinfunction "LCD_D[0]/SPI_RX_N4") (pintype "tri_state"))
      (node (ref "U9") (pin "8") (pinfunction "DO_8") (pintype "bidirectional"))
    )
    (net (code "284") (name "SPI_TX") (class "Default")
      (node (ref "R73") (pin "1") (pinfunction "1_1") (pintype "passive"))
      (node (ref "U4") (pin "K1") (pinfunction "LCD_D[1]/SPI_TX_K1") (pintype "tri_state"))
      (node (ref "U9") (pin "15") (pinfunction "DI_15") (pintype "bidirectional"))
    )
    (net (code "285") (name "SRST_N_OUT") (class "Default")
      (node (ref "R45") (pin "1") (pinfunction "1_1") (pintype "passive"))
      (node (ref "U6") (pin "26") (pinfunction "ACBUS0_26") (pintype "bidirectional"))
    )
    (net (code "286") (name "SRTST_N_IN") (class "Default")
      (node (ref "R44") (pin "1") (pinfunction "1_1") (pintype "passive"))
      (node (ref "R45") (pin "2") (pinfunction "2_2") (pintype "passive"))
      (node (ref "U6") (pin "27") (pinfunction "ACBUS1_27") (pintype "bidirectional"))
    )
    (net (code "287") (name "SW_UP") (class "Default")
      (node (ref "JP2") (pin "2") (pinfunction "2_2") (pintype "passive"))
      (node (ref "R4X") (pin "1") (pinfunction "1_1") (pintype "passive"))
      (node (ref "SW1") (pin "1") (pinfunction "O_1") (pintype "passive"))
    )
    (net (code "288") (name "TARGET_PWR_GOOD") (class "Default")
      (node (ref "J5") (pin "15") (pinfunction "15_15") (pintype "passive"))
      (node (ref "R3X") (pin "1") (pinfunction "1_1") (pintype "passive"))
      (node (ref "R40") (pin "1") (pinfunction "1_1") (pintype "passive"))
      (node (ref "R42") (pin "1") (pinfunction "1_1") (pintype "passive"))
      (node (ref "U18") (pin "2") (pinfunction "A1_2") (pintype "bidirectional"))
      (node (ref "U3X") (pin "3") (pinfunction "~{RESET}_3") (pintype "output"))
      (node (ref "U4") (pin "D2") (pinfunction "RESETN_D2") (pintype "input"))
      (node (ref "U5") (pin "D2") (pinfunction "RESETN_D2") (pintype "input"))
      (node (ref "U8") (pin "6") (pinfunction "~{CLR}_6") (pintype "input"))
    )
    (net (code "289") (name "TCK") (class "Default")
      (node (ref "R39") (pin "2") (pinfunction "2_2") (pintype "passive"))
      (node (ref "U4") (pin "N3") (pinfunction "TCK_N3") (pintype "input"))
      (node (ref "U5") (pin "N3") (pinfunction "TCK_N3") (pintype "input"))
    )
    (net (code "290") (name "TCK_R") (class "Default")
      (node (ref "R39") (pin "1") (pinfunction "1_1") (pintype "passive"))
      (node (ref "R46") (pin "2") (pinfunction "2_2") (pintype "passive"))
      (node (ref "U6") (pin "16") (pinfunction "ADBUS0_16") (pintype "bidirectional"))
    )
    (net (code "291") (name "TDI") (class "Default")
      (node (ref "R49") (pin "2") (pinfunction "2_2") (pintype "passive"))
      (node (ref "U4") (pin "K2") (pinfunction "TDI_K2") (pintype "input"))
    )
    (net (code "292") (name "TDI_R") (class "Default")
      (node (ref "R49") (pin "1") (pinfunction "1_1") (pintype "passive"))
      (node (ref "U6") (pin "17") (pinfunction "ADBUS1_17") (pintype "bidirectional"))
    )
    (net (code "293") (name "TDO") (class "Default")
      (node (ref "R48") (pin "2") (pinfunction "2_2") (pintype "passive"))
      (node (ref "R66X") (pin "1") (pinfunction "1_1") (pintype "passive"))
    )
    (net (code "294") (name "TDO1") (class "Default")
      (node (ref "U4") (pin "N1") (pinfunction "TDO_N1") (pintype "output"))
      (node (ref "U5") (pin "K2") (pinfunction "TDI_K2") (pintype "input"))
    )
    (net (code "295") (name "TDO2") (class "Default")
      (node (ref "R66X") (pin "2") (pinfunction "2_2") (pintype "passive"))
      (node (ref "U5") (pin "N1") (pinfunction "TDO_N1") (pintype "output"))
    )
    (net (code "296") (name "TDO_R") (class "Default")
      (node (ref "R48") (pin "1") (pinfunction "1_1") (pintype "passive"))
      (node (ref "U6") (pin "18") (pinfunction "ADBUS2_18") (pintype "bidirectional"))
    )
    (net (code "297") (name "TMS") (class "Default")
      (node (ref "R47") (pin "2") (pinfunction "2_2") (pintype "passive"))
      (node (ref "U4") (pin "N6") (pinfunction "TMS_N6") (pintype "input"))
      (node (ref "U5") (pin "N6") (pinfunction "TMS_N6") (pintype "input"))
    )
    (net (code "298") (name "TMS_R") (class "Default")
      (node (ref "R47") (pin "1") (pinfunction "1_1") (pintype "passive"))
      (node (ref "U6") (pin "19") (pinfunction "ADBUS3_19") (pintype "bidirectional"))
    )
    (net (code "299") (name "TP1_CLK12M") (class "Default")
      (node (ref "R223X") (pin "2") (pinfunction "2_2") (pintype "passive"))
      (node (ref "TP7X") (pin "TP") (pinfunction "TP_TP") (pintype "input"))
    )
    (net (code "300") (name "TP2_CLK12M") (class "Default")
      (node (ref "R224X") (pin "2") (pinfunction "2_2") (pintype "passive"))
      (node (ref "TP6X") (pin "TP") (pinfunction "TP_TP") (pintype "input"))
    )
    (net (code "301") (name "TRSTN") (class "Default")
      (node (ref "R57") (pin "1") (pinfunction "1_1") (pintype "passive"))
      (node (ref "R58") (pin "2") (pinfunction "2_2") (pintype "passive"))
      (node (ref "U4") (pin "P4") (pinfunction "TRST_P4") (pintype "input"))
      (node (ref "U5") (pin "P4") (pinfunction "TRST_P4") (pintype "input"))
    )
    (net (code "302") (name "TRSTN_R") (class "Default")
      (node (ref "R58") (pin "1") (pinfunction "1_1") (pintype "passive"))
      (node (ref "U6") (pin "21") (pinfunction "ADBUS4_21") (pintype "bidirectional"))
    )
    (net (code "303") (name "TUNER") (class "Default")
      (node (ref "C214") (pin "1") (pinfunction "1_1") (pintype "passive"))
      (node (ref "R214") (pin "2") (pinfunction "2_2") (pintype "passive"))
      (node (ref "R215") (pin "2") (pinfunction "2_2") (pintype "passive"))
      (node (ref "U5") (pin "A8") (pinfunction "GPAIN0_A8") (pintype "bidirectional"))
    )
    (net (code "304") (name "UART2_CTS") (class "Default")
      (node (ref "TP23X") (pin "TP") (pinfunction "TP_TP") (pintype "input"))
      (node (ref "U5") (pin "P12") (pinfunction "LCD_D[13]/UART_CTS/GP[29]/I2S3_FS_P12") (pintype "bidirectional"))
    )
    (net (code "305") (name "UART2_RX") (class "Default")
      (node (ref "TP24X") (pin "TP") (pinfunction "TP_TP") (pintype "input"))
      (node (ref "U5") (pin "P13") (pinfunction "LCD_D[14]/UART_RXD/GP[30]/I2S3_RX_P13") (pintype "bidirectional"))
    )
    (net (code "306") (name "UART2_TX") (class "Default")
      (node (ref "TP25X") (pin "TP") (pinfunction "TP_TP") (pintype "input"))
      (node (ref "U5") (pin "M11") (pinfunction "LCD_D[15]/UART_TXD/GP[31]/I2S3_DX_M11") (pintype "bidirectional"))
    )
    (net (code "307") (name "UART_CTS") (class "Default")
      (node (ref "R30") (pin "2") (pinfunction "2_2") (pintype "passive"))
      (node (ref "U4") (pin "P12") (pinfunction "LCD_D[13]/UART_CTS/GP[29]/I2S3_FS_P12") (pintype "bidirectional"))
    )
    (net (code "308") (name "UART_RTS") (class "Default")
      (node (ref "R27") (pin "2") (pinfunction "2_2") (pintype "passive"))
      (node (ref "U4") (pin "N12") (pinfunction "LCD_D[12]/UART_RTS/GP[28]/I2S3_CLK_N12") (pintype "bidirectional"))
    )
    (net (code "309") (name "UART_RX") (class "Default")
      (node (ref "R35") (pin "2") (pinfunction "2_2") (pintype "passive"))
      (node (ref "U4") (pin "P13") (pinfunction "LCD_D[14]/UART_RXD/GP[30]/I2S3_RX_P13") (pintype "bidirectional"))
    )
    (net (code "310") (name "UART_TX") (class "Default")
      (node (ref "R32") (pin "2") (pinfunction "2_2") (pintype "passive"))
      (node (ref "U4") (pin "M11") (pinfunction "LCD_D[15]/UART_TXD/GP[31]/I2S3_DX_M11") (pintype "bidirectional"))
    )
    (net (code "311") (name "USB1_LDO") (class "Default")
      (node (ref "R122") (pin "2") (pinfunction "2_2") (pintype "passive"))
      (node (ref "U4") (pin "D13") (pinfunction "USB_LDOO_D13") (pintype "power_in"))
    )
    (net (code "312") (name "USB1_VDD1P3") (class "Default")
      (node (ref "C5") (pin "1") (pinfunction "1_1") (pintype "passive"))
      (node (ref "C60") (pin "1") (pinfunction "1_1") (pintype "passive"))
      (node (ref "C74") (pin "1") (pinfunction "1_1") (pintype "passive"))
      (node (ref "FB6") (pin "2") (pinfunction "2_2") (pintype "passive"))
      (node (ref "U4") (pin "E12") (pinfunction "USB_VDD1P3_E12") (pintype "power_in"))
      (node (ref "U4") (pin "F14") (pinfunction "USB_VDD1P3_F14") (pintype "power_in"))
      (node (ref "U4") (pin "K13") (pinfunction "USB_VDD1P3_K13") (pintype "power_in"))
    )
    (net (code "313") (name "USB1_VDDA1P3") (class "Default")
      (node (ref "C2") (pin "1") (pinfunction "1_1") (pintype "passive"))
      (node (ref "C43") (pin "1") (pinfunction "1_1") (pintype "passive"))
      (node (ref "C49") (pin "1") (pinfunction "1_1") (pintype "passive"))
      (node (ref "FB4") (pin "2") (pinfunction "2_2") (pintype "passive"))
      (node (ref "U4") (pin "H12") (pinfunction "USB_VDDA1P3_H12") (pintype "power_in"))
    )
    (net (code "314") (name "USB1_VDDA3P3") (class "Default")
      (node (ref "C4") (pin "1") (pinfunction "1_1") (pintype "passive"))
      (node (ref "C56") (pin "1") (pinfunction "1_1") (pintype "passive"))
      (node (ref "C63") (pin "1") (pinfunction "1_1") (pintype "passive"))
      (node (ref "FB5") (pin "2") (pinfunction "2_2") (pintype "passive"))
      (node (ref "U4") (pin "G12") (pinfunction "USB_VDDA3P3_G12") (pintype "power_in"))
    )
    (net (code "315") (name "USB1_VDDOSC") (class "Default")
      (node (ref "C6") (pin "1") (pinfunction "1_1") (pintype "passive"))
      (node (ref "C66") (pin "1") (pinfunction "1_1") (pintype "passive"))
      (node (ref "C77") (pin "1") (pinfunction "1_1") (pintype "passive"))
      (node (ref "FB7") (pin "2") (pinfunction "2_2") (pintype "passive"))
      (node (ref "U4") (pin "E13") (pinfunction "USB_VDDOSC_E13") (pintype "power_in"))
    )
    (net (code "316") (name "USB1_VDDPLL") (class "Default")
      (node (ref "C3") (pin "1") (pinfunction "1_1") (pintype "passive"))
      (node (ref "C50") (pin "1") (pinfunction "1_1") (pintype "passive"))
      (node (ref "C57") (pin "1") (pinfunction "1_1") (pintype "passive"))
      (node (ref "L3") (pin "2") (pinfunction "2_2") (pintype "passive"))
      (node (ref "U4") (pin "G13") (pinfunction "USB_VDDPLL_G13") (pintype "power_in"))
    )
    (net (code "317") (name "USB2_CLK_12MHZ") (class "Default")
      (node (ref "R225X") (pin "2") (pinfunction "2_2") (pintype "passive"))
      (node (ref "R55-2") (pin "1") (pinfunction "1_1") (pintype "passive"))
    )
    (net (code "318") (name "USB2_D_N") (class "Default")
      (node (ref "J1-2") (pin "D-") (pinfunction "D-_D-") (pintype "bidirectional"))
      (node (ref "U5") (pin "J14") (pinfunction "USB_DM_J14") (pintype "bidirectional"))
    )
    (net (code "319") (name "USB2_D_P") (class "Default")
      (node (ref "J1-2") (pin "D+") (pinfunction "D+_D+") (pintype "bidirectional"))
      (node (ref "U5") (pin "H14") (pinfunction "USB_DP_H14") (pintype "bidirectional"))
    )
    (net (code "320") (name "USB2_LDO") (class "Default")
      (node (ref "R122-2") (pin "2") (pinfunction "2_2") (pintype "passive"))
      (node (ref "U5") (pin "D13") (pinfunction "USB_LDOO_D13") (pintype "power_in"))
    )
    (net (code "321") (name "USB2_VDD1P3") (class "Default")
      (node (ref "C5-2") (pin "1") (pinfunction "1_1") (pintype "passive"))
      (node (ref "C60-2") (pin "1") (pinfunction "1_1") (pintype "passive"))
      (node (ref "C74-2") (pin "1") (pinfunction "1_1") (pintype "passive"))
      (node (ref "FB6-2") (pin "2") (pinfunction "2_2") (pintype "passive"))
      (node (ref "U5") (pin "E12") (pinfunction "USB_VDD1P3_E12") (pintype "power_in"))
      (node (ref "U5") (pin "F14") (pinfunction "USB_VDD1P3_F14") (pintype "power_in"))
      (node (ref "U5") (pin "K13") (pinfunction "USB_VDD1P3_K13") (pintype "power_in"))
    )
    (net (code "322") (name "USB2_VDDA1P3") (class "Default")
      (node (ref "C2-2") (pin "1") (pinfunction "1_1") (pintype "passive"))
      (node (ref "C43-2") (pin "1") (pinfunction "1_1") (pintype "passive"))
      (node (ref "C49-2") (pin "1") (pinfunction "1_1") (pintype "passive"))
      (node (ref "FB4-2") (pin "2") (pinfunction "2_2") (pintype "passive"))
      (node (ref "U5") (pin "H12") (pinfunction "USB_VDDA1P3_H12") (pintype "power_in"))
    )
    (net (code "323") (name "USB2_VDDA3P3") (class "Default")
      (node (ref "C4-2") (pin "1") (pinfunction "1_1") (pintype "passive"))
      (node (ref "C56-2") (pin "1") (pinfunction "1_1") (pintype "passive"))
      (node (ref "C63-2") (pin "1") (pinfunction "1_1") (pintype "passive"))
      (node (ref "FB5-2") (pin "2") (pinfunction "2_2") (pintype "passive"))
      (node (ref "U5") (pin "G12") (pinfunction "USB_VDDA3P3_G12") (pintype "power_in"))
    )
    (net (code "324") (name "USB2_VDDOSC") (class "Default")
      (node (ref "C6-2") (pin "1") (pinfunction "1_1") (pintype "passive"))
      (node (ref "C66-2") (pin "1") (pinfunction "1_1") (pintype "passive"))
      (node (ref "C77-2") (pin "1") (pinfunction "1_1") (pintype "passive"))
      (node (ref "FB7-2") (pin "2") (pinfunction "2_2") (pintype "passive"))
      (node (ref "U5") (pin "E13") (pinfunction "USB_VDDOSC_E13") (pintype "power_in"))
    )
    (net (code "325") (name "USB2_VDDPLL") (class "Default")
      (node (ref "C3-2") (pin "1") (pinfunction "1_1") (pintype "passive"))
      (node (ref "C50-2") (pin "1") (pinfunction "1_1") (pintype "passive"))
      (node (ref "C57-2") (pin "1") (pinfunction "1_1") (pintype "passive"))
      (node (ref "L3-2") (pin "2") (pinfunction "2_2") (pintype "passive"))
      (node (ref "U5") (pin "G13") (pinfunction "USB_VDDPLL_G13") (pintype "power_in"))
    )
    (net (code "326") (name "USB_CLK_12MHZ") (class "Default")
      (node (ref "R230X") (pin "2") (pinfunction "2_2") (pintype "passive"))
      (node (ref "R55") (pin "1") (pinfunction "1_1") (pintype "passive"))
    )
    (net (code "327") (name "USB_D_N") (class "Default")
      (node (ref "J1") (pin "D-") (pinfunction "D-_D-") (pintype "bidirectional"))
      (node (ref "U4") (pin "J14") (pinfunction "USB_DM_J14") (pintype "bidirectional"))
    )
    (net (code "328") (name "USB_D_P") (class "Default")
      (node (ref "J1") (pin "D+") (pinfunction "D+_D+") (pintype "bidirectional"))
      (node (ref "U4") (pin "H14") (pinfunction "USB_DP_H14") (pintype "bidirectional"))
    )
    (net (code "329") (name "USB_LDO_OUT") (class "Default")
      (node (ref "FB4") (pin "1") (pinfunction "1_1") (pintype "passive"))
      (node (ref "FB6") (pin "1") (pinfunction "1_1") (pintype "passive"))
      (node (ref "R121") (pin "2") (pinfunction "2_2") (pintype "passive"))
      (node (ref "R122") (pin "1") (pinfunction "1_1") (pintype "passive"))
    )
    (net (code "330") (name "USB_LDO_OUT2") (class "Default")
      (node (ref "FB4-2") (pin "1") (pinfunction "1_1") (pintype "passive"))
      (node (ref "FB6-2") (pin "1") (pinfunction "1_1") (pintype "passive"))
      (node (ref "R121-2") (pin "2") (pinfunction "2_2") (pintype "passive"))
      (node (ref "R122-2") (pin "1") (pinfunction "1_1") (pintype "passive"))
    )
    (net (code "331") (name "USB_N") (class "Default")
      (node (ref "J2") (pin "D-") (pinfunction "D-_D-") (pintype "bidirectional"))
      (node (ref "U6") (pin "7") (pinfunction "USBDM_7") (pintype "bidirectional"))
      (node (ref "U7") (pin "5") (pinfunction "IO2_5") (pintype "bidirectional"))
    )
    (net (code "332") (name "USB_P") (class "Default")
      (node (ref "J2") (pin "D+") (pinfunction "D+_D+") (pintype "bidirectional"))
      (node (ref "U6") (pin "8") (pinfunction "USBDP_8") (pintype "bidirectional"))
      (node (ref "U7") (pin "3") (pinfunction "IO1_3") (pintype "bidirectional"))
    )
    (net (code "333") (name "USB_XI") (class "Default")
      (node (ref "R55") (pin "2") (pinfunction "2_2") (pintype "passive"))
      (node (ref "R56") (pin "2") (pinfunction "2_2") (pintype "passive"))
      (node (ref "U4") (pin "E14") (pinfunction "USB_MXI_E14") (pintype "input"))
    )
    (net (code "334") (name "USB_XI2") (class "Default")
      (node (ref "R55-2") (pin "2") (pinfunction "2_2") (pintype "passive"))
      (node (ref "R56-2") (pin "2") (pinfunction "2_2") (pintype "passive"))
      (node (ref "U5") (pin "E14") (pinfunction "USB_MXI_E14") (pintype "input"))
    )
    (net (code "335") (name "V1.65") (class "Default")
      (node (ref "R145") (pin "1") (pinfunction "1_1") (pintype "passive"))
      (node (ref "R171") (pin "1") (pinfunction "1_1") (pintype "passive"))
      (node (ref "R198") (pin "2") (pinfunction "2_2") (pintype "passive"))
      (node (ref "R199") (pin "2") (pinfunction "2_2") (pintype "passive"))
      (node (ref "R200") (pin "2") (pinfunction "2_2") (pintype "passive"))
      (node (ref "U20") (pin "1") (pinfunction "OUT_1") (pintype "output"))
      (node (ref "U20") (pin "2") (pinfunction "-IN_2") (pintype "input"))
      (node (ref "U20") (pin "5") (pinfunction "+IN_5") (pintype "input"))
      (node (ref "U22") (pin "2") (pinfunction "-IN_2") (pintype "input"))
      (node (ref "U22") (pin "5") (pinfunction "+IN_5") (pintype "input"))
      (node (ref "U23") (pin "2") (pinfunction "-IN_2") (pintype "input"))
      (node (ref "U23") (pin "5") (pinfunction "+IN_5") (pintype "input"))
    )
    (net (code "336") (name "V3.3A") (class "Default")
      (node (ref "C179") (pin "+") (pinfunction "+_+") (pintype "passive"))
      (node (ref "C185") (pin "1") (pinfunction "1_1") (pintype "passive"))
      (node (ref "C204") (pin "1") (pinfunction "1_1") (pintype "passive"))
      (node (ref "C209") (pin "1") (pinfunction "1_1") (pintype "passive"))
      (node (ref "C220") (pin "1") (pinfunction "1_1") (pintype "passive"))
      (node (ref "C221") (pin "1") (pinfunction "1_1") (pintype "passive"))
      (node (ref "C222") (pin "1") (pinfunction "1_1") (pintype "passive"))
      (node (ref "C223") (pin "1") (pinfunction "1_1") (pintype "passive"))
      (node (ref "C224") (pin "1") (pinfunction "1_1") (pintype "passive"))
      (node (ref "D9") (pin "C") (pinfunction "C_C") (pintype "passive"))
      (node (ref "FB3") (pin "2") (pinfunction "2_2") (pintype "passive"))
      (node (ref "IC2") (pin "14") (pinfunction "VDD_14") (pintype "power_in"))
      (node (ref "Q3") (pin "1") (pinfunction "D_1") (pintype "passive"))
      (node (ref "R108") (pin "2") (pinfunction "2_2") (pintype "passive"))
      (node (ref "R146") (pin "2") (pinfunction "2_2") (pintype "passive"))
      (node (ref "R168") (pin "2") (pinfunction "2_2") (pintype "passive"))
      (node (ref "R201") (pin "2") (pinfunction "2_2") (pintype "passive"))
      (node (ref "R202") (pin "2") (pinfunction "2_2") (pintype "passive"))
      (node (ref "R203") (pin "2") (pinfunction "2_2") (pintype "passive"))
      (node (ref "R204") (pin "2") (pinfunction "2_2") (pintype "passive"))
      (node (ref "R207") (pin "2") (pinfunction "2_2") (pintype "passive"))
      (node (ref "R211") (pin "2") (pinfunction "2_2") (pintype "passive"))
      (node (ref "U13") (pin "5") (pinfunction "VCC_5") (pintype "power_in"))
      (node (ref "U19") (pin "8") (pinfunction "V+_8") (pintype "power_in"))
      (node (ref "U20") (pin "8") (pinfunction "V+_8") (pintype "power_in"))
      (node (ref "U21") (pin "8") (pinfunction "V+_8") (pintype "power_in"))
      (node (ref "U22") (pin "8") (pinfunction "V+_8") (pintype "power_in"))
      (node (ref "U23") (pin "8") (pinfunction "V+_8") (pintype "power_in"))
      (node (ref "U24") (pin "8") (pinfunction "+V_8") (pintype "power_in"))
    )
    (net (code "337") (name "VBUS2_C5535") (class "Default")
      (node (ref "C24-2") (pin "1") (pinfunction "1_1") (pintype "passive"))
      (node (ref "C25-2") (pin "1") (pinfunction "1_1") (pintype "passive"))
      (node (ref "D2-2") (pin "C") (pinfunction "C_C") (pintype "passive"))
      (node (ref "D5") (pin "A") (pinfunction "A_A") (pintype "passive"))
      (node (ref "J1-2") (pin "VBUS") (pinfunction "VBUS_VBUS") (pintype "bidirectional"))
      (node (ref "R18-2") (pin "2") (pinfunction "2_2") (pintype "passive"))
      (node (ref "U5") (pin "L14") (pinfunction "USB_VBUS_L14") (pintype "bidirectional"))
    )
    (net (code "338") (name "VBUS_C5535") (class "Default")
      (node (ref "C24") (pin "1") (pinfunction "1_1") (pintype "passive"))
      (node (ref "C25") (pin "1") (pinfunction "1_1") (pintype "passive"))
      (node (ref "D2") (pin "C") (pinfunction "C_C") (pintype "passive"))
      (node (ref "D3") (pin "A") (pinfunction "A_A") (pintype "passive"))
      (node (ref "J1") (pin "VBUS") (pinfunction "VBUS_VBUS") (pintype "bidirectional"))
      (node (ref "R18") (pin "2") (pinfunction "2_2") (pintype "passive"))
      (node (ref "U4") (pin "L14") (pinfunction "USB_VBUS_L14") (pintype "bidirectional"))
    )
    (net (code "339") (name "VCCUSB") (class "Default")
      (node (ref "C7") (pin "1") (pinfunction "1_1") (pintype "passive"))
      (node (ref "C92") (pin "1") (pinfunction "1_1") (pintype "passive"))
      (node (ref "D4") (pin "A") (pinfunction "A_A") (pintype "passive"))
      (node (ref "L1") (pin "2") (pinfunction "2_2") (pintype "passive"))
    )
    (net (code "340") (name "VCC_1V3") (class "Default")
      (node (ref "C26X") (pin "1") (pinfunction "1_1") (pintype "passive"))
      (node (ref "C83") (pin "1") (pinfunction "1_1") (pintype "passive"))
      (node (ref "C83-2") (pin "1") (pinfunction "1_1") (pintype "passive"))
      (node (ref "C84") (pin "1") (pinfunction "1_1") (pintype "passive"))
      (node (ref "C84-2") (pin "1") (pinfunction "1_1") (pintype "passive"))
      (node (ref "C95X") (pin "1") (pinfunction "1_1") (pintype "passive"))
      (node (ref "R121") (pin "1") (pinfunction "1_1") (pintype "passive"))
      (node (ref "R121-2") (pin "1") (pinfunction "1_1") (pintype "passive"))
      (node (ref "R125X") (pin "2") (pinfunction "2_2") (pintype "passive"))
      (node (ref "R222X") (pin "1") (pinfunction "1_1") (pintype "passive"))
      (node (ref "U11X") (pin "5") (pinfunction "OUT_5") (pintype "power_in"))
      (node (ref "U3X") (pin "5") (pinfunction "SENSE_5") (pintype "input"))
      (node (ref "U4") (pin "B4") (pinfunction "CVDDRTC_B4") (pintype "power_in"))
      (node (ref "U4") (pin "B5") (pinfunction "CVDDRTC1_B5") (pintype "power_in"))
      (node (ref "U5") (pin "B4") (pinfunction "CVDDRTC_B4") (pintype "power_in"))
      (node (ref "U5") (pin "B5") (pinfunction "CVDDRTC1_B5") (pintype "power_in"))
    )
    (net (code "341") (name "VCC_1V8") (class "Default")
      (node (ref "C71") (pin "1") (pinfunction "1_1") (pintype "passive"))
      (node (ref "C71-2") (pin "1") (pinfunction "1_1") (pintype "passive"))
      (node (ref "C75") (pin "1") (pinfunction "1_1") (pintype "passive"))
      (node (ref "C75-2") (pin "1") (pinfunction "1_1") (pintype "passive"))
      (node (ref "C87") (pin "1") (pinfunction "1_1") (pintype "passive"))
      (node (ref "C87-2") (pin "1") (pinfunction "1_1") (pintype "passive"))
      (node (ref "C98X") (pin "1") (pinfunction "1_1") (pintype "passive"))
      (node (ref "R106") (pin "1") (pinfunction "1_1") (pintype "passive"))
      (node (ref "R107") (pin "2") (pinfunction "2_2") (pintype "passive"))
      (node (ref "R118X") (pin "2") (pinfunction "2_2") (pintype "passive"))
      (node (ref "R63") (pin "2") (pinfunction "2_2") (pintype "passive"))
      (node (ref "R63-2") (pin "2") (pinfunction "2_2") (pintype "passive"))
      (node (ref "U11X") (pin "1") (pinfunction "IN_1") (pintype "power_in"))
      (node (ref "U11X") (pin "3") (pinfunction "EN_3") (pintype "input"))
      (node (ref "U4") (pin "B10") (pinfunction "LDOI_B10") (pintype "power_in"))
      (node (ref "U4") (pin "B14") (pinfunction "LDOI_B14") (pintype "power_in"))
      (node (ref "U4") (pin "C14") (pinfunction "LDOI_C14") (pintype "power_in"))
      (node (ref "U5") (pin "B10") (pinfunction "LDOI_B10") (pintype "power_in"))
      (node (ref "U5") (pin "B14") (pinfunction "LDOI_B14") (pintype "power_in"))
      (node (ref "U5") (pin "C14") (pinfunction "LDOI_C14") (pintype "power_in"))
    )
    (net (code "342") (name "VCC_3V3") (class "Default")
      (node (ref "C10") (pin "1") (pinfunction "1_1") (pintype "passive"))
      (node (ref "C104") (pin "1") (pinfunction "1_1") (pintype "passive"))
      (node (ref "C122") (pin "1") (pinfunction "1_1") (pintype "passive"))
      (node (ref "C15") (pin "1") (pinfunction "1_1") (pintype "passive"))
      (node (ref "C169X") (pin "1") (pinfunction "1_1") (pintype "passive"))
      (node (ref "C21") (pin "1") (pinfunction "1_1") (pintype "passive"))
      (node (ref "C218X") (pin "1") (pinfunction "1_1") (pintype "passive"))
      (node (ref "C81") (pin "1") (pinfunction "1_1") (pintype "passive"))
      (node (ref "C81-2") (pin "1") (pinfunction "1_1") (pintype "passive"))
      (node (ref "C9") (pin "1") (pinfunction "1_1") (pintype "passive"))
      (node (ref "FB3") (pin "1") (pinfunction "1_1") (pintype "passive"))
      (node (ref "J11") (pin "4") (pinfunction "VDD_4") (pintype "power_in"))
      (node (ref "J5") (pin "1") (pinfunction "1_1") (pintype "passive"))
      (node (ref "J5") (pin "5") (pinfunction "5_5") (pintype "passive"))
      (node (ref "J6") (pin "4") (pinfunction "VDD_4") (pintype "power_in"))
      (node (ref "J7") (pin "2") (pinfunction "2_2") (pintype "passive"))
      (node (ref "L8X") (pin "1") (pinfunction "1_1") (pintype "passive"))
      (node (ref "R1") (pin "2") (pinfunction "2_2") (pintype "passive"))
      (node (ref "R10") (pin "2") (pinfunction "2_2") (pintype "passive"))
      (node (ref "R100") (pin "2") (pinfunction "2_2") (pintype "passive"))
      (node (ref "R101") (pin "2") (pinfunction "2_2") (pintype "passive"))
      (node (ref "R102") (pin "2") (pinfunction "2_2") (pintype "passive"))
      (node (ref "R103") (pin "2") (pinfunction "2_2") (pintype "passive"))
      (node (ref "R109") (pin "2") (pinfunction "2_2") (pintype "passive"))
      (node (ref "R11") (pin "2") (pinfunction "2_2") (pintype "passive"))
      (node (ref "R134") (pin "2") (pinfunction "2_2") (pintype "passive"))
      (node (ref "R135") (pin "2") (pinfunction "2_2") (pintype "passive"))
      (node (ref "R141") (pin "2") (pinfunction "2_2") (pintype "passive"))
      (node (ref "R143X") (pin "2") (pinfunction "2_2") (pintype "passive"))
      (node (ref "R2") (pin "2") (pinfunction "2_2") (pintype "passive"))
      (node (ref "R2X") (pin "2") (pinfunction "2_2") (pintype "passive"))
      (node (ref "R3") (pin "2") (pinfunction "2_2") (pintype "passive"))
      (node (ref "R3X") (pin "2") (pinfunction "2_2") (pintype "passive"))
      (node (ref "R4") (pin "2") (pinfunction "2_2") (pintype "passive"))
      (node (ref "R4X") (pin "2") (pinfunction "2_2") (pintype "passive"))
      (node (ref "R5") (pin "1") (pinfunction "1_1") (pintype "passive"))
      (node (ref "R6") (pin "2") (pinfunction "2_2") (pintype "passive"))
      (node (ref "R7") (pin "2") (pinfunction "2_2") (pintype "passive"))
      (node (ref "R98") (pin "2") (pinfunction "2_2") (pintype "passive"))
      (node (ref "R99") (pin "2") (pinfunction "2_2") (pintype "passive"))
      (node (ref "U10X") (pin "8") (pinfunction "VCC_8") (pintype "power_in"))
      (node (ref "U14") (pin "1") (pinfunction "E/D_1") (pintype "input"))
      (node (ref "U14") (pin "4") (pinfunction "VCC_4") (pintype "power_in"))
      (node (ref "U18") (pin "20") (pinfunction "VCC_20") (pintype "power_in"))
      (node (ref "U3X") (pin "4") (pinfunction "VDD_4") (pintype "power_in"))
      (node (ref "U9") (pin "2") (pinfunction "VCC_2") (pintype "power_in"))
      (node (ref "U9-2") (pin "2") (pinfunction "VCC_2") (pintype "power_in"))
    )
    (net (code "343") (name "VCC_3V3_CLK") (class "Default")
      (node (ref "C213X") (pin "1") (pinfunction "1_1") (pintype "passive"))
      (node (ref "C215X") (pin "1") (pinfunction "1_1") (pintype "passive"))
      (node (ref "C216X") (pin "1") (pinfunction "1_1") (pintype "passive"))
      (node (ref "C217X") (pin "1") (pinfunction "1_1") (pintype "passive"))
      (node (ref "L8X") (pin "2") (pinfunction "2_2") (pintype "passive"))
      (node (ref "U15X") (pin "10") (pinfunction "VDD_3_10") (pintype "power_in"))
      (node (ref "U15X") (pin "14") (pinfunction "VDD_14") (pintype "power_in"))
      (node (ref "U15X") (pin "5") (pinfunction "VDD_2_5") (pintype "power_in"))
    )
    (net (code "344") (name "VCC_3V3_PWR") (class "Default")
      (node (ref "C94X") (pin "1") (pinfunction "1_1") (pintype "passive"))
      (node (ref "L7X") (pin "1") (pinfunction "1_1") (pintype "passive"))
      (node (ref "R119X") (pin "1") (pinfunction "1_1") (pintype "passive"))
      (node (ref "R15") (pin "1") (pinfunction "1_1") (pintype "passive"))
      (node (ref "R1X") (pin "1") (pinfunction "1_1") (pintype "passive"))
      (node (ref "R2X") (pin "1") (pinfunction "1_1") (pintype "passive"))
      (node (ref "R65X") (pin "2") (pinfunction "2_2") (pintype "passive"))
      (node (ref "R96X") (pin "1") (pinfunction "1_1") (pintype "passive"))
      (node (ref "R97") (pin "2") (pinfunction "2_2") (pintype "passive"))
      (node (ref "R97-2") (pin "2") (pinfunction "2_2") (pintype "passive"))
      (node (ref "TP5X") (pin "TP") (pinfunction "TP_TP") (pintype "input"))
    )
    (net (code "345") (name "VCC_3V3_USB") (class "Default")
      (node (ref "FB5") (pin "1") (pinfunction "1_1") (pintype "passive"))
      (node (ref "FB5-2") (pin "1") (pinfunction "1_1") (pintype "passive"))
      (node (ref "FB7") (pin "1") (pinfunction "1_1") (pintype "passive"))
      (node (ref "FB7-2") (pin "1") (pinfunction "1_1") (pintype "passive"))
      (node (ref "L3") (pin "1") (pinfunction "1_1") (pintype "passive"))
      (node (ref "L3-2") (pin "1") (pinfunction "1_1") (pintype "passive"))
      (node (ref "R96X") (pin "2") (pinfunction "2_2") (pintype "passive"))
    )
    (net (code "346") (name "VCC_USB_DUAL") (class "Default")
      (node (ref "C23X") (pin "1") (pinfunction "1_1") (pintype "passive"))
      (node (ref "C99X") (pin "1") (pinfunction "1_1") (pintype "passive"))
      (node (ref "D1") (pin "C") (pinfunction "C_C") (pintype "passive"))
      (node (ref "D3") (pin "C") (pinfunction "C_C") (pintype "passive"))
      (node (ref "D4") (pin "C") (pinfunction "C_C") (pintype "passive"))
      (node (ref "D5") (pin "C") (pinfunction "C_C") (pintype "passive"))
      (node (ref "DS1") (pin "A") (pinfunction "A_A") (pintype "passive"))
      (node (ref "U12X") (pin "3") (pinfunction "VIN_3") (pintype "power_in"))
      (node (ref "U12X") (pin "5") (pinfunction "EN_5") (pintype "input"))
      (node (ref "U1X") (pin "3") (pinfunction "VIN_3") (pintype "power_in"))
      (node (ref "U1X") (pin "5") (pinfunction "EN_5") (pintype "input"))
    )
    (net (code "347") (name "VDD_IO1") (class "Default")
      (node (ref "C82") (pin "1") (pinfunction "1_1") (pintype "passive"))
      (node (ref "R119X") (pin "2") (pinfunction "2_2") (pintype "passive"))
      (node (ref "R13") (pin "2") (pinfunction "2_2") (pintype "passive"))
      (node (ref "R14") (pin "2") (pinfunction "2_2") (pintype "passive"))
      (node (ref "R16") (pin "2") (pinfunction "2_2") (pintype "passive"))
      (node (ref "R22") (pin "2") (pinfunction "2_2") (pintype "passive"))
      (node (ref "R25") (pin "2") (pinfunction "2_2") (pintype "passive"))
      (node (ref "R37") (pin "2") (pinfunction "2_2") (pintype "passive"))
      (node (ref "R41") (pin "2") (pinfunction "2_2") (pintype "passive"))
      (node (ref "R50") (pin "2") (pinfunction "2_2") (pintype "passive"))
      (node (ref "R51") (pin "2") (pinfunction "2_2") (pintype "passive"))
      (node (ref "R52") (pin "2") (pinfunction "2_2") (pintype "passive"))
      (node (ref "R72") (pin "2") (pinfunction "2_2") (pintype "passive"))
      (node (ref "R73") (pin "2") (pinfunction "2_2") (pintype "passive"))
      (node (ref "U4") (pin "C3") (pinfunction "DVDDRTC_C3") (pintype "power_in"))
    )
    (net (code "348") (name "VDD_IO1_CPU") (class "Default")
      (node (ref "C1") (pin "1") (pinfunction "1_1") (pintype "passive"))
      (node (ref "C28") (pin "1") (pinfunction "1_1") (pintype "passive"))
      (node (ref "C29") (pin "1") (pinfunction "1_1") (pintype "passive"))
      (node (ref "C30") (pin "1") (pinfunction "1_1") (pintype "passive"))
      (node (ref "C32") (pin "1") (pinfunction "1_1") (pintype "passive"))
      (node (ref "C45") (pin "1") (pinfunction "1_1") (pintype "passive"))
      (node (ref "C72") (pin "1") (pinfunction "1_1") (pintype "passive"))
      (node (ref "R97") (pin "1") (pinfunction "1_1") (pintype "passive"))
      (node (ref "U4") (pin "C6") (pinfunction "DVDDIO_C6") (pintype "power_in"))
      (node (ref "U4") (pin "L4") (pinfunction "DVDDIO_L4") (pintype "power_in"))
      (node (ref "U4") (pin "M3") (pinfunction "DVDDIO_M3") (pintype "power_in"))
      (node (ref "U4") (pin "M4") (pinfunction "DVDDIO_M4") (pintype "power_in"))
      (node (ref "U4") (pin "N11") (pinfunction "DVDDIO_N11") (pintype "power_in"))
      (node (ref "U4") (pin "N14") (pinfunction "DVDDIO_N14") (pintype "power_in"))
      (node (ref "U4") (pin "N8") (pinfunction "DVDDIO_N8") (pintype "power_in"))
    )
    (net (code "349") (name "VDD_IO2") (class "Default")
      (node (ref "C82-2") (pin "1") (pinfunction "1_1") (pintype "passive"))
      (node (ref "R13-2") (pin "2") (pinfunction "2_2") (pintype "passive"))
      (node (ref "R14-2") (pin "2") (pinfunction "2_2") (pintype "passive"))
      (node (ref "R15") (pin "2") (pinfunction "2_2") (pintype "passive"))
      (node (ref "R37-2") (pin "2") (pinfunction "2_2") (pintype "passive"))
      (node (ref "R41-2") (pin "2") (pinfunction "2_2") (pintype "passive"))
      (node (ref "R50-2") (pin "2") (pinfunction "2_2") (pintype "passive"))
      (node (ref "R51-2") (pin "2") (pinfunction "2_2") (pintype "passive"))
      (node (ref "R52-1") (pin "2") (pinfunction "2_2") (pintype "passive"))
      (node (ref "R52-2") (pin "2") (pinfunction "2_2") (pintype "passive"))
      (node (ref "R72-2") (pin "2") (pinfunction "2_2") (pintype "passive"))
      (node (ref "R73-2") (pin "2") (pinfunction "2_2") (pintype "passive"))
      (node (ref "U5") (pin "C3") (pinfunction "DVDDRTC_C3") (pintype "power_in"))
    )
    (net (code "350") (name "VDD_IO2_CPU") (class "Default")
      (node (ref "C1-2") (pin "1") (pinfunction "1_1") (pintype "passive"))
      (node (ref "C28-2") (pin "1") (pinfunction "1_1") (pintype "passive"))
      (node (ref "C29-2") (pin "1") (pinfunction "1_1") (pintype "passive"))
      (node (ref "C30-2") (pin "1") (pinfunction "1_1") (pintype "passive"))
      (node (ref "C32-2") (pin "1") (pinfunction "1_1") (pintype "passive"))
      (node (ref "C45-2") (pin "1") (pinfunction "1_1") (pintype "passive"))
      (node (ref "C72-2") (pin "1") (pinfunction "1_1") (pintype "passive"))
      (node (ref "R97-2") (pin "1") (pinfunction "1_1") (pintype "passive"))
      (node (ref "U5") (pin "C6") (pinfunction "DVDDIO_C6") (pintype "power_in"))
      (node (ref "U5") (pin "L4") (pinfunction "DVDDIO_L4") (pintype "power_in"))
      (node (ref "U5") (pin "M3") (pinfunction "DVDDIO_M3") (pintype "power_in"))
      (node (ref "U5") (pin "M4") (pinfunction "DVDDIO_M4") (pintype "power_in"))
      (node (ref "U5") (pin "N11") (pinfunction "DVDDIO_N11") (pintype "power_in"))
      (node (ref "U5") (pin "N14") (pinfunction "DVDDIO_N14") (pintype "power_in"))
      (node (ref "U5") (pin "N8") (pinfunction "DVDDIO_N8") (pintype "power_in"))
    )
    (net (code "351") (name "VPHY") (class "Default")
      (node (ref "C44") (pin "2") (pinfunction "2_2") (pintype "passive"))
      (node (ref "C47") (pin "2") (pinfunction "2_2") (pintype "passive"))
      (node (ref "L4") (pin "2") (pinfunction "2_2") (pintype "passive"))
      (node (ref "U6") (pin "4") (pinfunction "VPHY_4") (pintype "power_in"))
    )
    (net (code "352") (name "VPLL") (class "Default")
      (node (ref "C61") (pin "2") (pinfunction "2_2") (pintype "passive"))
      (node (ref "C76") (pin "2") (pinfunction "2_2") (pintype "passive"))
      (node (ref "L5") (pin "2") (pinfunction "2_2") (pintype "passive"))
      (node (ref "U6") (pin "9") (pinfunction "VPLL_9") (pintype "power_in"))
    )
    (net (code "353") (name "VSS1RTC") (class "Default")
      (node (ref "C90") (pin "1") (pinfunction "1_1") (pintype "passive"))
      (node (ref "C91") (pin "1") (pinfunction "1_1") (pintype "passive"))
      (node (ref "U4") (pin "C5") (pinfunction "VSSRTC_C5") (pintype "power_in"))
    )
    (net (code "354") (name "VSS2RTC") (class "Default")
      (node (ref "C90-2") (pin "1") (pinfunction "1_1") (pintype "passive"))
      (node (ref "C91-2") (pin "1") (pinfunction "1_1") (pintype "passive"))
      (node (ref "U5") (pin "C5") (pinfunction "VSSRTC_C5") (pintype "power_in"))
    )
    (net (code "355") (name "VUSB") (class "Default")
      (node (ref "C93") (pin "1") (pinfunction "1_1") (pintype "passive"))
      (node (ref "J2") (pin "VUSB") (pinfunction "VBUS_VUSB") (pintype "bidirectional"))
      (node (ref "L1") (pin "1") (pinfunction "1_1") (pintype "passive"))
      (node (ref "U7") (pin "1") (pinfunction "VCC_1") (pintype "power_in"))
    )
    (net (code "356") (name "WAKEUP") (class "Default")
      (node (ref "R59") (pin "2") (pinfunction "2_2") (pintype "passive"))
      (node (ref "U4") (pin "A5") (pinfunction "WAKEUP_A5") (pintype "bidirectional"))
    )
    (net (code "357") (name "WAKEUP2") (class "Default")
      (node (ref "R59-2") (pin "2") (pinfunction "2_2") (pintype "passive"))
      (node (ref "U5") (pin "A5") (pinfunction "WAKEUP_A5") (pintype "bidirectional"))
    )
    (net (code "358") (name "XF") (class "Default")
      (node (ref "R67") (pin "2") (pinfunction "2_2") (pintype "passive"))
      (node (ref "U4") (pin "J3") (pinfunction "XF_J3") (pintype "output"))
    )
    (net (code "359") (name "XF2") (class "Default")
      (node (ref "R105X") (pin "2") (pinfunction "2_2") (pintype "passive"))
      (node (ref "U5") (pin "J3") (pinfunction "XF_J3") (pintype "output"))
    )
    (net (code "360") (name "unconnected-(CF1-2-Pad2@2)") (class "Default")
      (node (ref "CF1") (pin "2@2") (pinfunction "2_2@2") (pintype "passive"))
    )
    (net (code "361") (name "unconnected-(D8-C1A2-Pad3)") (class "Default")
      (node (ref "D8") (pin "3") (pinfunction "C1A2_3") (pintype "passive"))
    )
    (net (code "362") (name "unconnected-(J1-2-PadID)") (class "Default")
      (node (ref "J1-2") (pin "ID") (pinfunction "ID_ID") (pintype "bidirectional"))
    )
    (net (code "363") (name "unconnected-(J1-PadID)") (class "Default")
      (node (ref "J1") (pin "ID") (pinfunction "ID_ID") (pintype "bidirectional"))
    )
    (net (code "364") (name "unconnected-(J4-RN-Pad5)") (class "Default")
      (node (ref "J4") (pin "5") (pinfunction "RN_5") (pintype "passive"))
    )
    (net (code "365") (name "unconnected-(J4-TN-Pad4)") (class "Default")
      (node (ref "J4") (pin "4") (pinfunction "TN_4") (pintype "passive"))
    )
    (net (code "366") (name "unconnected-(J6-Pad10)") (class "Default")
      (node (ref "J6") (pin "10") (pinfunction "10_10") (pintype "no_connect"))
    )
    (net (code "367") (name "unconnected-(J6-Pad12)") (class "Default")
      (node (ref "J6") (pin "12") (pinfunction "12_12") (pintype "no_connect"))
    )
    (net (code "368") (name "unconnected-(J6-Pad13)") (class "Default")
      (node (ref "J6") (pin "13") (pinfunction "13_13") (pintype "no_connect"))
    )
    (net (code "369") (name "unconnected-(J6-Pad14)") (class "Default")
      (node (ref "J6") (pin "14") (pinfunction "14_14") (pintype "no_connect"))
    )
    (net (code "370") (name "unconnected-(J9-PadSN)") (class "Default")
      (node (ref "J9") (pin "SN") (pinfunction "SN_SN") (pintype "passive"))
    )
    (net (code "371") (name "unconnected-(J9-PadTN)") (class "Default")
      (node (ref "J9") (pin "TN") (pinfunction "TN_TN") (pintype "passive"))
    )
    (net (code "372") (name "unconnected-(J10-PadSN)") (class "Default")
      (node (ref "J10") (pin "SN") (pinfunction "SN_SN") (pintype "passive"))
    )
    (net (code "373") (name "unconnected-(J10-PadTN)") (class "Default")
      (node (ref "J10") (pin "TN") (pinfunction "TN_TN") (pintype "passive"))
    )
    (net (code "374") (name "unconnected-(J11-Pad10)") (class "Default")
      (node (ref "J11") (pin "10") (pinfunction "10_10") (pintype "no_connect"))
    )
    (net (code "375") (name "unconnected-(J11-Pad12)") (class "Default")
      (node (ref "J11") (pin "12") (pinfunction "12_12") (pintype "no_connect"))
    )
    (net (code "376") (name "unconnected-(J11-Pad13)") (class "Default")
      (node (ref "J11") (pin "13") (pinfunction "13_13") (pintype "no_connect"))
    )
    (net (code "377") (name "unconnected-(J11-Pad14)") (class "Default")
      (node (ref "J11") (pin "14") (pinfunction "14_14") (pintype "no_connect"))
    )
    (net (code "378") (name "unconnected-(SW2A-O-Pad3)") (class "Default")
      (node (ref "SW2") (pin "3") (pinfunction "O_3") (pintype "passive"))
    )
    (net (code "379") (name "unconnected-(U2-DC-Pad7)") (class "Default")
      (node (ref "U2") (pin "7") (pinfunction "DC_7") (pintype "no_connect"))
    )
    (net (code "380") (name "unconnected-(U2-NC-Pad6)") (class "Default")
      (node (ref "U2") (pin "6") (pinfunction "NC_6") (pintype "no_connect"))
    )
    (net (code "381") (name "unconnected-(U3X-NC-Pad1)") (class "Default")
      (node (ref "U3X") (pin "1") (pinfunction "NC_1") (pintype "no_connect"))
    )
    (net (code "382") (name "unconnected-(U4B-RSV7-PadE1)") (class "Default")
      (node (ref "U4") (pin "E1") (pinfunction "RSV7_E1") (pintype "input"))
    )
    (net (code "383") (name "unconnected-(U4B-RSV8-PadF1)") (class "Default")
      (node (ref "U4") (pin "F1") (pinfunction "RSV8_F1") (pintype "input"))
    )
    (net (code "384") (name "unconnected-(U4B-RSV9-PadG1)") (class "Default")
      (node (ref "U4") (pin "G1") (pinfunction "RSV9_G1") (pintype "input"))
    )
    (net (code "385") (name "unconnected-(U4B-RSV10-PadH1)") (class "Default")
      (node (ref "U4") (pin "H1") (pinfunction "RSV10_H1") (pintype "input"))
    )
    (net (code "386") (name "unconnected-(U4B-RSV11-PadE2)") (class "Default")
      (node (ref "U4") (pin "E2") (pinfunction "RSV11_E2") (pintype "input"))
    )
    (net (code "387") (name "unconnected-(U4B-RSV12-PadG2)") (class "Default")
      (node (ref "U4") (pin "G2") (pinfunction "RSV12_G2") (pintype "input"))
    )
    (net (code "388") (name "unconnected-(U4B-USB_MXO-PadD14)") (class "Default")
      (node (ref "U4") (pin "D14") (pinfunction "USB_MXO_D14") (pintype "output"))
    )
    (net (code "389") (name "unconnected-(U5B-RSV7-PadE1)") (class "Default")
      (node (ref "U5") (pin "E1") (pinfunction "RSV7_E1") (pintype "input"))
    )
    (net (code "390") (name "unconnected-(U5B-RSV8-PadF1)") (class "Default")
      (node (ref "U5") (pin "F1") (pinfunction "RSV8_F1") (pintype "input"))
    )
    (net (code "391") (name "unconnected-(U5B-RSV9-PadG1)") (class "Default")
      (node (ref "U5") (pin "G1") (pinfunction "RSV9_G1") (pintype "input"))
    )
    (net (code "392") (name "unconnected-(U5B-RSV10-PadH1)") (class "Default")
      (node (ref "U5") (pin "H1") (pinfunction "RSV10_H1") (pintype "input"))
    )
    (net (code "393") (name "unconnected-(U5B-RSV11-PadE2)") (class "Default")
      (node (ref "U5") (pin "E2") (pinfunction "RSV11_E2") (pintype "input"))
    )
    (net (code "394") (name "unconnected-(U5B-RSV12-PadG2)") (class "Default")
      (node (ref "U5") (pin "G2") (pinfunction "RSV12_G2") (pintype "input"))
    )
    (net (code "395") (name "unconnected-(U5B-USB_MXO-PadD14)") (class "Default")
      (node (ref "U5") (pin "D14") (pinfunction "USB_MXO_D14") (pintype "output"))
    )
    (net (code "396") (name "unconnected-(U6-ACBUS6-Pad33)") (class "Default")
      (node (ref "U6") (pin "33") (pinfunction "ACBUS6_33") (pintype "bidirectional"))
    )
    (net (code "397") (name "unconnected-(U6-ACBUS7-Pad34)") (class "Default")
      (node (ref "U6") (pin "34") (pinfunction "ACBUS7_34") (pintype "bidirectional"))
    )
    (net (code "398") (name "unconnected-(U6-ADBUS5-Pad22)") (class "Default")
      (node (ref "U6") (pin "22") (pinfunction "ADBUS5_22") (pintype "bidirectional"))
    )
    (net (code "399") (name "unconnected-(U6-BCBUS0-Pad48)") (class "Default")
      (node (ref "U6") (pin "48") (pinfunction "BCBUS0_48") (pintype "bidirectional"))
    )
    (net (code "400") (name "unconnected-(U6-BCBUS1-Pad52)") (class "Default")
      (node (ref "U6") (pin "52") (pinfunction "BCBUS1_52") (pintype "bidirectional"))
    )
    (net (code "401") (name "unconnected-(U6-BCBUS2-Pad53)") (class "Default")
      (node (ref "U6") (pin "53") (pinfunction "BCBUS2_53") (pintype "bidirectional"))
    )
    (net (code "402") (name "unconnected-(U6-BCBUS3-Pad54)") (class "Default")
      (node (ref "U6") (pin "54") (pinfunction "BCBUS3_54") (pintype "bidirectional"))
    )
    (net (code "403") (name "unconnected-(U6-BCBUS4-Pad55)") (class "Default")
      (node (ref "U6") (pin "55") (pinfunction "BCBUS4_55") (pintype "bidirectional"))
    )
    (net (code "404") (name "unconnected-(U6-BCBUS5-Pad57)") (class "Default")
      (node (ref "U6") (pin "57") (pinfunction "BCBUS5_57") (pintype "bidirectional"))
    )
    (net (code "405") (name "unconnected-(U6-BCBUS6-Pad58)") (class "Default")
      (node (ref "U6") (pin "58") (pinfunction "BCBUS6_58") (pintype "bidirectional"))
    )
    (net (code "406") (name "unconnected-(U6-BCBUS7-Pad59)") (class "Default")
      (node (ref "U6") (pin "59") (pinfunction "BCBUS7_59") (pintype "bidirectional"))
    )
    (net (code "407") (name "unconnected-(U6-BDBUS4-Pad43)") (class "Default")
      (node (ref "U6") (pin "43") (pinfunction "BDBUS4_43") (pintype "output"))
    )
    (net (code "408") (name "unconnected-(U6-BDBUS5-Pad44)") (class "Default")
      (node (ref "U6") (pin "44") (pinfunction "BDBUS5_44") (pintype "input"))
    )
    (net (code "409") (name "unconnected-(U6-BDBUS6-Pad45)") (class "Default")
      (node (ref "U6") (pin "45") (pinfunction "BDBUS6_45") (pintype "input"))
    )
    (net (code "410") (name "unconnected-(U6-BDBUS7-Pad46)") (class "Default")
      (node (ref "U6") (pin "46") (pinfunction "BDBUS7_46") (pintype "input"))
    )
    (net (code "411") (name "unconnected-(U6-SUSPEND#-Pad36)") (class "Default")
      (node (ref "U6") (pin "36") (pinfunction "SUSPEND#_36") (pintype "output"))
    )
    (net (code "412") (name "unconnected-(U6-TEST-Pad13)") (class "Default")
      (node (ref "U6") (pin "13") (pinfunction "TEST_13") (pintype "input"))
    )
    (net (code "413") (name "unconnected-(U6-XTOUT-Pad3)") (class "Default")
      (node (ref "U6") (pin "3") (pinfunction "XTOUT_3") (pintype "output"))
    )
    (net (code "414") (name "unconnected-(U7-NC-Pad2)") (class "Default")
      (node (ref "U7") (pin "2") (pinfunction "NC_2") (pintype "no_connect"))
    )
    (net (code "415") (name "unconnected-(U9-2-NC-Pad3)") (class "Default")
      (node (ref "U9-2") (pin "3") (pinfunction "NC_3") (pintype "no_connect"))
    )
    (net (code "416") (name "unconnected-(U9-2-NC-Pad4)") (class "Default")
      (node (ref "U9-2") (pin "4") (pinfunction "NC_4") (pintype "no_connect"))
    )
    (net (code "417") (name "unconnected-(U9-2-NC-Pad5)") (class "Default")
      (node (ref "U9-2") (pin "5") (pinfunction "NC_5") (pintype "no_connect"))
    )
    (net (code "418") (name "unconnected-(U9-2-NC-Pad6)") (class "Default")
      (node (ref "U9-2") (pin "6") (pinfunction "NC_6") (pintype "no_connect"))
    )
    (net (code "419") (name "unconnected-(U9-2-NC-Pad11)") (class "Default")
      (node (ref "U9-2") (pin "11") (pinfunction "NC_11") (pintype "no_connect"))
    )
    (net (code "420") (name "unconnected-(U9-2-NC-Pad12)") (class "Default")
      (node (ref "U9-2") (pin "12") (pinfunction "NC_12") (pintype "no_connect"))
    )
    (net (code "421") (name "unconnected-(U9-2-NC-Pad13)") (class "Default")
      (node (ref "U9-2") (pin "13") (pinfunction "NC_13") (pintype "no_connect"))
    )
    (net (code "422") (name "unconnected-(U9-2-NC-Pad14)") (class "Default")
      (node (ref "U9-2") (pin "14") (pinfunction "NC_14") (pintype "no_connect"))
    )
    (net (code "423") (name "unconnected-(U9-NC-Pad3)") (class "Default")
      (node (ref "U9") (pin "3") (pinfunction "NC_3") (pintype "no_connect"))
    )
    (net (code "424") (name "unconnected-(U9-NC-Pad4)") (class "Default")
      (node (ref "U9") (pin "4") (pinfunction "NC_4") (pintype "no_connect"))
    )
    (net (code "425") (name "unconnected-(U9-NC-Pad5)") (class "Default")
      (node (ref "U9") (pin "5") (pinfunction "NC_5") (pintype "no_connect"))
    )
    (net (code "426") (name "unconnected-(U9-NC-Pad6)") (class "Default")
      (node (ref "U9") (pin "6") (pinfunction "NC_6") (pintype "no_connect"))
    )
    (net (code "427") (name "unconnected-(U9-NC-Pad11)") (class "Default")
      (node (ref "U9") (pin "11") (pinfunction "NC_11") (pintype "no_connect"))
    )
    (net (code "428") (name "unconnected-(U9-NC-Pad12)") (class "Default")
      (node (ref "U9") (pin "12") (pinfunction "NC_12") (pintype "no_connect"))
    )
    (net (code "429") (name "unconnected-(U9-NC-Pad13)") (class "Default")
      (node (ref "U9") (pin "13") (pinfunction "NC_13") (pintype "no_connect"))
    )
    (net (code "430") (name "unconnected-(U9-NC-Pad14)") (class "Default")
      (node (ref "U9") (pin "14") (pinfunction "NC_14") (pintype "no_connect"))
    )
    (net (code "431") (name "unconnected-(U17-GPIO{slash}MFP5_(32)-Pad32)") (class "Default")
      (node (ref "U17") (pin "32") (pinfunction "GPIO/MFP5_(32)_32") (pintype "input"))
    )
    (net (code "432") (name "unconnected-(U17-IN1_L-Pad13)") (class "Default")
      (node (ref "U17") (pin "13") (pinfunction "IN1_L_13") (pintype "input"))
    )
    (net (code "433") (name "unconnected-(U17-IN1_R-Pad14)") (class "Default")
      (node (ref "U17") (pin "14") (pinfunction "IN1_R_14") (pintype "input"))
    )
    (net (code "434") (name "unconnected-(U17-IN3_L-Pad20)") (class "Default")
      (node (ref "U17") (pin "20") (pinfunction "IN3_L_20") (pintype "input"))
    )
    (net (code "435") (name "unconnected-(U17-IN3_R-Pad21)") (class "Default")
      (node (ref "U17") (pin "21") (pinfunction "IN3_R_21") (pintype "input"))
    )
    (net (code "436") (name "unconnected-(U17-MISO{slash}MFP4-Pad11)") (class "Default")
      (node (ref "U17") (pin "11") (pinfunction "MISO/MFP4_11") (pintype "output"))
    )
    (net (code "437") (name "unconnected-(U17-SCLK{slash}MFP3-Pad8)") (class "Default")
      (node (ref "U17") (pin "8") (pinfunction "SCLK/MFP3_8") (pintype "input"))
    )
    (net (code "438") (name "unconnected-(U18-NC-Pad1)") (class "Default")
      (node (ref "U18") (pin "1") (pinfunction "NC_1") (pintype "no_connect"))
    )
  )
)
